# BitFury.net
KiCad netlist of a schematic drawn in Altium Designer
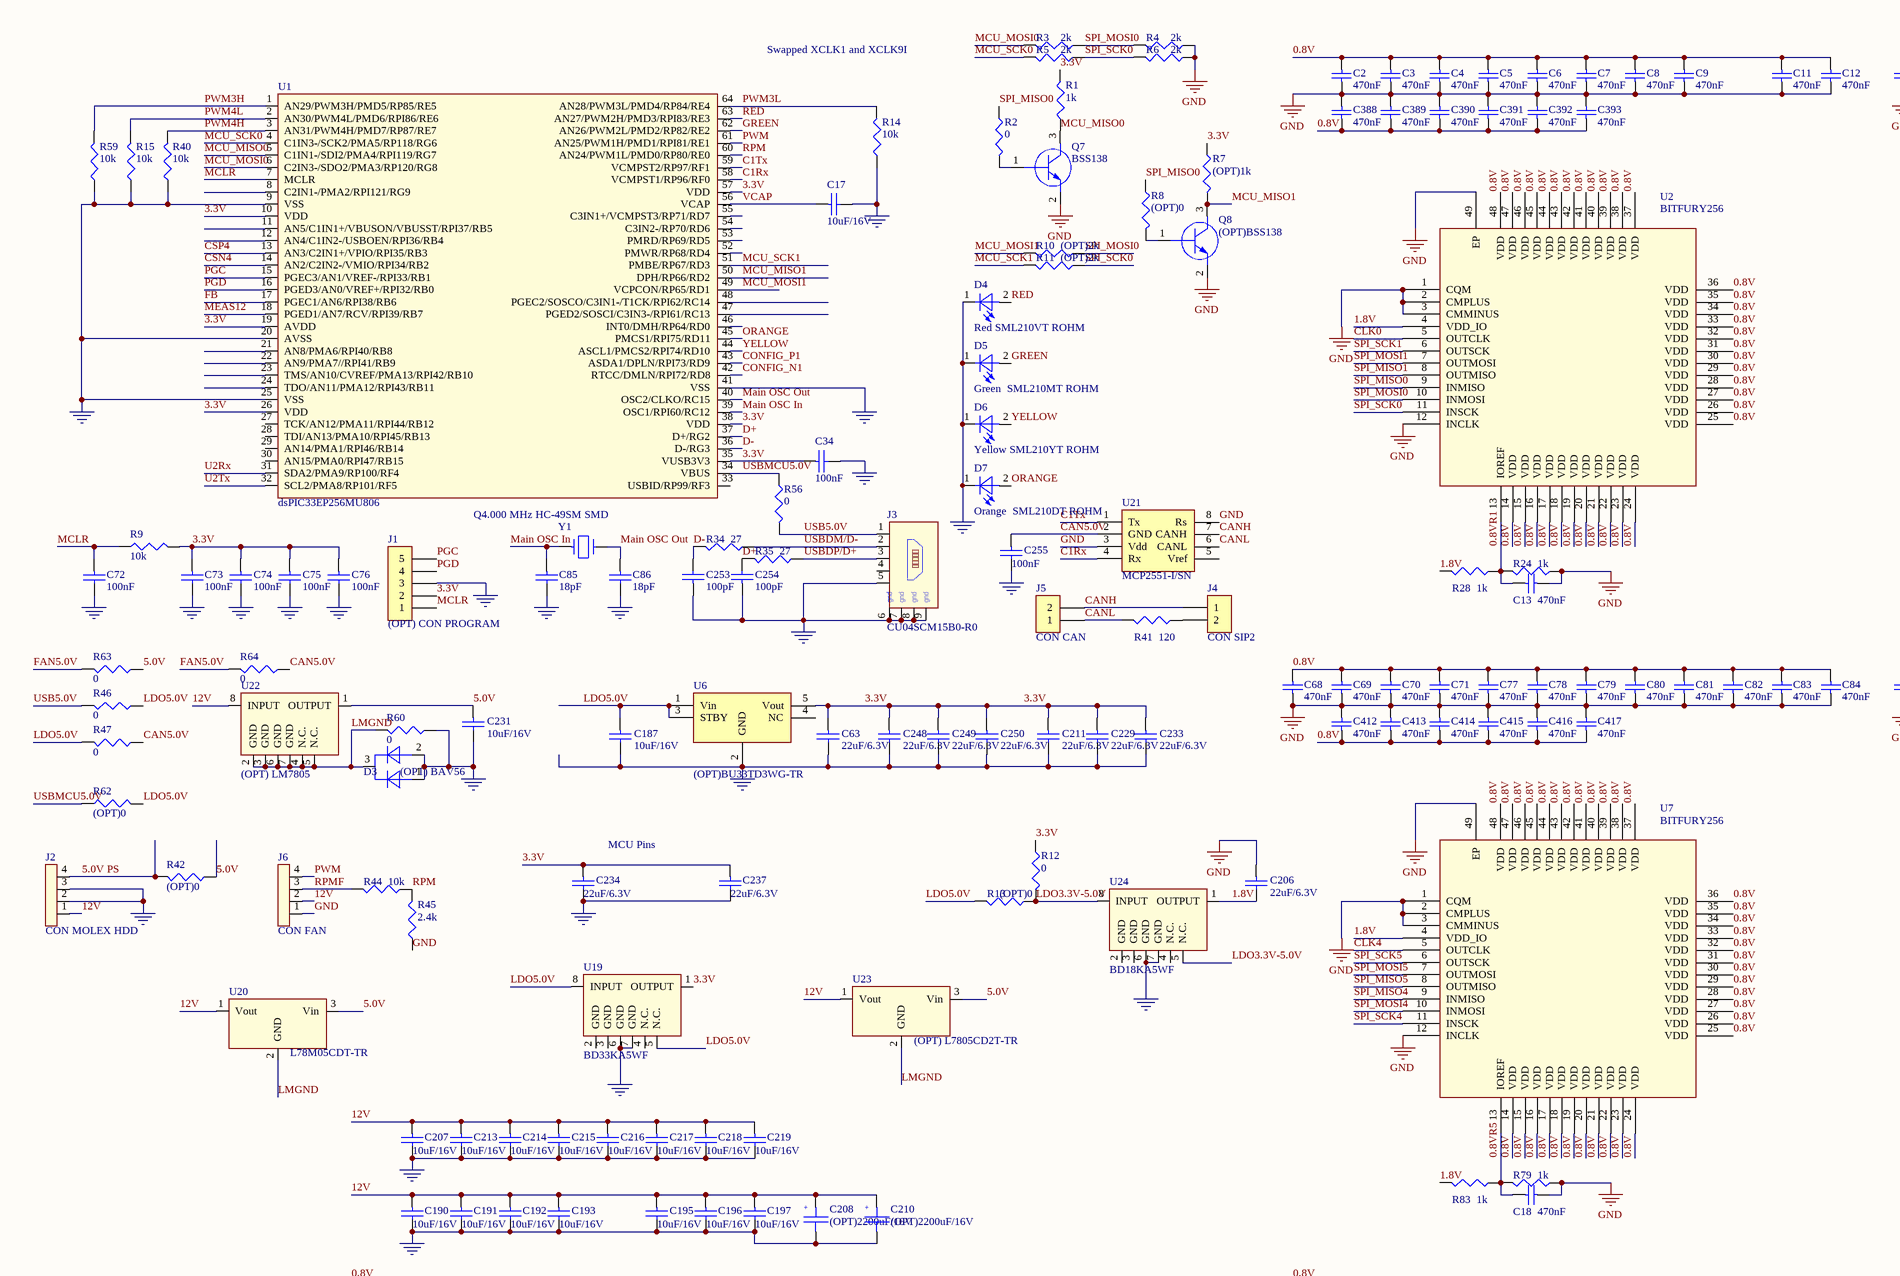
[diagram p0: BitFury.SchDoc, top left]
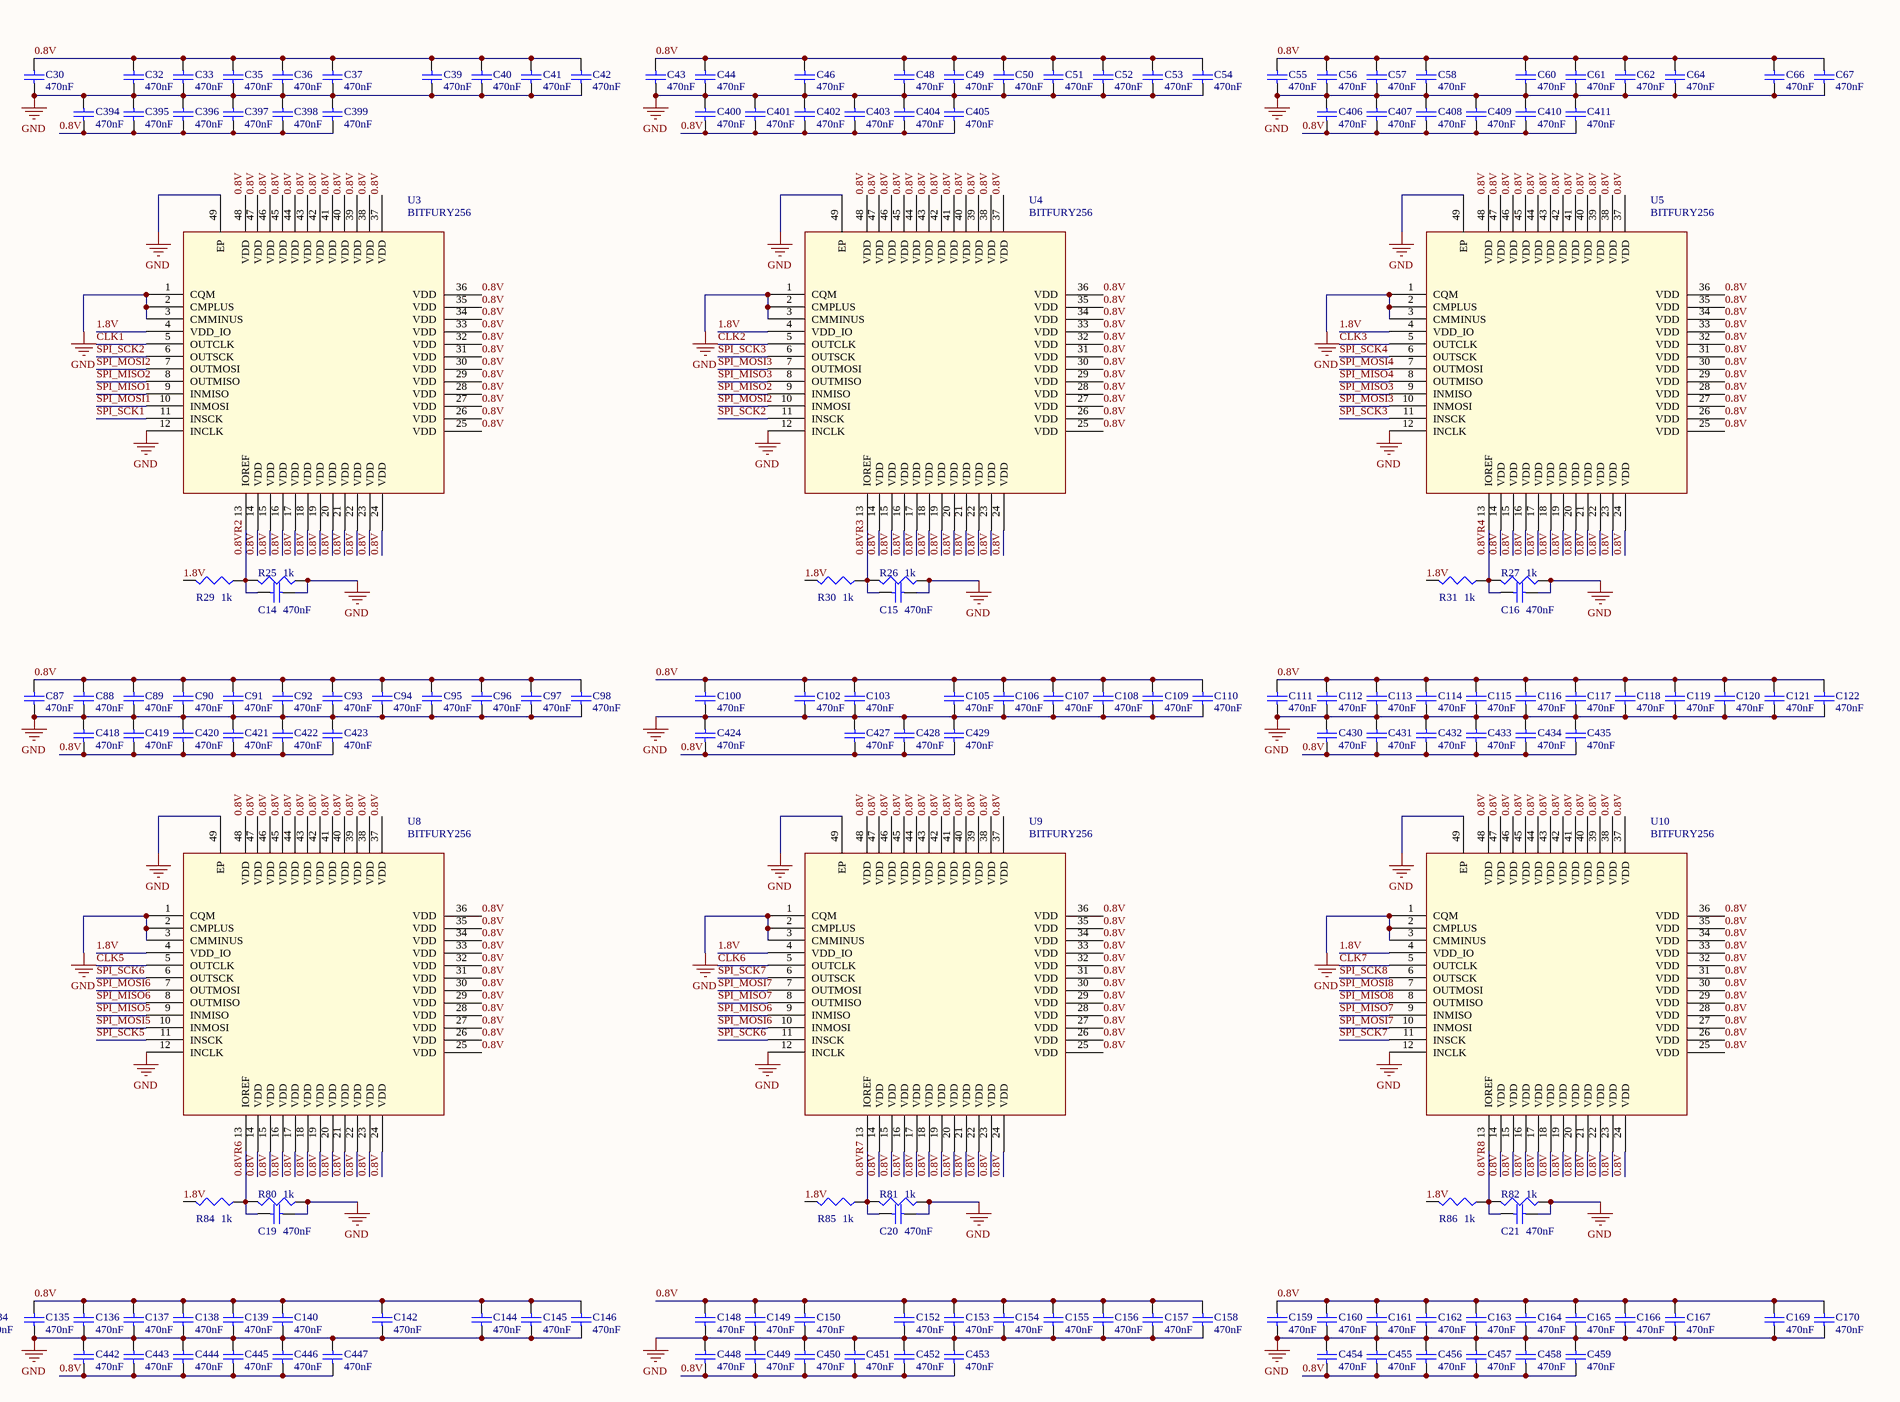
[diagram p1: BitFury.SchDoc, top right]
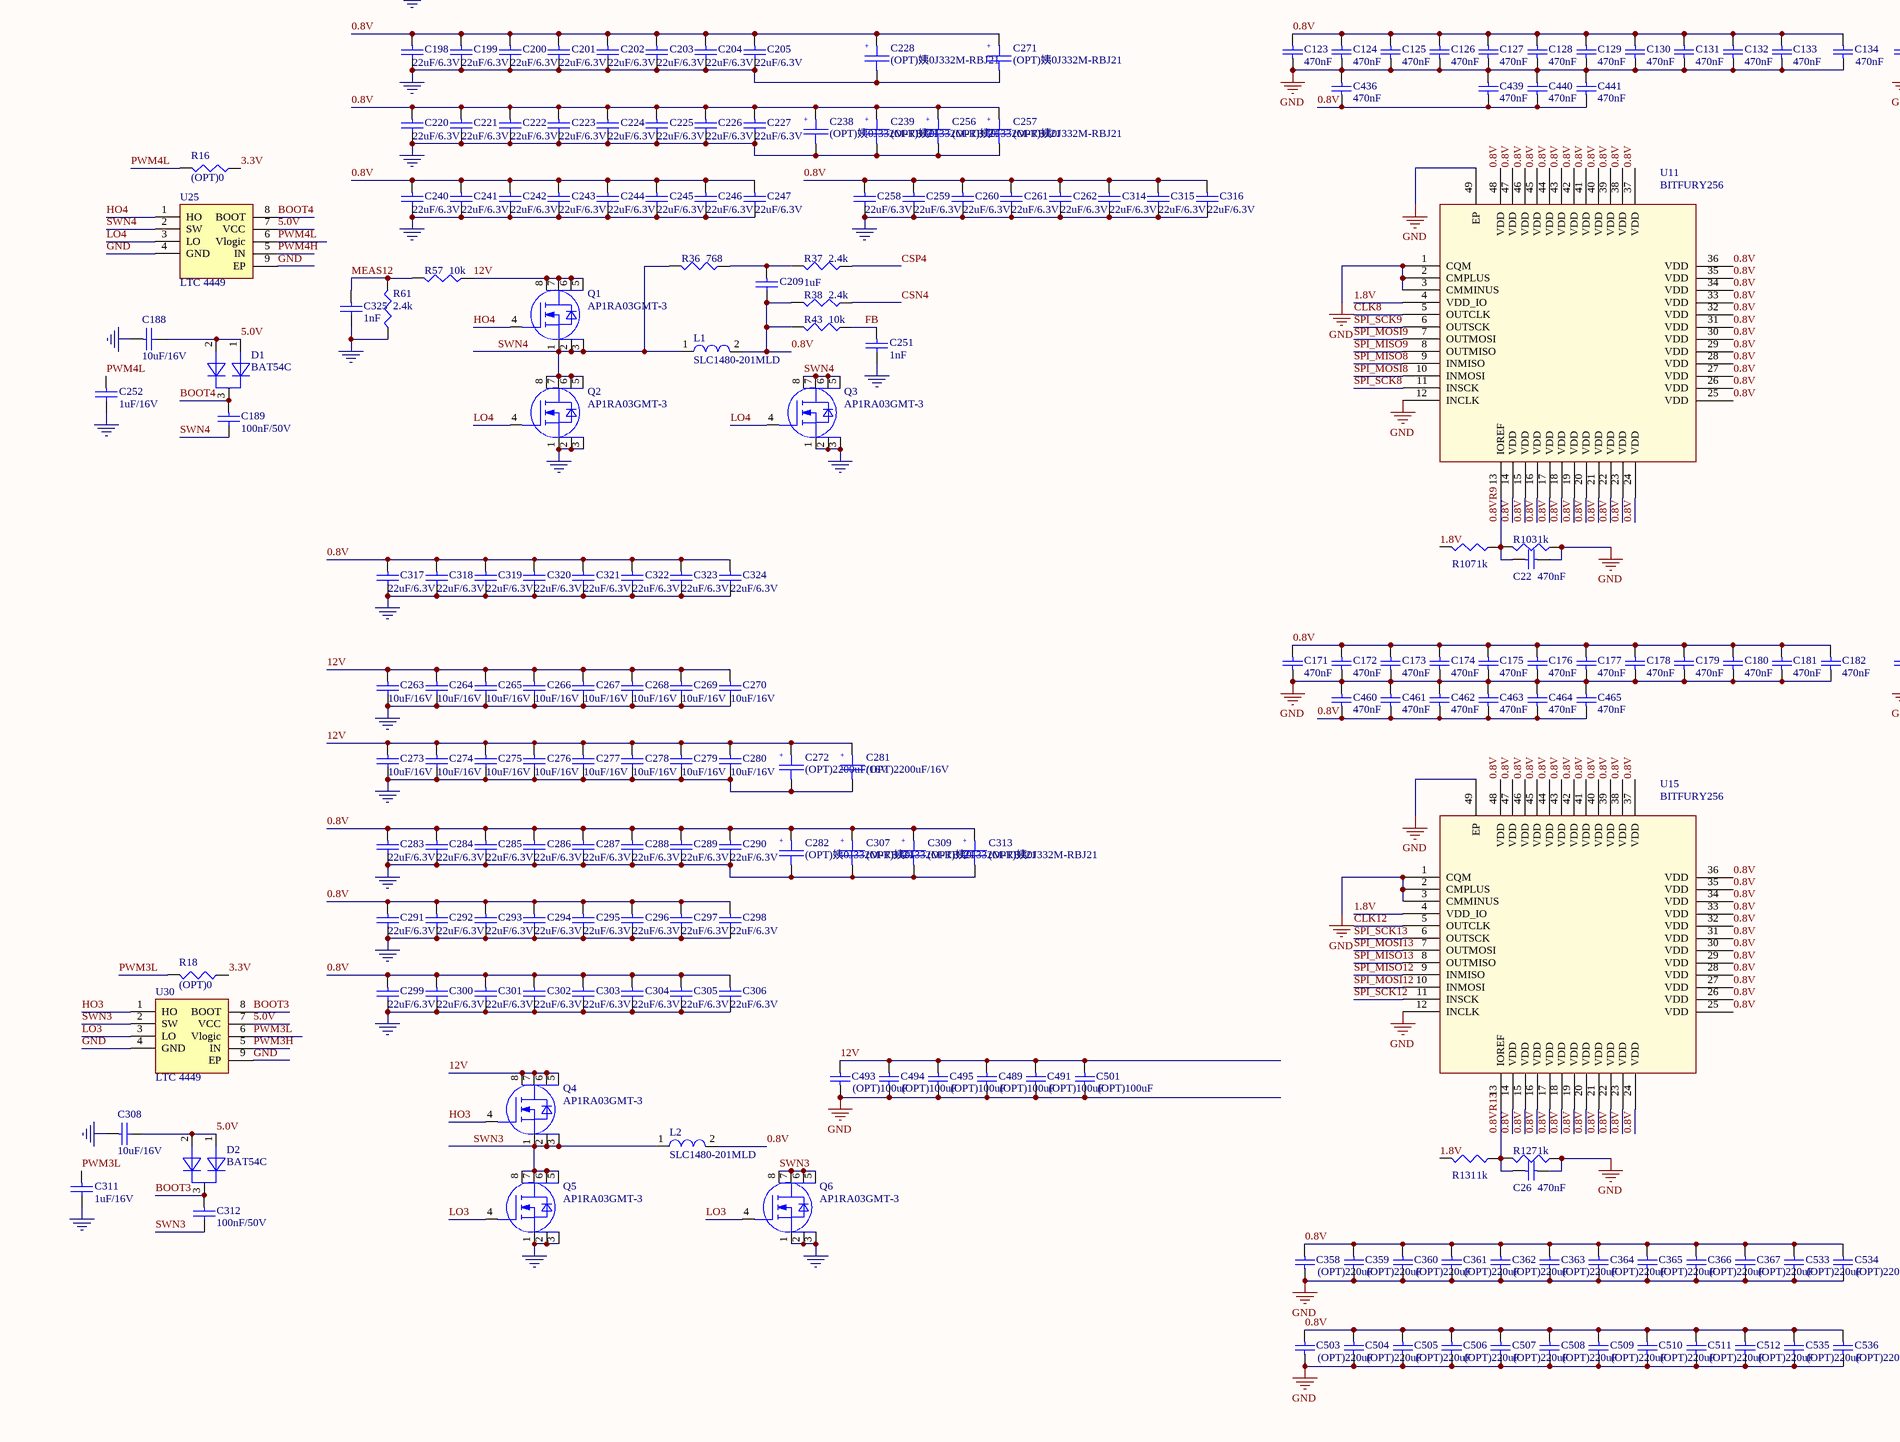
[diagram p2: BitFury.SchDoc, bottom left]
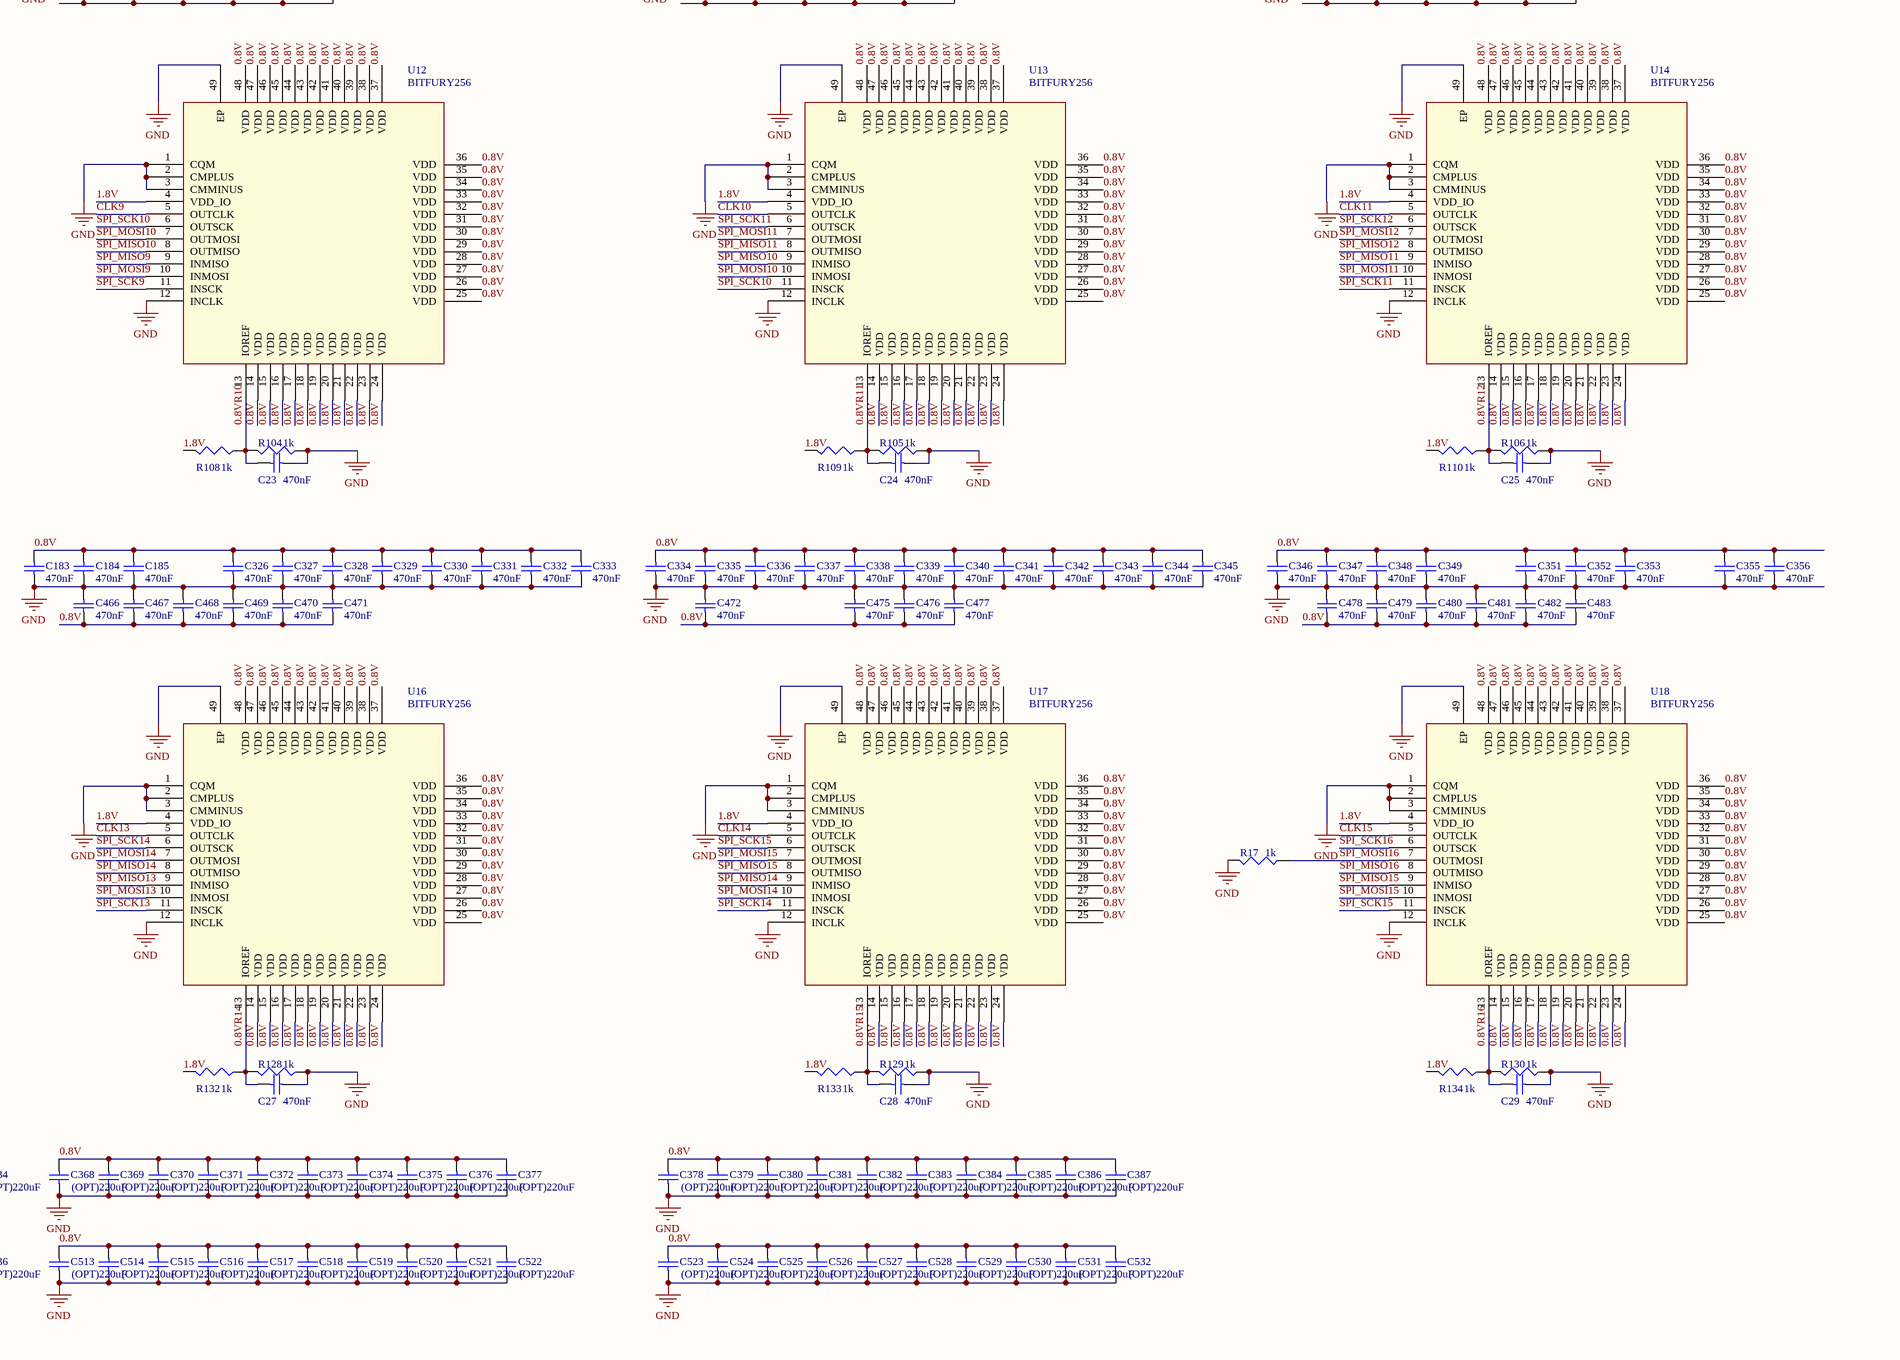
[diagram p3: BitFury.SchDoc, bottom right]

(export (version "E")
  (design (tool "Eeschema 10.0.6"))
  (components
    (comp (ref "C2")
      (value "470nF")
      (footprint "SMD_0603_CAPC1608X80N")
      (description "Capacitor (Semiconductor SIM Model)")
      (fields (field (name "PUBLISHER") "Altium Limited"))
      (libsource (lib "Miscellaneous Devices") (part "Cap Semi"))
    )
    (comp (ref "C3")
      (value "470nF")
      (footprint "SMD_0603_CAPC1608X80N")
      (description "Capacitor (Semiconductor SIM Model)")
      (fields (field (name "PUBLISHER") "Altium Limited"))
      (libsource (lib "Miscellaneous Devices") (part "Cap Semi"))
    )
    (comp (ref "C4")
      (value "470nF")
      (footprint "SMD_0603_CAPC1608X80N")
      (description "Capacitor (Semiconductor SIM Model)")
      (fields (field (name "PUBLISHER") "Altium Limited"))
      (libsource (lib "Miscellaneous Devices") (part "Cap Semi"))
    )
    (comp (ref "C5")
      (value "470nF")
      (footprint "SMD_0603_CAPC1608X80N")
      (description "Capacitor (Semiconductor SIM Model)")
      (fields (field (name "PUBLISHER") "Altium Limited"))
      (libsource (lib "Miscellaneous Devices") (part "Cap Semi"))
    )
    (comp (ref "C6")
      (value "470nF")
      (footprint "SMD_0603_CAPC1608X80N")
      (description "Capacitor (Semiconductor SIM Model)")
      (fields (field (name "PUBLISHER") "Altium Limited"))
      (libsource (lib "Miscellaneous Devices") (part "Cap Semi"))
    )
    (comp (ref "C7")
      (value "470nF")
      (footprint "SMD_0603_CAPC1608X80N")
      (description "Capacitor (Semiconductor SIM Model)")
      (fields (field (name "PUBLISHER") "Altium Limited"))
      (libsource (lib "Miscellaneous Devices") (part "Cap Semi"))
    )
    (comp (ref "C8")
      (value "470nF")
      (footprint "SMD_0603_CAPC1608X80N")
      (description "Capacitor (Semiconductor SIM Model)")
      (fields (field (name "PUBLISHER") "Altium Limited"))
      (libsource (lib "Miscellaneous Devices") (part "Cap Semi"))
    )
    (comp (ref "C9")
      (value "470nF")
      (footprint "SMD_0603_CAPC1608X80N")
      (description "Capacitor (Semiconductor SIM Model)")
      (fields (field (name "PUBLISHER") "Altium Limited"))
      (libsource (lib "Miscellaneous Devices") (part "Cap Semi"))
    )
    (comp (ref "C11")
      (value "470nF")
      (footprint "SMD_0603_CAPC1608X80N")
      (description "Capacitor (Semiconductor SIM Model)")
      (fields (field (name "PUBLISHER") "Altium Limited"))
      (libsource (lib "Miscellaneous Devices") (part "Cap Semi"))
    )
    (comp (ref "C12")
      (value "470nF")
      (footprint "SMD_0603_CAPC1608X80N")
      (description "Capacitor (Semiconductor SIM Model)")
      (fields (field (name "PUBLISHER") "Altium Limited"))
      (libsource (lib "Miscellaneous Devices") (part "Cap Semi"))
    )
    (comp (ref "C13")
      (value "470nF")
      (footprint "SMD_0603_CAPC1608X80N")
      (description "Capacitor (Semiconductor SIM Model)")
      (fields (field (name "PUBLISHER") "Altium Limited"))
      (libsource (lib "Miscellaneous Devices") (part "Cap Semi"))
    )
    (comp (ref "C14")
      (value "470nF")
      (footprint "SMD_0603_CAPC1608X80N")
      (description "Capacitor (Semiconductor SIM Model)")
      (fields (field (name "PUBLISHER") "Altium Limited"))
      (libsource (lib "Miscellaneous Devices") (part "Cap Semi"))
    )
    (comp (ref "C15")
      (value "470nF")
      (footprint "SMD_0603_CAPC1608X80N")
      (description "Capacitor (Semiconductor SIM Model)")
      (fields (field (name "PUBLISHER") "Altium Limited"))
      (libsource (lib "Miscellaneous Devices") (part "Cap Semi"))
    )
    (comp (ref "C16")
      (value "470nF")
      (footprint "SMD_0603_CAPC1608X80N")
      (description "Capacitor (Semiconductor SIM Model)")
      (fields (field (name "PUBLISHER") "Altium Limited"))
      (libsource (lib "Miscellaneous Devices") (part "Cap Semi"))
    )
    (comp (ref "C17")
      (value "10uF/16V")
      (footprint "SMD_0805_CAPC2012X145N")
      (description "Capacitor")
      (libsource (lib "*") (part "CAP"))
    )
    (comp (ref "C18")
      (value "470nF")
      (footprint "SMD_0603_CAPC1608X80N")
      (description "Capacitor (Semiconductor SIM Model)")
      (fields (field (name "PUBLISHER") "Altium Limited"))
      (libsource (lib "Miscellaneous Devices") (part "Cap Semi"))
    )
    (comp (ref "C19")
      (value "470nF")
      (footprint "SMD_0603_CAPC1608X80N")
      (description "Capacitor (Semiconductor SIM Model)")
      (fields (field (name "PUBLISHER") "Altium Limited"))
      (libsource (lib "Miscellaneous Devices") (part "Cap Semi"))
    )
    (comp (ref "C20")
      (value "470nF")
      (footprint "SMD_0603_CAPC1608X80N")
      (description "Capacitor (Semiconductor SIM Model)")
      (fields (field (name "PUBLISHER") "Altium Limited"))
      (libsource (lib "Miscellaneous Devices") (part "Cap Semi"))
    )
    (comp (ref "C21")
      (value "470nF")
      (footprint "SMD_0603_CAPC1608X80N")
      (description "Capacitor (Semiconductor SIM Model)")
      (fields (field (name "PUBLISHER") "Altium Limited"))
      (libsource (lib "Miscellaneous Devices") (part "Cap Semi"))
    )
    (comp (ref "C22")
      (value "470nF")
      (footprint "SMD_0603_CAPC1608X80N")
      (description "Capacitor (Semiconductor SIM Model)")
      (fields (field (name "PUBLISHER") "Altium Limited"))
      (libsource (lib "Miscellaneous Devices") (part "Cap Semi"))
    )
    (comp (ref "C23")
      (value "470nF")
      (footprint "SMD_0603_CAPC1608X80N")
      (description "Capacitor (Semiconductor SIM Model)")
      (fields (field (name "PUBLISHER") "Altium Limited"))
      (libsource (lib "Miscellaneous Devices") (part "Cap Semi"))
    )
    (comp (ref "C24")
      (value "470nF")
      (footprint "SMD_0603_CAPC1608X80N")
      (description "Capacitor (Semiconductor SIM Model)")
      (fields (field (name "PUBLISHER") "Altium Limited"))
      (libsource (lib "Miscellaneous Devices") (part "Cap Semi"))
    )
    (comp (ref "C25")
      (value "470nF")
      (footprint "SMD_0603_CAPC1608X80N")
      (description "Capacitor (Semiconductor SIM Model)")
      (fields (field (name "PUBLISHER") "Altium Limited"))
      (libsource (lib "Miscellaneous Devices") (part "Cap Semi"))
    )
    (comp (ref "C26")
      (value "470nF")
      (footprint "SMD_0603_CAPC1608X80N")
      (description "Capacitor (Semiconductor SIM Model)")
      (fields (field (name "PUBLISHER") "Altium Limited"))
      (libsource (lib "Miscellaneous Devices") (part "Cap Semi"))
    )
    (comp (ref "C27")
      (value "470nF")
      (footprint "SMD_0603_CAPC1608X80N")
      (description "Capacitor (Semiconductor SIM Model)")
      (fields (field (name "PUBLISHER") "Altium Limited"))
      (libsource (lib "Miscellaneous Devices") (part "Cap Semi"))
    )
    (comp (ref "C28")
      (value "470nF")
      (footprint "SMD_0603_CAPC1608X80N")
      (description "Capacitor (Semiconductor SIM Model)")
      (fields (field (name "PUBLISHER") "Altium Limited"))
      (libsource (lib "Miscellaneous Devices") (part "Cap Semi"))
    )
    (comp (ref "C29")
      (value "470nF")
      (footprint "SMD_0603_CAPC1608X80N")
      (description "Capacitor (Semiconductor SIM Model)")
      (fields (field (name "PUBLISHER") "Altium Limited"))
      (libsource (lib "Miscellaneous Devices") (part "Cap Semi"))
    )
    (comp (ref "C30")
      (value "470nF")
      (footprint "SMD_0603_CAPC1608X80N")
      (description "Capacitor (Semiconductor SIM Model)")
      (fields (field (name "PUBLISHER") "Altium Limited"))
      (libsource (lib "Miscellaneous Devices") (part "Cap Semi"))
    )
    (comp (ref "C32")
      (value "470nF")
      (footprint "SMD_0603_CAPC1608X80N")
      (description "Capacitor (Semiconductor SIM Model)")
      (fields (field (name "PUBLISHER") "Altium Limited"))
      (libsource (lib "Miscellaneous Devices") (part "Cap Semi"))
    )
    (comp (ref "C33")
      (value "470nF")
      (footprint "SMD_0603_CAPC1608X80N")
      (description "Capacitor (Semiconductor SIM Model)")
      (fields (field (name "PUBLISHER") "Altium Limited"))
      (libsource (lib "Miscellaneous Devices") (part "Cap Semi"))
    )
    (comp (ref "C34")
      (value "100nF")
      (footprint "SMD_0603_CAPC1608X80N")
      (description "Capacitor")
      (libsource (lib "*") (part "CAP"))
    )
    (comp (ref "C35")
      (value "470nF")
      (footprint "SMD_0603_CAPC1608X80N")
      (description "Capacitor (Semiconductor SIM Model)")
      (fields (field (name "PUBLISHER") "Altium Limited"))
      (libsource (lib "Miscellaneous Devices") (part "Cap Semi"))
    )
    (comp (ref "C36")
      (value "470nF")
      (footprint "SMD_0603_CAPC1608X80N")
      (description "Capacitor (Semiconductor SIM Model)")
      (fields (field (name "PUBLISHER") "Altium Limited"))
      (libsource (lib "Miscellaneous Devices") (part "Cap Semi"))
    )
    (comp (ref "C37")
      (value "470nF")
      (footprint "SMD_0603_CAPC1608X80N")
      (description "Capacitor (Semiconductor SIM Model)")
      (fields (field (name "PUBLISHER") "Altium Limited"))
      (libsource (lib "Miscellaneous Devices") (part "Cap Semi"))
    )
    (comp (ref "C39")
      (value "470nF")
      (footprint "SMD_0603_CAPC1608X80N")
      (description "Capacitor (Semiconductor SIM Model)")
      (fields (field (name "PUBLISHER") "Altium Limited"))
      (libsource (lib "Miscellaneous Devices") (part "Cap Semi"))
    )
    (comp (ref "C40")
      (value "470nF")
      (footprint "SMD_0603_CAPC1608X80N")
      (description "Capacitor (Semiconductor SIM Model)")
      (fields (field (name "PUBLISHER") "Altium Limited"))
      (libsource (lib "Miscellaneous Devices") (part "Cap Semi"))
    )
    (comp (ref "C41")
      (value "470nF")
      (footprint "SMD_0603_CAPC1608X80N")
      (description "Capacitor (Semiconductor SIM Model)")
      (fields (field (name "PUBLISHER") "Altium Limited"))
      (libsource (lib "Miscellaneous Devices") (part "Cap Semi"))
    )
    (comp (ref "C42")
      (value "470nF")
      (footprint "SMD_0603_CAPC1608X80N")
      (description "Capacitor (Semiconductor SIM Model)")
      (fields (field (name "PUBLISHER") "Altium Limited"))
      (libsource (lib "Miscellaneous Devices") (part "Cap Semi"))
    )
    (comp (ref "C43")
      (value "470nF")
      (footprint "SMD_0603_CAPC1608X80N")
      (description "Capacitor (Semiconductor SIM Model)")
      (fields (field (name "PUBLISHER") "Altium Limited"))
      (libsource (lib "Miscellaneous Devices") (part "Cap Semi"))
    )
    (comp (ref "C44")
      (value "470nF")
      (footprint "SMD_0603_CAPC1608X80N")
      (description "Capacitor (Semiconductor SIM Model)")
      (fields (field (name "PUBLISHER") "Altium Limited"))
      (libsource (lib "Miscellaneous Devices") (part "Cap Semi"))
    )
    (comp (ref "C46")
      (value "470nF")
      (footprint "SMD_0603_CAPC1608X80N")
      (description "Capacitor (Semiconductor SIM Model)")
      (fields (field (name "PUBLISHER") "Altium Limited"))
      (libsource (lib "Miscellaneous Devices") (part "Cap Semi"))
    )
    (comp (ref "C48")
      (value "470nF")
      (footprint "SMD_0603_CAPC1608X80N")
      (description "Capacitor (Semiconductor SIM Model)")
      (fields (field (name "PUBLISHER") "Altium Limited"))
      (libsource (lib "Miscellaneous Devices") (part "Cap Semi"))
    )
    (comp (ref "C49")
      (value "470nF")
      (footprint "SMD_0603_CAPC1608X80N")
      (description "Capacitor (Semiconductor SIM Model)")
      (fields (field (name "PUBLISHER") "Altium Limited"))
      (libsource (lib "Miscellaneous Devices") (part "Cap Semi"))
    )
    (comp (ref "C50")
      (value "470nF")
      (footprint "SMD_0603_CAPC1608X80N")
      (description "Capacitor (Semiconductor SIM Model)")
      (fields (field (name "PUBLISHER") "Altium Limited"))
      (libsource (lib "Miscellaneous Devices") (part "Cap Semi"))
    )
    (comp (ref "C51")
      (value "470nF")
      (footprint "SMD_0603_CAPC1608X80N")
      (description "Capacitor (Semiconductor SIM Model)")
      (fields (field (name "PUBLISHER") "Altium Limited"))
      (libsource (lib "Miscellaneous Devices") (part "Cap Semi"))
    )
    (comp (ref "C52")
      (value "470nF")
      (footprint "SMD_0603_CAPC1608X80N")
      (description "Capacitor (Semiconductor SIM Model)")
      (fields (field (name "PUBLISHER") "Altium Limited"))
      (libsource (lib "Miscellaneous Devices") (part "Cap Semi"))
    )
    (comp (ref "C53")
      (value "470nF")
      (footprint "SMD_0603_CAPC1608X80N")
      (description "Capacitor (Semiconductor SIM Model)")
      (fields (field (name "PUBLISHER") "Altium Limited"))
      (libsource (lib "Miscellaneous Devices") (part "Cap Semi"))
    )
    (comp (ref "C54")
      (value "470nF")
      (footprint "SMD_0603_CAPC1608X80N")
      (description "Capacitor (Semiconductor SIM Model)")
      (fields (field (name "PUBLISHER") "Altium Limited"))
      (libsource (lib "Miscellaneous Devices") (part "Cap Semi"))
    )
    (comp (ref "C55")
      (value "470nF")
      (footprint "SMD_0603_CAPC1608X80N")
      (description "Capacitor (Semiconductor SIM Model)")
      (fields (field (name "PUBLISHER") "Altium Limited"))
      (libsource (lib "Miscellaneous Devices") (part "Cap Semi"))
    )
    (comp (ref "C56")
      (value "470nF")
      (footprint "SMD_0603_CAPC1608X80N")
      (description "Capacitor (Semiconductor SIM Model)")
      (fields (field (name "PUBLISHER") "Altium Limited"))
      (libsource (lib "Miscellaneous Devices") (part "Cap Semi"))
    )
    (comp (ref "C57")
      (value "470nF")
      (footprint "SMD_0603_CAPC1608X80N")
      (description "Capacitor (Semiconductor SIM Model)")
      (fields (field (name "PUBLISHER") "Altium Limited"))
      (libsource (lib "Miscellaneous Devices") (part "Cap Semi"))
    )
    (comp (ref "C58")
      (value "470nF")
      (footprint "SMD_0603_CAPC1608X80N")
      (description "Capacitor (Semiconductor SIM Model)")
      (fields (field (name "PUBLISHER") "Altium Limited"))
      (libsource (lib "Miscellaneous Devices") (part "Cap Semi"))
    )
    (comp (ref "C60")
      (value "470nF")
      (footprint "SMD_0603_CAPC1608X80N")
      (description "Capacitor (Semiconductor SIM Model)")
      (fields (field (name "PUBLISHER") "Altium Limited"))
      (libsource (lib "Miscellaneous Devices") (part "Cap Semi"))
    )
    (comp (ref "C61")
      (value "470nF")
      (footprint "SMD_0603_CAPC1608X80N")
      (description "Capacitor (Semiconductor SIM Model)")
      (fields (field (name "PUBLISHER") "Altium Limited"))
      (libsource (lib "Miscellaneous Devices") (part "Cap Semi"))
    )
    (comp (ref "C62")
      (value "470nF")
      (footprint "SMD_0603_CAPC1608X80N")
      (description "Capacitor (Semiconductor SIM Model)")
      (fields (field (name "PUBLISHER") "Altium Limited"))
      (libsource (lib "Miscellaneous Devices") (part "Cap Semi"))
    )
    (comp (ref "C63")
      (value "22uF/6.3V")
      (footprint "SMD_0805_CAPC2012X145N")
      (description "Capacitor")
      (libsource (lib "*") (part "CAP"))
    )
    (comp (ref "C64")
      (value "470nF")
      (footprint "SMD_0603_CAPC1608X80N")
      (description "Capacitor (Semiconductor SIM Model)")
      (fields (field (name "PUBLISHER") "Altium Limited"))
      (libsource (lib "Miscellaneous Devices") (part "Cap Semi"))
    )
    (comp (ref "C66")
      (value "470nF")
      (footprint "SMD_0603_CAPC1608X80N")
      (description "Capacitor (Semiconductor SIM Model)")
      (fields (field (name "PUBLISHER") "Altium Limited"))
      (libsource (lib "Miscellaneous Devices") (part "Cap Semi"))
    )
    (comp (ref "C67")
      (value "470nF")
      (footprint "SMD_0603_CAPC1608X80N")
      (description "Capacitor (Semiconductor SIM Model)")
      (fields (field (name "PUBLISHER") "Altium Limited"))
      (libsource (lib "Miscellaneous Devices") (part "Cap Semi"))
    )
    (comp (ref "C68")
      (value "470nF")
      (footprint "SMD_0603_CAPC1608X80N")
      (description "Capacitor (Semiconductor SIM Model)")
      (fields (field (name "PUBLISHER") "Altium Limited"))
      (libsource (lib "Miscellaneous Devices") (part "Cap Semi"))
    )
    (comp (ref "C69")
      (value "470nF")
      (footprint "SMD_0603_CAPC1608X80N")
      (description "Capacitor (Semiconductor SIM Model)")
      (fields (field (name "PUBLISHER") "Altium Limited"))
      (libsource (lib "Miscellaneous Devices") (part "Cap Semi"))
    )
    (comp (ref "C70")
      (value "470nF")
      (footprint "SMD_0603_CAPC1608X80N")
      (description "Capacitor (Semiconductor SIM Model)")
      (fields (field (name "PUBLISHER") "Altium Limited"))
      (libsource (lib "Miscellaneous Devices") (part "Cap Semi"))
    )
    (comp (ref "C71")
      (value "470nF")
      (footprint "SMD_0603_CAPC1608X80N")
      (description "Capacitor (Semiconductor SIM Model)")
      (fields (field (name "PUBLISHER") "Altium Limited"))
      (libsource (lib "Miscellaneous Devices") (part "Cap Semi"))
    )
    (comp (ref "C72")
      (value "100nF")
      (footprint "SMD_0603_CAPC1608X80N")
      (description "Capacitor")
      (libsource (lib "*") (part "CAP"))
    )
    (comp (ref "C73")
      (value "100nF")
      (footprint "SMD_0603_CAPC1608X80N")
      (description "Capacitor")
      (libsource (lib "*") (part "CAP"))
    )
    (comp (ref "C74")
      (value "100nF")
      (footprint "SMD_0603_CAPC1608X80N")
      (description "Capacitor")
      (libsource (lib "*") (part "CAP"))
    )
    (comp (ref "C75")
      (value "100nF")
      (footprint "SMD_0603_CAPC1608X80N")
      (description "Capacitor")
      (libsource (lib "*") (part "CAP"))
    )
    (comp (ref "C76")
      (value "100nF")
      (footprint "SMD_0603_CAPC1608X80N")
      (description "Capacitor")
      (libsource (lib "*") (part "CAP"))
    )
    (comp (ref "C77")
      (value "470nF")
      (footprint "SMD_0603_CAPC1608X80N")
      (description "Capacitor (Semiconductor SIM Model)")
      (fields (field (name "PUBLISHER") "Altium Limited"))
      (libsource (lib "Miscellaneous Devices") (part "Cap Semi"))
    )
    (comp (ref "C78")
      (value "470nF")
      (footprint "SMD_0603_CAPC1608X80N")
      (description "Capacitor (Semiconductor SIM Model)")
      (fields (field (name "PUBLISHER") "Altium Limited"))
      (libsource (lib "Miscellaneous Devices") (part "Cap Semi"))
    )
    (comp (ref "C79")
      (value "470nF")
      (footprint "SMD_0603_CAPC1608X80N")
      (description "Capacitor (Semiconductor SIM Model)")
      (fields (field (name "PUBLISHER") "Altium Limited"))
      (libsource (lib "Miscellaneous Devices") (part "Cap Semi"))
    )
    (comp (ref "C80")
      (value "470nF")
      (footprint "SMD_0603_CAPC1608X80N")
      (description "Capacitor (Semiconductor SIM Model)")
      (fields (field (name "PUBLISHER") "Altium Limited"))
      (libsource (lib "Miscellaneous Devices") (part "Cap Semi"))
    )
    (comp (ref "C81")
      (value "470nF")
      (footprint "SMD_0603_CAPC1608X80N")
      (description "Capacitor (Semiconductor SIM Model)")
      (fields (field (name "PUBLISHER") "Altium Limited"))
      (libsource (lib "Miscellaneous Devices") (part "Cap Semi"))
    )
    (comp (ref "C82")
      (value "470nF")
      (footprint "SMD_0603_CAPC1608X80N")
      (description "Capacitor (Semiconductor SIM Model)")
      (fields (field (name "PUBLISHER") "Altium Limited"))
      (libsource (lib "Miscellaneous Devices") (part "Cap Semi"))
    )
    (comp (ref "C83")
      (value "470nF")
      (footprint "SMD_0603_CAPC1608X80N")
      (description "Capacitor (Semiconductor SIM Model)")
      (fields (field (name "PUBLISHER") "Altium Limited"))
      (libsource (lib "Miscellaneous Devices") (part "Cap Semi"))
    )
    (comp (ref "C84")
      (value "470nF")
      (footprint "SMD_0603_CAPC1608X80N")
      (description "Capacitor (Semiconductor SIM Model)")
      (fields (field (name "PUBLISHER") "Altium Limited"))
      (libsource (lib "Miscellaneous Devices") (part "Cap Semi"))
    )
    (comp (ref "C85")
      (value "18pF")
      (footprint "SMD_0603_CAPC1608X80N")
      (description "Capacitor")
      (libsource (lib "*") (part "CAP"))
    )
    (comp (ref "C86")
      (value "18pF")
      (footprint "SMD_0603_CAPC1608X80N")
      (description "Capacitor")
      (libsource (lib "*") (part "CAP"))
    )
    (comp (ref "C87")
      (value "470nF")
      (footprint "SMD_0603_CAPC1608X80N")
      (description "Capacitor (Semiconductor SIM Model)")
      (fields (field (name "PUBLISHER") "Altium Limited"))
      (libsource (lib "Miscellaneous Devices") (part "Cap Semi"))
    )
    (comp (ref "C88")
      (value "470nF")
      (footprint "SMD_0603_CAPC1608X80N")
      (description "Capacitor (Semiconductor SIM Model)")
      (fields (field (name "PUBLISHER") "Altium Limited"))
      (libsource (lib "Miscellaneous Devices") (part "Cap Semi"))
    )
    (comp (ref "C89")
      (value "470nF")
      (footprint "SMD_0603_CAPC1608X80N")
      (description "Capacitor (Semiconductor SIM Model)")
      (fields (field (name "PUBLISHER") "Altium Limited"))
      (libsource (lib "Miscellaneous Devices") (part "Cap Semi"))
    )
    (comp (ref "C90")
      (value "470nF")
      (footprint "SMD_0603_CAPC1608X80N")
      (description "Capacitor (Semiconductor SIM Model)")
      (fields (field (name "PUBLISHER") "Altium Limited"))
      (libsource (lib "Miscellaneous Devices") (part "Cap Semi"))
    )
    (comp (ref "C91")
      (value "470nF")
      (footprint "SMD_0603_CAPC1608X80N")
      (description "Capacitor (Semiconductor SIM Model)")
      (fields (field (name "PUBLISHER") "Altium Limited"))
      (libsource (lib "Miscellaneous Devices") (part "Cap Semi"))
    )
    (comp (ref "C92")
      (value "470nF")
      (footprint "SMD_0603_CAPC1608X80N")
      (description "Capacitor (Semiconductor SIM Model)")
      (fields (field (name "PUBLISHER") "Altium Limited"))
      (libsource (lib "Miscellaneous Devices") (part "Cap Semi"))
    )
    (comp (ref "C93")
      (value "470nF")
      (footprint "SMD_0603_CAPC1608X80N")
      (description "Capacitor (Semiconductor SIM Model)")
      (fields (field (name "PUBLISHER") "Altium Limited"))
      (libsource (lib "Miscellaneous Devices") (part "Cap Semi"))
    )
    (comp (ref "C94")
      (value "470nF")
      (footprint "SMD_0603_CAPC1608X80N")
      (description "Capacitor (Semiconductor SIM Model)")
      (fields (field (name "PUBLISHER") "Altium Limited"))
      (libsource (lib "Miscellaneous Devices") (part "Cap Semi"))
    )
    (comp (ref "C95")
      (value "470nF")
      (footprint "SMD_0603_CAPC1608X80N")
      (description "Capacitor (Semiconductor SIM Model)")
      (fields (field (name "PUBLISHER") "Altium Limited"))
      (libsource (lib "Miscellaneous Devices") (part "Cap Semi"))
    )
    (comp (ref "C96")
      (value "470nF")
      (footprint "SMD_0603_CAPC1608X80N")
      (description "Capacitor (Semiconductor SIM Model)")
      (fields (field (name "PUBLISHER") "Altium Limited"))
      (libsource (lib "Miscellaneous Devices") (part "Cap Semi"))
    )
    (comp (ref "C97")
      (value "470nF")
      (footprint "SMD_0603_CAPC1608X80N")
      (description "Capacitor (Semiconductor SIM Model)")
      (fields (field (name "PUBLISHER") "Altium Limited"))
      (libsource (lib "Miscellaneous Devices") (part "Cap Semi"))
    )
    (comp (ref "C98")
      (value "470nF")
      (footprint "SMD_0603_CAPC1608X80N")
      (description "Capacitor (Semiconductor SIM Model)")
      (fields (field (name "PUBLISHER") "Altium Limited"))
      (libsource (lib "Miscellaneous Devices") (part "Cap Semi"))
    )
    (comp (ref "C100")
      (value "470nF")
      (footprint "SMD_0603_CAPC1608X80N")
      (description "Capacitor (Semiconductor SIM Model)")
      (fields (field (name "PUBLISHER") "Altium Limited"))
      (libsource (lib "Miscellaneous Devices") (part "Cap Semi"))
    )
    (comp (ref "C102")
      (value "470nF")
      (footprint "SMD_0603_CAPC1608X80N")
      (description "Capacitor (Semiconductor SIM Model)")
      (fields (field (name "PUBLISHER") "Altium Limited"))
      (libsource (lib "Miscellaneous Devices") (part "Cap Semi"))
    )
    (comp (ref "C103")
      (value "470nF")
      (footprint "SMD_0603_CAPC1608X80N")
      (description "Capacitor (Semiconductor SIM Model)")
      (fields (field (name "PUBLISHER") "Altium Limited"))
      (libsource (lib "Miscellaneous Devices") (part "Cap Semi"))
    )
    (comp (ref "C105")
      (value "470nF")
      (footprint "SMD_0603_CAPC1608X80N")
      (description "Capacitor (Semiconductor SIM Model)")
      (fields (field (name "PUBLISHER") "Altium Limited"))
      (libsource (lib "Miscellaneous Devices") (part "Cap Semi"))
    )
    (comp (ref "C106")
      (value "470nF")
      (footprint "SMD_0603_CAPC1608X80N")
      (description "Capacitor (Semiconductor SIM Model)")
      (fields (field (name "PUBLISHER") "Altium Limited"))
      (libsource (lib "Miscellaneous Devices") (part "Cap Semi"))
    )
    (comp (ref "C107")
      (value "470nF")
      (footprint "SMD_0603_CAPC1608X80N")
      (description "Capacitor (Semiconductor SIM Model)")
      (fields (field (name "PUBLISHER") "Altium Limited"))
      (libsource (lib "Miscellaneous Devices") (part "Cap Semi"))
    )
    (comp (ref "C108")
      (value "470nF")
      (footprint "SMD_0603_CAPC1608X80N")
      (description "Capacitor (Semiconductor SIM Model)")
      (fields (field (name "PUBLISHER") "Altium Limited"))
      (libsource (lib "Miscellaneous Devices") (part "Cap Semi"))
    )
    (comp (ref "C109")
      (value "470nF")
      (footprint "SMD_0603_CAPC1608X80N")
      (description "Capacitor (Semiconductor SIM Model)")
      (fields (field (name "PUBLISHER") "Altium Limited"))
      (libsource (lib "Miscellaneous Devices") (part "Cap Semi"))
    )
    (comp (ref "C110")
      (value "470nF")
      (footprint "SMD_0603_CAPC1608X80N")
      (description "Capacitor (Semiconductor SIM Model)")
      (fields (field (name "PUBLISHER") "Altium Limited"))
      (libsource (lib "Miscellaneous Devices") (part "Cap Semi"))
    )
    (comp (ref "C111")
      (value "470nF")
      (footprint "SMD_0603_CAPC1608X80N")
      (description "Capacitor (Semiconductor SIM Model)")
      (fields (field (name "PUBLISHER") "Altium Limited"))
      (libsource (lib "Miscellaneous Devices") (part "Cap Semi"))
    )
    (comp (ref "C112")
      (value "470nF")
      (footprint "SMD_0603_CAPC1608X80N")
      (description "Capacitor (Semiconductor SIM Model)")
      (fields (field (name "PUBLISHER") "Altium Limited"))
      (libsource (lib "Miscellaneous Devices") (part "Cap Semi"))
    )
    (comp (ref "C113")
      (value "470nF")
      (footprint "SMD_0603_CAPC1608X80N")
      (description "Capacitor (Semiconductor SIM Model)")
      (fields (field (name "PUBLISHER") "Altium Limited"))
      (libsource (lib "Miscellaneous Devices") (part "Cap Semi"))
    )
    (comp (ref "C114")
      (value "470nF")
      (footprint "SMD_0603_CAPC1608X80N")
      (description "Capacitor (Semiconductor SIM Model)")
      (fields (field (name "PUBLISHER") "Altium Limited"))
      (libsource (lib "Miscellaneous Devices") (part "Cap Semi"))
    )
    (comp (ref "C115")
      (value "470nF")
      (footprint "SMD_0603_CAPC1608X80N")
      (description "Capacitor (Semiconductor SIM Model)")
      (fields (field (name "PUBLISHER") "Altium Limited"))
      (libsource (lib "Miscellaneous Devices") (part "Cap Semi"))
    )
    (comp (ref "C116")
      (value "470nF")
      (footprint "SMD_0603_CAPC1608X80N")
      (description "Capacitor (Semiconductor SIM Model)")
      (fields (field (name "PUBLISHER") "Altium Limited"))
      (libsource (lib "Miscellaneous Devices") (part "Cap Semi"))
    )
    (comp (ref "C117")
      (value "470nF")
      (footprint "SMD_0603_CAPC1608X80N")
      (description "Capacitor (Semiconductor SIM Model)")
      (fields (field (name "PUBLISHER") "Altium Limited"))
      (libsource (lib "Miscellaneous Devices") (part "Cap Semi"))
    )
    (comp (ref "C118")
      (value "470nF")
      (footprint "SMD_0603_CAPC1608X80N")
      (description "Capacitor (Semiconductor SIM Model)")
      (fields (field (name "PUBLISHER") "Altium Limited"))
      (libsource (lib "Miscellaneous Devices") (part "Cap Semi"))
    )
    (comp (ref "C119")
      (value "470nF")
      (footprint "SMD_0603_CAPC1608X80N")
      (description "Capacitor (Semiconductor SIM Model)")
      (fields (field (name "PUBLISHER") "Altium Limited"))
      (libsource (lib "Miscellaneous Devices") (part "Cap Semi"))
    )
    (comp (ref "C120")
      (value "470nF")
      (footprint "SMD_0603_CAPC1608X80N")
      (description "Capacitor (Semiconductor SIM Model)")
      (fields (field (name "PUBLISHER") "Altium Limited"))
      (libsource (lib "Miscellaneous Devices") (part "Cap Semi"))
    )
    (comp (ref "C121")
      (value "470nF")
      (footprint "SMD_0603_CAPC1608X80N")
      (description "Capacitor (Semiconductor SIM Model)")
      (fields (field (name "PUBLISHER") "Altium Limited"))
      (libsource (lib "Miscellaneous Devices") (part "Cap Semi"))
    )
    (comp (ref "C122")
      (value "470nF")
      (footprint "SMD_0603_CAPC1608X80N")
      (description "Capacitor (Semiconductor SIM Model)")
      (fields (field (name "PUBLISHER") "Altium Limited"))
      (libsource (lib "Miscellaneous Devices") (part "Cap Semi"))
    )
    (comp (ref "C123")
      (value "470nF")
      (footprint "SMD_0603_CAPC1608X80N")
      (description "Capacitor (Semiconductor SIM Model)")
      (fields (field (name "PUBLISHER") "Altium Limited"))
      (libsource (lib "Miscellaneous Devices") (part "Cap Semi"))
    )
    (comp (ref "C124")
      (value "470nF")
      (footprint "SMD_0603_CAPC1608X80N")
      (description "Capacitor (Semiconductor SIM Model)")
      (fields (field (name "PUBLISHER") "Altium Limited"))
      (libsource (lib "Miscellaneous Devices") (part "Cap Semi"))
    )
    (comp (ref "C125")
      (value "470nF")
      (footprint "SMD_0603_CAPC1608X80N")
      (description "Capacitor (Semiconductor SIM Model)")
      (fields (field (name "PUBLISHER") "Altium Limited"))
      (libsource (lib "Miscellaneous Devices") (part "Cap Semi"))
    )
    (comp (ref "C126")
      (value "470nF")
      (footprint "SMD_0603_CAPC1608X80N")
      (description "Capacitor (Semiconductor SIM Model)")
      (fields (field (name "PUBLISHER") "Altium Limited"))
      (libsource (lib "Miscellaneous Devices") (part "Cap Semi"))
    )
    (comp (ref "C127")
      (value "470nF")
      (footprint "SMD_0603_CAPC1608X80N")
      (description "Capacitor (Semiconductor SIM Model)")
      (fields (field (name "PUBLISHER") "Altium Limited"))
      (libsource (lib "Miscellaneous Devices") (part "Cap Semi"))
    )
    (comp (ref "C128")
      (value "470nF")
      (footprint "SMD_0603_CAPC1608X80N")
      (description "Capacitor (Semiconductor SIM Model)")
      (fields (field (name "PUBLISHER") "Altium Limited"))
      (libsource (lib "Miscellaneous Devices") (part "Cap Semi"))
    )
    (comp (ref "C129")
      (value "470nF")
      (footprint "SMD_0603_CAPC1608X80N")
      (description "Capacitor (Semiconductor SIM Model)")
      (fields (field (name "PUBLISHER") "Altium Limited"))
      (libsource (lib "Miscellaneous Devices") (part "Cap Semi"))
    )
    (comp (ref "C130")
      (value "470nF")
      (footprint "SMD_0603_CAPC1608X80N")
      (description "Capacitor (Semiconductor SIM Model)")
      (fields (field (name "PUBLISHER") "Altium Limited"))
      (libsource (lib "Miscellaneous Devices") (part "Cap Semi"))
    )
    (comp (ref "C131")
      (value "470nF")
      (footprint "SMD_0603_CAPC1608X80N")
      (description "Capacitor (Semiconductor SIM Model)")
      (fields (field (name "PUBLISHER") "Altium Limited"))
      (libsource (lib "Miscellaneous Devices") (part "Cap Semi"))
    )
    (comp (ref "C132")
      (value "470nF")
      (footprint "SMD_0603_CAPC1608X80N")
      (description "Capacitor (Semiconductor SIM Model)")
      (fields (field (name "PUBLISHER") "Altium Limited"))
      (libsource (lib "Miscellaneous Devices") (part "Cap Semi"))
    )
    (comp (ref "C133")
      (value "470nF")
      (footprint "SMD_0603_CAPC1608X80N")
      (description "Capacitor (Semiconductor SIM Model)")
      (fields (field (name "PUBLISHER") "Altium Limited"))
      (libsource (lib "Miscellaneous Devices") (part "Cap Semi"))
    )
    (comp (ref "C134")
      (value "470nF")
      (footprint "SMD_0603_CAPC1608X80N")
      (description "Capacitor (Semiconductor SIM Model)")
      (fields (field (name "PUBLISHER") "Altium Limited"))
      (libsource (lib "Miscellaneous Devices") (part "Cap Semi"))
    )
    (comp (ref "C135")
      (value "470nF")
      (footprint "SMD_0603_CAPC1608X80N")
      (description "Capacitor (Semiconductor SIM Model)")
      (fields (field (name "PUBLISHER") "Altium Limited"))
      (libsource (lib "Miscellaneous Devices") (part "Cap Semi"))
    )
    (comp (ref "C136")
      (value "470nF")
      (footprint "SMD_0603_CAPC1608X80N")
      (description "Capacitor (Semiconductor SIM Model)")
      (fields (field (name "PUBLISHER") "Altium Limited"))
      (libsource (lib "Miscellaneous Devices") (part "Cap Semi"))
    )
    (comp (ref "C137")
      (value "470nF")
      (footprint "SMD_0603_CAPC1608X80N")
      (description "Capacitor (Semiconductor SIM Model)")
      (fields (field (name "PUBLISHER") "Altium Limited"))
      (libsource (lib "Miscellaneous Devices") (part "Cap Semi"))
    )
    (comp (ref "C138")
      (value "470nF")
      (footprint "SMD_0603_CAPC1608X80N")
      (description "Capacitor (Semiconductor SIM Model)")
      (fields (field (name "PUBLISHER") "Altium Limited"))
      (libsource (lib "Miscellaneous Devices") (part "Cap Semi"))
    )
    (comp (ref "C139")
      (value "470nF")
      (footprint "SMD_0603_CAPC1608X80N")
      (description "Capacitor (Semiconductor SIM Model)")
      (fields (field (name "PUBLISHER") "Altium Limited"))
      (libsource (lib "Miscellaneous Devices") (part "Cap Semi"))
    )
    (comp (ref "C140")
      (value "470nF")
      (footprint "SMD_0603_CAPC1608X80N")
      (description "Capacitor (Semiconductor SIM Model)")
      (fields (field (name "PUBLISHER") "Altium Limited"))
      (libsource (lib "Miscellaneous Devices") (part "Cap Semi"))
    )
    (comp (ref "C142")
      (value "470nF")
      (footprint "SMD_0603_CAPC1608X80N")
      (description "Capacitor (Semiconductor SIM Model)")
      (fields (field (name "PUBLISHER") "Altium Limited"))
      (libsource (lib "Miscellaneous Devices") (part "Cap Semi"))
    )
    (comp (ref "C144")
      (value "470nF")
      (footprint "SMD_0603_CAPC1608X80N")
      (description "Capacitor (Semiconductor SIM Model)")
      (fields (field (name "PUBLISHER") "Altium Limited"))
      (libsource (lib "Miscellaneous Devices") (part "Cap Semi"))
    )
    (comp (ref "C145")
      (value "470nF")
      (footprint "SMD_0603_CAPC1608X80N")
      (description "Capacitor (Semiconductor SIM Model)")
      (fields (field (name "PUBLISHER") "Altium Limited"))
      (libsource (lib "Miscellaneous Devices") (part "Cap Semi"))
    )
    (comp (ref "C146")
      (value "470nF")
      (footprint "SMD_0603_CAPC1608X80N")
      (description "Capacitor (Semiconductor SIM Model)")
      (fields (field (name "PUBLISHER") "Altium Limited"))
      (libsource (lib "Miscellaneous Devices") (part "Cap Semi"))
    )
    (comp (ref "C148")
      (value "470nF")
      (footprint "SMD_0603_CAPC1608X80N")
      (description "Capacitor (Semiconductor SIM Model)")
      (fields (field (name "PUBLISHER") "Altium Limited"))
      (libsource (lib "Miscellaneous Devices") (part "Cap Semi"))
    )
    (comp (ref "C149")
      (value "470nF")
      (footprint "SMD_0603_CAPC1608X80N")
      (description "Capacitor (Semiconductor SIM Model)")
      (fields (field (name "PUBLISHER") "Altium Limited"))
      (libsource (lib "Miscellaneous Devices") (part "Cap Semi"))
    )
    (comp (ref "C150")
      (value "470nF")
      (footprint "SMD_0603_CAPC1608X80N")
      (description "Capacitor (Semiconductor SIM Model)")
      (fields (field (name "PUBLISHER") "Altium Limited"))
      (libsource (lib "Miscellaneous Devices") (part "Cap Semi"))
    )
    (comp (ref "C152")
      (value "470nF")
      (footprint "SMD_0603_CAPC1608X80N")
      (description "Capacitor (Semiconductor SIM Model)")
      (fields (field (name "PUBLISHER") "Altium Limited"))
      (libsource (lib "Miscellaneous Devices") (part "Cap Semi"))
    )
    (comp (ref "C153")
      (value "470nF")
      (footprint "SMD_0603_CAPC1608X80N")
      (description "Capacitor (Semiconductor SIM Model)")
      (fields (field (name "PUBLISHER") "Altium Limited"))
      (libsource (lib "Miscellaneous Devices") (part "Cap Semi"))
    )
    (comp (ref "C154")
      (value "470nF")
      (footprint "SMD_0603_CAPC1608X80N")
      (description "Capacitor (Semiconductor SIM Model)")
      (fields (field (name "PUBLISHER") "Altium Limited"))
      (libsource (lib "Miscellaneous Devices") (part "Cap Semi"))
    )
    (comp (ref "C155")
      (value "470nF")
      (footprint "SMD_0603_CAPC1608X80N")
      (description "Capacitor (Semiconductor SIM Model)")
      (fields (field (name "PUBLISHER") "Altium Limited"))
      (libsource (lib "Miscellaneous Devices") (part "Cap Semi"))
    )
    (comp (ref "C156")
      (value "470nF")
      (footprint "SMD_0603_CAPC1608X80N")
      (description "Capacitor (Semiconductor SIM Model)")
      (fields (field (name "PUBLISHER") "Altium Limited"))
      (libsource (lib "Miscellaneous Devices") (part "Cap Semi"))
    )
    (comp (ref "C157")
      (value "470nF")
      (footprint "SMD_0603_CAPC1608X80N")
      (description "Capacitor (Semiconductor SIM Model)")
      (fields (field (name "PUBLISHER") "Altium Limited"))
      (libsource (lib "Miscellaneous Devices") (part "Cap Semi"))
    )
    (comp (ref "C158")
      (value "470nF")
      (footprint "SMD_0603_CAPC1608X80N")
      (description "Capacitor (Semiconductor SIM Model)")
      (fields (field (name "PUBLISHER") "Altium Limited"))
      (libsource (lib "Miscellaneous Devices") (part "Cap Semi"))
    )
    (comp (ref "C159")
      (value "470nF")
      (footprint "SMD_0603_CAPC1608X80N")
      (description "Capacitor (Semiconductor SIM Model)")
      (fields (field (name "PUBLISHER") "Altium Limited"))
      (libsource (lib "Miscellaneous Devices") (part "Cap Semi"))
    )
    (comp (ref "C160")
      (value "470nF")
      (footprint "SMD_0603_CAPC1608X80N")
      (description "Capacitor (Semiconductor SIM Model)")
      (fields (field (name "PUBLISHER") "Altium Limited"))
      (libsource (lib "Miscellaneous Devices") (part "Cap Semi"))
    )
    (comp (ref "C161")
      (value "470nF")
      (footprint "SMD_0603_CAPC1608X80N")
      (description "Capacitor (Semiconductor SIM Model)")
      (fields (field (name "PUBLISHER") "Altium Limited"))
      (libsource (lib "Miscellaneous Devices") (part "Cap Semi"))
    )
    (comp (ref "C162")
      (value "470nF")
      (footprint "SMD_0603_CAPC1608X80N")
      (description "Capacitor (Semiconductor SIM Model)")
      (fields (field (name "PUBLISHER") "Altium Limited"))
      (libsource (lib "Miscellaneous Devices") (part "Cap Semi"))
    )
    (comp (ref "C163")
      (value "470nF")
      (footprint "SMD_0603_CAPC1608X80N")
      (description "Capacitor (Semiconductor SIM Model)")
      (fields (field (name "PUBLISHER") "Altium Limited"))
      (libsource (lib "Miscellaneous Devices") (part "Cap Semi"))
    )
    (comp (ref "C164")
      (value "470nF")
      (footprint "SMD_0603_CAPC1608X80N")
      (description "Capacitor (Semiconductor SIM Model)")
      (fields (field (name "PUBLISHER") "Altium Limited"))
      (libsource (lib "Miscellaneous Devices") (part "Cap Semi"))
    )
    (comp (ref "C165")
      (value "470nF")
      (footprint "SMD_0603_CAPC1608X80N")
      (description "Capacitor (Semiconductor SIM Model)")
      (fields (field (name "PUBLISHER") "Altium Limited"))
      (libsource (lib "Miscellaneous Devices") (part "Cap Semi"))
    )
    (comp (ref "C166")
      (value "470nF")
      (footprint "SMD_0603_CAPC1608X80N")
      (description "Capacitor (Semiconductor SIM Model)")
      (fields (field (name "PUBLISHER") "Altium Limited"))
      (libsource (lib "Miscellaneous Devices") (part "Cap Semi"))
    )
    (comp (ref "C167")
      (value "470nF")
      (footprint "SMD_0603_CAPC1608X80N")
      (description "Capacitor (Semiconductor SIM Model)")
      (fields (field (name "PUBLISHER") "Altium Limited"))
      (libsource (lib "Miscellaneous Devices") (part "Cap Semi"))
    )
    (comp (ref "C169")
      (value "470nF")
      (footprint "SMD_0603_CAPC1608X80N")
      (description "Capacitor (Semiconductor SIM Model)")
      (fields (field (name "PUBLISHER") "Altium Limited"))
      (libsource (lib "Miscellaneous Devices") (part "Cap Semi"))
    )
    (comp (ref "C170")
      (value "470nF")
      (footprint "SMD_0603_CAPC1608X80N")
      (description "Capacitor (Semiconductor SIM Model)")
      (fields (field (name "PUBLISHER") "Altium Limited"))
      (libsource (lib "Miscellaneous Devices") (part "Cap Semi"))
    )
    (comp (ref "C171")
      (value "470nF")
      (footprint "SMD_0603_CAPC1608X80N")
      (description "Capacitor (Semiconductor SIM Model)")
      (fields (field (name "PUBLISHER") "Altium Limited"))
      (libsource (lib "Miscellaneous Devices") (part "Cap Semi"))
    )
    (comp (ref "C172")
      (value "470nF")
      (footprint "SMD_0603_CAPC1608X80N")
      (description "Capacitor (Semiconductor SIM Model)")
      (fields (field (name "PUBLISHER") "Altium Limited"))
      (libsource (lib "Miscellaneous Devices") (part "Cap Semi"))
    )
    (comp (ref "C173")
      (value "470nF")
      (footprint "SMD_0603_CAPC1608X80N")
      (description "Capacitor (Semiconductor SIM Model)")
      (fields (field (name "PUBLISHER") "Altium Limited"))
      (libsource (lib "Miscellaneous Devices") (part "Cap Semi"))
    )
    (comp (ref "C174")
      (value "470nF")
      (footprint "SMD_0603_CAPC1608X80N")
      (description "Capacitor (Semiconductor SIM Model)")
      (fields (field (name "PUBLISHER") "Altium Limited"))
      (libsource (lib "Miscellaneous Devices") (part "Cap Semi"))
    )
    (comp (ref "C175")
      (value "470nF")
      (footprint "SMD_0603_CAPC1608X80N")
      (description "Capacitor (Semiconductor SIM Model)")
      (fields (field (name "PUBLISHER") "Altium Limited"))
      (libsource (lib "Miscellaneous Devices") (part "Cap Semi"))
    )
    (comp (ref "C176")
      (value "470nF")
      (footprint "SMD_0603_CAPC1608X80N")
      (description "Capacitor (Semiconductor SIM Model)")
      (fields (field (name "PUBLISHER") "Altium Limited"))
      (libsource (lib "Miscellaneous Devices") (part "Cap Semi"))
    )
    (comp (ref "C177")
      (value "470nF")
      (footprint "SMD_0603_CAPC1608X80N")
      (description "Capacitor (Semiconductor SIM Model)")
      (fields (field (name "PUBLISHER") "Altium Limited"))
      (libsource (lib "Miscellaneous Devices") (part "Cap Semi"))
    )
    (comp (ref "C178")
      (value "470nF")
      (footprint "SMD_0603_CAPC1608X80N")
      (description "Capacitor (Semiconductor SIM Model)")
      (fields (field (name "PUBLISHER") "Altium Limited"))
      (libsource (lib "Miscellaneous Devices") (part "Cap Semi"))
    )
    (comp (ref "C179")
      (value "470nF")
      (footprint "SMD_0603_CAPC1608X80N")
      (description "Capacitor (Semiconductor SIM Model)")
      (fields (field (name "PUBLISHER") "Altium Limited"))
      (libsource (lib "Miscellaneous Devices") (part "Cap Semi"))
    )
    (comp (ref "C180")
      (value "470nF")
      (footprint "SMD_0603_CAPC1608X80N")
      (description "Capacitor (Semiconductor SIM Model)")
      (fields (field (name "PUBLISHER") "Altium Limited"))
      (libsource (lib "Miscellaneous Devices") (part "Cap Semi"))
    )
    (comp (ref "C181")
      (value "470nF")
      (footprint "SMD_0603_CAPC1608X80N")
      (description "Capacitor (Semiconductor SIM Model)")
      (fields (field (name "PUBLISHER") "Altium Limited"))
      (libsource (lib "Miscellaneous Devices") (part "Cap Semi"))
    )
    (comp (ref "C182")
      (value "470nF")
      (footprint "SMD_0603_CAPC1608X80N")
      (description "Capacitor (Semiconductor SIM Model)")
      (fields (field (name "PUBLISHER") "Altium Limited"))
      (libsource (lib "Miscellaneous Devices") (part "Cap Semi"))
    )
    (comp (ref "C183")
      (value "470nF")
      (footprint "SMD_0603_CAPC1608X80N")
      (description "Capacitor (Semiconductor SIM Model)")
      (fields (field (name "PUBLISHER") "Altium Limited"))
      (libsource (lib "Miscellaneous Devices") (part "Cap Semi"))
    )
    (comp (ref "C184")
      (value "470nF")
      (footprint "SMD_0603_CAPC1608X80N")
      (description "Capacitor (Semiconductor SIM Model)")
      (fields (field (name "PUBLISHER") "Altium Limited"))
      (libsource (lib "Miscellaneous Devices") (part "Cap Semi"))
    )
    (comp (ref "C185")
      (value "470nF")
      (footprint "SMD_0603_CAPC1608X80N")
      (description "Capacitor (Semiconductor SIM Model)")
      (fields (field (name "PUBLISHER") "Altium Limited"))
      (libsource (lib "Miscellaneous Devices") (part "Cap Semi"))
    )
    (comp (ref "C187")
      (value "10uF/16V")
      (footprint "SMD_0805_CAPC2012X145N")
      (description "Capacitor")
      (libsource (lib "*") (part "CAP"))
    )
    (comp (ref "C188")
      (value "10uF/16V")
      (footprint "SMD_0805_CAPC2012X145N")
      (description "Capacitor")
      (libsource (lib "*") (part "CAP"))
    )
    (comp (ref "C189")
      (value "100nF/50V")
      (footprint "SMD_0805_CAPC2012X145N")
      (description "Capacitor")
      (libsource (lib "*") (part "CAP"))
    )
    (comp (ref "C190")
      (value "10uF/16V")
      (footprint "SMD_0805_CAPC2012X145N")
      (description "Capacitor")
      (libsource (lib "*") (part "CAP"))
    )
    (comp (ref "C191")
      (value "10uF/16V")
      (footprint "SMD_0805_CAPC2012X145N")
      (description "Capacitor")
      (libsource (lib "*") (part "CAP"))
    )
    (comp (ref "C192")
      (value "10uF/16V")
      (footprint "SMD_0805_CAPC2012X145N")
      (description "Capacitor")
      (libsource (lib "*") (part "CAP"))
    )
    (comp (ref "C193")
      (value "10uF/16V")
      (footprint "SMD_0805_CAPC2012X145N")
      (description "Capacitor")
      (libsource (lib "*") (part "CAP"))
    )
    (comp (ref "C195")
      (value "10uF/16V")
      (footprint "SMD_0805_CAPC2012X145N")
      (description "Capacitor")
      (libsource (lib "*") (part "CAP"))
    )
    (comp (ref "C196")
      (value "10uF/16V")
      (footprint "SMD_0805_CAPC2012X145N")
      (description "Capacitor")
      (libsource (lib "*") (part "CAP"))
    )
    (comp (ref "C197")
      (value "10uF/16V")
      (footprint "SMD_0805_CAPC2012X145N")
      (description "Capacitor")
      (libsource (lib "*") (part "CAP"))
    )
    (comp (ref "C198")
      (value "22uF/6.3V")
      (footprint "SMD_0805_CAPC2012X145N")
      (description "Capacitor")
      (libsource (lib "*") (part "CAP"))
    )
    (comp (ref "C199")
      (value "22uF/6.3V")
      (footprint "SMD_0805_CAPC2012X145N")
      (description "Capacitor")
      (libsource (lib "*") (part "CAP"))
    )
    (comp (ref "C200")
      (value "22uF/6.3V")
      (footprint "SMD_0805_CAPC2012X145N")
      (description "Capacitor")
      (libsource (lib "*") (part "CAP"))
    )
    (comp (ref "C201")
      (value "22uF/6.3V")
      (footprint "SMD_0805_CAPC2012X145N")
      (description "Capacitor")
      (libsource (lib "*") (part "CAP"))
    )
    (comp (ref "C202")
      (value "22uF/6.3V")
      (footprint "SMD_0805_CAPC2012X145N")
      (description "Capacitor")
      (libsource (lib "*") (part "CAP"))
    )
    (comp (ref "C203")
      (value "22uF/6.3V")
      (footprint "SMD_0805_CAPC2012X145N")
      (description "Capacitor")
      (libsource (lib "*") (part "CAP"))
    )
    (comp (ref "C204")
      (value "22uF/6.3V")
      (footprint "SMD_0805_CAPC2012X145N")
      (description "Capacitor")
      (libsource (lib "*") (part "CAP"))
    )
    (comp (ref "C205")
      (value "22uF/6.3V")
      (footprint "SMD_0805_CAPC2012X145N")
      (description "Capacitor")
      (libsource (lib "*") (part "CAP"))
    )
    (comp (ref "C206")
      (value "22uF/6.3V")
      (footprint "SMD_0805_CAPC2012X145N")
      (description "Capacitor")
      (libsource (lib "*") (part "CAP"))
    )
    (comp (ref "C207")
      (value "10uF/16V")
      (footprint "SMD_0805_CAPC2012X145N")
      (description "Capacitor")
      (libsource (lib "*") (part "CAP"))
    )
    (comp (ref "C208")
      (value "(OPT)2200uF/16V")
      (footprint "PTH_CAPPR500-1300X2250")
      (libsource (lib "EPIQ_DND_CIS_Library") (part "C_POL"))
    )
    (comp (ref "C209")
      (value "1uF")
      (footprint "SMD_0805_CAPC2012X145N")
      (description "Capacitor")
      (libsource (lib "*") (part "CAP"))
    )
    (comp (ref "C210")
      (value "(OPT)2200uF/16V")
      (footprint "PTH_CAPPR500-1300X2250")
      (libsource (lib "EPIQ_DND_CIS_Library") (part "C_POL"))
    )
    (comp (ref "C211")
      (value "22uF/6.3V")
      (footprint "SMD_0805_CAPC2012X145N")
      (description "Capacitor")
      (libsource (lib "*") (part "CAP"))
    )
    (comp (ref "C213")
      (value "10uF/16V")
      (footprint "SMD_0805_CAPC2012X145N")
      (description "Capacitor")
      (libsource (lib "*") (part "CAP"))
    )
    (comp (ref "C214")
      (value "10uF/16V")
      (footprint "SMD_0805_CAPC2012X145N")
      (description "Capacitor")
      (libsource (lib "*") (part "CAP"))
    )
    (comp (ref "C215")
      (value "10uF/16V")
      (footprint "SMD_0805_CAPC2012X145N")
      (description "Capacitor")
      (libsource (lib "*") (part "CAP"))
    )
    (comp (ref "C216")
      (value "10uF/16V")
      (footprint "SMD_0805_CAPC2012X145N")
      (description "Capacitor")
      (libsource (lib "*") (part "CAP"))
    )
    (comp (ref "C217")
      (value "10uF/16V")
      (footprint "SMD_0805_CAPC2012X145N")
      (description "Capacitor")
      (libsource (lib "*") (part "CAP"))
    )
    (comp (ref "C218")
      (value "10uF/16V")
      (footprint "SMD_0805_CAPC2012X145N")
      (description "Capacitor")
      (libsource (lib "*") (part "CAP"))
    )
    (comp (ref "C219")
      (value "10uF/16V")
      (footprint "SMD_0805_CAPC2012X145N")
      (description "Capacitor")
      (libsource (lib "*") (part "CAP"))
    )
    (comp (ref "C220")
      (value "22uF/6.3V")
      (footprint "SMD_0805_CAPC2012X145N")
      (description "Capacitor")
      (libsource (lib "*") (part "CAP"))
    )
    (comp (ref "C221")
      (value "22uF/6.3V")
      (footprint "SMD_0805_CAPC2012X145N")
      (description "Capacitor")
      (libsource (lib "*") (part "CAP"))
    )
    (comp (ref "C222")
      (value "22uF/6.3V")
      (footprint "SMD_0805_CAPC2012X145N")
      (description "Capacitor")
      (libsource (lib "*") (part "CAP"))
    )
    (comp (ref "C223")
      (value "22uF/6.3V")
      (footprint "SMD_0805_CAPC2012X145N")
      (description "Capacitor")
      (libsource (lib "*") (part "CAP"))
    )
    (comp (ref "C224")
      (value "22uF/6.3V")
      (footprint "SMD_0805_CAPC2012X145N")
      (description "Capacitor")
      (libsource (lib "*") (part "CAP"))
    )
    (comp (ref "C225")
      (value "22uF/6.3V")
      (footprint "SMD_0805_CAPC2012X145N")
      (description "Capacitor")
      (libsource (lib "*") (part "CAP"))
    )
    (comp (ref "C226")
      (value "22uF/6.3V")
      (footprint "SMD_0805_CAPC2012X145N")
      (description "Capacitor")
      (libsource (lib "*") (part "CAP"))
    )
    (comp (ref "C227")
      (value "22uF/6.3V")
      (footprint "SMD_0805_CAPC2012X145N")
      (description "Capacitor")
      (libsource (lib "*") (part "CAP"))
    )
    (comp (ref "C228")
      (value "(OPT)姨0J332M-RBJ21")
      (footprint "PTH_CAPPR500-1300X2250")
      (description "姨0J332M-RBJ21")
      (libsource (lib "EPIQ_DND_CIS_Library") (part "C_POL"))
    )
    (comp (ref "C229")
      (value "22uF/6.3V")
      (footprint "SMD_0805_CAPC2012X145N")
      (description "Capacitor")
      (libsource (lib "*") (part "CAP"))
    )
    (comp (ref "C231")
      (value "10uF/16V")
      (footprint "SMD_0805_CAPC2012X145N")
      (description "Capacitor")
      (libsource (lib "*") (part "CAP"))
    )
    (comp (ref "C233")
      (value "22uF/6.3V")
      (footprint "SMD_0805_CAPC2012X145N")
      (description "Capacitor")
      (libsource (lib "*") (part "CAP"))
    )
    (comp (ref "C234")
      (value "22uF/6.3V")
      (footprint "SMD_0805_CAPC2012X145N")
      (description "Capacitor")
      (libsource (lib "*") (part "CAP"))
    )
    (comp (ref "C237")
      (value "22uF/6.3V")
      (footprint "SMD_0805_CAPC2012X145N")
      (description "Capacitor")
      (libsource (lib "*") (part "CAP"))
    )
    (comp (ref "C238")
      (value "(OPT)姨0J332M-RBJ21")
      (footprint "PTH_CAPPR500-1300X2250")
      (description "姨0J332M-RBJ21")
      (libsource (lib "EPIQ_DND_CIS_Library") (part "C_POL"))
    )
    (comp (ref "C239")
      (value "(OPT)姨0J332M-RBJ21")
      (footprint "PTH_CAPPR500-1300X2250")
      (description "姨0J332M-RBJ21")
      (libsource (lib "EPIQ_DND_CIS_Library") (part "C_POL"))
    )
    (comp (ref "C240")
      (value "22uF/6.3V")
      (footprint "SMD_0805_CAPC2012X145N")
      (description "Capacitor")
      (libsource (lib "*") (part "CAP"))
    )
    (comp (ref "C241")
      (value "22uF/6.3V")
      (footprint "SMD_0805_CAPC2012X145N")
      (description "Capacitor")
      (libsource (lib "*") (part "CAP"))
    )
    (comp (ref "C242")
      (value "22uF/6.3V")
      (footprint "SMD_0805_CAPC2012X145N")
      (description "Capacitor")
      (libsource (lib "*") (part "CAP"))
    )
    (comp (ref "C243")
      (value "22uF/6.3V")
      (footprint "SMD_0805_CAPC2012X145N")
      (description "Capacitor")
      (libsource (lib "*") (part "CAP"))
    )
    (comp (ref "C244")
      (value "22uF/6.3V")
      (footprint "SMD_0805_CAPC2012X145N")
      (description "Capacitor")
      (libsource (lib "*") (part "CAP"))
    )
    (comp (ref "C245")
      (value "22uF/6.3V")
      (footprint "SMD_0805_CAPC2012X145N")
      (description "Capacitor")
      (libsource (lib "*") (part "CAP"))
    )
    (comp (ref "C246")
      (value "22uF/6.3V")
      (footprint "SMD_0805_CAPC2012X145N")
      (description "Capacitor")
      (libsource (lib "*") (part "CAP"))
    )
    (comp (ref "C247")
      (value "22uF/6.3V")
      (footprint "SMD_0805_CAPC2012X145N")
      (description "Capacitor")
      (libsource (lib "*") (part "CAP"))
    )
    (comp (ref "C248")
      (value "22uF/6.3V")
      (footprint "SMD_0805_CAPC2012X145N")
      (description "Capacitor")
      (libsource (lib "*") (part "CAP"))
    )
    (comp (ref "C249")
      (value "22uF/6.3V")
      (footprint "SMD_0805_CAPC2012X145N")
      (description "Capacitor")
      (libsource (lib "*") (part "CAP"))
    )
    (comp (ref "C250")
      (value "22uF/6.3V")
      (footprint "SMD_0805_CAPC2012X145N")
      (description "Capacitor")
      (libsource (lib "*") (part "CAP"))
    )
    (comp (ref "C251")
      (value "1nF")
      (footprint "SMD_0603_CAPC1608X80N")
      (description "Capacitor")
      (libsource (lib "*") (part "CAP"))
    )
    (comp (ref "C252")
      (value "1uF/16V")
      (footprint "SMD_0805_CAPC2012X145N")
      (description "Capacitor")
      (libsource (lib "*") (part "CAP"))
    )
    (comp (ref "C253")
      (value "100pF")
      (footprint "SMD_0603_CAPC1608X80N")
      (description "Capacitor")
      (libsource (lib "*") (part "CAP"))
    )
    (comp (ref "C254")
      (value "100pF")
      (footprint "SMD_0603_CAPC1608X80N")
      (description "Capacitor")
      (libsource (lib "*") (part "CAP"))
    )
    (comp (ref "C255")
      (value "100nF")
      (footprint "SMD_0603_CAPC1608X80N")
      (description "Capacitor")
      (libsource (lib "*") (part "CAP"))
    )
    (comp (ref "C256")
      (value "(OPT)姨0J332M-RBJ21")
      (footprint "PTH_CAPPR500-1300X2250")
      (description "姨0J332M-RBJ21")
      (libsource (lib "EPIQ_DND_CIS_Library") (part "C_POL"))
    )
    (comp (ref "C257")
      (value "(OPT)姨0J332M-RBJ21")
      (footprint "PTH_CAPPR500-1300X2250")
      (description "姨0J332M-RBJ21")
      (libsource (lib "EPIQ_DND_CIS_Library") (part "C_POL"))
    )
    (comp (ref "C258")
      (value "22uF/6.3V")
      (footprint "SMD_0805_CAPC2012X145N")
      (description "Capacitor")
      (libsource (lib "*") (part "CAP"))
    )
    (comp (ref "C259")
      (value "22uF/6.3V")
      (footprint "SMD_0805_CAPC2012X145N")
      (description "Capacitor")
      (libsource (lib "*") (part "CAP"))
    )
    (comp (ref "C260")
      (value "22uF/6.3V")
      (footprint "SMD_0805_CAPC2012X145N")
      (description "Capacitor")
      (libsource (lib "*") (part "CAP"))
    )
    (comp (ref "C261")
      (value "22uF/6.3V")
      (footprint "SMD_0805_CAPC2012X145N")
      (description "Capacitor")
      (libsource (lib "*") (part "CAP"))
    )
    (comp (ref "C262")
      (value "22uF/6.3V")
      (footprint "SMD_0805_CAPC2012X145N")
      (description "Capacitor")
      (libsource (lib "*") (part "CAP"))
    )
    (comp (ref "C263")
      (value "10uF/16V")
      (footprint "SMD_0805_CAPC2012X145N")
      (description "Capacitor")
      (libsource (lib "*") (part "CAP"))
    )
    (comp (ref "C264")
      (value "10uF/16V")
      (footprint "SMD_0805_CAPC2012X145N")
      (description "Capacitor")
      (libsource (lib "*") (part "CAP"))
    )
    (comp (ref "C265")
      (value "10uF/16V")
      (footprint "SMD_0805_CAPC2012X145N")
      (description "Capacitor")
      (libsource (lib "*") (part "CAP"))
    )
    (comp (ref "C266")
      (value "10uF/16V")
      (footprint "SMD_0805_CAPC2012X145N")
      (description "Capacitor")
      (libsource (lib "*") (part "CAP"))
    )
    (comp (ref "C267")
      (value "10uF/16V")
      (footprint "SMD_0805_CAPC2012X145N")
      (description "Capacitor")
      (libsource (lib "*") (part "CAP"))
    )
    (comp (ref "C268")
      (value "10uF/16V")
      (footprint "SMD_0805_CAPC2012X145N")
      (description "Capacitor")
      (libsource (lib "*") (part "CAP"))
    )
    (comp (ref "C269")
      (value "10uF/16V")
      (footprint "SMD_0805_CAPC2012X145N")
      (description "Capacitor")
      (libsource (lib "*") (part "CAP"))
    )
    (comp (ref "C270")
      (value "10uF/16V")
      (footprint "SMD_0805_CAPC2012X145N")
      (description "Capacitor")
      (libsource (lib "*") (part "CAP"))
    )
    (comp (ref "C271")
      (value "(OPT)姨0J332M-RBJ21")
      (footprint "PTH_CAPPR500-1300X2250")
      (description "姨0J332M-RBJ21")
      (libsource (lib "EPIQ_DND_CIS_Library") (part "C_POL"))
    )
    (comp (ref "C272")
      (value "(OPT)2200uF/16V")
      (footprint "PTH_CAPPR500-1300X2250")
      (libsource (lib "EPIQ_DND_CIS_Library") (part "C_POL"))
    )
    (comp (ref "C273")
      (value "10uF/16V")
      (footprint "SMD_0805_CAPC2012X145N")
      (description "Capacitor")
      (libsource (lib "*") (part "CAP"))
    )
    (comp (ref "C274")
      (value "10uF/16V")
      (footprint "SMD_0805_CAPC2012X145N")
      (description "Capacitor")
      (libsource (lib "*") (part "CAP"))
    )
    (comp (ref "C275")
      (value "10uF/16V")
      (footprint "SMD_0805_CAPC2012X145N")
      (description "Capacitor")
      (libsource (lib "*") (part "CAP"))
    )
    (comp (ref "C276")
      (value "10uF/16V")
      (footprint "SMD_0805_CAPC2012X145N")
      (description "Capacitor")
      (libsource (lib "*") (part "CAP"))
    )
    (comp (ref "C277")
      (value "10uF/16V")
      (footprint "SMD_0805_CAPC2012X145N")
      (description "Capacitor")
      (libsource (lib "*") (part "CAP"))
    )
    (comp (ref "C278")
      (value "10uF/16V")
      (footprint "SMD_0805_CAPC2012X145N")
      (description "Capacitor")
      (libsource (lib "*") (part "CAP"))
    )
    (comp (ref "C279")
      (value "10uF/16V")
      (footprint "SMD_0805_CAPC2012X145N")
      (description "Capacitor")
      (libsource (lib "*") (part "CAP"))
    )
    (comp (ref "C280")
      (value "10uF/16V")
      (footprint "SMD_0805_CAPC2012X145N")
      (description "Capacitor")
      (libsource (lib "*") (part "CAP"))
    )
    (comp (ref "C281")
      (value "(OPT)2200uF/16V")
      (footprint "PTH_CAPPR500-1300X2250")
      (libsource (lib "EPIQ_DND_CIS_Library") (part "C_POL"))
    )
    (comp (ref "C282")
      (value "(OPT)姨0J332M-RBJ21")
      (footprint "PTH_CAPPR500-1300X2250")
      (description "姨0J332M-RBJ21")
      (libsource (lib "EPIQ_DND_CIS_Library") (part "C_POL"))
    )
    (comp (ref "C283")
      (value "22uF/6.3V")
      (footprint "SMD_0805_CAPC2012X145N")
      (description "Capacitor")
      (libsource (lib "*") (part "CAP"))
    )
    (comp (ref "C284")
      (value "22uF/6.3V")
      (footprint "SMD_0805_CAPC2012X145N")
      (description "Capacitor")
      (libsource (lib "*") (part "CAP"))
    )
    (comp (ref "C285")
      (value "22uF/6.3V")
      (footprint "SMD_0805_CAPC2012X145N")
      (description "Capacitor")
      (libsource (lib "*") (part "CAP"))
    )
    (comp (ref "C286")
      (value "22uF/6.3V")
      (footprint "SMD_0805_CAPC2012X145N")
      (description "Capacitor")
      (libsource (lib "*") (part "CAP"))
    )
    (comp (ref "C287")
      (value "22uF/6.3V")
      (footprint "SMD_0805_CAPC2012X145N")
      (description "Capacitor")
      (libsource (lib "*") (part "CAP"))
    )
    (comp (ref "C288")
      (value "22uF/6.3V")
      (footprint "SMD_0805_CAPC2012X145N")
      (description "Capacitor")
      (libsource (lib "*") (part "CAP"))
    )
    (comp (ref "C289")
      (value "22uF/6.3V")
      (footprint "SMD_0805_CAPC2012X145N")
      (description "Capacitor")
      (libsource (lib "*") (part "CAP"))
    )
    (comp (ref "C290")
      (value "22uF/6.3V")
      (footprint "SMD_0805_CAPC2012X145N")
      (description "Capacitor")
      (libsource (lib "*") (part "CAP"))
    )
    (comp (ref "C291")
      (value "22uF/6.3V")
      (footprint "SMD_0805_CAPC2012X145N")
      (description "Capacitor")
      (libsource (lib "*") (part "CAP"))
    )
    (comp (ref "C292")
      (value "22uF/6.3V")
      (footprint "SMD_0805_CAPC2012X145N")
      (description "Capacitor")
      (libsource (lib "*") (part "CAP"))
    )
    (comp (ref "C293")
      (value "22uF/6.3V")
      (footprint "SMD_0805_CAPC2012X145N")
      (description "Capacitor")
      (libsource (lib "*") (part "CAP"))
    )
    (comp (ref "C294")
      (value "22uF/6.3V")
      (footprint "SMD_0805_CAPC2012X145N")
      (description "Capacitor")
      (libsource (lib "*") (part "CAP"))
    )
    (comp (ref "C295")
      (value "22uF/6.3V")
      (footprint "SMD_0805_CAPC2012X145N")
      (description "Capacitor")
      (libsource (lib "*") (part "CAP"))
    )
    (comp (ref "C296")
      (value "22uF/6.3V")
      (footprint "SMD_0805_CAPC2012X145N")
      (description "Capacitor")
      (libsource (lib "*") (part "CAP"))
    )
    (comp (ref "C297")
      (value "22uF/6.3V")
      (footprint "SMD_0805_CAPC2012X145N")
      (description "Capacitor")
      (libsource (lib "*") (part "CAP"))
    )
    (comp (ref "C298")
      (value "22uF/6.3V")
      (footprint "SMD_0805_CAPC2012X145N")
      (description "Capacitor")
      (libsource (lib "*") (part "CAP"))
    )
    (comp (ref "C299")
      (value "22uF/6.3V")
      (footprint "SMD_0805_CAPC2012X145N")
      (description "Capacitor")
      (libsource (lib "*") (part "CAP"))
    )
    (comp (ref "C300")
      (value "22uF/6.3V")
      (footprint "SMD_0805_CAPC2012X145N")
      (description "Capacitor")
      (libsource (lib "*") (part "CAP"))
    )
    (comp (ref "C301")
      (value "22uF/6.3V")
      (footprint "SMD_0805_CAPC2012X145N")
      (description "Capacitor")
      (libsource (lib "*") (part "CAP"))
    )
    (comp (ref "C302")
      (value "22uF/6.3V")
      (footprint "SMD_0805_CAPC2012X145N")
      (description "Capacitor")
      (libsource (lib "*") (part "CAP"))
    )
    (comp (ref "C303")
      (value "22uF/6.3V")
      (footprint "SMD_0805_CAPC2012X145N")
      (description "Capacitor")
      (libsource (lib "*") (part "CAP"))
    )
    (comp (ref "C304")
      (value "22uF/6.3V")
      (footprint "SMD_0805_CAPC2012X145N")
      (description "Capacitor")
      (libsource (lib "*") (part "CAP"))
    )
    (comp (ref "C305")
      (value "22uF/6.3V")
      (footprint "SMD_0805_CAPC2012X145N")
      (description "Capacitor")
      (libsource (lib "*") (part "CAP"))
    )
    (comp (ref "C306")
      (value "22uF/6.3V")
      (footprint "SMD_0805_CAPC2012X145N")
      (description "Capacitor")
      (libsource (lib "*") (part "CAP"))
    )
    (comp (ref "C307")
      (value "(OPT)姨0J332M-RBJ21")
      (footprint "PTH_CAPPR500-1300X2250")
      (description "姨0J332M-RBJ21")
      (libsource (lib "EPIQ_DND_CIS_Library") (part "C_POL"))
    )
    (comp (ref "C308")
      (value "10uF/16V")
      (footprint "SMD_0805_CAPC2012X145N")
      (description "Capacitor")
      (libsource (lib "*") (part "CAP"))
    )
    (comp (ref "C309")
      (value "(OPT)姨0J332M-RBJ21")
      (footprint "PTH_CAPPR500-1300X2250")
      (description "姨0J332M-RBJ21")
      (libsource (lib "EPIQ_DND_CIS_Library") (part "C_POL"))
    )
    (comp (ref "C311")
      (value "1uF/16V")
      (footprint "SMD_0805_CAPC2012X145N")
      (description "Capacitor")
      (libsource (lib "*") (part "CAP"))
    )
    (comp (ref "C312")
      (value "100nF/50V")
      (footprint "SMD_0805_CAPC2012X145N")
      (description "Capacitor")
      (libsource (lib "*") (part "CAP"))
    )
    (comp (ref "C313")
      (value "(OPT)姨0J332M-RBJ21")
      (footprint "PTH_CAPPR500-1300X2250")
      (description "姨0J332M-RBJ21")
      (libsource (lib "EPIQ_DND_CIS_Library") (part "C_POL"))
    )
    (comp (ref "C314")
      (value "22uF/6.3V")
      (footprint "SMD_0805_CAPC2012X145N")
      (description "Capacitor")
      (libsource (lib "*") (part "CAP"))
    )
    (comp (ref "C315")
      (value "22uF/6.3V")
      (footprint "SMD_0805_CAPC2012X145N")
      (description "Capacitor")
      (libsource (lib "*") (part "CAP"))
    )
    (comp (ref "C316")
      (value "22uF/6.3V")
      (footprint "SMD_0805_CAPC2012X145N")
      (description "Capacitor")
      (libsource (lib "*") (part "CAP"))
    )
    (comp (ref "C317")
      (value "22uF/6.3V")
      (footprint "SMD_0805_CAPC2012X145N")
      (description "Capacitor")
      (libsource (lib "*") (part "CAP"))
    )
    (comp (ref "C318")
      (value "22uF/6.3V")
      (footprint "SMD_0805_CAPC2012X145N")
      (description "Capacitor")
      (libsource (lib "*") (part "CAP"))
    )
    (comp (ref "C319")
      (value "22uF/6.3V")
      (footprint "SMD_0805_CAPC2012X145N")
      (description "Capacitor")
      (libsource (lib "*") (part "CAP"))
    )
    (comp (ref "C320")
      (value "22uF/6.3V")
      (footprint "SMD_0805_CAPC2012X145N")
      (description "Capacitor")
      (libsource (lib "*") (part "CAP"))
    )
    (comp (ref "C321")
      (value "22uF/6.3V")
      (footprint "SMD_0805_CAPC2012X145N")
      (description "Capacitor")
      (libsource (lib "*") (part "CAP"))
    )
    (comp (ref "C322")
      (value "22uF/6.3V")
      (footprint "SMD_0805_CAPC2012X145N")
      (description "Capacitor")
      (libsource (lib "*") (part "CAP"))
    )
    (comp (ref "C323")
      (value "22uF/6.3V")
      (footprint "SMD_0805_CAPC2012X145N")
      (description "Capacitor")
      (libsource (lib "*") (part "CAP"))
    )
    (comp (ref "C324")
      (value "22uF/6.3V")
      (footprint "SMD_0805_CAPC2012X145N")
      (description "Capacitor")
      (libsource (lib "*") (part "CAP"))
    )
    (comp (ref "C325")
      (value "1nF")
      (footprint "SMD_0603_CAPC1608X80N")
      (description "Capacitor")
      (libsource (lib "*") (part "CAP"))
    )
    (comp (ref "C326")
      (value "470nF")
      (footprint "SMD_0603_CAPC1608X80N")
      (description "Capacitor (Semiconductor SIM Model)")
      (fields (field (name "PUBLISHER") "Altium Limited"))
      (libsource (lib "Miscellaneous Devices") (part "Cap Semi"))
    )
    (comp (ref "C327")
      (value "470nF")
      (footprint "SMD_0603_CAPC1608X80N")
      (description "Capacitor (Semiconductor SIM Model)")
      (fields (field (name "PUBLISHER") "Altium Limited"))
      (libsource (lib "Miscellaneous Devices") (part "Cap Semi"))
    )
    (comp (ref "C328")
      (value "470nF")
      (footprint "SMD_0603_CAPC1608X80N")
      (description "Capacitor (Semiconductor SIM Model)")
      (fields (field (name "PUBLISHER") "Altium Limited"))
      (libsource (lib "Miscellaneous Devices") (part "Cap Semi"))
    )
    (comp (ref "C329")
      (value "470nF")
      (footprint "SMD_0603_CAPC1608X80N")
      (description "Capacitor (Semiconductor SIM Model)")
      (fields (field (name "PUBLISHER") "Altium Limited"))
      (libsource (lib "Miscellaneous Devices") (part "Cap Semi"))
    )
    (comp (ref "C330")
      (value "470nF")
      (footprint "SMD_0603_CAPC1608X80N")
      (description "Capacitor (Semiconductor SIM Model)")
      (fields (field (name "PUBLISHER") "Altium Limited"))
      (libsource (lib "Miscellaneous Devices") (part "Cap Semi"))
    )
    (comp (ref "C331")
      (value "470nF")
      (footprint "SMD_0603_CAPC1608X80N")
      (description "Capacitor (Semiconductor SIM Model)")
      (fields (field (name "PUBLISHER") "Altium Limited"))
      (libsource (lib "Miscellaneous Devices") (part "Cap Semi"))
    )
    (comp (ref "C332")
      (value "470nF")
      (footprint "SMD_0603_CAPC1608X80N")
      (description "Capacitor (Semiconductor SIM Model)")
      (fields (field (name "PUBLISHER") "Altium Limited"))
      (libsource (lib "Miscellaneous Devices") (part "Cap Semi"))
    )
    (comp (ref "C333")
      (value "470nF")
      (footprint "SMD_0603_CAPC1608X80N")
      (description "Capacitor (Semiconductor SIM Model)")
      (fields (field (name "PUBLISHER") "Altium Limited"))
      (libsource (lib "Miscellaneous Devices") (part "Cap Semi"))
    )
    (comp (ref "C334")
      (value "470nF")
      (footprint "SMD_0603_CAPC1608X80N")
      (description "Capacitor (Semiconductor SIM Model)")
      (fields (field (name "PUBLISHER") "Altium Limited"))
      (libsource (lib "Miscellaneous Devices") (part "Cap Semi"))
    )
    (comp (ref "C335")
      (value "470nF")
      (footprint "SMD_0603_CAPC1608X80N")
      (description "Capacitor (Semiconductor SIM Model)")
      (fields (field (name "PUBLISHER") "Altium Limited"))
      (libsource (lib "Miscellaneous Devices") (part "Cap Semi"))
    )
    (comp (ref "C336")
      (value "470nF")
      (footprint "SMD_0603_CAPC1608X80N")
      (description "Capacitor (Semiconductor SIM Model)")
      (fields (field (name "PUBLISHER") "Altium Limited"))
      (libsource (lib "Miscellaneous Devices") (part "Cap Semi"))
    )
    (comp (ref "C337")
      (value "470nF")
      (footprint "SMD_0603_CAPC1608X80N")
      (description "Capacitor (Semiconductor SIM Model)")
      (fields (field (name "PUBLISHER") "Altium Limited"))
      (libsource (lib "Miscellaneous Devices") (part "Cap Semi"))
    )
    (comp (ref "C338")
      (value "470nF")
      (footprint "SMD_0603_CAPC1608X80N")
      (description "Capacitor (Semiconductor SIM Model)")
      (fields (field (name "PUBLISHER") "Altium Limited"))
      (libsource (lib "Miscellaneous Devices") (part "Cap Semi"))
    )
    (comp (ref "C339")
      (value "470nF")
      (footprint "SMD_0603_CAPC1608X80N")
      (description "Capacitor (Semiconductor SIM Model)")
      (fields (field (name "PUBLISHER") "Altium Limited"))
      (libsource (lib "Miscellaneous Devices") (part "Cap Semi"))
    )
    (comp (ref "C340")
      (value "470nF")
      (footprint "SMD_0603_CAPC1608X80N")
      (description "Capacitor (Semiconductor SIM Model)")
      (fields (field (name "PUBLISHER") "Altium Limited"))
      (libsource (lib "Miscellaneous Devices") (part "Cap Semi"))
    )
    (comp (ref "C341")
      (value "470nF")
      (footprint "SMD_0603_CAPC1608X80N")
      (description "Capacitor (Semiconductor SIM Model)")
      (fields (field (name "PUBLISHER") "Altium Limited"))
      (libsource (lib "Miscellaneous Devices") (part "Cap Semi"))
    )
    (comp (ref "C342")
      (value "470nF")
      (footprint "SMD_0603_CAPC1608X80N")
      (description "Capacitor (Semiconductor SIM Model)")
      (fields (field (name "PUBLISHER") "Altium Limited"))
      (libsource (lib "Miscellaneous Devices") (part "Cap Semi"))
    )
    (comp (ref "C343")
      (value "470nF")
      (footprint "SMD_0603_CAPC1608X80N")
      (description "Capacitor (Semiconductor SIM Model)")
      (fields (field (name "PUBLISHER") "Altium Limited"))
      (libsource (lib "Miscellaneous Devices") (part "Cap Semi"))
    )
    (comp (ref "C344")
      (value "470nF")
      (footprint "SMD_0603_CAPC1608X80N")
      (description "Capacitor (Semiconductor SIM Model)")
      (fields (field (name "PUBLISHER") "Altium Limited"))
      (libsource (lib "Miscellaneous Devices") (part "Cap Semi"))
    )
    (comp (ref "C345")
      (value "470nF")
      (footprint "SMD_0603_CAPC1608X80N")
      (description "Capacitor (Semiconductor SIM Model)")
      (fields (field (name "PUBLISHER") "Altium Limited"))
      (libsource (lib "Miscellaneous Devices") (part "Cap Semi"))
    )
    (comp (ref "C346")
      (value "470nF")
      (footprint "SMD_0603_CAPC1608X80N")
      (description "Capacitor (Semiconductor SIM Model)")
      (fields (field (name "PUBLISHER") "Altium Limited"))
      (libsource (lib "Miscellaneous Devices") (part "Cap Semi"))
    )
    (comp (ref "C347")
      (value "470nF")
      (footprint "SMD_0603_CAPC1608X80N")
      (description "Capacitor (Semiconductor SIM Model)")
      (fields (field (name "PUBLISHER") "Altium Limited"))
      (libsource (lib "Miscellaneous Devices") (part "Cap Semi"))
    )
    (comp (ref "C348")
      (value "470nF")
      (footprint "SMD_0603_CAPC1608X80N")
      (description "Capacitor (Semiconductor SIM Model)")
      (fields (field (name "PUBLISHER") "Altium Limited"))
      (libsource (lib "Miscellaneous Devices") (part "Cap Semi"))
    )
    (comp (ref "C349")
      (value "470nF")
      (footprint "SMD_0603_CAPC1608X80N")
      (description "Capacitor (Semiconductor SIM Model)")
      (fields (field (name "PUBLISHER") "Altium Limited"))
      (libsource (lib "Miscellaneous Devices") (part "Cap Semi"))
    )
    (comp (ref "C351")
      (value "470nF")
      (footprint "SMD_0603_CAPC1608X80N")
      (description "Capacitor (Semiconductor SIM Model)")
      (fields (field (name "PUBLISHER") "Altium Limited"))
      (libsource (lib "Miscellaneous Devices") (part "Cap Semi"))
    )
    (comp (ref "C352")
      (value "470nF")
      (footprint "SMD_0603_CAPC1608X80N")
      (description "Capacitor (Semiconductor SIM Model)")
      (fields (field (name "PUBLISHER") "Altium Limited"))
      (libsource (lib "Miscellaneous Devices") (part "Cap Semi"))
    )
    (comp (ref "C353")
      (value "470nF")
      (footprint "SMD_0603_CAPC1608X80N")
      (description "Capacitor (Semiconductor SIM Model)")
      (fields (field (name "PUBLISHER") "Altium Limited"))
      (libsource (lib "Miscellaneous Devices") (part "Cap Semi"))
    )
    (comp (ref "C355")
      (value "470nF")
      (footprint "SMD_0603_CAPC1608X80N")
      (description "Capacitor (Semiconductor SIM Model)")
      (fields (field (name "PUBLISHER") "Altium Limited"))
      (libsource (lib "Miscellaneous Devices") (part "Cap Semi"))
    )
    (comp (ref "C356")
      (value "470nF")
      (footprint "SMD_0603_CAPC1608X80N")
      (description "Capacitor (Semiconductor SIM Model)")
      (fields (field (name "PUBLISHER") "Altium Limited"))
      (libsource (lib "Miscellaneous Devices") (part "Cap Semi"))
    )
    (comp (ref "C358")
      (value "(OPT)220uF")
      (footprint "SMD_1210_CAPC3225X279N")
      (description "CL32A227MQVNNNE 220UF 6.3V 20% X5R 1210")
      (fields (field (name "PUBLISHER") "Altium Limited"))
      (libsource (lib "Miscellaneous Devices") (part "Cap Semi"))
    )
    (comp (ref "C359")
      (value "(OPT)220uF")
      (footprint "SMD_1210_CAPC3225X279N")
      (description "CL32A227MQVNNNE 220UF 6.3V 20% X5R 1210")
      (fields (field (name "PUBLISHER") "Altium Limited"))
      (libsource (lib "Miscellaneous Devices") (part "Cap Semi"))
    )
    (comp (ref "C360")
      (value "(OPT)220uF")
      (footprint "SMD_1210_CAPC3225X279N")
      (description "CL32A227MQVNNNE 220UF 6.3V 20% X5R 1210")
      (fields (field (name "PUBLISHER") "Altium Limited"))
      (libsource (lib "Miscellaneous Devices") (part "Cap Semi"))
    )
    (comp (ref "C361")
      (value "(OPT)220uF")
      (footprint "SMD_1210_CAPC3225X279N")
      (description "CL32A227MQVNNNE 220UF 6.3V 20% X5R 1210")
      (fields (field (name "PUBLISHER") "Altium Limited"))
      (libsource (lib "Miscellaneous Devices") (part "Cap Semi"))
    )
    (comp (ref "C362")
      (value "(OPT)220uF")
      (footprint "SMD_1210_CAPC3225X279N")
      (description "CL32A227MQVNNNE 220UF 6.3V 20% X5R 1210")
      (fields (field (name "PUBLISHER") "Altium Limited"))
      (libsource (lib "Miscellaneous Devices") (part "Cap Semi"))
    )
    (comp (ref "C363")
      (value "(OPT)220uF")
      (footprint "SMD_1210_CAPC3225X279N")
      (description "CL32A227MQVNNNE 220UF 6.3V 20% X5R 1210")
      (fields (field (name "PUBLISHER") "Altium Limited"))
      (libsource (lib "Miscellaneous Devices") (part "Cap Semi"))
    )
    (comp (ref "C364")
      (value "(OPT)220uF")
      (footprint "SMD_1210_CAPC3225X279N")
      (description "CL32A227MQVNNNE 220UF 6.3V 20% X5R 1210")
      (fields (field (name "PUBLISHER") "Altium Limited"))
      (libsource (lib "Miscellaneous Devices") (part "Cap Semi"))
    )
    (comp (ref "C365")
      (value "(OPT)220uF")
      (footprint "SMD_1210_CAPC3225X279N")
      (description "CL32A227MQVNNNE 220UF 6.3V 20% X5R 1210")
      (fields (field (name "PUBLISHER") "Altium Limited"))
      (libsource (lib "Miscellaneous Devices") (part "Cap Semi"))
    )
    (comp (ref "C366")
      (value "(OPT)220uF")
      (footprint "SMD_1210_CAPC3225X279N")
      (description "CL32A227MQVNNNE 220UF 6.3V 20% X5R 1210")
      (fields (field (name "PUBLISHER") "Altium Limited"))
      (libsource (lib "Miscellaneous Devices") (part "Cap Semi"))
    )
    (comp (ref "C367")
      (value "(OPT)220uF")
      (footprint "SMD_1210_CAPC3225X279N")
      (description "CL32A227MQVNNNE 220UF 6.3V 20% X5R 1210")
      (fields (field (name "PUBLISHER") "Altium Limited"))
      (libsource (lib "Miscellaneous Devices") (part "Cap Semi"))
    )
    (comp (ref "C368")
      (value "(OPT)220uF")
      (footprint "SMD_1210_CAPC3225X279N")
      (description "CL32A227MQVNNNE 220UF 6.3V 20% X5R 1210")
      (fields (field (name "PUBLISHER") "Altium Limited"))
      (libsource (lib "Miscellaneous Devices") (part "Cap Semi"))
    )
    (comp (ref "C369")
      (value "(OPT)220uF")
      (footprint "SMD_1210_CAPC3225X279N")
      (description "CL32A227MQVNNNE 220UF 6.3V 20% X5R 1210")
      (fields (field (name "PUBLISHER") "Altium Limited"))
      (libsource (lib "Miscellaneous Devices") (part "Cap Semi"))
    )
    (comp (ref "C370")
      (value "(OPT)220uF")
      (footprint "SMD_1210_CAPC3225X279N")
      (description "CL32A227MQVNNNE 220UF 6.3V 20% X5R 1210")
      (fields (field (name "PUBLISHER") "Altium Limited"))
      (libsource (lib "Miscellaneous Devices") (part "Cap Semi"))
    )
    (comp (ref "C371")
      (value "(OPT)220uF")
      (footprint "SMD_1210_CAPC3225X279N")
      (description "CL32A227MQVNNNE 220UF 6.3V 20% X5R 1210")
      (fields (field (name "PUBLISHER") "Altium Limited"))
      (libsource (lib "Miscellaneous Devices") (part "Cap Semi"))
    )
    (comp (ref "C372")
      (value "(OPT)220uF")
      (footprint "SMD_1210_CAPC3225X279N")
      (description "CL32A227MQVNNNE 220UF 6.3V 20% X5R 1210")
      (fields (field (name "PUBLISHER") "Altium Limited"))
      (libsource (lib "Miscellaneous Devices") (part "Cap Semi"))
    )
    (comp (ref "C373")
      (value "(OPT)220uF")
      (footprint "SMD_1210_CAPC3225X279N")
      (description "CL32A227MQVNNNE 220UF 6.3V 20% X5R 1210")
      (fields (field (name "PUBLISHER") "Altium Limited"))
      (libsource (lib "Miscellaneous Devices") (part "Cap Semi"))
    )
    (comp (ref "C374")
      (value "(OPT)220uF")
      (footprint "SMD_1210_CAPC3225X279N")
      (description "CL32A227MQVNNNE 220UF 6.3V 20% X5R 1210")
      (fields (field (name "PUBLISHER") "Altium Limited"))
      (libsource (lib "Miscellaneous Devices") (part "Cap Semi"))
    )
    (comp (ref "C375")
      (value "(OPT)220uF")
      (footprint "SMD_1210_CAPC3225X279N")
      (description "CL32A227MQVNNNE 220UF 6.3V 20% X5R 1210")
      (fields (field (name "PUBLISHER") "Altium Limited"))
      (libsource (lib "Miscellaneous Devices") (part "Cap Semi"))
    )
    (comp (ref "C376")
      (value "(OPT)220uF")
      (footprint "SMD_1210_CAPC3225X279N")
      (description "CL32A227MQVNNNE 220UF 6.3V 20% X5R 1210")
      (fields (field (name "PUBLISHER") "Altium Limited"))
      (libsource (lib "Miscellaneous Devices") (part "Cap Semi"))
    )
    (comp (ref "C377")
      (value "(OPT)220uF")
      (footprint "SMD_1210_CAPC3225X279N")
      (description "CL32A227MQVNNNE 220UF 6.3V 20% X5R 1210")
      (fields (field (name "PUBLISHER") "Altium Limited"))
      (libsource (lib "Miscellaneous Devices") (part "Cap Semi"))
    )
    (comp (ref "C378")
      (value "(OPT)220uF")
      (footprint "SMD_1210_CAPC3225X279N")
      (description "CL32A227MQVNNNE 220UF 6.3V 20% X5R 1210")
      (fields (field (name "PUBLISHER") "Altium Limited"))
      (libsource (lib "Miscellaneous Devices") (part "Cap Semi"))
    )
    (comp (ref "C379")
      (value "(OPT)220uF")
      (footprint "SMD_1210_CAPC3225X279N")
      (description "CL32A227MQVNNNE 220UF 6.3V 20% X5R 1210")
      (fields (field (name "PUBLISHER") "Altium Limited"))
      (libsource (lib "Miscellaneous Devices") (part "Cap Semi"))
    )
    (comp (ref "C380")
      (value "(OPT)220uF")
      (footprint "SMD_1210_CAPC3225X279N")
      (description "CL32A227MQVNNNE 220UF 6.3V 20% X5R 1210")
      (fields (field (name "PUBLISHER") "Altium Limited"))
      (libsource (lib "Miscellaneous Devices") (part "Cap Semi"))
    )
    (comp (ref "C381")
      (value "(OPT)220uF")
      (footprint "SMD_1210_CAPC3225X279N")
      (description "CL32A227MQVNNNE 220UF 6.3V 20% X5R 1210")
      (fields (field (name "PUBLISHER") "Altium Limited"))
      (libsource (lib "Miscellaneous Devices") (part "Cap Semi"))
    )
    (comp (ref "C382")
      (value "(OPT)220uF")
      (footprint "SMD_1210_CAPC3225X279N")
      (description "CL32A227MQVNNNE 220UF 6.3V 20% X5R 1210")
      (fields (field (name "PUBLISHER") "Altium Limited"))
      (libsource (lib "Miscellaneous Devices") (part "Cap Semi"))
    )
    (comp (ref "C383")
      (value "(OPT)220uF")
      (footprint "SMD_1210_CAPC3225X279N")
      (description "CL32A227MQVNNNE 220UF 6.3V 20% X5R 1210")
      (fields (field (name "PUBLISHER") "Altium Limited"))
      (libsource (lib "Miscellaneous Devices") (part "Cap Semi"))
    )
    (comp (ref "C384")
      (value "(OPT)220uF")
      (footprint "SMD_1210_CAPC3225X279N")
      (description "CL32A227MQVNNNE 220UF 6.3V 20% X5R 1210")
      (fields (field (name "PUBLISHER") "Altium Limited"))
      (libsource (lib "Miscellaneous Devices") (part "Cap Semi"))
    )
    (comp (ref "C385")
      (value "(OPT)220uF")
      (footprint "SMD_1210_CAPC3225X279N")
      (description "CL32A227MQVNNNE 220UF 6.3V 20% X5R 1210")
      (fields (field (name "PUBLISHER") "Altium Limited"))
      (libsource (lib "Miscellaneous Devices") (part "Cap Semi"))
    )
    (comp (ref "C386")
      (value "(OPT)220uF")
      (footprint "SMD_1210_CAPC3225X279N")
      (description "CL32A227MQVNNNE 220UF 6.3V 20% X5R 1210")
      (fields (field (name "PUBLISHER") "Altium Limited"))
      (libsource (lib "Miscellaneous Devices") (part "Cap Semi"))
    )
    (comp (ref "C387")
      (value "(OPT)220uF")
      (footprint "SMD_1210_CAPC3225X279N")
      (description "CL32A227MQVNNNE 220UF 6.3V 20% X5R 1210")
      (fields (field (name "PUBLISHER") "Altium Limited"))
      (libsource (lib "Miscellaneous Devices") (part "Cap Semi"))
    )
    (comp (ref "C388")
      (value "470nF")
      (footprint "SMD_0603_CAPC1608X80N")
      (description "Capacitor (Semiconductor SIM Model)")
      (fields (field (name "PUBLISHER") "Altium Limited"))
      (libsource (lib "Miscellaneous Devices") (part "Cap Semi"))
    )
    (comp (ref "C389")
      (value "470nF")
      (footprint "SMD_0603_CAPC1608X80N")
      (description "Capacitor (Semiconductor SIM Model)")
      (fields (field (name "PUBLISHER") "Altium Limited"))
      (libsource (lib "Miscellaneous Devices") (part "Cap Semi"))
    )
    (comp (ref "C390")
      (value "470nF")
      (footprint "SMD_0603_CAPC1608X80N")
      (description "Capacitor (Semiconductor SIM Model)")
      (fields (field (name "PUBLISHER") "Altium Limited"))
      (libsource (lib "Miscellaneous Devices") (part "Cap Semi"))
    )
    (comp (ref "C391")
      (value "470nF")
      (footprint "SMD_0603_CAPC1608X80N")
      (description "Capacitor (Semiconductor SIM Model)")
      (fields (field (name "PUBLISHER") "Altium Limited"))
      (libsource (lib "Miscellaneous Devices") (part "Cap Semi"))
    )
    (comp (ref "C392")
      (value "470nF")
      (footprint "SMD_0603_CAPC1608X80N")
      (description "Capacitor (Semiconductor SIM Model)")
      (fields (field (name "PUBLISHER") "Altium Limited"))
      (libsource (lib "Miscellaneous Devices") (part "Cap Semi"))
    )
    (comp (ref "C393")
      (value "470nF")
      (footprint "SMD_0603_CAPC1608X80N")
      (description "Capacitor (Semiconductor SIM Model)")
      (fields (field (name "PUBLISHER") "Altium Limited"))
      (libsource (lib "Miscellaneous Devices") (part "Cap Semi"))
    )
    (comp (ref "C394")
      (value "470nF")
      (footprint "SMD_0603_CAPC1608X80N")
      (description "Capacitor (Semiconductor SIM Model)")
      (fields (field (name "PUBLISHER") "Altium Limited"))
      (libsource (lib "Miscellaneous Devices") (part "Cap Semi"))
    )
    (comp (ref "C395")
      (value "470nF")
      (footprint "SMD_0603_CAPC1608X80N")
      (description "Capacitor (Semiconductor SIM Model)")
      (fields (field (name "PUBLISHER") "Altium Limited"))
      (libsource (lib "Miscellaneous Devices") (part "Cap Semi"))
    )
    (comp (ref "C396")
      (value "470nF")
      (footprint "SMD_0603_CAPC1608X80N")
      (description "Capacitor (Semiconductor SIM Model)")
      (fields (field (name "PUBLISHER") "Altium Limited"))
      (libsource (lib "Miscellaneous Devices") (part "Cap Semi"))
    )
    (comp (ref "C397")
      (value "470nF")
      (footprint "SMD_0603_CAPC1608X80N")
      (description "Capacitor (Semiconductor SIM Model)")
      (fields (field (name "PUBLISHER") "Altium Limited"))
      (libsource (lib "Miscellaneous Devices") (part "Cap Semi"))
    )
    (comp (ref "C398")
      (value "470nF")
      (footprint "SMD_0603_CAPC1608X80N")
      (description "Capacitor (Semiconductor SIM Model)")
      (fields (field (name "PUBLISHER") "Altium Limited"))
      (libsource (lib "Miscellaneous Devices") (part "Cap Semi"))
    )
    (comp (ref "C399")
      (value "470nF")
      (footprint "SMD_0603_CAPC1608X80N")
      (description "Capacitor (Semiconductor SIM Model)")
      (fields (field (name "PUBLISHER") "Altium Limited"))
      (libsource (lib "Miscellaneous Devices") (part "Cap Semi"))
    )
    (comp (ref "C400")
      (value "470nF")
      (footprint "SMD_0603_CAPC1608X80N")
      (description "Capacitor (Semiconductor SIM Model)")
      (fields (field (name "PUBLISHER") "Altium Limited"))
      (libsource (lib "Miscellaneous Devices") (part "Cap Semi"))
    )
    (comp (ref "C401")
      (value "470nF")
      (footprint "SMD_0603_CAPC1608X80N")
      (description "Capacitor (Semiconductor SIM Model)")
      (fields (field (name "PUBLISHER") "Altium Limited"))
      (libsource (lib "Miscellaneous Devices") (part "Cap Semi"))
    )
    (comp (ref "C402")
      (value "470nF")
      (footprint "SMD_0603_CAPC1608X80N")
      (description "Capacitor (Semiconductor SIM Model)")
      (fields (field (name "PUBLISHER") "Altium Limited"))
      (libsource (lib "Miscellaneous Devices") (part "Cap Semi"))
    )
    (comp (ref "C403")
      (value "470nF")
      (footprint "SMD_0603_CAPC1608X80N")
      (description "Capacitor (Semiconductor SIM Model)")
      (fields (field (name "PUBLISHER") "Altium Limited"))
      (libsource (lib "Miscellaneous Devices") (part "Cap Semi"))
    )
    (comp (ref "C404")
      (value "470nF")
      (footprint "SMD_0603_CAPC1608X80N")
      (description "Capacitor (Semiconductor SIM Model)")
      (fields (field (name "PUBLISHER") "Altium Limited"))
      (libsource (lib "Miscellaneous Devices") (part "Cap Semi"))
    )
    (comp (ref "C405")
      (value "470nF")
      (footprint "SMD_0603_CAPC1608X80N")
      (description "Capacitor (Semiconductor SIM Model)")
      (fields (field (name "PUBLISHER") "Altium Limited"))
      (libsource (lib "Miscellaneous Devices") (part "Cap Semi"))
    )
    (comp (ref "C406")
      (value "470nF")
      (footprint "SMD_0603_CAPC1608X80N")
      (description "Capacitor (Semiconductor SIM Model)")
      (fields (field (name "PUBLISHER") "Altium Limited"))
      (libsource (lib "Miscellaneous Devices") (part "Cap Semi"))
    )
    (comp (ref "C407")
      (value "470nF")
      (footprint "SMD_0603_CAPC1608X80N")
      (description "Capacitor (Semiconductor SIM Model)")
      (fields (field (name "PUBLISHER") "Altium Limited"))
      (libsource (lib "Miscellaneous Devices") (part "Cap Semi"))
    )
    (comp (ref "C408")
      (value "470nF")
      (footprint "SMD_0603_CAPC1608X80N")
      (description "Capacitor (Semiconductor SIM Model)")
      (fields (field (name "PUBLISHER") "Altium Limited"))
      (libsource (lib "Miscellaneous Devices") (part "Cap Semi"))
    )
    (comp (ref "C409")
      (value "470nF")
      (footprint "SMD_0603_CAPC1608X80N")
      (description "Capacitor (Semiconductor SIM Model)")
      (fields (field (name "PUBLISHER") "Altium Limited"))
      (libsource (lib "Miscellaneous Devices") (part "Cap Semi"))
    )
    (comp (ref "C410")
      (value "470nF")
      (footprint "SMD_0603_CAPC1608X80N")
      (description "Capacitor (Semiconductor SIM Model)")
      (fields (field (name "PUBLISHER") "Altium Limited"))
      (libsource (lib "Miscellaneous Devices") (part "Cap Semi"))
    )
    (comp (ref "C411")
      (value "470nF")
      (footprint "SMD_0603_CAPC1608X80N")
      (description "Capacitor (Semiconductor SIM Model)")
      (fields (field (name "PUBLISHER") "Altium Limited"))
      (libsource (lib "Miscellaneous Devices") (part "Cap Semi"))
    )
    (comp (ref "C412")
      (value "470nF")
      (footprint "SMD_0603_CAPC1608X80N")
      (description "Capacitor (Semiconductor SIM Model)")
      (fields (field (name "PUBLISHER") "Altium Limited"))
      (libsource (lib "Miscellaneous Devices") (part "Cap Semi"))
    )
    (comp (ref "C413")
      (value "470nF")
      (footprint "SMD_0603_CAPC1608X80N")
      (description "Capacitor (Semiconductor SIM Model)")
      (fields (field (name "PUBLISHER") "Altium Limited"))
      (libsource (lib "Miscellaneous Devices") (part "Cap Semi"))
    )
    (comp (ref "C414")
      (value "470nF")
      (footprint "SMD_0603_CAPC1608X80N")
      (description "Capacitor (Semiconductor SIM Model)")
      (fields (field (name "PUBLISHER") "Altium Limited"))
      (libsource (lib "Miscellaneous Devices") (part "Cap Semi"))
    )
    (comp (ref "C415")
      (value "470nF")
      (footprint "SMD_0603_CAPC1608X80N")
      (description "Capacitor (Semiconductor SIM Model)")
      (fields (field (name "PUBLISHER") "Altium Limited"))
      (libsource (lib "Miscellaneous Devices") (part "Cap Semi"))
    )
    (comp (ref "C416")
      (value "470nF")
      (footprint "SMD_0603_CAPC1608X80N")
      (description "Capacitor (Semiconductor SIM Model)")
      (fields (field (name "PUBLISHER") "Altium Limited"))
      (libsource (lib "Miscellaneous Devices") (part "Cap Semi"))
    )
    (comp (ref "C417")
      (value "470nF")
      (footprint "SMD_0603_CAPC1608X80N")
      (description "Capacitor (Semiconductor SIM Model)")
      (fields (field (name "PUBLISHER") "Altium Limited"))
      (libsource (lib "Miscellaneous Devices") (part "Cap Semi"))
    )
    (comp (ref "C418")
      (value "470nF")
      (footprint "SMD_0603_CAPC1608X80N")
      (description "Capacitor (Semiconductor SIM Model)")
      (fields (field (name "PUBLISHER") "Altium Limited"))
      (libsource (lib "Miscellaneous Devices") (part "Cap Semi"))
    )
    (comp (ref "C419")
      (value "470nF")
      (footprint "SMD_0603_CAPC1608X80N")
      (description "Capacitor (Semiconductor SIM Model)")
      (fields (field (name "PUBLISHER") "Altium Limited"))
      (libsource (lib "Miscellaneous Devices") (part "Cap Semi"))
    )
    (comp (ref "C420")
      (value "470nF")
      (footprint "SMD_0603_CAPC1608X80N")
      (description "Capacitor (Semiconductor SIM Model)")
      (fields (field (name "PUBLISHER") "Altium Limited"))
      (libsource (lib "Miscellaneous Devices") (part "Cap Semi"))
    )
    (comp (ref "C421")
      (value "470nF")
      (footprint "SMD_0603_CAPC1608X80N")
      (description "Capacitor (Semiconductor SIM Model)")
      (fields (field (name "PUBLISHER") "Altium Limited"))
      (libsource (lib "Miscellaneous Devices") (part "Cap Semi"))
    )
    (comp (ref "C422")
      (value "470nF")
      (footprint "SMD_0603_CAPC1608X80N")
      (description "Capacitor (Semiconductor SIM Model)")
      (fields (field (name "PUBLISHER") "Altium Limited"))
      (libsource (lib "Miscellaneous Devices") (part "Cap Semi"))
    )
    (comp (ref "C423")
      (value "470nF")
      (footprint "SMD_0603_CAPC1608X80N")
      (description "Capacitor (Semiconductor SIM Model)")
      (fields (field (name "PUBLISHER") "Altium Limited"))
      (libsource (lib "Miscellaneous Devices") (part "Cap Semi"))
    )
    (comp (ref "C424")
      (value "470nF")
      (footprint "SMD_0603_CAPC1608X80N")
      (description "Capacitor (Semiconductor SIM Model)")
      (fields (field (name "PUBLISHER") "Altium Limited"))
      (libsource (lib "Miscellaneous Devices") (part "Cap Semi"))
    )
    (comp (ref "C427")
      (value "470nF")
      (footprint "SMD_0603_CAPC1608X80N")
      (description "Capacitor (Semiconductor SIM Model)")
      (fields (field (name "PUBLISHER") "Altium Limited"))
      (libsource (lib "Miscellaneous Devices") (part "Cap Semi"))
    )
    (comp (ref "C428")
      (value "470nF")
      (footprint "SMD_0603_CAPC1608X80N")
      (description "Capacitor (Semiconductor SIM Model)")
      (fields (field (name "PUBLISHER") "Altium Limited"))
      (libsource (lib "Miscellaneous Devices") (part "Cap Semi"))
    )
    (comp (ref "C429")
      (value "470nF")
      (footprint "SMD_0603_CAPC1608X80N")
      (description "Capacitor (Semiconductor SIM Model)")
      (fields (field (name "PUBLISHER") "Altium Limited"))
      (libsource (lib "Miscellaneous Devices") (part "Cap Semi"))
    )
    (comp (ref "C430")
      (value "470nF")
      (footprint "SMD_0603_CAPC1608X80N")
      (description "Capacitor (Semiconductor SIM Model)")
      (fields (field (name "PUBLISHER") "Altium Limited"))
      (libsource (lib "Miscellaneous Devices") (part "Cap Semi"))
    )
    (comp (ref "C431")
      (value "470nF")
      (footprint "SMD_0603_CAPC1608X80N")
      (description "Capacitor (Semiconductor SIM Model)")
      (fields (field (name "PUBLISHER") "Altium Limited"))
      (libsource (lib "Miscellaneous Devices") (part "Cap Semi"))
    )
    (comp (ref "C432")
      (value "470nF")
      (footprint "SMD_0603_CAPC1608X80N")
      (description "Capacitor (Semiconductor SIM Model)")
      (fields (field (name "PUBLISHER") "Altium Limited"))
      (libsource (lib "Miscellaneous Devices") (part "Cap Semi"))
    )
    (comp (ref "C433")
      (value "470nF")
      (footprint "SMD_0603_CAPC1608X80N")
      (description "Capacitor (Semiconductor SIM Model)")
      (fields (field (name "PUBLISHER") "Altium Limited"))
      (libsource (lib "Miscellaneous Devices") (part "Cap Semi"))
    )
    (comp (ref "C434")
      (value "470nF")
      (footprint "SMD_0603_CAPC1608X80N")
      (description "Capacitor (Semiconductor SIM Model)")
      (fields (field (name "PUBLISHER") "Altium Limited"))
      (libsource (lib "Miscellaneous Devices") (part "Cap Semi"))
    )
    (comp (ref "C435")
      (value "470nF")
      (footprint "SMD_0603_CAPC1608X80N")
      (description "Capacitor (Semiconductor SIM Model)")
      (fields (field (name "PUBLISHER") "Altium Limited"))
      (libsource (lib "Miscellaneous Devices") (part "Cap Semi"))
    )
    (comp (ref "C436")
      (value "470nF")
      (footprint "SMD_0603_CAPC1608X80N")
      (description "Capacitor (Semiconductor SIM Model)")
      (fields (field (name "PUBLISHER") "Altium Limited"))
      (libsource (lib "Miscellaneous Devices") (part "Cap Semi"))
    )
    (comp (ref "C439")
      (value "470nF")
      (footprint "SMD_0603_CAPC1608X80N")
      (description "Capacitor (Semiconductor SIM Model)")
      (fields (field (name "PUBLISHER") "Altium Limited"))
      (libsource (lib "Miscellaneous Devices") (part "Cap Semi"))
    )
    (comp (ref "C440")
      (value "470nF")
      (footprint "SMD_0603_CAPC1608X80N")
      (description "Capacitor (Semiconductor SIM Model)")
      (fields (field (name "PUBLISHER") "Altium Limited"))
      (libsource (lib "Miscellaneous Devices") (part "Cap Semi"))
    )
    (comp (ref "C441")
      (value "470nF")
      (footprint "SMD_0603_CAPC1608X80N")
      (description "Capacitor (Semiconductor SIM Model)")
      (fields (field (name "PUBLISHER") "Altium Limited"))
      (libsource (lib "Miscellaneous Devices") (part "Cap Semi"))
    )
    (comp (ref "C442")
      (value "470nF")
      (footprint "SMD_0603_CAPC1608X80N")
      (description "Capacitor (Semiconductor SIM Model)")
      (fields (field (name "PUBLISHER") "Altium Limited"))
      (libsource (lib "Miscellaneous Devices") (part "Cap Semi"))
    )
    (comp (ref "C443")
      (value "470nF")
      (footprint "SMD_0603_CAPC1608X80N")
      (description "Capacitor (Semiconductor SIM Model)")
      (fields (field (name "PUBLISHER") "Altium Limited"))
      (libsource (lib "Miscellaneous Devices") (part "Cap Semi"))
    )
    (comp (ref "C444")
      (value "470nF")
      (footprint "SMD_0603_CAPC1608X80N")
      (description "Capacitor (Semiconductor SIM Model)")
      (fields (field (name "PUBLISHER") "Altium Limited"))
      (libsource (lib "Miscellaneous Devices") (part "Cap Semi"))
    )
    (comp (ref "C445")
      (value "470nF")
      (footprint "SMD_0603_CAPC1608X80N")
      (description "Capacitor (Semiconductor SIM Model)")
      (fields (field (name "PUBLISHER") "Altium Limited"))
      (libsource (lib "Miscellaneous Devices") (part "Cap Semi"))
    )
    (comp (ref "C446")
      (value "470nF")
      (footprint "SMD_0603_CAPC1608X80N")
      (description "Capacitor (Semiconductor SIM Model)")
      (fields (field (name "PUBLISHER") "Altium Limited"))
      (libsource (lib "Miscellaneous Devices") (part "Cap Semi"))
    )
    (comp (ref "C447")
      (value "470nF")
      (footprint "SMD_0603_CAPC1608X80N")
      (description "Capacitor (Semiconductor SIM Model)")
      (fields (field (name "PUBLISHER") "Altium Limited"))
      (libsource (lib "Miscellaneous Devices") (part "Cap Semi"))
    )
    (comp (ref "C448")
      (value "470nF")
      (footprint "SMD_0603_CAPC1608X80N")
      (description "Capacitor (Semiconductor SIM Model)")
      (fields (field (name "PUBLISHER") "Altium Limited"))
      (libsource (lib "Miscellaneous Devices") (part "Cap Semi"))
    )
    (comp (ref "C449")
      (value "470nF")
      (footprint "SMD_0603_CAPC1608X80N")
      (description "Capacitor (Semiconductor SIM Model)")
      (fields (field (name "PUBLISHER") "Altium Limited"))
      (libsource (lib "Miscellaneous Devices") (part "Cap Semi"))
    )
    (comp (ref "C450")
      (value "470nF")
      (footprint "SMD_0603_CAPC1608X80N")
      (description "Capacitor (Semiconductor SIM Model)")
      (fields (field (name "PUBLISHER") "Altium Limited"))
      (libsource (lib "Miscellaneous Devices") (part "Cap Semi"))
    )
    (comp (ref "C451")
      (value "470nF")
      (footprint "SMD_0603_CAPC1608X80N")
      (description "Capacitor (Semiconductor SIM Model)")
      (fields (field (name "PUBLISHER") "Altium Limited"))
      (libsource (lib "Miscellaneous Devices") (part "Cap Semi"))
    )
    (comp (ref "C452")
      (value "470nF")
      (footprint "SMD_0603_CAPC1608X80N")
      (description "Capacitor (Semiconductor SIM Model)")
      (fields (field (name "PUBLISHER") "Altium Limited"))
      (libsource (lib "Miscellaneous Devices") (part "Cap Semi"))
    )
    (comp (ref "C453")
      (value "470nF")
      (footprint "SMD_0603_CAPC1608X80N")
      (description "Capacitor (Semiconductor SIM Model)")
      (fields (field (name "PUBLISHER") "Altium Limited"))
      (libsource (lib "Miscellaneous Devices") (part "Cap Semi"))
    )
    (comp (ref "C454")
      (value "470nF")
      (footprint "SMD_0603_CAPC1608X80N")
      (description "Capacitor (Semiconductor SIM Model)")
      (fields (field (name "PUBLISHER") "Altium Limited"))
      (libsource (lib "Miscellaneous Devices") (part "Cap Semi"))
    )
    (comp (ref "C455")
      (value "470nF")
      (footprint "SMD_0603_CAPC1608X80N")
      (description "Capacitor (Semiconductor SIM Model)")
      (fields (field (name "PUBLISHER") "Altium Limited"))
      (libsource (lib "Miscellaneous Devices") (part "Cap Semi"))
    )
    (comp (ref "C456")
      (value "470nF")
      (footprint "SMD_0603_CAPC1608X80N")
      (description "Capacitor (Semiconductor SIM Model)")
      (fields (field (name "PUBLISHER") "Altium Limited"))
      (libsource (lib "Miscellaneous Devices") (part "Cap Semi"))
    )
    (comp (ref "C457")
      (value "470nF")
      (footprint "SMD_0603_CAPC1608X80N")
      (description "Capacitor (Semiconductor SIM Model)")
      (fields (field (name "PUBLISHER") "Altium Limited"))
      (libsource (lib "Miscellaneous Devices") (part "Cap Semi"))
    )
    (comp (ref "C458")
      (value "470nF")
      (footprint "SMD_0603_CAPC1608X80N")
      (description "Capacitor (Semiconductor SIM Model)")
      (fields (field (name "PUBLISHER") "Altium Limited"))
      (libsource (lib "Miscellaneous Devices") (part "Cap Semi"))
    )
    (comp (ref "C459")
      (value "470nF")
      (footprint "SMD_0603_CAPC1608X80N")
      (description "Capacitor (Semiconductor SIM Model)")
      (fields (field (name "PUBLISHER") "Altium Limited"))
      (libsource (lib "Miscellaneous Devices") (part "Cap Semi"))
    )
    (comp (ref "C460")
      (value "470nF")
      (footprint "SMD_0603_CAPC1608X80N")
      (description "Capacitor (Semiconductor SIM Model)")
      (fields (field (name "PUBLISHER") "Altium Limited"))
      (libsource (lib "Miscellaneous Devices") (part "Cap Semi"))
    )
    (comp (ref "C461")
      (value "470nF")
      (footprint "SMD_0603_CAPC1608X80N")
      (description "Capacitor (Semiconductor SIM Model)")
      (fields (field (name "PUBLISHER") "Altium Limited"))
      (libsource (lib "Miscellaneous Devices") (part "Cap Semi"))
    )
    (comp (ref "C462")
      (value "470nF")
      (footprint "SMD_0603_CAPC1608X80N")
      (description "Capacitor (Semiconductor SIM Model)")
      (fields (field (name "PUBLISHER") "Altium Limited"))
      (libsource (lib "Miscellaneous Devices") (part "Cap Semi"))
    )
    (comp (ref "C463")
      (value "470nF")
      (footprint "SMD_0603_CAPC1608X80N")
      (description "Capacitor (Semiconductor SIM Model)")
      (fields (field (name "PUBLISHER") "Altium Limited"))
      (libsource (lib "Miscellaneous Devices") (part "Cap Semi"))
    )
    (comp (ref "C464")
      (value "470nF")
      (footprint "SMD_0603_CAPC1608X80N")
      (description "Capacitor (Semiconductor SIM Model)")
      (fields (field (name "PUBLISHER") "Altium Limited"))
      (libsource (lib "Miscellaneous Devices") (part "Cap Semi"))
    )
    (comp (ref "C465")
      (value "470nF")
      (footprint "SMD_0603_CAPC1608X80N")
      (description "Capacitor (Semiconductor SIM Model)")
      (fields (field (name "PUBLISHER") "Altium Limited"))
      (libsource (lib "Miscellaneous Devices") (part "Cap Semi"))
    )
    (comp (ref "C466")
      (value "470nF")
      (footprint "SMD_0603_CAPC1608X80N")
      (description "Capacitor (Semiconductor SIM Model)")
      (fields (field (name "PUBLISHER") "Altium Limited"))
      (libsource (lib "Miscellaneous Devices") (part "Cap Semi"))
    )
    (comp (ref "C467")
      (value "470nF")
      (footprint "SMD_0603_CAPC1608X80N")
      (description "Capacitor (Semiconductor SIM Model)")
      (fields (field (name "PUBLISHER") "Altium Limited"))
      (libsource (lib "Miscellaneous Devices") (part "Cap Semi"))
    )
    (comp (ref "C468")
      (value "470nF")
      (footprint "SMD_0603_CAPC1608X80N")
      (description "Capacitor (Semiconductor SIM Model)")
      (fields (field (name "PUBLISHER") "Altium Limited"))
      (libsource (lib "Miscellaneous Devices") (part "Cap Semi"))
    )
    (comp (ref "C469")
      (value "470nF")
      (footprint "SMD_0603_CAPC1608X80N")
      (description "Capacitor (Semiconductor SIM Model)")
      (fields (field (name "PUBLISHER") "Altium Limited"))
      (libsource (lib "Miscellaneous Devices") (part "Cap Semi"))
    )
    (comp (ref "C470")
      (value "470nF")
      (footprint "SMD_0603_CAPC1608X80N")
      (description "Capacitor (Semiconductor SIM Model)")
      (fields (field (name "PUBLISHER") "Altium Limited"))
      (libsource (lib "Miscellaneous Devices") (part "Cap Semi"))
    )
    (comp (ref "C471")
      (value "470nF")
      (footprint "SMD_0603_CAPC1608X80N")
      (description "Capacitor (Semiconductor SIM Model)")
      (fields (field (name "PUBLISHER") "Altium Limited"))
      (libsource (lib "Miscellaneous Devices") (part "Cap Semi"))
    )
    (comp (ref "C472")
      (value "470nF")
      (footprint "SMD_0603_CAPC1608X80N")
      (description "Capacitor (Semiconductor SIM Model)")
      (fields (field (name "PUBLISHER") "Altium Limited"))
      (libsource (lib "Miscellaneous Devices") (part "Cap Semi"))
    )
    (comp (ref "C475")
      (value "470nF")
      (footprint "SMD_0603_CAPC1608X80N")
      (description "Capacitor (Semiconductor SIM Model)")
      (fields (field (name "PUBLISHER") "Altium Limited"))
      (libsource (lib "Miscellaneous Devices") (part "Cap Semi"))
    )
    (comp (ref "C476")
      (value "470nF")
      (footprint "SMD_0603_CAPC1608X80N")
      (description "Capacitor (Semiconductor SIM Model)")
      (fields (field (name "PUBLISHER") "Altium Limited"))
      (libsource (lib "Miscellaneous Devices") (part "Cap Semi"))
    )
    (comp (ref "C477")
      (value "470nF")
      (footprint "SMD_0603_CAPC1608X80N")
      (description "Capacitor (Semiconductor SIM Model)")
      (fields (field (name "PUBLISHER") "Altium Limited"))
      (libsource (lib "Miscellaneous Devices") (part "Cap Semi"))
    )
    (comp (ref "C478")
      (value "470nF")
      (footprint "SMD_0603_CAPC1608X80N")
      (description "Capacitor (Semiconductor SIM Model)")
      (fields (field (name "PUBLISHER") "Altium Limited"))
      (libsource (lib "Miscellaneous Devices") (part "Cap Semi"))
    )
    (comp (ref "C479")
      (value "470nF")
      (footprint "SMD_0603_CAPC1608X80N")
      (description "Capacitor (Semiconductor SIM Model)")
      (fields (field (name "PUBLISHER") "Altium Limited"))
      (libsource (lib "Miscellaneous Devices") (part "Cap Semi"))
    )
    (comp (ref "C480")
      (value "470nF")
      (footprint "SMD_0603_CAPC1608X80N")
      (description "Capacitor (Semiconductor SIM Model)")
      (fields (field (name "PUBLISHER") "Altium Limited"))
      (libsource (lib "Miscellaneous Devices") (part "Cap Semi"))
    )
    (comp (ref "C481")
      (value "470nF")
      (footprint "SMD_0603_CAPC1608X80N")
      (description "Capacitor (Semiconductor SIM Model)")
      (fields (field (name "PUBLISHER") "Altium Limited"))
      (libsource (lib "Miscellaneous Devices") (part "Cap Semi"))
    )
    (comp (ref "C482")
      (value "470nF")
      (footprint "SMD_0603_CAPC1608X80N")
      (description "Capacitor (Semiconductor SIM Model)")
      (fields (field (name "PUBLISHER") "Altium Limited"))
      (libsource (lib "Miscellaneous Devices") (part "Cap Semi"))
    )
    (comp (ref "C483")
      (value "470nF")
      (footprint "SMD_0603_CAPC1608X80N")
      (description "Capacitor (Semiconductor SIM Model)")
      (fields (field (name "PUBLISHER") "Altium Limited"))
      (libsource (lib "Miscellaneous Devices") (part "Cap Semi"))
    )
    (comp (ref "C489")
      (value "(OPT)100uF")
      (footprint "SMD_1210_CAPC3225X279N")
      (description "CL32A227MQVNNNE 220UF 6.3V 20% X5R 1210")
      (fields (field (name "PUBLISHER") "Altium Limited"))
      (libsource (lib "Miscellaneous Devices") (part "Cap Semi"))
    )
    (comp (ref "C491")
      (value "(OPT)100uF")
      (footprint "SMD_1210_CAPC3225X279N")
      (description "CL32A227MQVNNNE 220UF 6.3V 20% X5R 1210")
      (fields (field (name "PUBLISHER") "Altium Limited"))
      (libsource (lib "Miscellaneous Devices") (part "Cap Semi"))
    )
    (comp (ref "C493")
      (value "(OPT)100uF")
      (footprint "SMD_1210_CAPC3225X279N")
      (description "CL32A227MQVNNNE 220UF 6.3V 20% X5R 1210")
      (fields (field (name "PUBLISHER") "Altium Limited"))
      (libsource (lib "Miscellaneous Devices") (part "Cap Semi"))
    )
    (comp (ref "C494")
      (value "(OPT)100uF")
      (footprint "SMD_1210_CAPC3225X279N")
      (description "CL32A227MQVNNNE 220UF 6.3V 20% X5R 1210")
      (fields (field (name "PUBLISHER") "Altium Limited"))
      (libsource (lib "Miscellaneous Devices") (part "Cap Semi"))
    )
    (comp (ref "C495")
      (value "(OPT)100uF")
      (footprint "SMD_1210_CAPC3225X279N")
      (description "CL32A227MQVNNNE 220UF 6.3V 20% X5R 1210")
      (fields (field (name "PUBLISHER") "Altium Limited"))
      (libsource (lib "Miscellaneous Devices") (part "Cap Semi"))
    )
    (comp (ref "C501")
      (value "(OPT)100uF")
      (footprint "SMD_1210_CAPC3225X279N")
      (description "CL32A227MQVNNNE 220UF 6.3V 20% X5R 1210")
      (fields (field (name "PUBLISHER") "Altium Limited"))
      (libsource (lib "Miscellaneous Devices") (part "Cap Semi"))
    )
    (comp (ref "C503")
      (value "(OPT)220uF")
      (footprint "SMD_1210_CAPC3225X279N")
      (description "CL32A227MQVNNNE 220UF 6.3V 20% X5R 1210")
      (fields (field (name "PUBLISHER") "Altium Limited"))
      (libsource (lib "Miscellaneous Devices") (part "Cap Semi"))
    )
    (comp (ref "C504")
      (value "(OPT)220uF")
      (footprint "SMD_1210_CAPC3225X279N")
      (description "CL32A227MQVNNNE 220UF 6.3V 20% X5R 1210")
      (fields (field (name "PUBLISHER") "Altium Limited"))
      (libsource (lib "Miscellaneous Devices") (part "Cap Semi"))
    )
    (comp (ref "C505")
      (value "(OPT)220uF")
      (footprint "SMD_1210_CAPC3225X279N")
      (description "CL32A227MQVNNNE 220UF 6.3V 20% X5R 1210")
      (fields (field (name "PUBLISHER") "Altium Limited"))
      (libsource (lib "Miscellaneous Devices") (part "Cap Semi"))
    )
    (comp (ref "C506")
      (value "(OPT)220uF")
      (footprint "SMD_1210_CAPC3225X279N")
      (description "CL32A227MQVNNNE 220UF 6.3V 20% X5R 1210")
      (fields (field (name "PUBLISHER") "Altium Limited"))
      (libsource (lib "Miscellaneous Devices") (part "Cap Semi"))
    )
    (comp (ref "C507")
      (value "(OPT)220uF")
      (footprint "SMD_1210_CAPC3225X279N")
      (description "CL32A227MQVNNNE 220UF 6.3V 20% X5R 1210")
      (fields (field (name "PUBLISHER") "Altium Limited"))
      (libsource (lib "Miscellaneous Devices") (part "Cap Semi"))
    )
    (comp (ref "C508")
      (value "(OPT)220uF")
      (footprint "SMD_1210_CAPC3225X279N")
      (description "CL32A227MQVNNNE 220UF 6.3V 20% X5R 1210")
      (fields (field (name "PUBLISHER") "Altium Limited"))
      (libsource (lib "Miscellaneous Devices") (part "Cap Semi"))
    )
    (comp (ref "C509")
      (value "(OPT)220uF")
      (footprint "SMD_1210_CAPC3225X279N")
      (description "CL32A227MQVNNNE 220UF 6.3V 20% X5R 1210")
      (fields (field (name "PUBLISHER") "Altium Limited"))
      (libsource (lib "Miscellaneous Devices") (part "Cap Semi"))
    )
    (comp (ref "C510")
      (value "(OPT)220uF")
      (footprint "SMD_1210_CAPC3225X279N")
      (description "CL32A227MQVNNNE 220UF 6.3V 20% X5R 1210")
      (fields (field (name "PUBLISHER") "Altium Limited"))
      (libsource (lib "Miscellaneous Devices") (part "Cap Semi"))
    )
    (comp (ref "C511")
      (value "(OPT)220uF")
      (footprint "SMD_1210_CAPC3225X279N")
      (description "CL32A227MQVNNNE 220UF 6.3V 20% X5R 1210")
      (fields (field (name "PUBLISHER") "Altium Limited"))
      (libsource (lib "Miscellaneous Devices") (part "Cap Semi"))
    )
    (comp (ref "C512")
      (value "(OPT)220uF")
      (footprint "SMD_1210_CAPC3225X279N")
      (description "CL32A227MQVNNNE 220UF 6.3V 20% X5R 1210")
      (fields (field (name "PUBLISHER") "Altium Limited"))
      (libsource (lib "Miscellaneous Devices") (part "Cap Semi"))
    )
    (comp (ref "C513")
      (value "(OPT)220uF")
      (footprint "SMD_1210_CAPC3225X279N")
      (description "CL32A227MQVNNNE 220UF 6.3V 20% X5R 1210")
      (fields (field (name "PUBLISHER") "Altium Limited"))
      (libsource (lib "Miscellaneous Devices") (part "Cap Semi"))
    )
    (comp (ref "C514")
      (value "(OPT)220uF")
      (footprint "SMD_1210_CAPC3225X279N")
      (description "CL32A227MQVNNNE 220UF 6.3V 20% X5R 1210")
      (fields (field (name "PUBLISHER") "Altium Limited"))
      (libsource (lib "Miscellaneous Devices") (part "Cap Semi"))
    )
    (comp (ref "C515")
      (value "(OPT)220uF")
      (footprint "SMD_1210_CAPC3225X279N")
      (description "CL32A227MQVNNNE 220UF 6.3V 20% X5R 1210")
      (fields (field (name "PUBLISHER") "Altium Limited"))
      (libsource (lib "Miscellaneous Devices") (part "Cap Semi"))
    )
    (comp (ref "C516")
      (value "(OPT)220uF")
      (footprint "SMD_1210_CAPC3225X279N")
      (description "CL32A227MQVNNNE 220UF 6.3V 20% X5R 1210")
      (fields (field (name "PUBLISHER") "Altium Limited"))
      (libsource (lib "Miscellaneous Devices") (part "Cap Semi"))
    )
    (comp (ref "C517")
      (value "(OPT)220uF")
      (footprint "SMD_1210_CAPC3225X279N")
      (description "CL32A227MQVNNNE 220UF 6.3V 20% X5R 1210")
      (fields (field (name "PUBLISHER") "Altium Limited"))
      (libsource (lib "Miscellaneous Devices") (part "Cap Semi"))
    )
    (comp (ref "C518")
      (value "(OPT)220uF")
      (footprint "SMD_1210_CAPC3225X279N")
      (description "CL32A227MQVNNNE 220UF 6.3V 20% X5R 1210")
      (fields (field (name "PUBLISHER") "Altium Limited"))
      (libsource (lib "Miscellaneous Devices") (part "Cap Semi"))
    )
    (comp (ref "C519")
      (value "(OPT)220uF")
      (footprint "SMD_1210_CAPC3225X279N")
      (description "CL32A227MQVNNNE 220UF 6.3V 20% X5R 1210")
      (fields (field (name "PUBLISHER") "Altium Limited"))
      (libsource (lib "Miscellaneous Devices") (part "Cap Semi"))
    )
    (comp (ref "C520")
      (value "(OPT)220uF")
      (footprint "SMD_1210_CAPC3225X279N")
      (description "CL32A227MQVNNNE 220UF 6.3V 20% X5R 1210")
      (fields (field (name "PUBLISHER") "Altium Limited"))
      (libsource (lib "Miscellaneous Devices") (part "Cap Semi"))
    )
    (comp (ref "C521")
      (value "(OPT)220uF")
      (footprint "SMD_1210_CAPC3225X279N")
      (description "CL32A227MQVNNNE 220UF 6.3V 20% X5R 1210")
      (fields (field (name "PUBLISHER") "Altium Limited"))
      (libsource (lib "Miscellaneous Devices") (part "Cap Semi"))
    )
    (comp (ref "C522")
      (value "(OPT)220uF")
      (footprint "SMD_1210_CAPC3225X279N")
      (description "CL32A227MQVNNNE 220UF 6.3V 20% X5R 1210")
      (fields (field (name "PUBLISHER") "Altium Limited"))
      (libsource (lib "Miscellaneous Devices") (part "Cap Semi"))
    )
    (comp (ref "C523")
      (value "(OPT)220uF")
      (footprint "SMD_1210_CAPC3225X279N")
      (description "CL32A227MQVNNNE 220UF 6.3V 20% X5R 1210")
      (fields (field (name "PUBLISHER") "Altium Limited"))
      (libsource (lib "Miscellaneous Devices") (part "Cap Semi"))
    )
    (comp (ref "C524")
      (value "(OPT)220uF")
      (footprint "SMD_1210_CAPC3225X279N")
      (description "CL32A227MQVNNNE 220UF 6.3V 20% X5R 1210")
      (fields (field (name "PUBLISHER") "Altium Limited"))
      (libsource (lib "Miscellaneous Devices") (part "Cap Semi"))
    )
    (comp (ref "C525")
      (value "(OPT)220uF")
      (footprint "SMD_1210_CAPC3225X279N")
      (description "CL32A227MQVNNNE 220UF 6.3V 20% X5R 1210")
      (fields (field (name "PUBLISHER") "Altium Limited"))
      (libsource (lib "Miscellaneous Devices") (part "Cap Semi"))
    )
    (comp (ref "C526")
      (value "(OPT)220uF")
      (footprint "SMD_1210_CAPC3225X279N")
      (description "CL32A227MQVNNNE 220UF 6.3V 20% X5R 1210")
      (fields (field (name "PUBLISHER") "Altium Limited"))
      (libsource (lib "Miscellaneous Devices") (part "Cap Semi"))
    )
    (comp (ref "C527")
      (value "(OPT)220uF")
      (footprint "SMD_1210_CAPC3225X279N")
      (description "CL32A227MQVNNNE 220UF 6.3V 20% X5R 1210")
      (fields (field (name "PUBLISHER") "Altium Limited"))
      (libsource (lib "Miscellaneous Devices") (part "Cap Semi"))
    )
    (comp (ref "C528")
      (value "(OPT)220uF")
      (footprint "SMD_1210_CAPC3225X279N")
      (description "CL32A227MQVNNNE 220UF 6.3V 20% X5R 1210")
      (fields (field (name "PUBLISHER") "Altium Limited"))
      (libsource (lib "Miscellaneous Devices") (part "Cap Semi"))
    )
    (comp (ref "C529")
      (value "(OPT)220uF")
      (footprint "SMD_1210_CAPC3225X279N")
      (description "CL32A227MQVNNNE 220UF 6.3V 20% X5R 1210")
      (fields (field (name "PUBLISHER") "Altium Limited"))
      (libsource (lib "Miscellaneous Devices") (part "Cap Semi"))
    )
    (comp (ref "C530")
      (value "(OPT)220uF")
      (footprint "SMD_1210_CAPC3225X279N")
      (description "CL32A227MQVNNNE 220UF 6.3V 20% X5R 1210")
      (fields (field (name "PUBLISHER") "Altium Limited"))
      (libsource (lib "Miscellaneous Devices") (part "Cap Semi"))
    )
    (comp (ref "C531")
      (value "(OPT)220uF")
      (footprint "SMD_1210_CAPC3225X279N")
      (description "CL32A227MQVNNNE 220UF 6.3V 20% X5R 1210")
      (fields (field (name "PUBLISHER") "Altium Limited"))
      (libsource (lib "Miscellaneous Devices") (part "Cap Semi"))
    )
    (comp (ref "C532")
      (value "(OPT)220uF")
      (footprint "SMD_1210_CAPC3225X279N")
      (description "CL32A227MQVNNNE 220UF 6.3V 20% X5R 1210")
      (fields (field (name "PUBLISHER") "Altium Limited"))
      (libsource (lib "Miscellaneous Devices") (part "Cap Semi"))
    )
    (comp (ref "C533")
      (value "(OPT)220uF")
      (footprint "SMD_1210_CAPC3225X279N")
      (description "CL32A227MQVNNNE 220UF 6.3V 20% X5R 1210")
      (fields (field (name "PUBLISHER") "Altium Limited"))
      (libsource (lib "Miscellaneous Devices") (part "Cap Semi"))
    )
    (comp (ref "C534")
      (value "(OPT)220uF")
      (footprint "SMD_1210_CAPC3225X279N")
      (description "CL32A227MQVNNNE 220UF 6.3V 20% X5R 1210")
      (fields (field (name "PUBLISHER") "Altium Limited"))
      (libsource (lib "Miscellaneous Devices") (part "Cap Semi"))
    )
    (comp (ref "C535")
      (value "(OPT)220uF")
      (footprint "SMD_1210_CAPC3225X279N")
      (description "CL32A227MQVNNNE 220UF 6.3V 20% X5R 1210")
      (fields (field (name "PUBLISHER") "Altium Limited"))
      (libsource (lib "Miscellaneous Devices") (part "Cap Semi"))
    )
    (comp (ref "C536")
      (value "(OPT)220uF")
      (footprint "SMD_1210_CAPC3225X279N")
      (description "CL32A227MQVNNNE 220UF 6.3V 20% X5R 1210")
      (fields (field (name "PUBLISHER") "Altium Limited"))
      (libsource (lib "Miscellaneous Devices") (part "Cap Semi"))
    )
    (comp (ref "D1")
      (value "BAT54C")
      (footprint "SMD_SOT23_SOT95P240X120-3N")
      (libsource (lib "EPIQ_DND_CIS_Library") (part "D_DUAL_A1A2CC3"))
    )
    (comp (ref "D2")
      (value "BAT54C")
      (footprint "SMD_SOT23_SOT95P240X120-3N")
      (libsource (lib "EPIQ_DND_CIS_Library") (part "D_DUAL_A1A2CC3"))
    )
    (comp (ref "D3")
      (value "(OPT) BAV56")
      (footprint "SMD_SOT23_SOT95P240X120-3N")
      (libsource (lib "EPIQ_DND_CIS_Library") (part "D_DUAL_A1A2CC3"))
    )
    (comp (ref "D4")
      (value "Red SML210VT ROHM")
      (footprint "SMD_0805_LED2012X100N")
      (libsource (lib "EPIQ_DND_CIS_Library") (part "LED_2"))
    )
    (comp (ref "D5")
      (value "Green 	SML210MT ROHM")
      (footprint "SMD_0805_LED2012X100N")
      (libsource (lib "EPIQ_DND_CIS_Library") (part "LED_2"))
    )
    (comp (ref "D6")
      (value "Yellow SML210YT ROHM")
      (footprint "SMD_0805_LED2012X100N")
      (libsource (lib "EPIQ_DND_CIS_Library") (part "LED_2"))
    )
    (comp (ref "D7")
      (value "Orange 	SML210DT ROHM")
      (footprint "SMD_0805_LED2012X100N")
      (libsource (lib "EPIQ_DND_CIS_Library") (part "LED_2"))
    )
    (comp (ref "J1")
      (value "(OPT) CON PROGRAM")
      (footprint "SIP5 PGM TOP")
      (description "Connector")
      (libsource (lib "Miscellaneous Devices") (part "CON5"))
    )
    (comp (ref "J2")
      (value "CON MOLEX HDD")
      (footprint "MOLEX_PWR_4P - AVALON")
      (libsource (lib "EPIQ_DND_CIS_Library") (part "CON_4PINS"))
    )
    (comp (ref "J3")
      (value "CU04SCM15B0-R0")
      (footprint "SMD_CON-CVILUX-CU04-SCM15B0")
      (libsource (lib "EPIQ_DND_CIS_Library") (part "CON_USB_MINI_1"))
    )
    (comp (ref "J4")
      (value "CON SIP2")
      (footprint "PTH_HDRV02W64P254_1X02")
      (description "Connector")
      (libsource (lib "Miscellaneous Devices") (part "CON2"))
    )
    (comp (ref "J5")
      (value "CON CAN")
      (footprint "PTH_CON_JST-B2PS-VH")
      (description "Connector")
      (libsource (lib "*") (part "CON2"))
    )
    (comp (ref "J6")
      (value "CON FAN")
      (footprint "PTH_CON_PANCON-MPSS100-04D")
      (libsource (lib "EPIQ_DND_CIS_Library") (part "CON_4PINS"))
    )
    (comp (ref "L1")
      (value "SLC1480-201MLD")
      (footprint "SMD_INDM12501250X800A - Coilcraft SLC1480")
      (libsource (lib "EPIQ_DND_CIS_Library") (part "L"))
    )
    (comp (ref "L2")
      (value "SLC1480-201MLD")
      (footprint "SMD_INDM12501250X800A - Coilcraft SLC1480")
      (libsource (lib "EPIQ_DND_CIS_Library") (part "L"))
    )
    (comp (ref "Q1")
      (value "AP1RA03GMT-3")
      (footprint "SMD_SON127P615X520X100-8N")
      (libsource (lib "EPIQ_DND_CIS_Library") (part "MOS_N_D1_S1S2S3G4D5D6D7D8"))
    )
    (comp (ref "Q2")
      (value "AP1RA03GMT-3")
      (footprint "SMD_SON127P615X520X100-8N")
      (libsource (lib "EPIQ_DND_CIS_Library") (part "MOS_N_D1_S1S2S3G4D5D6D7D8"))
    )
    (comp (ref "Q3")
      (value "AP1RA03GMT-3")
      (footprint "SMD_SON127P615X520X100-8N")
      (libsource (lib "EPIQ_DND_CIS_Library") (part "MOS_N_D1_S1S2S3G4D5D6D7D8"))
    )
    (comp (ref "Q4")
      (value "AP1RA03GMT-3")
      (footprint "SMD_SON127P615X520X100-8N")
      (libsource (lib "EPIQ_DND_CIS_Library") (part "MOS_N_D1_S1S2S3G4D5D6D7D8"))
    )
    (comp (ref "Q5")
      (value "AP1RA03GMT-3")
      (footprint "SMD_SON127P615X520X100-8N")
      (libsource (lib "EPIQ_DND_CIS_Library") (part "MOS_N_D1_S1S2S3G4D5D6D7D8"))
    )
    (comp (ref "Q6")
      (value "AP1RA03GMT-3")
      (footprint "SMD_SON127P615X520X100-8N")
      (libsource (lib "EPIQ_DND_CIS_Library") (part "MOS_N_D1_S1S2S3G4D5D6D7D8"))
    )
    (comp (ref "Q7")
      (value "BSS138")
      (footprint "SMD_SOT23_SOT95P240X120-3N")
      (libsource (lib "EPIQ_DND_CIS_Library") (part "BJT_NPN_B1E2C3"))
    )
    (comp (ref "Q8")
      (value "(OPT)BSS138")
      (footprint "SMD_SOT23_SOT95P240X120-3N")
      (libsource (lib "EPIQ_DND_CIS_Library") (part "BJT_NPN_B1E2C3"))
    )
    (comp (ref "R1")
      (value "1k")
      (footprint "SMD_0603_RESC1608X55N")
      (description "Resistor")
      (fields (field (name "PUBLISHER") "Altium Limited"))
      (libsource (lib "Miscellaneous Devices") (part "Res3"))
    )
    (comp (ref "R2")
      (value "0")
      (footprint "SMD_0603_RESC1608X55N")
      (description "Resistor")
      (fields (field (name "PUBLISHER") "Altium Limited"))
      (libsource (lib "Miscellaneous Devices") (part "Res3"))
    )
    (comp (ref "R3")
      (value "2k")
      (footprint "SMD_0603_RESC1608X55N")
      (description "Resistor")
      (fields (field (name "PUBLISHER") "Altium Limited"))
      (libsource (lib "Miscellaneous Devices") (part "Res3"))
    )
    (comp (ref "R4")
      (value "2k")
      (footprint "SMD_0603_RESC1608X55N")
      (description "Resistor")
      (fields (field (name "PUBLISHER") "Altium Limited"))
      (libsource (lib "Miscellaneous Devices") (part "Res3"))
    )
    (comp (ref "R5")
      (value "2k")
      (footprint "SMD_0603_RESC1608X55N")
      (description "Resistor")
      (fields (field (name "PUBLISHER") "Altium Limited"))
      (libsource (lib "Miscellaneous Devices") (part "Res3"))
    )
    (comp (ref "R6")
      (value "2k")
      (footprint "SMD_0603_RESC1608X55N")
      (description "Resistor")
      (fields (field (name "PUBLISHER") "Altium Limited"))
      (libsource (lib "Miscellaneous Devices") (part "Res3"))
    )
    (comp (ref "R7")
      (value "(OPT)1k")
      (footprint "SMD_0603_RESC1608X55N")
      (description "Resistor")
      (fields (field (name "PUBLISHER") "Altium Limited"))
      (libsource (lib "Miscellaneous Devices") (part "Res3"))
    )
    (comp (ref "R8")
      (value "(OPT)0")
      (footprint "SMD_0603_RESC1608X55N")
      (description "Resistor")
      (fields (field (name "PUBLISHER") "Altium Limited"))
      (libsource (lib "Miscellaneous Devices") (part "Res3"))
    )
    (comp (ref "R9")
      (value "10k")
      (footprint "SMD_0603_RESC1608X55N")
      (description "Resistor")
      (fields (field (name "PUBLISHER") "Altium Limited"))
      (libsource (lib "Miscellaneous Devices") (part "Res3"))
    )
    (comp (ref "R10")
      (value "(OPT)2k")
      (footprint "SMD_0603_RESC1608X55N")
      (description "Resistor")
      (fields (field (name "PUBLISHER") "Altium Limited"))
      (libsource (lib "Miscellaneous Devices") (part "Res3"))
    )
    (comp (ref "R11")
      (value "(OPT)2k")
      (footprint "SMD_0603_RESC1608X55N")
      (description "Resistor")
      (fields (field (name "PUBLISHER") "Altium Limited"))
      (libsource (lib "Miscellaneous Devices") (part "Res3"))
    )
    (comp (ref "R12")
      (value "0")
      (footprint "SMD_0603_RESC1608X55N")
      (description "Resistor")
      (fields (field (name "PUBLISHER") "Altium Limited"))
      (libsource (lib "Miscellaneous Devices") (part "Res3"))
    )
    (comp (ref "R13")
      (value "(OPT)0")
      (footprint "SMD_0603_RESC1608X55N")
      (description "Resistor")
      (fields (field (name "PUBLISHER") "Altium Limited"))
      (libsource (lib "Miscellaneous Devices") (part "Res3"))
    )
    (comp (ref "R14")
      (value "10k")
      (footprint "SMD_0603_RESC1608X55N")
      (description "Resistor")
      (fields (field (name "PUBLISHER") "Altium Limited"))
      (libsource (lib "Miscellaneous Devices") (part "Res3"))
    )
    (comp (ref "R15")
      (value "10k")
      (footprint "SMD_0603_RESC1608X55N")
      (description "Resistor")
      (fields (field (name "PUBLISHER") "Altium Limited"))
      (libsource (lib "Miscellaneous Devices") (part "Res3"))
    )
    (comp (ref "R16")
      (value "(OPT)0")
      (footprint "SMD_0603_RESC1608X55N")
      (description "Resistor")
      (fields (field (name "PUBLISHER") "Altium Limited"))
      (libsource (lib "Miscellaneous Devices") (part "Res3"))
    )
    (comp (ref "R17")
      (value "1k")
      (footprint "SMD_0603_RESC1608X55N")
      (description "Resistor")
      (fields (field (name "PUBLISHER") "Altium Limited"))
      (libsource (lib "Miscellaneous Devices") (part "Res3"))
    )
    (comp (ref "R18")
      (value "(OPT)0")
      (footprint "SMD_0603_RESC1608X55N")
      (description "Resistor")
      (fields (field (name "PUBLISHER") "Altium Limited"))
      (libsource (lib "Miscellaneous Devices") (part "Res3"))
    )
    (comp (ref "R24")
      (value "1k")
      (footprint "SMD_0603_RESC1608X55N")
      (description "Resistor")
      (fields (field (name "PUBLISHER") "Altium Limited"))
      (libsource (lib "Miscellaneous Devices") (part "Res3"))
    )
    (comp (ref "R25")
      (value "1k")
      (footprint "SMD_0603_RESC1608X55N")
      (description "Resistor")
      (fields (field (name "PUBLISHER") "Altium Limited"))
      (libsource (lib "Miscellaneous Devices") (part "Res3"))
    )
    (comp (ref "R26")
      (value "1k")
      (footprint "SMD_0603_RESC1608X55N")
      (description "Resistor")
      (fields (field (name "PUBLISHER") "Altium Limited"))
      (libsource (lib "Miscellaneous Devices") (part "Res3"))
    )
    (comp (ref "R27")
      (value "1k")
      (footprint "SMD_0603_RESC1608X55N")
      (description "Resistor")
      (fields (field (name "PUBLISHER") "Altium Limited"))
      (libsource (lib "Miscellaneous Devices") (part "Res3"))
    )
    (comp (ref "R28")
      (value "1k")
      (footprint "SMD_0603_RESC1608X55N")
      (description "Resistor")
      (fields (field (name "PUBLISHER") "Altium Limited"))
      (libsource (lib "Miscellaneous Devices") (part "Res3"))
    )
    (comp (ref "R29")
      (value "1k")
      (footprint "SMD_0603_RESC1608X55N")
      (description "Resistor")
      (fields (field (name "PUBLISHER") "Altium Limited"))
      (libsource (lib "Miscellaneous Devices") (part "Res3"))
    )
    (comp (ref "R30")
      (value "1k")
      (footprint "SMD_0603_RESC1608X55N")
      (description "Resistor")
      (fields (field (name "PUBLISHER") "Altium Limited"))
      (libsource (lib "Miscellaneous Devices") (part "Res3"))
    )
    (comp (ref "R31")
      (value "1k")
      (footprint "SMD_0603_RESC1608X55N")
      (description "Resistor")
      (fields (field (name "PUBLISHER") "Altium Limited"))
      (libsource (lib "Miscellaneous Devices") (part "Res3"))
    )
    (comp (ref "R34")
      (value "27")
      (footprint "SMD_0603_RESC1608X55N")
      (description "Resistor")
      (fields (field (name "PUBLISHER") "Altium Limited"))
      (libsource (lib "Miscellaneous Devices") (part "Res3"))
    )
    (comp (ref "R35")
      (value "27")
      (footprint "SMD_0603_RESC1608X55N")
      (description "Resistor")
      (fields (field (name "PUBLISHER") "Altium Limited"))
      (libsource (lib "Miscellaneous Devices") (part "Res3"))
    )
    (comp (ref "R36")
      (value "768")
      (footprint "SMD_0603_RESC1608X55N")
      (description "Resistor")
      (fields (field (name "PUBLISHER") "Altium Limited"))
      (libsource (lib "Miscellaneous Devices") (part "Res3"))
    )
    (comp (ref "R37")
      (value "2.4k")
      (footprint "SMD_0603_RESC1608X55N")
      (description "Resistor")
      (fields (field (name "PUBLISHER") "Altium Limited"))
      (libsource (lib "Miscellaneous Devices") (part "Res3"))
    )
    (comp (ref "R38")
      (value "2.4k")
      (footprint "SMD_0603_RESC1608X55N")
      (description "Resistor")
      (fields (field (name "PUBLISHER") "Altium Limited"))
      (libsource (lib "Miscellaneous Devices") (part "Res3"))
    )
    (comp (ref "R40")
      (value "10k")
      (footprint "SMD_0603_RESC1608X55N")
      (description "Resistor")
      (fields (field (name "PUBLISHER") "Altium Limited"))
      (libsource (lib "Miscellaneous Devices") (part "Res3"))
    )
    (comp (ref "R41")
      (value "120")
      (footprint "SMD_0603_RESC1608X55N")
      (description "Resistor")
      (fields (field (name "PUBLISHER") "Altium Limited"))
      (libsource (lib "Miscellaneous Devices") (part "Res3"))
    )
    (comp (ref "R42")
      (value "(OPT)0")
      (footprint "SMD_0603_RESC1608X55N")
      (description "Resistor")
      (fields (field (name "PUBLISHER") "Altium Limited"))
      (libsource (lib "Miscellaneous Devices") (part "Res3"))
    )
    (comp (ref "R43")
      (value "10k")
      (footprint "SMD_0603_RESC1608X55N")
      (description "Resistor")
      (fields (field (name "PUBLISHER") "Altium Limited"))
      (libsource (lib "Miscellaneous Devices") (part "Res3"))
    )
    (comp (ref "R44")
      (value "10k")
      (footprint "SMD_0603_RESC1608X55N")
      (description "Resistor")
      (fields (field (name "PUBLISHER") "Altium Limited"))
      (libsource (lib "Miscellaneous Devices") (part "Res3"))
    )
    (comp (ref "R45")
      (value "2.4k")
      (footprint "SMD_0603_RESC1608X55N")
      (description "Resistor")
      (fields (field (name "PUBLISHER") "Altium Limited"))
      (libsource (lib "Miscellaneous Devices") (part "Res3"))
    )
    (comp (ref "R46")
      (value "0")
      (footprint "SMD_1206_RESC3216X180N")
      (description "Resistor")
      (fields (field (name "PUBLISHER") "Altium Limited"))
      (libsource (lib "Miscellaneous Devices") (part "Res3"))
    )
    (comp (ref "R47")
      (value "0")
      (footprint "SMD_1206_RESC3216X180N")
      (description "Resistor")
      (fields (field (name "PUBLISHER") "Altium Limited"))
      (libsource (lib "Miscellaneous Devices") (part "Res3"))
    )
    (comp (ref "R56")
      (value "0")
      (footprint "SMD_0603_RESC1608X55N")
      (description "Resistor")
      (fields (field (name "PUBLISHER") "Altium Limited"))
      (libsource (lib "Miscellaneous Devices") (part "Res3"))
    )
    (comp (ref "R57")
      (value "10k")
      (footprint "SMD_0603_RESC1608X55N")
      (description "Resistor")
      (fields (field (name "PUBLISHER") "Altium Limited"))
      (libsource (lib "Miscellaneous Devices") (part "Res3"))
    )
    (comp (ref "R59")
      (value "10k")
      (footprint "SMD_0603_RESC1608X55N")
      (description "Resistor")
      (fields (field (name "PUBLISHER") "Altium Limited"))
      (libsource (lib "Miscellaneous Devices") (part "Res3"))
    )
    (comp (ref "R60")
      (value "0")
      (footprint "SMD_1206_RESC3216X180N")
      (description "Resistor")
      (fields (field (name "PUBLISHER") "Altium Limited"))
      (libsource (lib "Miscellaneous Devices") (part "Res3"))
    )
    (comp (ref "R61")
      (value "2.4k")
      (footprint "SMD_0603_RESC1608X55N")
      (description "Resistor")
      (fields (field (name "PUBLISHER") "Altium Limited"))
      (libsource (lib "Miscellaneous Devices") (part "Res3"))
    )
    (comp (ref "R62")
      (value "(OPT)0")
      (footprint "SMD_0603_RESC1608X55N")
      (description "Resistor")
      (fields (field (name "PUBLISHER") "Altium Limited"))
      (libsource (lib "Miscellaneous Devices") (part "Res3"))
    )
    (comp (ref "R63")
      (value "0")
      (footprint "SMD_0603_RESC1608X55N")
      (description "Resistor")
      (fields (field (name "PUBLISHER") "Altium Limited"))
      (libsource (lib "Miscellaneous Devices") (part "Res3"))
    )
    (comp (ref "R64")
      (value "0")
      (footprint "SMD_0603_RESC1608X55N")
      (description "Resistor")
      (fields (field (name "PUBLISHER") "Altium Limited"))
      (libsource (lib "Miscellaneous Devices") (part "Res3"))
    )
    (comp (ref "R79")
      (value "1k")
      (footprint "SMD_0603_RESC1608X55N")
      (description "Resistor")
      (fields (field (name "PUBLISHER") "Altium Limited"))
      (libsource (lib "Miscellaneous Devices") (part "Res3"))
    )
    (comp (ref "R80")
      (value "1k")
      (footprint "SMD_0603_RESC1608X55N")
      (description "Resistor")
      (fields (field (name "PUBLISHER") "Altium Limited"))
      (libsource (lib "Miscellaneous Devices") (part "Res3"))
    )
    (comp (ref "R81")
      (value "1k")
      (footprint "SMD_0603_RESC1608X55N")
      (description "Resistor")
      (fields (field (name "PUBLISHER") "Altium Limited"))
      (libsource (lib "Miscellaneous Devices") (part "Res3"))
    )
    (comp (ref "R82")
      (value "1k")
      (footprint "SMD_0603_RESC1608X55N")
      (description "Resistor")
      (fields (field (name "PUBLISHER") "Altium Limited"))
      (libsource (lib "Miscellaneous Devices") (part "Res3"))
    )
    (comp (ref "R83")
      (value "1k")
      (footprint "SMD_0603_RESC1608X55N")
      (description "Resistor")
      (fields (field (name "PUBLISHER") "Altium Limited"))
      (libsource (lib "Miscellaneous Devices") (part "Res3"))
    )
    (comp (ref "R84")
      (value "1k")
      (footprint "SMD_0603_RESC1608X55N")
      (description "Resistor")
      (fields (field (name "PUBLISHER") "Altium Limited"))
      (libsource (lib "Miscellaneous Devices") (part "Res3"))
    )
    (comp (ref "R85")
      (value "1k")
      (footprint "SMD_0603_RESC1608X55N")
      (description "Resistor")
      (fields (field (name "PUBLISHER") "Altium Limited"))
      (libsource (lib "Miscellaneous Devices") (part "Res3"))
    )
    (comp (ref "R86")
      (value "1k")
      (footprint "SMD_0603_RESC1608X55N")
      (description "Resistor")
      (fields (field (name "PUBLISHER") "Altium Limited"))
      (libsource (lib "Miscellaneous Devices") (part "Res3"))
    )
    (comp (ref "R103")
      (value "1k")
      (footprint "SMD_0603_RESC1608X55N")
      (description "Resistor")
      (fields (field (name "PUBLISHER") "Altium Limited"))
      (libsource (lib "Miscellaneous Devices") (part "Res3"))
    )
    (comp (ref "R104")
      (value "1k")
      (footprint "SMD_0603_RESC1608X55N")
      (description "Resistor")
      (fields (field (name "PUBLISHER") "Altium Limited"))
      (libsource (lib "Miscellaneous Devices") (part "Res3"))
    )
    (comp (ref "R105")
      (value "1k")
      (footprint "SMD_0603_RESC1608X55N")
      (description "Resistor")
      (fields (field (name "PUBLISHER") "Altium Limited"))
      (libsource (lib "Miscellaneous Devices") (part "Res3"))
    )
    (comp (ref "R106")
      (value "1k")
      (footprint "SMD_0603_RESC1608X55N")
      (description "Resistor")
      (fields (field (name "PUBLISHER") "Altium Limited"))
      (libsource (lib "Miscellaneous Devices") (part "Res3"))
    )
    (comp (ref "R107")
      (value "1k")
      (footprint "SMD_0603_RESC1608X55N")
      (description "Resistor")
      (fields (field (name "PUBLISHER") "Altium Limited"))
      (libsource (lib "Miscellaneous Devices") (part "Res3"))
    )
    (comp (ref "R108")
      (value "1k")
      (footprint "SMD_0603_RESC1608X55N")
      (description "Resistor")
      (fields (field (name "PUBLISHER") "Altium Limited"))
      (libsource (lib "Miscellaneous Devices") (part "Res3"))
    )
    (comp (ref "R109")
      (value "1k")
      (footprint "SMD_0603_RESC1608X55N")
      (description "Resistor")
      (fields (field (name "PUBLISHER") "Altium Limited"))
      (libsource (lib "Miscellaneous Devices") (part "Res3"))
    )
    (comp (ref "R110")
      (value "1k")
      (footprint "SMD_0603_RESC1608X55N")
      (description "Resistor")
      (fields (field (name "PUBLISHER") "Altium Limited"))
      (libsource (lib "Miscellaneous Devices") (part "Res3"))
    )
    (comp (ref "R127")
      (value "1k")
      (footprint "SMD_0603_RESC1608X55N")
      (description "Resistor")
      (fields (field (name "PUBLISHER") "Altium Limited"))
      (libsource (lib "Miscellaneous Devices") (part "Res3"))
    )
    (comp (ref "R128")
      (value "1k")
      (footprint "SMD_0603_RESC1608X55N")
      (description "Resistor")
      (fields (field (name "PUBLISHER") "Altium Limited"))
      (libsource (lib "Miscellaneous Devices") (part "Res3"))
    )
    (comp (ref "R129")
      (value "1k")
      (footprint "SMD_0603_RESC1608X55N")
      (description "Resistor")
      (fields (field (name "PUBLISHER") "Altium Limited"))
      (libsource (lib "Miscellaneous Devices") (part "Res3"))
    )
    (comp (ref "R130")
      (value "1k")
      (footprint "SMD_0603_RESC1608X55N")
      (description "Resistor")
      (fields (field (name "PUBLISHER") "Altium Limited"))
      (libsource (lib "Miscellaneous Devices") (part "Res3"))
    )
    (comp (ref "R131")
      (value "1k")
      (footprint "SMD_0603_RESC1608X55N")
      (description "Resistor")
      (fields (field (name "PUBLISHER") "Altium Limited"))
      (libsource (lib "Miscellaneous Devices") (part "Res3"))
    )
    (comp (ref "R132")
      (value "1k")
      (footprint "SMD_0603_RESC1608X55N")
      (description "Resistor")
      (fields (field (name "PUBLISHER") "Altium Limited"))
      (libsource (lib "Miscellaneous Devices") (part "Res3"))
    )
    (comp (ref "R133")
      (value "1k")
      (footprint "SMD_0603_RESC1608X55N")
      (description "Resistor")
      (fields (field (name "PUBLISHER") "Altium Limited"))
      (libsource (lib "Miscellaneous Devices") (part "Res3"))
    )
    (comp (ref "R134")
      (value "1k")
      (footprint "SMD_0603_RESC1608X55N")
      (description "Resistor")
      (fields (field (name "PUBLISHER") "Altium Limited"))
      (libsource (lib "Miscellaneous Devices") (part "Res3"))
    )
    (comp (ref "U1")
      (value "dsPIC33EP256MU806")
      (footprint "SMD_QFP50P1200X1200X120-64N")
      (libsource (lib "MCU") (part "dsPIC33EP256MU806"))
    )
    (comp (ref "U2")
      (value "BITFURY256")
      (footprint "SMD_QFN50P700X700X90-49N")
      (description "BitFury SHA256")
      (libsource (lib "DevicesA10") (part "BITFURY256"))
    )
    (comp (ref "U3")
      (value "BITFURY256")
      (footprint "SMD_QFN50P700X700X90-49N")
      (description "BitFury SHA256")
      (libsource (lib "DevicesA10") (part "BITFURY256"))
    )
    (comp (ref "U4")
      (value "BITFURY256")
      (footprint "SMD_QFN50P700X700X90-49N")
      (description "BitFury SHA256")
      (libsource (lib "DevicesA10") (part "BITFURY256"))
    )
    (comp (ref "U5")
      (value "BITFURY256")
      (footprint "SMD_QFN50P700X700X90-49N")
      (description "BitFury SHA256")
      (libsource (lib "DevicesA10") (part "BITFURY256"))
    )
    (comp (ref "U6")
      (value "(OPT)BU33TD3WG-TR")
      (footprint "SMD_SOT26_SOT95P285X140-5N - DLV")
      (libsource (lib "Miscellaneous Devices") (part "VOLTREG LDO"))
    )
    (comp (ref "U7")
      (value "BITFURY256")
      (footprint "SMD_QFN50P700X700X90-49N")
      (description "BitFury SHA256")
      (libsource (lib "DevicesA10") (part "BITFURY256"))
    )
    (comp (ref "U8")
      (value "BITFURY256")
      (footprint "SMD_QFN50P700X700X90-49N")
      (description "BitFury SHA256")
      (libsource (lib "DevicesA10") (part "BITFURY256"))
    )
    (comp (ref "U9")
      (value "BITFURY256")
      (footprint "SMD_QFN50P700X700X90-49N")
      (description "BitFury SHA256")
      (libsource (lib "DevicesA10") (part "BITFURY256"))
    )
    (comp (ref "U10")
      (value "BITFURY256")
      (footprint "SMD_QFN50P700X700X90-49N")
      (description "BitFury SHA256")
      (libsource (lib "DevicesA10") (part "BITFURY256"))
    )
    (comp (ref "U11")
      (value "BITFURY256")
      (footprint "SMD_QFN50P700X700X90-49N")
      (description "BitFury SHA256")
      (libsource (lib "DevicesA10") (part "BITFURY256"))
    )
    (comp (ref "U12")
      (value "BITFURY256")
      (footprint "SMD_QFN50P700X700X90-49N")
      (description "BitFury SHA256")
      (libsource (lib "DevicesA10") (part "BITFURY256"))
    )
    (comp (ref "U13")
      (value "BITFURY256")
      (footprint "SMD_QFN50P700X700X90-49N")
      (description "BitFury SHA256")
      (libsource (lib "DevicesA10") (part "BITFURY256"))
    )
    (comp (ref "U14")
      (value "BITFURY256")
      (footprint "SMD_QFN50P700X700X90-49N")
      (description "BitFury SHA256")
      (libsource (lib "DevicesA10") (part "BITFURY256"))
    )
    (comp (ref "U15")
      (value "BITFURY256")
      (footprint "SMD_QFN50P700X700X90-49N")
      (description "BitFury SHA256")
      (libsource (lib "DevicesA10") (part "BITFURY256"))
    )
    (comp (ref "U16")
      (value "BITFURY256")
      (footprint "SMD_QFN50P700X700X90-49N")
      (description "BitFury SHA256")
      (libsource (lib "DevicesA10") (part "BITFURY256"))
    )
    (comp (ref "U17")
      (value "BITFURY256")
      (footprint "SMD_QFN50P700X700X90-49N")
      (description "BitFury SHA256")
      (libsource (lib "DevicesA10") (part "BITFURY256"))
    )
    (comp (ref "U18")
      (value "BITFURY256")
      (footprint "SMD_QFN50P700X700X90-49N")
      (description "BitFury SHA256")
      (libsource (lib "DevicesA10") (part "BITFURY256"))
    )
    (comp (ref "U19")
      (value "BD33KA5WF")
      (footprint "SMD_SOIC127P602X173-8N")
      (libsource (lib "EPIQ_DND_CIS_Library") (part "IC_LM2931AD-5.0R2G_SO-8"))
    )
    (comp (ref "U20")
      (value "L78M05CDT-TR")
      (footprint "SMD_TO229P991X239-4AN_DPAK")
      (libsource (lib "EPIQ_DND_CIS_Library") (part "IC_Vout1GND2Vin3"))
    )
    (comp (ref "U21")
      (value "MCP2551-I/SN")
      (footprint "SMD_SOIC127P602X173-8N")
      (description "CAN Driver")
      (libsource (lib "Devices") (part "MCP2551"))
    )
    (comp (ref "U22")
      (value "(OPT) LM7805")
      (footprint "SMD_SOIC127P602X173-8N")
      (libsource (lib "EPIQ_DND_CIS_Library") (part "IC_LM2931AD-5.0R2G_SO-8"))
    )
    (comp (ref "U23")
      (value "(OPT) L7805CD2T-TR")
      (footprint "SMD_TO254P1524X483-3_4N_D2PAK + DPAK")
      (libsource (lib "EPIQ_DND_CIS_Library") (part "IC_Vout1GND2Vin3"))
    )
    (comp (ref "U24")
      (value "BD18KA5WF")
      (footprint "SMD_SOIC127P602X173-8N")
      (libsource (lib "EPIQ_DND_CIS_Library") (part "IC_LM2931AD-5.0R2G_SO-8"))
    )
    (comp (ref "U25")
      (value "LTC 4449")
      (footprint "SMD_SOP65P490X110-9N - DUAL")
      (description "Mosfet 12V Dual Bootstrapped PWM Sync Buck Optimised")
      (libsource (lib "Devices") (part "DRVFET_LTC4442"))
    )
    (comp (ref "U30")
      (value "LTC 4449")
      (footprint "SMD_SOP65P490X110-9N - DUAL")
      (description "Mosfet 12V Dual Bootstrapped PWM Sync Buck Optimised")
      (libsource (lib "Devices") (part "DRVFET_LTC4442"))
    )
    (comp (ref "Y1")
      (value "Q4.000 MHz HC-49SM SMD")
      (footprint "SMD_HC49_XTAL1140X480X420N")
      (description "Crystal")
      (libsource (lib "*") (part "CRYSTAL"))
    )
  )
  (nets
    (net (code "1") (name "/0.8V") (class "Default")
      (node (ref "C100") (pin "1") (pinfunction "1_1") (pintype "passive"))
      (node (ref "C102") (pin "1") (pinfunction "1_1") (pintype "passive"))
      (node (ref "C103") (pin "1") (pinfunction "1_1") (pintype "passive"))
      (node (ref "C105") (pin "1") (pinfunction "1_1") (pintype "passive"))
      (node (ref "C106") (pin "1") (pinfunction "1_1") (pintype "passive"))
      (node (ref "C107") (pin "1") (pinfunction "1_1") (pintype "passive"))
      (node (ref "C108") (pin "1") (pinfunction "1_1") (pintype "passive"))
      (node (ref "C109") (pin "1") (pinfunction "1_1") (pintype "passive"))
      (node (ref "C11") (pin "1") (pinfunction "1_1") (pintype "passive"))
      (node (ref "C110") (pin "1") (pinfunction "1_1") (pintype "passive"))
      (node (ref "C111") (pin "1") (pinfunction "1_1") (pintype "passive"))
      (node (ref "C112") (pin "1") (pinfunction "1_1") (pintype "passive"))
      (node (ref "C113") (pin "1") (pinfunction "1_1") (pintype "passive"))
      (node (ref "C114") (pin "1") (pinfunction "1_1") (pintype "passive"))
      (node (ref "C115") (pin "1") (pinfunction "1_1") (pintype "passive"))
      (node (ref "C116") (pin "1") (pinfunction "1_1") (pintype "passive"))
      (node (ref "C117") (pin "1") (pinfunction "1_1") (pintype "passive"))
      (node (ref "C118") (pin "1") (pinfunction "1_1") (pintype "passive"))
      (node (ref "C119") (pin "1") (pinfunction "1_1") (pintype "passive"))
      (node (ref "C12") (pin "1") (pinfunction "1_1") (pintype "passive"))
      (node (ref "C120") (pin "1") (pinfunction "1_1") (pintype "passive"))
      (node (ref "C121") (pin "1") (pinfunction "1_1") (pintype "passive"))
      (node (ref "C122") (pin "1") (pinfunction "1_1") (pintype "passive"))
      (node (ref "C123") (pin "1") (pinfunction "1_1") (pintype "passive"))
      (node (ref "C124") (pin "1") (pinfunction "1_1") (pintype "passive"))
      (node (ref "C125") (pin "1") (pinfunction "1_1") (pintype "passive"))
      (node (ref "C126") (pin "1") (pinfunction "1_1") (pintype "passive"))
      (node (ref "C127") (pin "1") (pinfunction "1_1") (pintype "passive"))
      (node (ref "C128") (pin "1") (pinfunction "1_1") (pintype "passive"))
      (node (ref "C129") (pin "1") (pinfunction "1_1") (pintype "passive"))
      (node (ref "C130") (pin "1") (pinfunction "1_1") (pintype "passive"))
      (node (ref "C131") (pin "1") (pinfunction "1_1") (pintype "passive"))
      (node (ref "C132") (pin "1") (pinfunction "1_1") (pintype "passive"))
      (node (ref "C133") (pin "1") (pinfunction "1_1") (pintype "passive"))
      (node (ref "C134") (pin "1") (pinfunction "1_1") (pintype "passive"))
      (node (ref "C135") (pin "1") (pinfunction "1_1") (pintype "passive"))
      (node (ref "C136") (pin "1") (pinfunction "1_1") (pintype "passive"))
      (node (ref "C137") (pin "1") (pinfunction "1_1") (pintype "passive"))
      (node (ref "C138") (pin "1") (pinfunction "1_1") (pintype "passive"))
      (node (ref "C139") (pin "1") (pinfunction "1_1") (pintype "passive"))
      (node (ref "C140") (pin "1") (pinfunction "1_1") (pintype "passive"))
      (node (ref "C142") (pin "1") (pinfunction "1_1") (pintype "passive"))
      (node (ref "C144") (pin "1") (pinfunction "1_1") (pintype "passive"))
      (node (ref "C145") (pin "1") (pinfunction "1_1") (pintype "passive"))
      (node (ref "C146") (pin "1") (pinfunction "1_1") (pintype "passive"))
      (node (ref "C148") (pin "1") (pinfunction "1_1") (pintype "passive"))
      (node (ref "C149") (pin "1") (pinfunction "1_1") (pintype "passive"))
      (node (ref "C150") (pin "1") (pinfunction "1_1") (pintype "passive"))
      (node (ref "C152") (pin "1") (pinfunction "1_1") (pintype "passive"))
      (node (ref "C153") (pin "1") (pinfunction "1_1") (pintype "passive"))
      (node (ref "C154") (pin "1") (pinfunction "1_1") (pintype "passive"))
      (node (ref "C155") (pin "1") (pinfunction "1_1") (pintype "passive"))
      (node (ref "C156") (pin "1") (pinfunction "1_1") (pintype "passive"))
      (node (ref "C157") (pin "1") (pinfunction "1_1") (pintype "passive"))
      (node (ref "C158") (pin "1") (pinfunction "1_1") (pintype "passive"))
      (node (ref "C159") (pin "1") (pinfunction "1_1") (pintype "passive"))
      (node (ref "C160") (pin "1") (pinfunction "1_1") (pintype "passive"))
      (node (ref "C161") (pin "1") (pinfunction "1_1") (pintype "passive"))
      (node (ref "C162") (pin "1") (pinfunction "1_1") (pintype "passive"))
      (node (ref "C163") (pin "1") (pinfunction "1_1") (pintype "passive"))
      (node (ref "C164") (pin "1") (pinfunction "1_1") (pintype "passive"))
      (node (ref "C165") (pin "1") (pinfunction "1_1") (pintype "passive"))
      (node (ref "C166") (pin "1") (pinfunction "1_1") (pintype "passive"))
      (node (ref "C167") (pin "1") (pinfunction "1_1") (pintype "passive"))
      (node (ref "C169") (pin "1") (pinfunction "1_1") (pintype "passive"))
      (node (ref "C170") (pin "1") (pinfunction "1_1") (pintype "passive"))
      (node (ref "C171") (pin "1") (pinfunction "1_1") (pintype "passive"))
      (node (ref "C172") (pin "1") (pinfunction "1_1") (pintype "passive"))
      (node (ref "C173") (pin "1") (pinfunction "1_1") (pintype "passive"))
      (node (ref "C174") (pin "1") (pinfunction "1_1") (pintype "passive"))
      (node (ref "C175") (pin "1") (pinfunction "1_1") (pintype "passive"))
      (node (ref "C176") (pin "1") (pinfunction "1_1") (pintype "passive"))
      (node (ref "C177") (pin "1") (pinfunction "1_1") (pintype "passive"))
      (node (ref "C178") (pin "1") (pinfunction "1_1") (pintype "passive"))
      (node (ref "C179") (pin "1") (pinfunction "1_1") (pintype "passive"))
      (node (ref "C180") (pin "1") (pinfunction "1_1") (pintype "passive"))
      (node (ref "C181") (pin "1") (pinfunction "1_1") (pintype "passive"))
      (node (ref "C182") (pin "1") (pinfunction "1_1") (pintype "passive"))
      (node (ref "C183") (pin "1") (pinfunction "1_1") (pintype "passive"))
      (node (ref "C184") (pin "1") (pinfunction "1_1") (pintype "passive"))
      (node (ref "C185") (pin "1") (pinfunction "1_1") (pintype "passive"))
      (node (ref "C198") (pin "1") (pinfunction "1_1") (pintype "passive"))
      (node (ref "C199") (pin "1") (pinfunction "1_1") (pintype "passive"))
      (node (ref "C2") (pin "1") (pinfunction "1_1") (pintype "passive"))
      (node (ref "C200") (pin "1") (pinfunction "1_1") (pintype "passive"))
      (node (ref "C201") (pin "1") (pinfunction "1_1") (pintype "passive"))
      (node (ref "C202") (pin "1") (pinfunction "1_1") (pintype "passive"))
      (node (ref "C203") (pin "1") (pinfunction "1_1") (pintype "passive"))
      (node (ref "C204") (pin "1") (pinfunction "1_1") (pintype "passive"))
      (node (ref "C205") (pin "1") (pinfunction "1_1") (pintype "passive"))
      (node (ref "C209") (pin "2") (pinfunction "2_2") (pintype "passive"))
      (node (ref "C220") (pin "1") (pinfunction "1_1") (pintype "passive"))
      (node (ref "C221") (pin "1") (pinfunction "1_1") (pintype "passive"))
      (node (ref "C222") (pin "1") (pinfunction "1_1") (pintype "passive"))
      (node (ref "C223") (pin "1") (pinfunction "1_1") (pintype "passive"))
      (node (ref "C224") (pin "1") (pinfunction "1_1") (pintype "passive"))
      (node (ref "C225") (pin "1") (pinfunction "1_1") (pintype "passive"))
      (node (ref "C226") (pin "1") (pinfunction "1_1") (pintype "passive"))
      (node (ref "C227") (pin "1") (pinfunction "1_1") (pintype "passive"))
      (node (ref "C228") (pin "1") (pinfunction "1_1") (pintype "passive"))
      (node (ref "C238") (pin "1") (pinfunction "1_1") (pintype "passive"))
      (node (ref "C239") (pin "1") (pinfunction "1_1") (pintype "passive"))
      (node (ref "C240") (pin "1") (pinfunction "1_1") (pintype "passive"))
      (node (ref "C241") (pin "1") (pinfunction "1_1") (pintype "passive"))
      (node (ref "C242") (pin "1") (pinfunction "1_1") (pintype "passive"))
      (node (ref "C243") (pin "1") (pinfunction "1_1") (pintype "passive"))
      (node (ref "C244") (pin "1") (pinfunction "1_1") (pintype "passive"))
      (node (ref "C245") (pin "1") (pinfunction "1_1") (pintype "passive"))
      (node (ref "C246") (pin "1") (pinfunction "1_1") (pintype "passive"))
      (node (ref "C247") (pin "1") (pinfunction "1_1") (pintype "passive"))
      (node (ref "C256") (pin "1") (pinfunction "1_1") (pintype "passive"))
      (node (ref "C257") (pin "1") (pinfunction "1_1") (pintype "passive"))
      (node (ref "C258") (pin "1") (pinfunction "1_1") (pintype "passive"))
      (node (ref "C259") (pin "1") (pinfunction "1_1") (pintype "passive"))
      (node (ref "C260") (pin "1") (pinfunction "1_1") (pintype "passive"))
      (node (ref "C261") (pin "1") (pinfunction "1_1") (pintype "passive"))
      (node (ref "C262") (pin "1") (pinfunction "1_1") (pintype "passive"))
      (node (ref "C271") (pin "1") (pinfunction "1_1") (pintype "passive"))
      (node (ref "C282") (pin "1") (pinfunction "1_1") (pintype "passive"))
      (node (ref "C283") (pin "1") (pinfunction "1_1") (pintype "passive"))
      (node (ref "C284") (pin "1") (pinfunction "1_1") (pintype "passive"))
      (node (ref "C285") (pin "1") (pinfunction "1_1") (pintype "passive"))
      (node (ref "C286") (pin "1") (pinfunction "1_1") (pintype "passive"))
      (node (ref "C287") (pin "1") (pinfunction "1_1") (pintype "passive"))
      (node (ref "C288") (pin "1") (pinfunction "1_1") (pintype "passive"))
      (node (ref "C289") (pin "1") (pinfunction "1_1") (pintype "passive"))
      (node (ref "C290") (pin "1") (pinfunction "1_1") (pintype "passive"))
      (node (ref "C291") (pin "1") (pinfunction "1_1") (pintype "passive"))
      (node (ref "C292") (pin "1") (pinfunction "1_1") (pintype "passive"))
      (node (ref "C293") (pin "1") (pinfunction "1_1") (pintype "passive"))
      (node (ref "C294") (pin "1") (pinfunction "1_1") (pintype "passive"))
      (node (ref "C295") (pin "1") (pinfunction "1_1") (pintype "passive"))
      (node (ref "C296") (pin "1") (pinfunction "1_1") (pintype "passive"))
      (node (ref "C297") (pin "1") (pinfunction "1_1") (pintype "passive"))
      (node (ref "C298") (pin "1") (pinfunction "1_1") (pintype "passive"))
      (node (ref "C299") (pin "1") (pinfunction "1_1") (pintype "passive"))
      (node (ref "C3") (pin "1") (pinfunction "1_1") (pintype "passive"))
      (node (ref "C30") (pin "1") (pinfunction "1_1") (pintype "passive"))
      (node (ref "C300") (pin "1") (pinfunction "1_1") (pintype "passive"))
      (node (ref "C301") (pin "1") (pinfunction "1_1") (pintype "passive"))
      (node (ref "C302") (pin "1") (pinfunction "1_1") (pintype "passive"))
      (node (ref "C303") (pin "1") (pinfunction "1_1") (pintype "passive"))
      (node (ref "C304") (pin "1") (pinfunction "1_1") (pintype "passive"))
      (node (ref "C305") (pin "1") (pinfunction "1_1") (pintype "passive"))
      (node (ref "C306") (pin "1") (pinfunction "1_1") (pintype "passive"))
      (node (ref "C307") (pin "1") (pinfunction "1_1") (pintype "passive"))
      (node (ref "C309") (pin "1") (pinfunction "1_1") (pintype "passive"))
      (node (ref "C313") (pin "1") (pinfunction "1_1") (pintype "passive"))
      (node (ref "C314") (pin "1") (pinfunction "1_1") (pintype "passive"))
      (node (ref "C315") (pin "1") (pinfunction "1_1") (pintype "passive"))
      (node (ref "C316") (pin "1") (pinfunction "1_1") (pintype "passive"))
      (node (ref "C317") (pin "1") (pinfunction "1_1") (pintype "passive"))
      (node (ref "C318") (pin "1") (pinfunction "1_1") (pintype "passive"))
      (node (ref "C319") (pin "1") (pinfunction "1_1") (pintype "passive"))
      (node (ref "C32") (pin "1") (pinfunction "1_1") (pintype "passive"))
      (node (ref "C320") (pin "1") (pinfunction "1_1") (pintype "passive"))
      (node (ref "C321") (pin "1") (pinfunction "1_1") (pintype "passive"))
      (node (ref "C322") (pin "1") (pinfunction "1_1") (pintype "passive"))
      (node (ref "C323") (pin "1") (pinfunction "1_1") (pintype "passive"))
      (node (ref "C324") (pin "1") (pinfunction "1_1") (pintype "passive"))
      (node (ref "C326") (pin "1") (pinfunction "1_1") (pintype "passive"))
      (node (ref "C327") (pin "1") (pinfunction "1_1") (pintype "passive"))
      (node (ref "C328") (pin "1") (pinfunction "1_1") (pintype "passive"))
      (node (ref "C329") (pin "1") (pinfunction "1_1") (pintype "passive"))
      (node (ref "C33") (pin "1") (pinfunction "1_1") (pintype "passive"))
      (node (ref "C330") (pin "1") (pinfunction "1_1") (pintype "passive"))
      (node (ref "C331") (pin "1") (pinfunction "1_1") (pintype "passive"))
      (node (ref "C332") (pin "1") (pinfunction "1_1") (pintype "passive"))
      (node (ref "C333") (pin "1") (pinfunction "1_1") (pintype "passive"))
      (node (ref "C334") (pin "1") (pinfunction "1_1") (pintype "passive"))
      (node (ref "C335") (pin "1") (pinfunction "1_1") (pintype "passive"))
      (node (ref "C336") (pin "1") (pinfunction "1_1") (pintype "passive"))
      (node (ref "C337") (pin "1") (pinfunction "1_1") (pintype "passive"))
      (node (ref "C338") (pin "1") (pinfunction "1_1") (pintype "passive"))
      (node (ref "C339") (pin "1") (pinfunction "1_1") (pintype "passive"))
      (node (ref "C340") (pin "1") (pinfunction "1_1") (pintype "passive"))
      (node (ref "C341") (pin "1") (pinfunction "1_1") (pintype "passive"))
      (node (ref "C342") (pin "1") (pinfunction "1_1") (pintype "passive"))
      (node (ref "C343") (pin "1") (pinfunction "1_1") (pintype "passive"))
      (node (ref "C344") (pin "1") (pinfunction "1_1") (pintype "passive"))
      (node (ref "C345") (pin "1") (pinfunction "1_1") (pintype "passive"))
      (node (ref "C346") (pin "1") (pinfunction "1_1") (pintype "passive"))
      (node (ref "C347") (pin "1") (pinfunction "1_1") (pintype "passive"))
      (node (ref "C348") (pin "1") (pinfunction "1_1") (pintype "passive"))
      (node (ref "C349") (pin "1") (pinfunction "1_1") (pintype "passive"))
      (node (ref "C35") (pin "1") (pinfunction "1_1") (pintype "passive"))
      (node (ref "C351") (pin "1") (pinfunction "1_1") (pintype "passive"))
      (node (ref "C352") (pin "1") (pinfunction "1_1") (pintype "passive"))
      (node (ref "C353") (pin "1") (pinfunction "1_1") (pintype "passive"))
      (node (ref "C355") (pin "1") (pinfunction "1_1") (pintype "passive"))
      (node (ref "C356") (pin "1") (pinfunction "1_1") (pintype "passive"))
      (node (ref "C358") (pin "1") (pinfunction "1_1") (pintype "passive"))
      (node (ref "C359") (pin "1") (pinfunction "1_1") (pintype "passive"))
      (node (ref "C36") (pin "1") (pinfunction "1_1") (pintype "passive"))
      (node (ref "C360") (pin "1") (pinfunction "1_1") (pintype "passive"))
      (node (ref "C361") (pin "1") (pinfunction "1_1") (pintype "passive"))
      (node (ref "C362") (pin "1") (pinfunction "1_1") (pintype "passive"))
      (node (ref "C363") (pin "1") (pinfunction "1_1") (pintype "passive"))
      (node (ref "C364") (pin "1") (pinfunction "1_1") (pintype "passive"))
      (node (ref "C365") (pin "1") (pinfunction "1_1") (pintype "passive"))
      (node (ref "C366") (pin "1") (pinfunction "1_1") (pintype "passive"))
      (node (ref "C367") (pin "1") (pinfunction "1_1") (pintype "passive"))
      (node (ref "C368") (pin "1") (pinfunction "1_1") (pintype "passive"))
      (node (ref "C369") (pin "1") (pinfunction "1_1") (pintype "passive"))
      (node (ref "C37") (pin "1") (pinfunction "1_1") (pintype "passive"))
      (node (ref "C370") (pin "1") (pinfunction "1_1") (pintype "passive"))
      (node (ref "C371") (pin "1") (pinfunction "1_1") (pintype "passive"))
      (node (ref "C372") (pin "1") (pinfunction "1_1") (pintype "passive"))
      (node (ref "C373") (pin "1") (pinfunction "1_1") (pintype "passive"))
      (node (ref "C374") (pin "1") (pinfunction "1_1") (pintype "passive"))
      (node (ref "C375") (pin "1") (pinfunction "1_1") (pintype "passive"))
      (node (ref "C376") (pin "1") (pinfunction "1_1") (pintype "passive"))
      (node (ref "C377") (pin "1") (pinfunction "1_1") (pintype "passive"))
      (node (ref "C378") (pin "1") (pinfunction "1_1") (pintype "passive"))
      (node (ref "C379") (pin "1") (pinfunction "1_1") (pintype "passive"))
      (node (ref "C380") (pin "1") (pinfunction "1_1") (pintype "passive"))
      (node (ref "C381") (pin "1") (pinfunction "1_1") (pintype "passive"))
      (node (ref "C382") (pin "1") (pinfunction "1_1") (pintype "passive"))
      (node (ref "C383") (pin "1") (pinfunction "1_1") (pintype "passive"))
      (node (ref "C384") (pin "1") (pinfunction "1_1") (pintype "passive"))
      (node (ref "C385") (pin "1") (pinfunction "1_1") (pintype "passive"))
      (node (ref "C386") (pin "1") (pinfunction "1_1") (pintype "passive"))
      (node (ref "C387") (pin "1") (pinfunction "1_1") (pintype "passive"))
      (node (ref "C388") (pin "2") (pinfunction "2_2") (pintype "passive"))
      (node (ref "C389") (pin "2") (pinfunction "2_2") (pintype "passive"))
      (node (ref "C39") (pin "1") (pinfunction "1_1") (pintype "passive"))
      (node (ref "C390") (pin "2") (pinfunction "2_2") (pintype "passive"))
      (node (ref "C391") (pin "2") (pinfunction "2_2") (pintype "passive"))
      (node (ref "C392") (pin "2") (pinfunction "2_2") (pintype "passive"))
      (node (ref "C393") (pin "2") (pinfunction "2_2") (pintype "passive"))
      (node (ref "C394") (pin "2") (pinfunction "2_2") (pintype "passive"))
      (node (ref "C395") (pin "2") (pinfunction "2_2") (pintype "passive"))
      (node (ref "C396") (pin "2") (pinfunction "2_2") (pintype "passive"))
      (node (ref "C397") (pin "2") (pinfunction "2_2") (pintype "passive"))
      (node (ref "C398") (pin "2") (pinfunction "2_2") (pintype "passive"))
      (node (ref "C399") (pin "2") (pinfunction "2_2") (pintype "passive"))
      (node (ref "C4") (pin "1") (pinfunction "1_1") (pintype "passive"))
      (node (ref "C40") (pin "1") (pinfunction "1_1") (pintype "passive"))
      (node (ref "C400") (pin "2") (pinfunction "2_2") (pintype "passive"))
      (node (ref "C401") (pin "2") (pinfunction "2_2") (pintype "passive"))
      (node (ref "C402") (pin "2") (pinfunction "2_2") (pintype "passive"))
      (node (ref "C403") (pin "2") (pinfunction "2_2") (pintype "passive"))
      (node (ref "C404") (pin "2") (pinfunction "2_2") (pintype "passive"))
      (node (ref "C405") (pin "2") (pinfunction "2_2") (pintype "passive"))
      (node (ref "C406") (pin "2") (pinfunction "2_2") (pintype "passive"))
      (node (ref "C407") (pin "2") (pinfunction "2_2") (pintype "passive"))
      (node (ref "C408") (pin "2") (pinfunction "2_2") (pintype "passive"))
      (node (ref "C409") (pin "2") (pinfunction "2_2") (pintype "passive"))
      (node (ref "C41") (pin "1") (pinfunction "1_1") (pintype "passive"))
      (node (ref "C410") (pin "2") (pinfunction "2_2") (pintype "passive"))
      (node (ref "C411") (pin "2") (pinfunction "2_2") (pintype "passive"))
      (node (ref "C412") (pin "2") (pinfunction "2_2") (pintype "passive"))
      (node (ref "C413") (pin "2") (pinfunction "2_2") (pintype "passive"))
      (node (ref "C414") (pin "2") (pinfunction "2_2") (pintype "passive"))
      (node (ref "C415") (pin "2") (pinfunction "2_2") (pintype "passive"))
      (node (ref "C416") (pin "2") (pinfunction "2_2") (pintype "passive"))
      (node (ref "C417") (pin "2") (pinfunction "2_2") (pintype "passive"))
      (node (ref "C418") (pin "2") (pinfunction "2_2") (pintype "passive"))
      (node (ref "C419") (pin "2") (pinfunction "2_2") (pintype "passive"))
      (node (ref "C42") (pin "1") (pinfunction "1_1") (pintype "passive"))
      (node (ref "C420") (pin "2") (pinfunction "2_2") (pintype "passive"))
      (node (ref "C421") (pin "2") (pinfunction "2_2") (pintype "passive"))
      (node (ref "C422") (pin "2") (pinfunction "2_2") (pintype "passive"))
      (node (ref "C423") (pin "2") (pinfunction "2_2") (pintype "passive"))
      (node (ref "C424") (pin "2") (pinfunction "2_2") (pintype "passive"))
      (node (ref "C427") (pin "2") (pinfunction "2_2") (pintype "passive"))
      (node (ref "C428") (pin "2") (pinfunction "2_2") (pintype "passive"))
      (node (ref "C429") (pin "2") (pinfunction "2_2") (pintype "passive"))
      (node (ref "C43") (pin "1") (pinfunction "1_1") (pintype "passive"))
      (node (ref "C430") (pin "2") (pinfunction "2_2") (pintype "passive"))
      (node (ref "C431") (pin "2") (pinfunction "2_2") (pintype "passive"))
      (node (ref "C432") (pin "2") (pinfunction "2_2") (pintype "passive"))
      (node (ref "C433") (pin "2") (pinfunction "2_2") (pintype "passive"))
      (node (ref "C434") (pin "2") (pinfunction "2_2") (pintype "passive"))
      (node (ref "C435") (pin "2") (pinfunction "2_2") (pintype "passive"))
      (node (ref "C436") (pin "2") (pinfunction "2_2") (pintype "passive"))
      (node (ref "C439") (pin "2") (pinfunction "2_2") (pintype "passive"))
      (node (ref "C44") (pin "1") (pinfunction "1_1") (pintype "passive"))
      (node (ref "C440") (pin "2") (pinfunction "2_2") (pintype "passive"))
      (node (ref "C441") (pin "2") (pinfunction "2_2") (pintype "passive"))
      (node (ref "C442") (pin "2") (pinfunction "2_2") (pintype "passive"))
      (node (ref "C443") (pin "2") (pinfunction "2_2") (pintype "passive"))
      (node (ref "C444") (pin "2") (pinfunction "2_2") (pintype "passive"))
      (node (ref "C445") (pin "2") (pinfunction "2_2") (pintype "passive"))
      (node (ref "C446") (pin "2") (pinfunction "2_2") (pintype "passive"))
      (node (ref "C447") (pin "2") (pinfunction "2_2") (pintype "passive"))
      (node (ref "C448") (pin "2") (pinfunction "2_2") (pintype "passive"))
      (node (ref "C449") (pin "2") (pinfunction "2_2") (pintype "passive"))
      (node (ref "C450") (pin "2") (pinfunction "2_2") (pintype "passive"))
      (node (ref "C451") (pin "2") (pinfunction "2_2") (pintype "passive"))
      (node (ref "C452") (pin "2") (pinfunction "2_2") (pintype "passive"))
      (node (ref "C453") (pin "2") (pinfunction "2_2") (pintype "passive"))
      (node (ref "C454") (pin "2") (pinfunction "2_2") (pintype "passive"))
      (node (ref "C455") (pin "2") (pinfunction "2_2") (pintype "passive"))
      (node (ref "C456") (pin "2") (pinfunction "2_2") (pintype "passive"))
      (node (ref "C457") (pin "2") (pinfunction "2_2") (pintype "passive"))
      (node (ref "C458") (pin "2") (pinfunction "2_2") (pintype "passive"))
      (node (ref "C459") (pin "2") (pinfunction "2_2") (pintype "passive"))
      (node (ref "C46") (pin "1") (pinfunction "1_1") (pintype "passive"))
      (node (ref "C460") (pin "2") (pinfunction "2_2") (pintype "passive"))
      (node (ref "C461") (pin "2") (pinfunction "2_2") (pintype "passive"))
      (node (ref "C462") (pin "2") (pinfunction "2_2") (pintype "passive"))
      (node (ref "C463") (pin "2") (pinfunction "2_2") (pintype "passive"))
      (node (ref "C464") (pin "2") (pinfunction "2_2") (pintype "passive"))
      (node (ref "C465") (pin "2") (pinfunction "2_2") (pintype "passive"))
      (node (ref "C466") (pin "2") (pinfunction "2_2") (pintype "passive"))
      (node (ref "C467") (pin "2") (pinfunction "2_2") (pintype "passive"))
      (node (ref "C468") (pin "2") (pinfunction "2_2") (pintype "passive"))
      (node (ref "C469") (pin "2") (pinfunction "2_2") (pintype "passive"))
      (node (ref "C470") (pin "2") (pinfunction "2_2") (pintype "passive"))
      (node (ref "C471") (pin "2") (pinfunction "2_2") (pintype "passive"))
      (node (ref "C472") (pin "2") (pinfunction "2_2") (pintype "passive"))
      (node (ref "C475") (pin "2") (pinfunction "2_2") (pintype "passive"))
      (node (ref "C476") (pin "2") (pinfunction "2_2") (pintype "passive"))
      (node (ref "C477") (pin "2") (pinfunction "2_2") (pintype "passive"))
      (node (ref "C478") (pin "2") (pinfunction "2_2") (pintype "passive"))
      (node (ref "C479") (pin "2") (pinfunction "2_2") (pintype "passive"))
      (node (ref "C48") (pin "1") (pinfunction "1_1") (pintype "passive"))
      (node (ref "C480") (pin "2") (pinfunction "2_2") (pintype "passive"))
      (node (ref "C481") (pin "2") (pinfunction "2_2") (pintype "passive"))
      (node (ref "C482") (pin "2") (pinfunction "2_2") (pintype "passive"))
      (node (ref "C483") (pin "2") (pinfunction "2_2") (pintype "passive"))
      (node (ref "C49") (pin "1") (pinfunction "1_1") (pintype "passive"))
      (node (ref "C5") (pin "1") (pinfunction "1_1") (pintype "passive"))
      (node (ref "C50") (pin "1") (pinfunction "1_1") (pintype "passive"))
      (node (ref "C503") (pin "1") (pinfunction "1_1") (pintype "passive"))
      (node (ref "C504") (pin "1") (pinfunction "1_1") (pintype "passive"))
      (node (ref "C505") (pin "1") (pinfunction "1_1") (pintype "passive"))
      (node (ref "C506") (pin "1") (pinfunction "1_1") (pintype "passive"))
      (node (ref "C507") (pin "1") (pinfunction "1_1") (pintype "passive"))
      (node (ref "C508") (pin "1") (pinfunction "1_1") (pintype "passive"))
      (node (ref "C509") (pin "1") (pinfunction "1_1") (pintype "passive"))
      (node (ref "C51") (pin "1") (pinfunction "1_1") (pintype "passive"))
      (node (ref "C510") (pin "1") (pinfunction "1_1") (pintype "passive"))
      (node (ref "C511") (pin "1") (pinfunction "1_1") (pintype "passive"))
      (node (ref "C512") (pin "1") (pinfunction "1_1") (pintype "passive"))
      (node (ref "C513") (pin "1") (pinfunction "1_1") (pintype "passive"))
      (node (ref "C514") (pin "1") (pinfunction "1_1") (pintype "passive"))
      (node (ref "C515") (pin "1") (pinfunction "1_1") (pintype "passive"))
      (node (ref "C516") (pin "1") (pinfunction "1_1") (pintype "passive"))
      (node (ref "C517") (pin "1") (pinfunction "1_1") (pintype "passive"))
      (node (ref "C518") (pin "1") (pinfunction "1_1") (pintype "passive"))
      (node (ref "C519") (pin "1") (pinfunction "1_1") (pintype "passive"))
      (node (ref "C52") (pin "1") (pinfunction "1_1") (pintype "passive"))
      (node (ref "C520") (pin "1") (pinfunction "1_1") (pintype "passive"))
      (node (ref "C521") (pin "1") (pinfunction "1_1") (pintype "passive"))
      (node (ref "C522") (pin "1") (pinfunction "1_1") (pintype "passive"))
      (node (ref "C523") (pin "1") (pinfunction "1_1") (pintype "passive"))
      (node (ref "C524") (pin "1") (pinfunction "1_1") (pintype "passive"))
      (node (ref "C525") (pin "1") (pinfunction "1_1") (pintype "passive"))
      (node (ref "C526") (pin "1") (pinfunction "1_1") (pintype "passive"))
      (node (ref "C527") (pin "1") (pinfunction "1_1") (pintype "passive"))
      (node (ref "C528") (pin "1") (pinfunction "1_1") (pintype "passive"))
      (node (ref "C529") (pin "1") (pinfunction "1_1") (pintype "passive"))
      (node (ref "C53") (pin "1") (pinfunction "1_1") (pintype "passive"))
      (node (ref "C530") (pin "1") (pinfunction "1_1") (pintype "passive"))
      (node (ref "C531") (pin "1") (pinfunction "1_1") (pintype "passive"))
      (node (ref "C532") (pin "1") (pinfunction "1_1") (pintype "passive"))
      (node (ref "C533") (pin "1") (pinfunction "1_1") (pintype "passive"))
      (node (ref "C534") (pin "1") (pinfunction "1_1") (pintype "passive"))
      (node (ref "C535") (pin "1") (pinfunction "1_1") (pintype "passive"))
      (node (ref "C536") (pin "1") (pinfunction "1_1") (pintype "passive"))
      (node (ref "C54") (pin "1") (pinfunction "1_1") (pintype "passive"))
      (node (ref "C55") (pin "1") (pinfunction "1_1") (pintype "passive"))
      (node (ref "C56") (pin "1") (pinfunction "1_1") (pintype "passive"))
      (node (ref "C57") (pin "1") (pinfunction "1_1") (pintype "passive"))
      (node (ref "C58") (pin "1") (pinfunction "1_1") (pintype "passive"))
      (node (ref "C6") (pin "1") (pinfunction "1_1") (pintype "passive"))
      (node (ref "C60") (pin "1") (pinfunction "1_1") (pintype "passive"))
      (node (ref "C61") (pin "1") (pinfunction "1_1") (pintype "passive"))
      (node (ref "C62") (pin "1") (pinfunction "1_1") (pintype "passive"))
      (node (ref "C64") (pin "1") (pinfunction "1_1") (pintype "passive"))
      (node (ref "C66") (pin "1") (pinfunction "1_1") (pintype "passive"))
      (node (ref "C67") (pin "1") (pinfunction "1_1") (pintype "passive"))
      (node (ref "C68") (pin "1") (pinfunction "1_1") (pintype "passive"))
      (node (ref "C69") (pin "1") (pinfunction "1_1") (pintype "passive"))
      (node (ref "C7") (pin "1") (pinfunction "1_1") (pintype "passive"))
      (node (ref "C70") (pin "1") (pinfunction "1_1") (pintype "passive"))
      (node (ref "C71") (pin "1") (pinfunction "1_1") (pintype "passive"))
      (node (ref "C77") (pin "1") (pinfunction "1_1") (pintype "passive"))
      (node (ref "C78") (pin "1") (pinfunction "1_1") (pintype "passive"))
      (node (ref "C79") (pin "1") (pinfunction "1_1") (pintype "passive"))
      (node (ref "C8") (pin "1") (pinfunction "1_1") (pintype "passive"))
      (node (ref "C80") (pin "1") (pinfunction "1_1") (pintype "passive"))
      (node (ref "C81") (pin "1") (pinfunction "1_1") (pintype "passive"))
      (node (ref "C82") (pin "1") (pinfunction "1_1") (pintype "passive"))
      (node (ref "C83") (pin "1") (pinfunction "1_1") (pintype "passive"))
      (node (ref "C84") (pin "1") (pinfunction "1_1") (pintype "passive"))
      (node (ref "C87") (pin "1") (pinfunction "1_1") (pintype "passive"))
      (node (ref "C88") (pin "1") (pinfunction "1_1") (pintype "passive"))
      (node (ref "C89") (pin "1") (pinfunction "1_1") (pintype "passive"))
      (node (ref "C9") (pin "1") (pinfunction "1_1") (pintype "passive"))
      (node (ref "C90") (pin "1") (pinfunction "1_1") (pintype "passive"))
      (node (ref "C91") (pin "1") (pinfunction "1_1") (pintype "passive"))
      (node (ref "C92") (pin "1") (pinfunction "1_1") (pintype "passive"))
      (node (ref "C93") (pin "1") (pinfunction "1_1") (pintype "passive"))
      (node (ref "C94") (pin "1") (pinfunction "1_1") (pintype "passive"))
      (node (ref "C95") (pin "1") (pinfunction "1_1") (pintype "passive"))
      (node (ref "C96") (pin "1") (pinfunction "1_1") (pintype "passive"))
      (node (ref "C97") (pin "1") (pinfunction "1_1") (pintype "passive"))
      (node (ref "C98") (pin "1") (pinfunction "1_1") (pintype "passive"))
      (node (ref "L1") (pin "2") (pinfunction "2_2") (pintype "passive"))
      (node (ref "L2") (pin "2") (pinfunction "2_2") (pintype "passive"))
      (node (ref "R38") (pin "2") (pinfunction "2_2") (pintype "passive"))
      (node (ref "R43") (pin "2") (pinfunction "2_2") (pintype "passive"))
      (node (ref "U10") (pin "14") (pinfunction "VDD_14") (pintype "passive"))
      (node (ref "U10") (pin "15") (pinfunction "VDD_15") (pintype "passive"))
      (node (ref "U10") (pin "16") (pinfunction "VDD_16") (pintype "passive"))
      (node (ref "U10") (pin "17") (pinfunction "VDD_17") (pintype "passive"))
      (node (ref "U10") (pin "18") (pinfunction "VDD_18") (pintype "passive"))
      (node (ref "U10") (pin "19") (pinfunction "VDD_19") (pintype "passive"))
      (node (ref "U10") (pin "20") (pinfunction "VDD_20") (pintype "passive"))
      (node (ref "U10") (pin "21") (pinfunction "VDD_21") (pintype "passive"))
      (node (ref "U10") (pin "22") (pinfunction "VDD_22") (pintype "passive"))
      (node (ref "U10") (pin "23") (pinfunction "VDD_23") (pintype "passive"))
      (node (ref "U10") (pin "24") (pinfunction "VDD_24") (pintype "passive"))
      (node (ref "U10") (pin "25") (pinfunction "VDD_25") (pintype "passive"))
      (node (ref "U10") (pin "26") (pinfunction "VDD_26") (pintype "passive"))
      (node (ref "U10") (pin "27") (pinfunction "VDD_27") (pintype "passive"))
      (node (ref "U10") (pin "28") (pinfunction "VDD_28") (pintype "passive"))
      (node (ref "U10") (pin "29") (pinfunction "VDD_29") (pintype "passive"))
      (node (ref "U10") (pin "30") (pinfunction "VDD_30") (pintype "passive"))
      (node (ref "U10") (pin "31") (pinfunction "VDD_31") (pintype "passive"))
      (node (ref "U10") (pin "32") (pinfunction "VDD_32") (pintype "passive"))
      (node (ref "U10") (pin "33") (pinfunction "VDD_33") (pintype "passive"))
      (node (ref "U10") (pin "34") (pinfunction "VDD_34") (pintype "passive"))
      (node (ref "U10") (pin "35") (pinfunction "VDD_35") (pintype "passive"))
      (node (ref "U10") (pin "36") (pinfunction "VDD_36") (pintype "passive"))
      (node (ref "U10") (pin "37") (pinfunction "VDD_37") (pintype "passive"))
      (node (ref "U10") (pin "38") (pinfunction "VDD_38") (pintype "passive"))
      (node (ref "U10") (pin "39") (pinfunction "VDD_39") (pintype "passive"))
      (node (ref "U10") (pin "40") (pinfunction "VDD_40") (pintype "passive"))
      (node (ref "U10") (pin "41") (pinfunction "VDD_41") (pintype "passive"))
      (node (ref "U10") (pin "42") (pinfunction "VDD_42") (pintype "passive"))
      (node (ref "U10") (pin "43") (pinfunction "VDD_43") (pintype "passive"))
      (node (ref "U10") (pin "44") (pinfunction "VDD_44") (pintype "passive"))
      (node (ref "U10") (pin "45") (pinfunction "VDD_45") (pintype "passive"))
      (node (ref "U10") (pin "46") (pinfunction "VDD_46") (pintype "passive"))
      (node (ref "U10") (pin "47") (pinfunction "VDD_47") (pintype "passive"))
      (node (ref "U10") (pin "48") (pinfunction "VDD_48") (pintype "passive"))
      (node (ref "U11") (pin "14") (pinfunction "VDD_14") (pintype "passive"))
      (node (ref "U11") (pin "15") (pinfunction "VDD_15") (pintype "passive"))
      (node (ref "U11") (pin "16") (pinfunction "VDD_16") (pintype "passive"))
      (node (ref "U11") (pin "17") (pinfunction "VDD_17") (pintype "passive"))
      (node (ref "U11") (pin "18") (pinfunction "VDD_18") (pintype "passive"))
      (node (ref "U11") (pin "19") (pinfunction "VDD_19") (pintype "passive"))
      (node (ref "U11") (pin "20") (pinfunction "VDD_20") (pintype "passive"))
      (node (ref "U11") (pin "21") (pinfunction "VDD_21") (pintype "passive"))
      (node (ref "U11") (pin "22") (pinfunction "VDD_22") (pintype "passive"))
      (node (ref "U11") (pin "23") (pinfunction "VDD_23") (pintype "passive"))
      (node (ref "U11") (pin "24") (pinfunction "VDD_24") (pintype "passive"))
      (node (ref "U11") (pin "25") (pinfunction "VDD_25") (pintype "passive"))
      (node (ref "U11") (pin "26") (pinfunction "VDD_26") (pintype "passive"))
      (node (ref "U11") (pin "27") (pinfunction "VDD_27") (pintype "passive"))
      (node (ref "U11") (pin "28") (pinfunction "VDD_28") (pintype "passive"))
      (node (ref "U11") (pin "29") (pinfunction "VDD_29") (pintype "passive"))
      (node (ref "U11") (pin "30") (pinfunction "VDD_30") (pintype "passive"))
      (node (ref "U11") (pin "31") (pinfunction "VDD_31") (pintype "passive"))
      (node (ref "U11") (pin "32") (pinfunction "VDD_32") (pintype "passive"))
      (node (ref "U11") (pin "33") (pinfunction "VDD_33") (pintype "passive"))
      (node (ref "U11") (pin "34") (pinfunction "VDD_34") (pintype "passive"))
      (node (ref "U11") (pin "35") (pinfunction "VDD_35") (pintype "passive"))
      (node (ref "U11") (pin "36") (pinfunction "VDD_36") (pintype "passive"))
      (node (ref "U11") (pin "37") (pinfunction "VDD_37") (pintype "passive"))
      (node (ref "U11") (pin "38") (pinfunction "VDD_38") (pintype "passive"))
      (node (ref "U11") (pin "39") (pinfunction "VDD_39") (pintype "passive"))
      (node (ref "U11") (pin "40") (pinfunction "VDD_40") (pintype "passive"))
      (node (ref "U11") (pin "41") (pinfunction "VDD_41") (pintype "passive"))
      (node (ref "U11") (pin "42") (pinfunction "VDD_42") (pintype "passive"))
      (node (ref "U11") (pin "43") (pinfunction "VDD_43") (pintype "passive"))
      (node (ref "U11") (pin "44") (pinfunction "VDD_44") (pintype "passive"))
      (node (ref "U11") (pin "45") (pinfunction "VDD_45") (pintype "passive"))
      (node (ref "U11") (pin "46") (pinfunction "VDD_46") (pintype "passive"))
      (node (ref "U11") (pin "47") (pinfunction "VDD_47") (pintype "passive"))
      (node (ref "U11") (pin "48") (pinfunction "VDD_48") (pintype "passive"))
      (node (ref "U12") (pin "14") (pinfunction "VDD_14") (pintype "passive"))
      (node (ref "U12") (pin "15") (pinfunction "VDD_15") (pintype "passive"))
      (node (ref "U12") (pin "16") (pinfunction "VDD_16") (pintype "passive"))
      (node (ref "U12") (pin "17") (pinfunction "VDD_17") (pintype "passive"))
      (node (ref "U12") (pin "18") (pinfunction "VDD_18") (pintype "passive"))
      (node (ref "U12") (pin "19") (pinfunction "VDD_19") (pintype "passive"))
      (node (ref "U12") (pin "20") (pinfunction "VDD_20") (pintype "passive"))
      (node (ref "U12") (pin "21") (pinfunction "VDD_21") (pintype "passive"))
      (node (ref "U12") (pin "22") (pinfunction "VDD_22") (pintype "passive"))
      (node (ref "U12") (pin "23") (pinfunction "VDD_23") (pintype "passive"))
      (node (ref "U12") (pin "24") (pinfunction "VDD_24") (pintype "passive"))
      (node (ref "U12") (pin "25") (pinfunction "VDD_25") (pintype "passive"))
      (node (ref "U12") (pin "26") (pinfunction "VDD_26") (pintype "passive"))
      (node (ref "U12") (pin "27") (pinfunction "VDD_27") (pintype "passive"))
      (node (ref "U12") (pin "28") (pinfunction "VDD_28") (pintype "passive"))
      (node (ref "U12") (pin "29") (pinfunction "VDD_29") (pintype "passive"))
      (node (ref "U12") (pin "30") (pinfunction "VDD_30") (pintype "passive"))
      (node (ref "U12") (pin "31") (pinfunction "VDD_31") (pintype "passive"))
      (node (ref "U12") (pin "32") (pinfunction "VDD_32") (pintype "passive"))
      (node (ref "U12") (pin "33") (pinfunction "VDD_33") (pintype "passive"))
      (node (ref "U12") (pin "34") (pinfunction "VDD_34") (pintype "passive"))
      (node (ref "U12") (pin "35") (pinfunction "VDD_35") (pintype "passive"))
      (node (ref "U12") (pin "36") (pinfunction "VDD_36") (pintype "passive"))
      (node (ref "U12") (pin "37") (pinfunction "VDD_37") (pintype "passive"))
      (node (ref "U12") (pin "38") (pinfunction "VDD_38") (pintype "passive"))
      (node (ref "U12") (pin "39") (pinfunction "VDD_39") (pintype "passive"))
      (node (ref "U12") (pin "40") (pinfunction "VDD_40") (pintype "passive"))
      (node (ref "U12") (pin "41") (pinfunction "VDD_41") (pintype "passive"))
      (node (ref "U12") (pin "42") (pinfunction "VDD_42") (pintype "passive"))
      (node (ref "U12") (pin "43") (pinfunction "VDD_43") (pintype "passive"))
      (node (ref "U12") (pin "44") (pinfunction "VDD_44") (pintype "passive"))
      (node (ref "U12") (pin "45") (pinfunction "VDD_45") (pintype "passive"))
      (node (ref "U12") (pin "46") (pinfunction "VDD_46") (pintype "passive"))
      (node (ref "U12") (pin "47") (pinfunction "VDD_47") (pintype "passive"))
      (node (ref "U12") (pin "48") (pinfunction "VDD_48") (pintype "passive"))
      (node (ref "U13") (pin "14") (pinfunction "VDD_14") (pintype "passive"))
      (node (ref "U13") (pin "15") (pinfunction "VDD_15") (pintype "passive"))
      (node (ref "U13") (pin "16") (pinfunction "VDD_16") (pintype "passive"))
      (node (ref "U13") (pin "17") (pinfunction "VDD_17") (pintype "passive"))
      (node (ref "U13") (pin "18") (pinfunction "VDD_18") (pintype "passive"))
      (node (ref "U13") (pin "19") (pinfunction "VDD_19") (pintype "passive"))
      (node (ref "U13") (pin "20") (pinfunction "VDD_20") (pintype "passive"))
      (node (ref "U13") (pin "21") (pinfunction "VDD_21") (pintype "passive"))
      (node (ref "U13") (pin "22") (pinfunction "VDD_22") (pintype "passive"))
      (node (ref "U13") (pin "23") (pinfunction "VDD_23") (pintype "passive"))
      (node (ref "U13") (pin "24") (pinfunction "VDD_24") (pintype "passive"))
      (node (ref "U13") (pin "25") (pinfunction "VDD_25") (pintype "passive"))
      (node (ref "U13") (pin "26") (pinfunction "VDD_26") (pintype "passive"))
      (node (ref "U13") (pin "27") (pinfunction "VDD_27") (pintype "passive"))
      (node (ref "U13") (pin "28") (pinfunction "VDD_28") (pintype "passive"))
      (node (ref "U13") (pin "29") (pinfunction "VDD_29") (pintype "passive"))
      (node (ref "U13") (pin "30") (pinfunction "VDD_30") (pintype "passive"))
      (node (ref "U13") (pin "31") (pinfunction "VDD_31") (pintype "passive"))
      (node (ref "U13") (pin "32") (pinfunction "VDD_32") (pintype "passive"))
      (node (ref "U13") (pin "33") (pinfunction "VDD_33") (pintype "passive"))
      (node (ref "U13") (pin "34") (pinfunction "VDD_34") (pintype "passive"))
      (node (ref "U13") (pin "35") (pinfunction "VDD_35") (pintype "passive"))
      (node (ref "U13") (pin "36") (pinfunction "VDD_36") (pintype "passive"))
      (node (ref "U13") (pin "37") (pinfunction "VDD_37") (pintype "passive"))
      (node (ref "U13") (pin "38") (pinfunction "VDD_38") (pintype "passive"))
      (node (ref "U13") (pin "39") (pinfunction "VDD_39") (pintype "passive"))
      (node (ref "U13") (pin "40") (pinfunction "VDD_40") (pintype "passive"))
      (node (ref "U13") (pin "41") (pinfunction "VDD_41") (pintype "passive"))
      (node (ref "U13") (pin "42") (pinfunction "VDD_42") (pintype "passive"))
      (node (ref "U13") (pin "43") (pinfunction "VDD_43") (pintype "passive"))
      (node (ref "U13") (pin "44") (pinfunction "VDD_44") (pintype "passive"))
      (node (ref "U13") (pin "45") (pinfunction "VDD_45") (pintype "passive"))
      (node (ref "U13") (pin "46") (pinfunction "VDD_46") (pintype "passive"))
      (node (ref "U13") (pin "47") (pinfunction "VDD_47") (pintype "passive"))
      (node (ref "U13") (pin "48") (pinfunction "VDD_48") (pintype "passive"))
      (node (ref "U14") (pin "14") (pinfunction "VDD_14") (pintype "passive"))
      (node (ref "U14") (pin "15") (pinfunction "VDD_15") (pintype "passive"))
      (node (ref "U14") (pin "16") (pinfunction "VDD_16") (pintype "passive"))
      (node (ref "U14") (pin "17") (pinfunction "VDD_17") (pintype "passive"))
      (node (ref "U14") (pin "18") (pinfunction "VDD_18") (pintype "passive"))
      (node (ref "U14") (pin "19") (pinfunction "VDD_19") (pintype "passive"))
      (node (ref "U14") (pin "20") (pinfunction "VDD_20") (pintype "passive"))
      (node (ref "U14") (pin "21") (pinfunction "VDD_21") (pintype "passive"))
      (node (ref "U14") (pin "22") (pinfunction "VDD_22") (pintype "passive"))
      (node (ref "U14") (pin "23") (pinfunction "VDD_23") (pintype "passive"))
      (node (ref "U14") (pin "24") (pinfunction "VDD_24") (pintype "passive"))
      (node (ref "U14") (pin "25") (pinfunction "VDD_25") (pintype "passive"))
      (node (ref "U14") (pin "26") (pinfunction "VDD_26") (pintype "passive"))
      (node (ref "U14") (pin "27") (pinfunction "VDD_27") (pintype "passive"))
      (node (ref "U14") (pin "28") (pinfunction "VDD_28") (pintype "passive"))
      (node (ref "U14") (pin "29") (pinfunction "VDD_29") (pintype "passive"))
      (node (ref "U14") (pin "30") (pinfunction "VDD_30") (pintype "passive"))
      (node (ref "U14") (pin "31") (pinfunction "VDD_31") (pintype "passive"))
      (node (ref "U14") (pin "32") (pinfunction "VDD_32") (pintype "passive"))
      (node (ref "U14") (pin "33") (pinfunction "VDD_33") (pintype "passive"))
      (node (ref "U14") (pin "34") (pinfunction "VDD_34") (pintype "passive"))
      (node (ref "U14") (pin "35") (pinfunction "VDD_35") (pintype "passive"))
      (node (ref "U14") (pin "36") (pinfunction "VDD_36") (pintype "passive"))
      (node (ref "U14") (pin "37") (pinfunction "VDD_37") (pintype "passive"))
      (node (ref "U14") (pin "38") (pinfunction "VDD_38") (pintype "passive"))
      (node (ref "U14") (pin "39") (pinfunction "VDD_39") (pintype "passive"))
      (node (ref "U14") (pin "40") (pinfunction "VDD_40") (pintype "passive"))
      (node (ref "U14") (pin "41") (pinfunction "VDD_41") (pintype "passive"))
      (node (ref "U14") (pin "42") (pinfunction "VDD_42") (pintype "passive"))
      (node (ref "U14") (pin "43") (pinfunction "VDD_43") (pintype "passive"))
      (node (ref "U14") (pin "44") (pinfunction "VDD_44") (pintype "passive"))
      (node (ref "U14") (pin "45") (pinfunction "VDD_45") (pintype "passive"))
      (node (ref "U14") (pin "46") (pinfunction "VDD_46") (pintype "passive"))
      (node (ref "U14") (pin "47") (pinfunction "VDD_47") (pintype "passive"))
      (node (ref "U14") (pin "48") (pinfunction "VDD_48") (pintype "passive"))
      (node (ref "U15") (pin "14") (pinfunction "VDD_14") (pintype "passive"))
      (node (ref "U15") (pin "15") (pinfunction "VDD_15") (pintype "passive"))
      (node (ref "U15") (pin "16") (pinfunction "VDD_16") (pintype "passive"))
      (node (ref "U15") (pin "17") (pinfunction "VDD_17") (pintype "passive"))
      (node (ref "U15") (pin "18") (pinfunction "VDD_18") (pintype "passive"))
      (node (ref "U15") (pin "19") (pinfunction "VDD_19") (pintype "passive"))
      (node (ref "U15") (pin "20") (pinfunction "VDD_20") (pintype "passive"))
      (node (ref "U15") (pin "21") (pinfunction "VDD_21") (pintype "passive"))
      (node (ref "U15") (pin "22") (pinfunction "VDD_22") (pintype "passive"))
      (node (ref "U15") (pin "23") (pinfunction "VDD_23") (pintype "passive"))
      (node (ref "U15") (pin "24") (pinfunction "VDD_24") (pintype "passive"))
      (node (ref "U15") (pin "25") (pinfunction "VDD_25") (pintype "passive"))
      (node (ref "U15") (pin "26") (pinfunction "VDD_26") (pintype "passive"))
      (node (ref "U15") (pin "27") (pinfunction "VDD_27") (pintype "passive"))
      (node (ref "U15") (pin "28") (pinfunction "VDD_28") (pintype "passive"))
      (node (ref "U15") (pin "29") (pinfunction "VDD_29") (pintype "passive"))
      (node (ref "U15") (pin "30") (pinfunction "VDD_30") (pintype "passive"))
      (node (ref "U15") (pin "31") (pinfunction "VDD_31") (pintype "passive"))
      (node (ref "U15") (pin "32") (pinfunction "VDD_32") (pintype "passive"))
      (node (ref "U15") (pin "33") (pinfunction "VDD_33") (pintype "passive"))
      (node (ref "U15") (pin "34") (pinfunction "VDD_34") (pintype "passive"))
      (node (ref "U15") (pin "35") (pinfunction "VDD_35") (pintype "passive"))
      (node (ref "U15") (pin "36") (pinfunction "VDD_36") (pintype "passive"))
      (node (ref "U15") (pin "37") (pinfunction "VDD_37") (pintype "passive"))
      (node (ref "U15") (pin "38") (pinfunction "VDD_38") (pintype "passive"))
      (node (ref "U15") (pin "39") (pinfunction "VDD_39") (pintype "passive"))
      (node (ref "U15") (pin "40") (pinfunction "VDD_40") (pintype "passive"))
      (node (ref "U15") (pin "41") (pinfunction "VDD_41") (pintype "passive"))
      (node (ref "U15") (pin "42") (pinfunction "VDD_42") (pintype "passive"))
      (node (ref "U15") (pin "43") (pinfunction "VDD_43") (pintype "passive"))
      (node (ref "U15") (pin "44") (pinfunction "VDD_44") (pintype "passive"))
      (node (ref "U15") (pin "45") (pinfunction "VDD_45") (pintype "passive"))
      (node (ref "U15") (pin "46") (pinfunction "VDD_46") (pintype "passive"))
      (node (ref "U15") (pin "47") (pinfunction "VDD_47") (pintype "passive"))
      (node (ref "U15") (pin "48") (pinfunction "VDD_48") (pintype "passive"))
      (node (ref "U16") (pin "14") (pinfunction "VDD_14") (pintype "passive"))
      (node (ref "U16") (pin "15") (pinfunction "VDD_15") (pintype "passive"))
      (node (ref "U16") (pin "16") (pinfunction "VDD_16") (pintype "passive"))
      (node (ref "U16") (pin "17") (pinfunction "VDD_17") (pintype "passive"))
      (node (ref "U16") (pin "18") (pinfunction "VDD_18") (pintype "passive"))
      (node (ref "U16") (pin "19") (pinfunction "VDD_19") (pintype "passive"))
      (node (ref "U16") (pin "20") (pinfunction "VDD_20") (pintype "passive"))
      (node (ref "U16") (pin "21") (pinfunction "VDD_21") (pintype "passive"))
      (node (ref "U16") (pin "22") (pinfunction "VDD_22") (pintype "passive"))
      (node (ref "U16") (pin "23") (pinfunction "VDD_23") (pintype "passive"))
      (node (ref "U16") (pin "24") (pinfunction "VDD_24") (pintype "passive"))
      (node (ref "U16") (pin "25") (pinfunction "VDD_25") (pintype "passive"))
      (node (ref "U16") (pin "26") (pinfunction "VDD_26") (pintype "passive"))
      (node (ref "U16") (pin "27") (pinfunction "VDD_27") (pintype "passive"))
      (node (ref "U16") (pin "28") (pinfunction "VDD_28") (pintype "passive"))
      (node (ref "U16") (pin "29") (pinfunction "VDD_29") (pintype "passive"))
      (node (ref "U16") (pin "30") (pinfunction "VDD_30") (pintype "passive"))
      (node (ref "U16") (pin "31") (pinfunction "VDD_31") (pintype "passive"))
      (node (ref "U16") (pin "32") (pinfunction "VDD_32") (pintype "passive"))
      (node (ref "U16") (pin "33") (pinfunction "VDD_33") (pintype "passive"))
      (node (ref "U16") (pin "34") (pinfunction "VDD_34") (pintype "passive"))
      (node (ref "U16") (pin "35") (pinfunction "VDD_35") (pintype "passive"))
      (node (ref "U16") (pin "36") (pinfunction "VDD_36") (pintype "passive"))
      (node (ref "U16") (pin "37") (pinfunction "VDD_37") (pintype "passive"))
      (node (ref "U16") (pin "38") (pinfunction "VDD_38") (pintype "passive"))
      (node (ref "U16") (pin "39") (pinfunction "VDD_39") (pintype "passive"))
      (node (ref "U16") (pin "40") (pinfunction "VDD_40") (pintype "passive"))
      (node (ref "U16") (pin "41") (pinfunction "VDD_41") (pintype "passive"))
      (node (ref "U16") (pin "42") (pinfunction "VDD_42") (pintype "passive"))
      (node (ref "U16") (pin "43") (pinfunction "VDD_43") (pintype "passive"))
      (node (ref "U16") (pin "44") (pinfunction "VDD_44") (pintype "passive"))
      (node (ref "U16") (pin "45") (pinfunction "VDD_45") (pintype "passive"))
      (node (ref "U16") (pin "46") (pinfunction "VDD_46") (pintype "passive"))
      (node (ref "U16") (pin "47") (pinfunction "VDD_47") (pintype "passive"))
      (node (ref "U16") (pin "48") (pinfunction "VDD_48") (pintype "passive"))
      (node (ref "U17") (pin "14") (pinfunction "VDD_14") (pintype "passive"))
      (node (ref "U17") (pin "15") (pinfunction "VDD_15") (pintype "passive"))
      (node (ref "U17") (pin "16") (pinfunction "VDD_16") (pintype "passive"))
      (node (ref "U17") (pin "17") (pinfunction "VDD_17") (pintype "passive"))
      (node (ref "U17") (pin "18") (pinfunction "VDD_18") (pintype "passive"))
      (node (ref "U17") (pin "19") (pinfunction "VDD_19") (pintype "passive"))
      (node (ref "U17") (pin "20") (pinfunction "VDD_20") (pintype "passive"))
      (node (ref "U17") (pin "21") (pinfunction "VDD_21") (pintype "passive"))
      (node (ref "U17") (pin "22") (pinfunction "VDD_22") (pintype "passive"))
      (node (ref "U17") (pin "23") (pinfunction "VDD_23") (pintype "passive"))
      (node (ref "U17") (pin "24") (pinfunction "VDD_24") (pintype "passive"))
      (node (ref "U17") (pin "25") (pinfunction "VDD_25") (pintype "passive"))
      (node (ref "U17") (pin "26") (pinfunction "VDD_26") (pintype "passive"))
      (node (ref "U17") (pin "27") (pinfunction "VDD_27") (pintype "passive"))
      (node (ref "U17") (pin "28") (pinfunction "VDD_28") (pintype "passive"))
      (node (ref "U17") (pin "29") (pinfunction "VDD_29") (pintype "passive"))
      (node (ref "U17") (pin "30") (pinfunction "VDD_30") (pintype "passive"))
      (node (ref "U17") (pin "31") (pinfunction "VDD_31") (pintype "passive"))
      (node (ref "U17") (pin "32") (pinfunction "VDD_32") (pintype "passive"))
      (node (ref "U17") (pin "33") (pinfunction "VDD_33") (pintype "passive"))
      (node (ref "U17") (pin "34") (pinfunction "VDD_34") (pintype "passive"))
      (node (ref "U17") (pin "35") (pinfunction "VDD_35") (pintype "passive"))
      (node (ref "U17") (pin "36") (pinfunction "VDD_36") (pintype "passive"))
      (node (ref "U17") (pin "37") (pinfunction "VDD_37") (pintype "passive"))
      (node (ref "U17") (pin "38") (pinfunction "VDD_38") (pintype "passive"))
      (node (ref "U17") (pin "39") (pinfunction "VDD_39") (pintype "passive"))
      (node (ref "U17") (pin "40") (pinfunction "VDD_40") (pintype "passive"))
      (node (ref "U17") (pin "41") (pinfunction "VDD_41") (pintype "passive"))
      (node (ref "U17") (pin "42") (pinfunction "VDD_42") (pintype "passive"))
      (node (ref "U17") (pin "43") (pinfunction "VDD_43") (pintype "passive"))
      (node (ref "U17") (pin "44") (pinfunction "VDD_44") (pintype "passive"))
      (node (ref "U17") (pin "45") (pinfunction "VDD_45") (pintype "passive"))
      (node (ref "U17") (pin "46") (pinfunction "VDD_46") (pintype "passive"))
      (node (ref "U17") (pin "47") (pinfunction "VDD_47") (pintype "passive"))
      (node (ref "U17") (pin "48") (pinfunction "VDD_48") (pintype "passive"))
      (node (ref "U18") (pin "14") (pinfunction "VDD_14") (pintype "passive"))
      (node (ref "U18") (pin "15") (pinfunction "VDD_15") (pintype "passive"))
      (node (ref "U18") (pin "16") (pinfunction "VDD_16") (pintype "passive"))
      (node (ref "U18") (pin "17") (pinfunction "VDD_17") (pintype "passive"))
      (node (ref "U18") (pin "18") (pinfunction "VDD_18") (pintype "passive"))
      (node (ref "U18") (pin "19") (pinfunction "VDD_19") (pintype "passive"))
      (node (ref "U18") (pin "20") (pinfunction "VDD_20") (pintype "passive"))
      (node (ref "U18") (pin "21") (pinfunction "VDD_21") (pintype "passive"))
      (node (ref "U18") (pin "22") (pinfunction "VDD_22") (pintype "passive"))
      (node (ref "U18") (pin "23") (pinfunction "VDD_23") (pintype "passive"))
      (node (ref "U18") (pin "24") (pinfunction "VDD_24") (pintype "passive"))
      (node (ref "U18") (pin "25") (pinfunction "VDD_25") (pintype "passive"))
      (node (ref "U18") (pin "26") (pinfunction "VDD_26") (pintype "passive"))
      (node (ref "U18") (pin "27") (pinfunction "VDD_27") (pintype "passive"))
      (node (ref "U18") (pin "28") (pinfunction "VDD_28") (pintype "passive"))
      (node (ref "U18") (pin "29") (pinfunction "VDD_29") (pintype "passive"))
      (node (ref "U18") (pin "30") (pinfunction "VDD_30") (pintype "passive"))
      (node (ref "U18") (pin "31") (pinfunction "VDD_31") (pintype "passive"))
      (node (ref "U18") (pin "32") (pinfunction "VDD_32") (pintype "passive"))
      (node (ref "U18") (pin "33") (pinfunction "VDD_33") (pintype "passive"))
      (node (ref "U18") (pin "34") (pinfunction "VDD_34") (pintype "passive"))
      (node (ref "U18") (pin "35") (pinfunction "VDD_35") (pintype "passive"))
      (node (ref "U18") (pin "36") (pinfunction "VDD_36") (pintype "passive"))
      (node (ref "U18") (pin "37") (pinfunction "VDD_37") (pintype "passive"))
      (node (ref "U18") (pin "38") (pinfunction "VDD_38") (pintype "passive"))
      (node (ref "U18") (pin "39") (pinfunction "VDD_39") (pintype "passive"))
      (node (ref "U18") (pin "40") (pinfunction "VDD_40") (pintype "passive"))
      (node (ref "U18") (pin "41") (pinfunction "VDD_41") (pintype "passive"))
      (node (ref "U18") (pin "42") (pinfunction "VDD_42") (pintype "passive"))
      (node (ref "U18") (pin "43") (pinfunction "VDD_43") (pintype "passive"))
      (node (ref "U18") (pin "44") (pinfunction "VDD_44") (pintype "passive"))
      (node (ref "U18") (pin "45") (pinfunction "VDD_45") (pintype "passive"))
      (node (ref "U18") (pin "46") (pinfunction "VDD_46") (pintype "passive"))
      (node (ref "U18") (pin "47") (pinfunction "VDD_47") (pintype "passive"))
      (node (ref "U18") (pin "48") (pinfunction "VDD_48") (pintype "passive"))
      (node (ref "U2") (pin "14") (pinfunction "VDD_14") (pintype "passive"))
      (node (ref "U2") (pin "15") (pinfunction "VDD_15") (pintype "passive"))
      (node (ref "U2") (pin "16") (pinfunction "VDD_16") (pintype "passive"))
      (node (ref "U2") (pin "17") (pinfunction "VDD_17") (pintype "passive"))
      (node (ref "U2") (pin "18") (pinfunction "VDD_18") (pintype "passive"))
      (node (ref "U2") (pin "19") (pinfunction "VDD_19") (pintype "passive"))
      (node (ref "U2") (pin "20") (pinfunction "VDD_20") (pintype "passive"))
      (node (ref "U2") (pin "21") (pinfunction "VDD_21") (pintype "passive"))
      (node (ref "U2") (pin "22") (pinfunction "VDD_22") (pintype "passive"))
      (node (ref "U2") (pin "23") (pinfunction "VDD_23") (pintype "passive"))
      (node (ref "U2") (pin "24") (pinfunction "VDD_24") (pintype "passive"))
      (node (ref "U2") (pin "25") (pinfunction "VDD_25") (pintype "passive"))
      (node (ref "U2") (pin "26") (pinfunction "VDD_26") (pintype "passive"))
      (node (ref "U2") (pin "27") (pinfunction "VDD_27") (pintype "passive"))
      (node (ref "U2") (pin "28") (pinfunction "VDD_28") (pintype "passive"))
      (node (ref "U2") (pin "29") (pinfunction "VDD_29") (pintype "passive"))
      (node (ref "U2") (pin "30") (pinfunction "VDD_30") (pintype "passive"))
      (node (ref "U2") (pin "31") (pinfunction "VDD_31") (pintype "passive"))
      (node (ref "U2") (pin "32") (pinfunction "VDD_32") (pintype "passive"))
      (node (ref "U2") (pin "33") (pinfunction "VDD_33") (pintype "passive"))
      (node (ref "U2") (pin "34") (pinfunction "VDD_34") (pintype "passive"))
      (node (ref "U2") (pin "35") (pinfunction "VDD_35") (pintype "passive"))
      (node (ref "U2") (pin "36") (pinfunction "VDD_36") (pintype "passive"))
      (node (ref "U2") (pin "37") (pinfunction "VDD_37") (pintype "passive"))
      (node (ref "U2") (pin "38") (pinfunction "VDD_38") (pintype "passive"))
      (node (ref "U2") (pin "39") (pinfunction "VDD_39") (pintype "passive"))
      (node (ref "U2") (pin "40") (pinfunction "VDD_40") (pintype "passive"))
      (node (ref "U2") (pin "41") (pinfunction "VDD_41") (pintype "passive"))
      (node (ref "U2") (pin "42") (pinfunction "VDD_42") (pintype "passive"))
      (node (ref "U2") (pin "43") (pinfunction "VDD_43") (pintype "passive"))
      (node (ref "U2") (pin "44") (pinfunction "VDD_44") (pintype "passive"))
      (node (ref "U2") (pin "45") (pinfunction "VDD_45") (pintype "passive"))
      (node (ref "U2") (pin "46") (pinfunction "VDD_46") (pintype "passive"))
      (node (ref "U2") (pin "47") (pinfunction "VDD_47") (pintype "passive"))
      (node (ref "U2") (pin "48") (pinfunction "VDD_48") (pintype "passive"))
      (node (ref "U3") (pin "14") (pinfunction "VDD_14") (pintype "passive"))
      (node (ref "U3") (pin "15") (pinfunction "VDD_15") (pintype "passive"))
      (node (ref "U3") (pin "16") (pinfunction "VDD_16") (pintype "passive"))
      (node (ref "U3") (pin "17") (pinfunction "VDD_17") (pintype "passive"))
      (node (ref "U3") (pin "18") (pinfunction "VDD_18") (pintype "passive"))
      (node (ref "U3") (pin "19") (pinfunction "VDD_19") (pintype "passive"))
      (node (ref "U3") (pin "20") (pinfunction "VDD_20") (pintype "passive"))
      (node (ref "U3") (pin "21") (pinfunction "VDD_21") (pintype "passive"))
      (node (ref "U3") (pin "22") (pinfunction "VDD_22") (pintype "passive"))
      (node (ref "U3") (pin "23") (pinfunction "VDD_23") (pintype "passive"))
      (node (ref "U3") (pin "24") (pinfunction "VDD_24") (pintype "passive"))
      (node (ref "U3") (pin "25") (pinfunction "VDD_25") (pintype "passive"))
      (node (ref "U3") (pin "26") (pinfunction "VDD_26") (pintype "passive"))
      (node (ref "U3") (pin "27") (pinfunction "VDD_27") (pintype "passive"))
      (node (ref "U3") (pin "28") (pinfunction "VDD_28") (pintype "passive"))
      (node (ref "U3") (pin "29") (pinfunction "VDD_29") (pintype "passive"))
      (node (ref "U3") (pin "30") (pinfunction "VDD_30") (pintype "passive"))
      (node (ref "U3") (pin "31") (pinfunction "VDD_31") (pintype "passive"))
      (node (ref "U3") (pin "32") (pinfunction "VDD_32") (pintype "passive"))
      (node (ref "U3") (pin "33") (pinfunction "VDD_33") (pintype "passive"))
      (node (ref "U3") (pin "34") (pinfunction "VDD_34") (pintype "passive"))
      (node (ref "U3") (pin "35") (pinfunction "VDD_35") (pintype "passive"))
      (node (ref "U3") (pin "36") (pinfunction "VDD_36") (pintype "passive"))
      (node (ref "U3") (pin "37") (pinfunction "VDD_37") (pintype "passive"))
      (node (ref "U3") (pin "38") (pinfunction "VDD_38") (pintype "passive"))
      (node (ref "U3") (pin "39") (pinfunction "VDD_39") (pintype "passive"))
      (node (ref "U3") (pin "40") (pinfunction "VDD_40") (pintype "passive"))
      (node (ref "U3") (pin "41") (pinfunction "VDD_41") (pintype "passive"))
      (node (ref "U3") (pin "42") (pinfunction "VDD_42") (pintype "passive"))
      (node (ref "U3") (pin "43") (pinfunction "VDD_43") (pintype "passive"))
      (node (ref "U3") (pin "44") (pinfunction "VDD_44") (pintype "passive"))
      (node (ref "U3") (pin "45") (pinfunction "VDD_45") (pintype "passive"))
      (node (ref "U3") (pin "46") (pinfunction "VDD_46") (pintype "passive"))
      (node (ref "U3") (pin "47") (pinfunction "VDD_47") (pintype "passive"))
      (node (ref "U3") (pin "48") (pinfunction "VDD_48") (pintype "passive"))
      (node (ref "U4") (pin "14") (pinfunction "VDD_14") (pintype "passive"))
      (node (ref "U4") (pin "15") (pinfunction "VDD_15") (pintype "passive"))
      (node (ref "U4") (pin "16") (pinfunction "VDD_16") (pintype "passive"))
      (node (ref "U4") (pin "17") (pinfunction "VDD_17") (pintype "passive"))
      (node (ref "U4") (pin "18") (pinfunction "VDD_18") (pintype "passive"))
      (node (ref "U4") (pin "19") (pinfunction "VDD_19") (pintype "passive"))
      (node (ref "U4") (pin "20") (pinfunction "VDD_20") (pintype "passive"))
      (node (ref "U4") (pin "21") (pinfunction "VDD_21") (pintype "passive"))
      (node (ref "U4") (pin "22") (pinfunction "VDD_22") (pintype "passive"))
      (node (ref "U4") (pin "23") (pinfunction "VDD_23") (pintype "passive"))
      (node (ref "U4") (pin "24") (pinfunction "VDD_24") (pintype "passive"))
      (node (ref "U4") (pin "25") (pinfunction "VDD_25") (pintype "passive"))
      (node (ref "U4") (pin "26") (pinfunction "VDD_26") (pintype "passive"))
      (node (ref "U4") (pin "27") (pinfunction "VDD_27") (pintype "passive"))
      (node (ref "U4") (pin "28") (pinfunction "VDD_28") (pintype "passive"))
      (node (ref "U4") (pin "29") (pinfunction "VDD_29") (pintype "passive"))
      (node (ref "U4") (pin "30") (pinfunction "VDD_30") (pintype "passive"))
      (node (ref "U4") (pin "31") (pinfunction "VDD_31") (pintype "passive"))
      (node (ref "U4") (pin "32") (pinfunction "VDD_32") (pintype "passive"))
      (node (ref "U4") (pin "33") (pinfunction "VDD_33") (pintype "passive"))
      (node (ref "U4") (pin "34") (pinfunction "VDD_34") (pintype "passive"))
      (node (ref "U4") (pin "35") (pinfunction "VDD_35") (pintype "passive"))
      (node (ref "U4") (pin "36") (pinfunction "VDD_36") (pintype "passive"))
      (node (ref "U4") (pin "37") (pinfunction "VDD_37") (pintype "passive"))
      (node (ref "U4") (pin "38") (pinfunction "VDD_38") (pintype "passive"))
      (node (ref "U4") (pin "39") (pinfunction "VDD_39") (pintype "passive"))
      (node (ref "U4") (pin "40") (pinfunction "VDD_40") (pintype "passive"))
      (node (ref "U4") (pin "41") (pinfunction "VDD_41") (pintype "passive"))
      (node (ref "U4") (pin "42") (pinfunction "VDD_42") (pintype "passive"))
      (node (ref "U4") (pin "43") (pinfunction "VDD_43") (pintype "passive"))
      (node (ref "U4") (pin "44") (pinfunction "VDD_44") (pintype "passive"))
      (node (ref "U4") (pin "45") (pinfunction "VDD_45") (pintype "passive"))
      (node (ref "U4") (pin "46") (pinfunction "VDD_46") (pintype "passive"))
      (node (ref "U4") (pin "47") (pinfunction "VDD_47") (pintype "passive"))
      (node (ref "U4") (pin "48") (pinfunction "VDD_48") (pintype "passive"))
      (node (ref "U5") (pin "14") (pinfunction "VDD_14") (pintype "passive"))
      (node (ref "U5") (pin "15") (pinfunction "VDD_15") (pintype "passive"))
      (node (ref "U5") (pin "16") (pinfunction "VDD_16") (pintype "passive"))
      (node (ref "U5") (pin "17") (pinfunction "VDD_17") (pintype "passive"))
      (node (ref "U5") (pin "18") (pinfunction "VDD_18") (pintype "passive"))
      (node (ref "U5") (pin "19") (pinfunction "VDD_19") (pintype "passive"))
      (node (ref "U5") (pin "20") (pinfunction "VDD_20") (pintype "passive"))
      (node (ref "U5") (pin "21") (pinfunction "VDD_21") (pintype "passive"))
      (node (ref "U5") (pin "22") (pinfunction "VDD_22") (pintype "passive"))
      (node (ref "U5") (pin "23") (pinfunction "VDD_23") (pintype "passive"))
      (node (ref "U5") (pin "24") (pinfunction "VDD_24") (pintype "passive"))
      (node (ref "U5") (pin "25") (pinfunction "VDD_25") (pintype "passive"))
      (node (ref "U5") (pin "26") (pinfunction "VDD_26") (pintype "passive"))
      (node (ref "U5") (pin "27") (pinfunction "VDD_27") (pintype "passive"))
      (node (ref "U5") (pin "28") (pinfunction "VDD_28") (pintype "passive"))
      (node (ref "U5") (pin "29") (pinfunction "VDD_29") (pintype "passive"))
      (node (ref "U5") (pin "30") (pinfunction "VDD_30") (pintype "passive"))
      (node (ref "U5") (pin "31") (pinfunction "VDD_31") (pintype "passive"))
      (node (ref "U5") (pin "32") (pinfunction "VDD_32") (pintype "passive"))
      (node (ref "U5") (pin "33") (pinfunction "VDD_33") (pintype "passive"))
      (node (ref "U5") (pin "34") (pinfunction "VDD_34") (pintype "passive"))
      (node (ref "U5") (pin "35") (pinfunction "VDD_35") (pintype "passive"))
      (node (ref "U5") (pin "36") (pinfunction "VDD_36") (pintype "passive"))
      (node (ref "U5") (pin "37") (pinfunction "VDD_37") (pintype "passive"))
      (node (ref "U5") (pin "38") (pinfunction "VDD_38") (pintype "passive"))
      (node (ref "U5") (pin "39") (pinfunction "VDD_39") (pintype "passive"))
      (node (ref "U5") (pin "40") (pinfunction "VDD_40") (pintype "passive"))
      (node (ref "U5") (pin "41") (pinfunction "VDD_41") (pintype "passive"))
      (node (ref "U5") (pin "42") (pinfunction "VDD_42") (pintype "passive"))
      (node (ref "U5") (pin "43") (pinfunction "VDD_43") (pintype "passive"))
      (node (ref "U5") (pin "44") (pinfunction "VDD_44") (pintype "passive"))
      (node (ref "U5") (pin "45") (pinfunction "VDD_45") (pintype "passive"))
      (node (ref "U5") (pin "46") (pinfunction "VDD_46") (pintype "passive"))
      (node (ref "U5") (pin "47") (pinfunction "VDD_47") (pintype "passive"))
      (node (ref "U5") (pin "48") (pinfunction "VDD_48") (pintype "passive"))
      (node (ref "U7") (pin "14") (pinfunction "VDD_14") (pintype "passive"))
      (node (ref "U7") (pin "15") (pinfunction "VDD_15") (pintype "passive"))
      (node (ref "U7") (pin "16") (pinfunction "VDD_16") (pintype "passive"))
      (node (ref "U7") (pin "17") (pinfunction "VDD_17") (pintype "passive"))
      (node (ref "U7") (pin "18") (pinfunction "VDD_18") (pintype "passive"))
      (node (ref "U7") (pin "19") (pinfunction "VDD_19") (pintype "passive"))
      (node (ref "U7") (pin "20") (pinfunction "VDD_20") (pintype "passive"))
      (node (ref "U7") (pin "21") (pinfunction "VDD_21") (pintype "passive"))
      (node (ref "U7") (pin "22") (pinfunction "VDD_22") (pintype "passive"))
      (node (ref "U7") (pin "23") (pinfunction "VDD_23") (pintype "passive"))
      (node (ref "U7") (pin "24") (pinfunction "VDD_24") (pintype "passive"))
      (node (ref "U7") (pin "25") (pinfunction "VDD_25") (pintype "passive"))
      (node (ref "U7") (pin "26") (pinfunction "VDD_26") (pintype "passive"))
      (node (ref "U7") (pin "27") (pinfunction "VDD_27") (pintype "passive"))
      (node (ref "U7") (pin "28") (pinfunction "VDD_28") (pintype "passive"))
      (node (ref "U7") (pin "29") (pinfunction "VDD_29") (pintype "passive"))
      (node (ref "U7") (pin "30") (pinfunction "VDD_30") (pintype "passive"))
      (node (ref "U7") (pin "31") (pinfunction "VDD_31") (pintype "passive"))
      (node (ref "U7") (pin "32") (pinfunction "VDD_32") (pintype "passive"))
      (node (ref "U7") (pin "33") (pinfunction "VDD_33") (pintype "passive"))
      (node (ref "U7") (pin "34") (pinfunction "VDD_34") (pintype "passive"))
      (node (ref "U7") (pin "35") (pinfunction "VDD_35") (pintype "passive"))
      (node (ref "U7") (pin "36") (pinfunction "VDD_36") (pintype "passive"))
      (node (ref "U7") (pin "37") (pinfunction "VDD_37") (pintype "passive"))
      (node (ref "U7") (pin "38") (pinfunction "VDD_38") (pintype "passive"))
      (node (ref "U7") (pin "39") (pinfunction "VDD_39") (pintype "passive"))
      (node (ref "U7") (pin "40") (pinfunction "VDD_40") (pintype "passive"))
      (node (ref "U7") (pin "41") (pinfunction "VDD_41") (pintype "passive"))
      (node (ref "U7") (pin "42") (pinfunction "VDD_42") (pintype "passive"))
      (node (ref "U7") (pin "43") (pinfunction "VDD_43") (pintype "passive"))
      (node (ref "U7") (pin "44") (pinfunction "VDD_44") (pintype "passive"))
      (node (ref "U7") (pin "45") (pinfunction "VDD_45") (pintype "passive"))
      (node (ref "U7") (pin "46") (pinfunction "VDD_46") (pintype "passive"))
      (node (ref "U7") (pin "47") (pinfunction "VDD_47") (pintype "passive"))
      (node (ref "U7") (pin "48") (pinfunction "VDD_48") (pintype "passive"))
      (node (ref "U8") (pin "14") (pinfunction "VDD_14") (pintype "passive"))
      (node (ref "U8") (pin "15") (pinfunction "VDD_15") (pintype "passive"))
      (node (ref "U8") (pin "16") (pinfunction "VDD_16") (pintype "passive"))
      (node (ref "U8") (pin "17") (pinfunction "VDD_17") (pintype "passive"))
      (node (ref "U8") (pin "18") (pinfunction "VDD_18") (pintype "passive"))
      (node (ref "U8") (pin "19") (pinfunction "VDD_19") (pintype "passive"))
      (node (ref "U8") (pin "20") (pinfunction "VDD_20") (pintype "passive"))
      (node (ref "U8") (pin "21") (pinfunction "VDD_21") (pintype "passive"))
      (node (ref "U8") (pin "22") (pinfunction "VDD_22") (pintype "passive"))
      (node (ref "U8") (pin "23") (pinfunction "VDD_23") (pintype "passive"))
      (node (ref "U8") (pin "24") (pinfunction "VDD_24") (pintype "passive"))
      (node (ref "U8") (pin "25") (pinfunction "VDD_25") (pintype "passive"))
      (node (ref "U8") (pin "26") (pinfunction "VDD_26") (pintype "passive"))
      (node (ref "U8") (pin "27") (pinfunction "VDD_27") (pintype "passive"))
      (node (ref "U8") (pin "28") (pinfunction "VDD_28") (pintype "passive"))
      (node (ref "U8") (pin "29") (pinfunction "VDD_29") (pintype "passive"))
      (node (ref "U8") (pin "30") (pinfunction "VDD_30") (pintype "passive"))
      (node (ref "U8") (pin "31") (pinfunction "VDD_31") (pintype "passive"))
      (node (ref "U8") (pin "32") (pinfunction "VDD_32") (pintype "passive"))
      (node (ref "U8") (pin "33") (pinfunction "VDD_33") (pintype "passive"))
      (node (ref "U8") (pin "34") (pinfunction "VDD_34") (pintype "passive"))
      (node (ref "U8") (pin "35") (pinfunction "VDD_35") (pintype "passive"))
      (node (ref "U8") (pin "36") (pinfunction "VDD_36") (pintype "passive"))
      (node (ref "U8") (pin "37") (pinfunction "VDD_37") (pintype "passive"))
      (node (ref "U8") (pin "38") (pinfunction "VDD_38") (pintype "passive"))
      (node (ref "U8") (pin "39") (pinfunction "VDD_39") (pintype "passive"))
      (node (ref "U8") (pin "40") (pinfunction "VDD_40") (pintype "passive"))
      (node (ref "U8") (pin "41") (pinfunction "VDD_41") (pintype "passive"))
      (node (ref "U8") (pin "42") (pinfunction "VDD_42") (pintype "passive"))
      (node (ref "U8") (pin "43") (pinfunction "VDD_43") (pintype "passive"))
      (node (ref "U8") (pin "44") (pinfunction "VDD_44") (pintype "passive"))
      (node (ref "U8") (pin "45") (pinfunction "VDD_45") (pintype "passive"))
      (node (ref "U8") (pin "46") (pinfunction "VDD_46") (pintype "passive"))
      (node (ref "U8") (pin "47") (pinfunction "VDD_47") (pintype "passive"))
      (node (ref "U8") (pin "48") (pinfunction "VDD_48") (pintype "passive"))
      (node (ref "U9") (pin "14") (pinfunction "VDD_14") (pintype "passive"))
      (node (ref "U9") (pin "15") (pinfunction "VDD_15") (pintype "passive"))
      (node (ref "U9") (pin "16") (pinfunction "VDD_16") (pintype "passive"))
      (node (ref "U9") (pin "17") (pinfunction "VDD_17") (pintype "passive"))
      (node (ref "U9") (pin "18") (pinfunction "VDD_18") (pintype "passive"))
      (node (ref "U9") (pin "19") (pinfunction "VDD_19") (pintype "passive"))
      (node (ref "U9") (pin "20") (pinfunction "VDD_20") (pintype "passive"))
      (node (ref "U9") (pin "21") (pinfunction "VDD_21") (pintype "passive"))
      (node (ref "U9") (pin "22") (pinfunction "VDD_22") (pintype "passive"))
      (node (ref "U9") (pin "23") (pinfunction "VDD_23") (pintype "passive"))
      (node (ref "U9") (pin "24") (pinfunction "VDD_24") (pintype "passive"))
      (node (ref "U9") (pin "25") (pinfunction "VDD_25") (pintype "passive"))
      (node (ref "U9") (pin "26") (pinfunction "VDD_26") (pintype "passive"))
      (node (ref "U9") (pin "27") (pinfunction "VDD_27") (pintype "passive"))
      (node (ref "U9") (pin "28") (pinfunction "VDD_28") (pintype "passive"))
      (node (ref "U9") (pin "29") (pinfunction "VDD_29") (pintype "passive"))
      (node (ref "U9") (pin "30") (pinfunction "VDD_30") (pintype "passive"))
      (node (ref "U9") (pin "31") (pinfunction "VDD_31") (pintype "passive"))
      (node (ref "U9") (pin "32") (pinfunction "VDD_32") (pintype "passive"))
      (node (ref "U9") (pin "33") (pinfunction "VDD_33") (pintype "passive"))
      (node (ref "U9") (pin "34") (pinfunction "VDD_34") (pintype "passive"))
      (node (ref "U9") (pin "35") (pinfunction "VDD_35") (pintype "passive"))
      (node (ref "U9") (pin "36") (pinfunction "VDD_36") (pintype "passive"))
      (node (ref "U9") (pin "37") (pinfunction "VDD_37") (pintype "passive"))
      (node (ref "U9") (pin "38") (pinfunction "VDD_38") (pintype "passive"))
      (node (ref "U9") (pin "39") (pinfunction "VDD_39") (pintype "passive"))
      (node (ref "U9") (pin "40") (pinfunction "VDD_40") (pintype "passive"))
      (node (ref "U9") (pin "41") (pinfunction "VDD_41") (pintype "passive"))
      (node (ref "U9") (pin "42") (pinfunction "VDD_42") (pintype "passive"))
      (node (ref "U9") (pin "43") (pinfunction "VDD_43") (pintype "passive"))
      (node (ref "U9") (pin "44") (pinfunction "VDD_44") (pintype "passive"))
      (node (ref "U9") (pin "45") (pinfunction "VDD_45") (pintype "passive"))
      (node (ref "U9") (pin "46") (pinfunction "VDD_46") (pintype "passive"))
      (node (ref "U9") (pin "47") (pinfunction "VDD_47") (pintype "passive"))
      (node (ref "U9") (pin "48") (pinfunction "VDD_48") (pintype "passive"))
    )
    (net (code "2") (name "/0.8VR1") (class "Default")
      (node (ref "C13") (pin "2") (pinfunction "2_2") (pintype "passive"))
      (node (ref "R24") (pin "2") (pinfunction "2_2") (pintype "passive"))
      (node (ref "R28") (pin "1") (pinfunction "1_1") (pintype "passive"))
      (node (ref "U2") (pin "13") (pinfunction "IOREF_13") (pintype "passive"))
    )
    (net (code "3") (name "/0.8VR2") (class "Default")
      (node (ref "C14") (pin "2") (pinfunction "2_2") (pintype "passive"))
      (node (ref "R25") (pin "2") (pinfunction "2_2") (pintype "passive"))
      (node (ref "R29") (pin "1") (pinfunction "1_1") (pintype "passive"))
      (node (ref "U3") (pin "13") (pinfunction "IOREF_13") (pintype "passive"))
    )
    (net (code "4") (name "/0.8VR3") (class "Default")
      (node (ref "C15") (pin "2") (pinfunction "2_2") (pintype "passive"))
      (node (ref "R26") (pin "2") (pinfunction "2_2") (pintype "passive"))
      (node (ref "R30") (pin "1") (pinfunction "1_1") (pintype "passive"))
      (node (ref "U4") (pin "13") (pinfunction "IOREF_13") (pintype "passive"))
    )
    (net (code "5") (name "/0.8VR4") (class "Default")
      (node (ref "C16") (pin "2") (pinfunction "2_2") (pintype "passive"))
      (node (ref "R27") (pin "2") (pinfunction "2_2") (pintype "passive"))
      (node (ref "R31") (pin "1") (pinfunction "1_1") (pintype "passive"))
      (node (ref "U5") (pin "13") (pinfunction "IOREF_13") (pintype "passive"))
    )
    (net (code "6") (name "/0.8VR5") (class "Default")
      (node (ref "C18") (pin "2") (pinfunction "2_2") (pintype "passive"))
      (node (ref "R79") (pin "2") (pinfunction "2_2") (pintype "passive"))
      (node (ref "R83") (pin "1") (pinfunction "1_1") (pintype "passive"))
      (node (ref "U7") (pin "13") (pinfunction "IOREF_13") (pintype "passive"))
    )
    (net (code "7") (name "/0.8VR6") (class "Default")
      (node (ref "C19") (pin "2") (pinfunction "2_2") (pintype "passive"))
      (node (ref "R80") (pin "2") (pinfunction "2_2") (pintype "passive"))
      (node (ref "R84") (pin "1") (pinfunction "1_1") (pintype "passive"))
      (node (ref "U8") (pin "13") (pinfunction "IOREF_13") (pintype "passive"))
    )
    (net (code "8") (name "/0.8VR7") (class "Default")
      (node (ref "C20") (pin "2") (pinfunction "2_2") (pintype "passive"))
      (node (ref "R81") (pin "2") (pinfunction "2_2") (pintype "passive"))
      (node (ref "R85") (pin "1") (pinfunction "1_1") (pintype "passive"))
      (node (ref "U9") (pin "13") (pinfunction "IOREF_13") (pintype "passive"))
    )
    (net (code "9") (name "/0.8VR8") (class "Default")
      (node (ref "C21") (pin "2") (pinfunction "2_2") (pintype "passive"))
      (node (ref "R82") (pin "2") (pinfunction "2_2") (pintype "passive"))
      (node (ref "R86") (pin "1") (pinfunction "1_1") (pintype "passive"))
      (node (ref "U10") (pin "13") (pinfunction "IOREF_13") (pintype "passive"))
    )
    (net (code "10") (name "/0.8VR9") (class "Default")
      (node (ref "C22") (pin "2") (pinfunction "2_2") (pintype "passive"))
      (node (ref "R103") (pin "2") (pinfunction "2_2") (pintype "passive"))
      (node (ref "R107") (pin "1") (pinfunction "1_1") (pintype "passive"))
      (node (ref "U11") (pin "13") (pinfunction "IOREF_13") (pintype "passive"))
    )
    (net (code "11") (name "/0.8VR10") (class "Default")
      (node (ref "C23") (pin "2") (pinfunction "2_2") (pintype "passive"))
      (node (ref "R104") (pin "2") (pinfunction "2_2") (pintype "passive"))
      (node (ref "R108") (pin "1") (pinfunction "1_1") (pintype "passive"))
      (node (ref "U12") (pin "13") (pinfunction "IOREF_13") (pintype "passive"))
    )
    (net (code "12") (name "/0.8VR11") (class "Default")
      (node (ref "C24") (pin "2") (pinfunction "2_2") (pintype "passive"))
      (node (ref "R105") (pin "2") (pinfunction "2_2") (pintype "passive"))
      (node (ref "R109") (pin "1") (pinfunction "1_1") (pintype "passive"))
      (node (ref "U13") (pin "13") (pinfunction "IOREF_13") (pintype "passive"))
    )
    (net (code "13") (name "/0.8VR12") (class "Default")
      (node (ref "C25") (pin "2") (pinfunction "2_2") (pintype "passive"))
      (node (ref "R106") (pin "2") (pinfunction "2_2") (pintype "passive"))
      (node (ref "R110") (pin "1") (pinfunction "1_1") (pintype "passive"))
      (node (ref "U14") (pin "13") (pinfunction "IOREF_13") (pintype "passive"))
    )
    (net (code "14") (name "/0.8VR13") (class "Default")
      (node (ref "C26") (pin "2") (pinfunction "2_2") (pintype "passive"))
      (node (ref "R127") (pin "2") (pinfunction "2_2") (pintype "passive"))
      (node (ref "R131") (pin "1") (pinfunction "1_1") (pintype "passive"))
      (node (ref "U15") (pin "13") (pinfunction "IOREF_13") (pintype "passive"))
    )
    (net (code "15") (name "/0.8VR14") (class "Default")
      (node (ref "C27") (pin "2") (pinfunction "2_2") (pintype "passive"))
      (node (ref "R128") (pin "2") (pinfunction "2_2") (pintype "passive"))
      (node (ref "R132") (pin "1") (pinfunction "1_1") (pintype "passive"))
      (node (ref "U16") (pin "13") (pinfunction "IOREF_13") (pintype "passive"))
    )
    (net (code "16") (name "/0.8VR15") (class "Default")
      (node (ref "C28") (pin "2") (pinfunction "2_2") (pintype "passive"))
      (node (ref "R129") (pin "2") (pinfunction "2_2") (pintype "passive"))
      (node (ref "R133") (pin "1") (pinfunction "1_1") (pintype "passive"))
      (node (ref "U17") (pin "13") (pinfunction "IOREF_13") (pintype "passive"))
    )
    (net (code "17") (name "/0.8VR16") (class "Default")
      (node (ref "C29") (pin "2") (pinfunction "2_2") (pintype "passive"))
      (node (ref "R130") (pin "2") (pinfunction "2_2") (pintype "passive"))
      (node (ref "R134") (pin "1") (pinfunction "1_1") (pintype "passive"))
      (node (ref "U18") (pin "13") (pinfunction "IOREF_13") (pintype "passive"))
    )
    (net (code "18") (name "/1.8V") (class "Default")
      (node (ref "C206") (pin "2") (pinfunction "2_2") (pintype "passive"))
      (node (ref "R107") (pin "2") (pinfunction "2_2") (pintype "passive"))
      (node (ref "R108") (pin "2") (pinfunction "2_2") (pintype "passive"))
      (node (ref "R109") (pin "2") (pinfunction "2_2") (pintype "passive"))
      (node (ref "R110") (pin "2") (pinfunction "2_2") (pintype "passive"))
      (node (ref "R131") (pin "2") (pinfunction "2_2") (pintype "passive"))
      (node (ref "R132") (pin "2") (pinfunction "2_2") (pintype "passive"))
      (node (ref "R133") (pin "2") (pinfunction "2_2") (pintype "passive"))
      (node (ref "R134") (pin "2") (pinfunction "2_2") (pintype "passive"))
      (node (ref "R28") (pin "2") (pinfunction "2_2") (pintype "passive"))
      (node (ref "R29") (pin "2") (pinfunction "2_2") (pintype "passive"))
      (node (ref "R30") (pin "2") (pinfunction "2_2") (pintype "passive"))
      (node (ref "R31") (pin "2") (pinfunction "2_2") (pintype "passive"))
      (node (ref "R83") (pin "2") (pinfunction "2_2") (pintype "passive"))
      (node (ref "R84") (pin "2") (pinfunction "2_2") (pintype "passive"))
      (node (ref "R85") (pin "2") (pinfunction "2_2") (pintype "passive"))
      (node (ref "R86") (pin "2") (pinfunction "2_2") (pintype "passive"))
      (node (ref "U10") (pin "4") (pinfunction "VDD_IO_4") (pintype "passive"))
      (node (ref "U11") (pin "4") (pinfunction "VDD_IO_4") (pintype "passive"))
      (node (ref "U12") (pin "4") (pinfunction "VDD_IO_4") (pintype "passive"))
      (node (ref "U13") (pin "4") (pinfunction "VDD_IO_4") (pintype "passive"))
      (node (ref "U14") (pin "4") (pinfunction "VDD_IO_4") (pintype "passive"))
      (node (ref "U15") (pin "4") (pinfunction "VDD_IO_4") (pintype "passive"))
      (node (ref "U16") (pin "4") (pinfunction "VDD_IO_4") (pintype "passive"))
      (node (ref "U17") (pin "4") (pinfunction "VDD_IO_4") (pintype "passive"))
      (node (ref "U18") (pin "4") (pinfunction "VDD_IO_4") (pintype "passive"))
      (node (ref "U2") (pin "4") (pinfunction "VDD_IO_4") (pintype "passive"))
      (node (ref "U24") (pin "1") (pinfunction "OUTPUT_1") (pintype "passive"))
      (node (ref "U3") (pin "4") (pinfunction "VDD_IO_4") (pintype "passive"))
      (node (ref "U4") (pin "4") (pinfunction "VDD_IO_4") (pintype "passive"))
      (node (ref "U5") (pin "4") (pinfunction "VDD_IO_4") (pintype "passive"))
      (node (ref "U7") (pin "4") (pinfunction "VDD_IO_4") (pintype "passive"))
      (node (ref "U8") (pin "4") (pinfunction "VDD_IO_4") (pintype "passive"))
      (node (ref "U9") (pin "4") (pinfunction "VDD_IO_4") (pintype "passive"))
    )
    (net (code "19") (name "/3.3V") (class "Default")
      (node (ref "C211") (pin "1") (pinfunction "1_1") (pintype "passive"))
      (node (ref "C229") (pin "1") (pinfunction "1_1") (pintype "passive"))
      (node (ref "C233") (pin "1") (pinfunction "1_1") (pintype "passive"))
      (node (ref "C234") (pin "1") (pinfunction "1_1") (pintype "passive"))
      (node (ref "C237") (pin "1") (pinfunction "1_1") (pintype "passive"))
      (node (ref "C248") (pin "1") (pinfunction "1_1") (pintype "passive"))
      (node (ref "C249") (pin "1") (pinfunction "1_1") (pintype "passive"))
      (node (ref "C250") (pin "1") (pinfunction "1_1") (pintype "passive"))
      (node (ref "C34") (pin "1") (pinfunction "1_1") (pintype "passive"))
      (node (ref "C63") (pin "1") (pinfunction "1_1") (pintype "passive"))
      (node (ref "C73") (pin "1") (pinfunction "1_1") (pintype "passive"))
      (node (ref "C74") (pin "1") (pinfunction "1_1") (pintype "passive"))
      (node (ref "C75") (pin "1") (pinfunction "1_1") (pintype "passive"))
      (node (ref "C76") (pin "1") (pinfunction "1_1") (pintype "passive"))
      (node (ref "J1") (pin "2") (pinfunction "2_2") (pintype "passive"))
      (node (ref "R1") (pin "2") (pinfunction "2_2") (pintype "passive"))
      (node (ref "R12") (pin "1") (pinfunction "1_1") (pintype "passive"))
      (node (ref "R16") (pin "1") (pinfunction "1_1") (pintype "passive"))
      (node (ref "R18") (pin "1") (pinfunction "1_1") (pintype "passive"))
      (node (ref "R7") (pin "1") (pinfunction "1_1") (pintype "passive"))
      (node (ref "R9") (pin "2") (pinfunction "2_2") (pintype "passive"))
      (node (ref "U1") (pin "10") (pinfunction "VDD_10") (pintype "passive"))
      (node (ref "U1") (pin "19") (pinfunction "AVDD_19") (pintype "passive"))
      (node (ref "U1") (pin "26") (pinfunction "VDD_26") (pintype "passive"))
      (node (ref "U1") (pin "35") (pinfunction "VUSB3V3_35") (pintype "passive"))
      (node (ref "U1") (pin "38") (pinfunction "VDD_38") (pintype "passive"))
      (node (ref "U1") (pin "57") (pinfunction "VDD_57") (pintype "passive"))
      (node (ref "U19") (pin "1") (pinfunction "OUTPUT_1") (pintype "passive"))
      (node (ref "U6") (pin "5") (pinfunction "Vout_5") (pintype "passive"))
    )
    (net (code "20") (name "/5.0V") (class "Default")
      (node (ref "C188") (pin "2") (pinfunction "2_2") (pintype "passive"))
      (node (ref "C231") (pin "1") (pinfunction "1_1") (pintype "passive"))
      (node (ref "C308") (pin "2") (pinfunction "2_2") (pintype "passive"))
      (node (ref "D1") (pin "1") (pinfunction "A1_1") (pintype "passive"))
      (node (ref "D1") (pin "2") (pinfunction "A2_2") (pintype "passive"))
      (node (ref "D2") (pin "1") (pinfunction "A1_1") (pintype "passive"))
      (node (ref "D2") (pin "2") (pinfunction "A2_2") (pintype "passive"))
      (node (ref "R42") (pin "1") (pinfunction "1_1") (pintype "passive"))
      (node (ref "R63") (pin "1") (pinfunction "1_1") (pintype "passive"))
      (node (ref "U20") (pin "3") (pinfunction "Vin_3") (pintype "passive"))
      (node (ref "U22") (pin "1") (pinfunction "OUTPUT_1") (pintype "passive"))
      (node (ref "U23") (pin "3") (pinfunction "Vin_3") (pintype "passive"))
      (node (ref "U25") (pin "7") (pinfunction "VCC_7") (pintype "passive"))
      (node (ref "U30") (pin "7") (pinfunction "VCC_7") (pintype "passive"))
    )
    (net (code "21") (name "/5.0V PS") (class "Default")
      (node (ref "J2") (pin "4") (pinfunction "4_4") (pintype "passive"))
      (node (ref "R42") (pin "2") (pinfunction "2_2") (pintype "passive"))
    )
    (net (code "22") (name "/12V") (class "Default")
      (node (ref "C190") (pin "1") (pinfunction "1_1") (pintype "passive"))
      (node (ref "C191") (pin "1") (pinfunction "1_1") (pintype "passive"))
      (node (ref "C192") (pin "1") (pinfunction "1_1") (pintype "passive"))
      (node (ref "C193") (pin "1") (pinfunction "1_1") (pintype "passive"))
      (node (ref "C195") (pin "1") (pinfunction "1_1") (pintype "passive"))
      (node (ref "C196") (pin "1") (pinfunction "1_1") (pintype "passive"))
      (node (ref "C197") (pin "1") (pinfunction "1_1") (pintype "passive"))
      (node (ref "C207") (pin "1") (pinfunction "1_1") (pintype "passive"))
      (node (ref "C208") (pin "1") (pinfunction "1_1") (pintype "passive"))
      (node (ref "C210") (pin "1") (pinfunction "1_1") (pintype "passive"))
      (node (ref "C213") (pin "1") (pinfunction "1_1") (pintype "passive"))
      (node (ref "C214") (pin "1") (pinfunction "1_1") (pintype "passive"))
      (node (ref "C215") (pin "1") (pinfunction "1_1") (pintype "passive"))
      (node (ref "C216") (pin "1") (pinfunction "1_1") (pintype "passive"))
      (node (ref "C217") (pin "1") (pinfunction "1_1") (pintype "passive"))
      (node (ref "C218") (pin "1") (pinfunction "1_1") (pintype "passive"))
      (node (ref "C219") (pin "1") (pinfunction "1_1") (pintype "passive"))
      (node (ref "C263") (pin "1") (pinfunction "1_1") (pintype "passive"))
      (node (ref "C264") (pin "1") (pinfunction "1_1") (pintype "passive"))
      (node (ref "C265") (pin "1") (pinfunction "1_1") (pintype "passive"))
      (node (ref "C266") (pin "1") (pinfunction "1_1") (pintype "passive"))
      (node (ref "C267") (pin "1") (pinfunction "1_1") (pintype "passive"))
      (node (ref "C268") (pin "1") (pinfunction "1_1") (pintype "passive"))
      (node (ref "C269") (pin "1") (pinfunction "1_1") (pintype "passive"))
      (node (ref "C270") (pin "1") (pinfunction "1_1") (pintype "passive"))
      (node (ref "C272") (pin "1") (pinfunction "1_1") (pintype "passive"))
      (node (ref "C273") (pin "1") (pinfunction "1_1") (pintype "passive"))
      (node (ref "C274") (pin "1") (pinfunction "1_1") (pintype "passive"))
      (node (ref "C275") (pin "1") (pinfunction "1_1") (pintype "passive"))
      (node (ref "C276") (pin "1") (pinfunction "1_1") (pintype "passive"))
      (node (ref "C277") (pin "1") (pinfunction "1_1") (pintype "passive"))
      (node (ref "C278") (pin "1") (pinfunction "1_1") (pintype "passive"))
      (node (ref "C279") (pin "1") (pinfunction "1_1") (pintype "passive"))
      (node (ref "C280") (pin "1") (pinfunction "1_1") (pintype "passive"))
      (node (ref "C281") (pin "1") (pinfunction "1_1") (pintype "passive"))
      (node (ref "C489") (pin "1") (pinfunction "1_1") (pintype "passive"))
      (node (ref "C491") (pin "1") (pinfunction "1_1") (pintype "passive"))
      (node (ref "C493") (pin "1") (pinfunction "1_1") (pintype "passive"))
      (node (ref "C494") (pin "1") (pinfunction "1_1") (pintype "passive"))
      (node (ref "C495") (pin "1") (pinfunction "1_1") (pintype "passive"))
      (node (ref "C501") (pin "1") (pinfunction "1_1") (pintype "passive"))
      (node (ref "J2") (pin "1") (pinfunction "1_1") (pintype "passive"))
      (node (ref "J6") (pin "2") (pinfunction "2_2") (pintype "passive"))
      (node (ref "Q1") (pin "5") (pinfunction "D_5") (pintype "passive"))
      (node (ref "Q1") (pin "6") (pinfunction "D_6") (pintype "passive"))
      (node (ref "Q1") (pin "7") (pinfunction "D_7") (pintype "passive"))
      (node (ref "Q1") (pin "8") (pinfunction "D_8") (pintype "passive"))
      (node (ref "Q4") (pin "5") (pinfunction "D_5") (pintype "passive"))
      (node (ref "Q4") (pin "6") (pinfunction "D_6") (pintype "passive"))
      (node (ref "Q4") (pin "7") (pinfunction "D_7") (pintype "passive"))
      (node (ref "Q4") (pin "8") (pinfunction "D_8") (pintype "passive"))
      (node (ref "R57") (pin "1") (pinfunction "1_1") (pintype "passive"))
      (node (ref "U20") (pin "1") (pinfunction "Vout_1") (pintype "passive"))
      (node (ref "U22") (pin "8") (pinfunction "INPUT_8") (pintype "passive"))
      (node (ref "U23") (pin "1") (pinfunction "Vout_1") (pintype "passive"))
    )
    (net (code "23") (name "/BOOT3") (class "Default")
      (node (ref "C312") (pin "1") (pinfunction "1_1") (pintype "passive"))
      (node (ref "D2") (pin "3") (pinfunction "CC_3") (pintype "passive"))
      (node (ref "U30") (pin "8") (pinfunction "BOOT_8") (pintype "passive"))
    )
    (net (code "24") (name "/BOOT4") (class "Default")
      (node (ref "C189") (pin "1") (pinfunction "1_1") (pintype "passive"))
      (node (ref "D1") (pin "3") (pinfunction "CC_3") (pintype "passive"))
      (node (ref "U25") (pin "8") (pinfunction "BOOT_8") (pintype "passive"))
    )
    (net (code "25") (name "/C1Rx") (class "Default")
      (node (ref "U1") (pin "58") (pinfunction "VCMPST1/RP96/RF0_58") (pintype "passive"))
      (node (ref "U21") (pin "4") (pinfunction "Rx_4") (pintype "passive"))
    )
    (net (code "26") (name "/C1Tx") (class "Default")
      (node (ref "U1") (pin "59") (pinfunction "VCMPST2/RP97/RF1_59") (pintype "passive"))
      (node (ref "U21") (pin "1") (pinfunction "Tx_1") (pintype "passive"))
    )
    (net (code "27") (name "/CAN5.0V") (class "Default")
      (node (ref "C255") (pin "1") (pinfunction "1_1") (pintype "passive"))
      (node (ref "R47") (pin "1") (pinfunction "1_1") (pintype "passive"))
      (node (ref "R64") (pin "1") (pinfunction "1_1") (pintype "passive"))
      (node (ref "U21") (pin "2") (pinfunction "GND_2") (pintype "passive"))
    )
    (net (code "28") (name "/CANH") (class "Default")
      (node (ref "J4") (pin "1") (pinfunction "1_1") (pintype "passive"))
      (node (ref "J5") (pin "2") (pinfunction "2_2") (pintype "passive"))
      (node (ref "U21") (pin "7") (pinfunction "CANH_7") (pintype "passive"))
    )
    (net (code "29") (name "/CANL") (class "Default")
      (node (ref "J5") (pin "1") (pinfunction "1_1") (pintype "passive"))
      (node (ref "R41") (pin "2") (pinfunction "2_2") (pintype "passive"))
      (node (ref "U21") (pin "6") (pinfunction "CANL_6") (pintype "passive"))
    )
    (net (code "30") (name "/CLK0") (class "Default")
      (node (ref "U2") (pin "5") (pinfunction "OUTCLK_5") (pintype "passive"))
    )
    (net (code "31") (name "/CLK1") (class "Default")
      (node (ref "U3") (pin "5") (pinfunction "OUTCLK_5") (pintype "passive"))
    )
    (net (code "32") (name "/CLK2") (class "Default")
      (node (ref "U4") (pin "5") (pinfunction "OUTCLK_5") (pintype "passive"))
    )
    (net (code "33") (name "/CLK3") (class "Default")
      (node (ref "U5") (pin "5") (pinfunction "OUTCLK_5") (pintype "passive"))
    )
    (net (code "34") (name "/CLK4") (class "Default")
      (node (ref "U7") (pin "5") (pinfunction "OUTCLK_5") (pintype "passive"))
    )
    (net (code "35") (name "/CLK5") (class "Default")
      (node (ref "U8") (pin "5") (pinfunction "OUTCLK_5") (pintype "passive"))
    )
    (net (code "36") (name "/CLK6") (class "Default")
      (node (ref "U9") (pin "5") (pinfunction "OUTCLK_5") (pintype "passive"))
    )
    (net (code "37") (name "/CLK7") (class "Default")
      (node (ref "U10") (pin "5") (pinfunction "OUTCLK_5") (pintype "passive"))
    )
    (net (code "38") (name "/CLK8") (class "Default")
      (node (ref "U11") (pin "5") (pinfunction "OUTCLK_5") (pintype "passive"))
    )
    (net (code "39") (name "/CLK9") (class "Default")
      (node (ref "U12") (pin "5") (pinfunction "OUTCLK_5") (pintype "passive"))
    )
    (net (code "40") (name "/CLK10") (class "Default")
      (node (ref "U13") (pin "5") (pinfunction "OUTCLK_5") (pintype "passive"))
    )
    (net (code "41") (name "/CLK11") (class "Default")
      (node (ref "U14") (pin "5") (pinfunction "OUTCLK_5") (pintype "passive"))
    )
    (net (code "42") (name "/CLK12") (class "Default")
      (node (ref "U15") (pin "5") (pinfunction "OUTCLK_5") (pintype "passive"))
    )
    (net (code "43") (name "/CLK13") (class "Default")
      (node (ref "U16") (pin "5") (pinfunction "OUTCLK_5") (pintype "passive"))
    )
    (net (code "44") (name "/CLK14") (class "Default")
      (node (ref "U17") (pin "5") (pinfunction "OUTCLK_5") (pintype "passive"))
    )
    (net (code "45") (name "/CLK15") (class "Default")
      (node (ref "U18") (pin "5") (pinfunction "OUTCLK_5") (pintype "passive"))
    )
    (net (code "46") (name "/CONFIG_N1") (class "Default")
      (node (ref "U1") (pin "42") (pinfunction "RTCC/DMLN/RPI72/RD8_42") (pintype "passive"))
    )
    (net (code "47") (name "/CONFIG_P1") (class "Default")
      (node (ref "U1") (pin "43") (pinfunction "ASDA1/DPLN/RPI73/RD9_43") (pintype "passive"))
    )
    (net (code "48") (name "/CSN4") (class "Default")
      (node (ref "R38") (pin "1") (pinfunction "1_1") (pintype "passive"))
      (node (ref "U1") (pin "14") (pinfunction "AN2/C2IN2-/VMIO/RPI34/RB2_14") (pintype "passive"))
    )
    (net (code "49") (name "/CSP4") (class "Default")
      (node (ref "R37") (pin "1") (pinfunction "1_1") (pintype "passive"))
      (node (ref "U1") (pin "13") (pinfunction "AN3/C2IN1+/VPIO/RPI35/RB3_13") (pintype "passive"))
    )
    (net (code "50") (name "/D+") (class "Default")
      (node (ref "C254") (pin "2") (pinfunction "2_2") (pintype "passive"))
      (node (ref "R35") (pin "2") (pinfunction "2_2") (pintype "passive"))
      (node (ref "U1") (pin "37") (pinfunction "D+/RG2_37") (pintype "passive"))
    )
    (net (code "51") (name "/D-") (class "Default")
      (node (ref "C253") (pin "2") (pinfunction "2_2") (pintype "passive"))
      (node (ref "R34") (pin "2") (pinfunction "2_2") (pintype "passive"))
      (node (ref "U1") (pin "36") (pinfunction "D-/RG3_36") (pintype "passive"))
    )
    (net (code "52") (name "/FAN5.0V") (class "Default")
      (node (ref "R63") (pin "2") (pinfunction "2_2") (pintype "passive"))
      (node (ref "R64") (pin "2") (pinfunction "2_2") (pintype "passive"))
    )
    (net (code "53") (name "/FB") (class "Default")
      (node (ref "C251") (pin "1") (pinfunction "1_1") (pintype "passive"))
      (node (ref "R43") (pin "1") (pinfunction "1_1") (pintype "passive"))
      (node (ref "U1") (pin "17") (pinfunction "PGEC1/AN6/RPI38/RB6_17") (pintype "passive"))
    )
    (net (code "54") (name "/GREEN") (class "Default")
      (node (ref "D5") (pin "2") (pinfunction "A_2") (pintype "passive"))
      (node (ref "U1") (pin "62") (pinfunction "AN26/PWM2L/PMD2/RP82/RE2_62") (pintype "passive"))
    )
    (net (code "55") (name "/HO3") (class "Default")
      (node (ref "Q4") (pin "4") (pinfunction "G_4") (pintype "passive"))
      (node (ref "U30") (pin "1") (pinfunction "HO_1") (pintype "passive"))
    )
    (net (code "56") (name "/HO4") (class "Default")
      (node (ref "Q1") (pin "4") (pinfunction "G_4") (pintype "passive"))
      (node (ref "U25") (pin "1") (pinfunction "HO_1") (pintype "passive"))
    )
    (net (code "57") (name "/LDO3.3V-5.0V") (class "Default")
      (node (ref "R12") (pin "2") (pinfunction "2_2") (pintype "passive"))
      (node (ref "R13") (pin "1") (pinfunction "1_1") (pintype "passive"))
      (node (ref "U24") (pin "5") (pinfunction "N.C._5") (pintype "passive"))
      (node (ref "U24") (pin "8") (pinfunction "INPUT_8") (pintype "passive"))
    )
    (net (code "58") (name "/LDO5.0V") (class "Default")
      (node (ref "C187") (pin "1") (pinfunction "1_1") (pintype "passive"))
      (node (ref "R13") (pin "2") (pinfunction "2_2") (pintype "passive"))
      (node (ref "R46") (pin "1") (pinfunction "1_1") (pintype "passive"))
      (node (ref "R47") (pin "2") (pinfunction "2_2") (pintype "passive"))
      (node (ref "R62") (pin "2") (pinfunction "2_2") (pintype "passive"))
      (node (ref "U19") (pin "5") (pinfunction "N.C._5") (pintype "passive"))
      (node (ref "U19") (pin "8") (pinfunction "INPUT_8") (pintype "passive"))
      (node (ref "U6") (pin "1") (pinfunction "Vin_1") (pintype "passive"))
      (node (ref "U6") (pin "3") (pinfunction "STBY_3") (pintype "passive"))
    )
    (net (code "59") (name "/LMGND") (class "Default")
      (node (ref "D3") (pin "3") (pinfunction "CC_3") (pintype "passive"))
      (node (ref "R60") (pin "2") (pinfunction "2_2") (pintype "passive"))
      (node (ref "U20") (pin "2") (pinfunction "GND_2") (pintype "passive"))
      (node (ref "U22") (pin "2") (pinfunction "GND_2") (pintype "passive"))
      (node (ref "U22") (pin "3") (pinfunction "GND_3") (pintype "passive"))
      (node (ref "U22") (pin "4") (pinfunction "N.C._4") (pintype "passive"))
      (node (ref "U22") (pin "5") (pinfunction "N.C._5") (pintype "passive"))
      (node (ref "U22") (pin "6") (pinfunction "GND_6") (pintype "passive"))
      (node (ref "U22") (pin "7") (pinfunction "GND_7") (pintype "passive"))
      (node (ref "U23") (pin "2") (pinfunction "GND_2") (pintype "passive"))
    )
    (net (code "60") (name "/LO3") (class "Default")
      (node (ref "Q5") (pin "4") (pinfunction "G_4") (pintype "passive"))
      (node (ref "Q6") (pin "4") (pinfunction "G_4") (pintype "passive"))
      (node (ref "U30") (pin "3") (pinfunction "LO_3") (pintype "passive"))
    )
    (net (code "61") (name "/LO4") (class "Default")
      (node (ref "Q2") (pin "4") (pinfunction "G_4") (pintype "passive"))
      (node (ref "Q3") (pin "4") (pinfunction "G_4") (pintype "passive"))
      (node (ref "U25") (pin "3") (pinfunction "LO_3") (pintype "passive"))
    )
    (net (code "62") (name "/MCLR") (class "Default")
      (node (ref "C72") (pin "1") (pinfunction "1_1") (pintype "passive"))
      (node (ref "J1") (pin "1") (pinfunction "1_1") (pintype "passive"))
      (node (ref "R9") (pin "1") (pinfunction "1_1") (pintype "passive"))
      (node (ref "U1") (pin "7") (pinfunction "MCLR_7") (pintype "passive"))
    )
    (net (code "63") (name "/MCU_MISO0") (class "Default")
      (node (ref "Q7") (pin "3") (pinfunction "C_3") (pintype "passive"))
      (node (ref "R1") (pin "1") (pinfunction "1_1") (pintype "passive"))
      (node (ref "U1") (pin "5") (pinfunction "C1IN1-/SDI2/PMA4/RPI119/RG7_5") (pintype "passive"))
    )
    (net (code "64") (name "/MCU_MISO1") (class "Default")
      (node (ref "Q8") (pin "3") (pinfunction "C_3") (pintype "passive"))
      (node (ref "R7") (pin "2") (pinfunction "2_2") (pintype "passive"))
      (node (ref "U1") (pin "50") (pinfunction "DPH/RP66/RD2_50") (pintype "passive"))
    )
    (net (code "65") (name "/MCU_MOSI0") (class "Default")
      (node (ref "R3") (pin "2") (pinfunction "2_2") (pintype "passive"))
      (node (ref "U1") (pin "6") (pinfunction "C2IN3-/SDO2/PMA3/RP120/RG8_6") (pintype "passive"))
    )
    (net (code "66") (name "/MCU_MOSI1") (class "Default")
      (node (ref "R10") (pin "2") (pinfunction "2_2") (pintype "passive"))
      (node (ref "U1") (pin "49") (pinfunction "VCPCON/RP65/RD1_49") (pintype "passive"))
    )
    (net (code "67") (name "/MCU_SCK0") (class "Default")
      (node (ref "R5") (pin "2") (pinfunction "2_2") (pintype "passive"))
      (node (ref "U1") (pin "4") (pinfunction "C1IN3-/SCK2/PMA5/RP118/RG6_4") (pintype "passive"))
    )
    (net (code "68") (name "/MCU_SCK1") (class "Default")
      (node (ref "R11") (pin "2") (pinfunction "2_2") (pintype "passive"))
      (node (ref "U1") (pin "51") (pinfunction "PMBE/RP67/RD3_51") (pintype "passive"))
    )
    (net (code "69") (name "/MEAS12") (class "Default")
      (node (ref "C325") (pin "1") (pinfunction "1_1") (pintype "passive"))
      (node (ref "R57") (pin "2") (pinfunction "2_2") (pintype "passive"))
      (node (ref "R61") (pin "2") (pinfunction "2_2") (pintype "passive"))
      (node (ref "U1") (pin "18") (pinfunction "PGED1/AN7/RCV/RPI39/RB7_18") (pintype "passive"))
    )
    (net (code "70") (name "/Main OSC In") (class "Default")
      (node (ref "C85") (pin "1") (pinfunction "1_1") (pintype "passive"))
      (node (ref "U1") (pin "39") (pinfunction "OSC1/RPI60/RC12_39") (pintype "passive"))
      (node (ref "Y1") (pin "1") (pinfunction "1_1") (pintype "passive"))
    )
    (net (code "71") (name "/Main OSC Out") (class "Default")
      (node (ref "C86") (pin "1") (pinfunction "1_1") (pintype "passive"))
      (node (ref "U1") (pin "40") (pinfunction "OSC2/CLKO/RC15_40") (pintype "passive"))
      (node (ref "Y1") (pin "2") (pinfunction "2_2") (pintype "passive"))
    )
    (net (code "72") (name "/ORANGE") (class "Default")
      (node (ref "D7") (pin "2") (pinfunction "A_2") (pintype "passive"))
      (node (ref "U1") (pin "45") (pinfunction "PMCS1/RPI75/RD11_45") (pintype "passive"))
    )
    (net (code "73") (name "/PGC") (class "Default")
      (node (ref "J1") (pin "5") (pinfunction "5_5") (pintype "passive"))
      (node (ref "U1") (pin "15") (pinfunction "PGEC3/AN1/VREF-/RPI33/RB1_15") (pintype "passive"))
    )
    (net (code "74") (name "/PGD") (class "Default")
      (node (ref "J1") (pin "4") (pinfunction "4_4") (pintype "passive"))
      (node (ref "U1") (pin "16") (pinfunction "PGED3/AN0/VREF+/RPI32/RB0_16") (pintype "passive"))
    )
    (net (code "75") (name "/PWM") (class "Default")
      (node (ref "J6") (pin "4") (pinfunction "4_4") (pintype "passive"))
      (node (ref "U1") (pin "61") (pinfunction "AN25/PWM1H/PMD1/RPI81/RE1_61") (pintype "passive"))
    )
    (net (code "76") (name "/PWM3H") (class "Default")
      (node (ref "R59") (pin "2") (pinfunction "2_2") (pintype "passive"))
      (node (ref "U1") (pin "1") (pinfunction "AN29/PWM3H/PMD5/RP85/RE5_1") (pintype "passive"))
      (node (ref "U30") (pin "5") (pinfunction "IN_5") (pintype "passive"))
    )
    (net (code "77") (name "/PWM3L") (class "Default")
      (node (ref "C311") (pin "1") (pinfunction "1_1") (pintype "passive"))
      (node (ref "R14") (pin "2") (pinfunction "2_2") (pintype "passive"))
      (node (ref "R18") (pin "2") (pinfunction "2_2") (pintype "passive"))
      (node (ref "U1") (pin "64") (pinfunction "AN28/PWM3L/PMD4/RP84/RE4_64") (pintype "passive"))
      (node (ref "U30") (pin "6") (pinfunction "Vlogic_6") (pintype "passive"))
    )
    (net (code "78") (name "/PWM4H") (class "Default")
      (node (ref "R40") (pin "2") (pinfunction "2_2") (pintype "passive"))
      (node (ref "U1") (pin "3") (pinfunction "AN31/PWM4H/PMD7/RP87/RE7_3") (pintype "passive"))
      (node (ref "U25") (pin "5") (pinfunction "IN_5") (pintype "passive"))
    )
    (net (code "79") (name "/PWM4L") (class "Default")
      (node (ref "C252") (pin "1") (pinfunction "1_1") (pintype "passive"))
      (node (ref "R15") (pin "2") (pinfunction "2_2") (pintype "passive"))
      (node (ref "R16") (pin "2") (pinfunction "2_2") (pintype "passive"))
      (node (ref "U1") (pin "2") (pinfunction "AN30/PWM4L/PMD6/RPI86/RE6_2") (pintype "passive"))
      (node (ref "U25") (pin "6") (pinfunction "Vlogic_6") (pintype "passive"))
    )
    (net (code "80") (name "/RED") (class "Default")
      (node (ref "D4") (pin "2") (pinfunction "A_2") (pintype "passive"))
      (node (ref "U1") (pin "63") (pinfunction "AN27/PWM2H/PMD3/RPI83/RE3_63") (pintype "passive"))
    )
    (net (code "81") (name "/RPM") (class "Default")
      (node (ref "R44") (pin "1") (pinfunction "1_1") (pintype "passive"))
      (node (ref "R45") (pin "2") (pinfunction "2_2") (pintype "passive"))
      (node (ref "U1") (pin "60") (pinfunction "AN24/PWM1L/PMD0/RP80/RE0_60") (pintype "passive"))
    )
    (net (code "82") (name "/RPMF") (class "Default")
      (node (ref "J6") (pin "3") (pinfunction "3_3") (pintype "passive"))
      (node (ref "R44") (pin "2") (pinfunction "2_2") (pintype "passive"))
    )
    (net (code "83") (name "/SPI_MISO0") (class "Default")
      (node (ref "R2") (pin "1") (pinfunction "1_1") (pintype "passive"))
      (node (ref "R8") (pin "1") (pinfunction "1_1") (pintype "passive"))
      (node (ref "U2") (pin "9") (pinfunction "INMISO_9") (pintype "passive"))
    )
    (net (code "84") (name "/SPI_MISO1") (class "Default")
      (node (ref "U2") (pin "8") (pinfunction "OUTMISO_8") (pintype "passive"))
      (node (ref "U3") (pin "9") (pinfunction "INMISO_9") (pintype "passive"))
    )
    (net (code "85") (name "/SPI_MISO2") (class "Default")
      (node (ref "U3") (pin "8") (pinfunction "OUTMISO_8") (pintype "passive"))
      (node (ref "U4") (pin "9") (pinfunction "INMISO_9") (pintype "passive"))
    )
    (net (code "86") (name "/SPI_MISO3") (class "Default")
      (node (ref "U4") (pin "8") (pinfunction "OUTMISO_8") (pintype "passive"))
      (node (ref "U5") (pin "9") (pinfunction "INMISO_9") (pintype "passive"))
    )
    (net (code "87") (name "/SPI_MISO4") (class "Default")
      (node (ref "U5") (pin "8") (pinfunction "OUTMISO_8") (pintype "passive"))
      (node (ref "U7") (pin "9") (pinfunction "INMISO_9") (pintype "passive"))
    )
    (net (code "88") (name "/SPI_MISO5") (class "Default")
      (node (ref "U7") (pin "8") (pinfunction "OUTMISO_8") (pintype "passive"))
      (node (ref "U8") (pin "9") (pinfunction "INMISO_9") (pintype "passive"))
    )
    (net (code "89") (name "/SPI_MISO6") (class "Default")
      (node (ref "U8") (pin "8") (pinfunction "OUTMISO_8") (pintype "passive"))
      (node (ref "U9") (pin "9") (pinfunction "INMISO_9") (pintype "passive"))
    )
    (net (code "90") (name "/SPI_MISO7") (class "Default")
      (node (ref "U10") (pin "9") (pinfunction "INMISO_9") (pintype "passive"))
      (node (ref "U9") (pin "8") (pinfunction "OUTMISO_8") (pintype "passive"))
    )
    (net (code "91") (name "/SPI_MISO8") (class "Default")
      (node (ref "U10") (pin "8") (pinfunction "OUTMISO_8") (pintype "passive"))
      (node (ref "U11") (pin "9") (pinfunction "INMISO_9") (pintype "passive"))
    )
    (net (code "92") (name "/SPI_MISO9") (class "Default")
      (node (ref "U11") (pin "8") (pinfunction "OUTMISO_8") (pintype "passive"))
      (node (ref "U12") (pin "9") (pinfunction "INMISO_9") (pintype "passive"))
    )
    (net (code "93") (name "/SPI_MISO10") (class "Default")
      (node (ref "U12") (pin "8") (pinfunction "OUTMISO_8") (pintype "passive"))
      (node (ref "U13") (pin "9") (pinfunction "INMISO_9") (pintype "passive"))
    )
    (net (code "94") (name "/SPI_MISO11") (class "Default")
      (node (ref "U13") (pin "8") (pinfunction "OUTMISO_8") (pintype "passive"))
      (node (ref "U14") (pin "9") (pinfunction "INMISO_9") (pintype "passive"))
    )
    (net (code "95") (name "/SPI_MISO12") (class "Default")
      (node (ref "U14") (pin "8") (pinfunction "OUTMISO_8") (pintype "passive"))
      (node (ref "U15") (pin "9") (pinfunction "INMISO_9") (pintype "passive"))
    )
    (net (code "96") (name "/SPI_MISO13") (class "Default")
      (node (ref "U15") (pin "8") (pinfunction "OUTMISO_8") (pintype "passive"))
      (node (ref "U16") (pin "9") (pinfunction "INMISO_9") (pintype "passive"))
    )
    (net (code "97") (name "/SPI_MISO14") (class "Default")
      (node (ref "U16") (pin "8") (pinfunction "OUTMISO_8") (pintype "passive"))
      (node (ref "U17") (pin "9") (pinfunction "INMISO_9") (pintype "passive"))
    )
    (net (code "98") (name "/SPI_MISO15") (class "Default")
      (node (ref "U17") (pin "8") (pinfunction "OUTMISO_8") (pintype "passive"))
      (node (ref "U18") (pin "9") (pinfunction "INMISO_9") (pintype "passive"))
    )
    (net (code "99") (name "/SPI_MISO16") (class "Default")
      (node (ref "U18") (pin "8") (pinfunction "OUTMISO_8") (pintype "passive"))
    )
    (net (code "100") (name "/SPI_MOSI0") (class "Default")
      (node (ref "R10") (pin "1") (pinfunction "1_1") (pintype "passive"))
      (node (ref "R3") (pin "1") (pinfunction "1_1") (pintype "passive"))
      (node (ref "R4") (pin "2") (pinfunction "2_2") (pintype "passive"))
      (node (ref "U2") (pin "10") (pinfunction "INMOSI_10") (pintype "passive"))
    )
    (net (code "101") (name "/SPI_MOSI1") (class "Default")
      (node (ref "U2") (pin "7") (pinfunction "OUTMOSI_7") (pintype "passive"))
      (node (ref "U3") (pin "10") (pinfunction "INMOSI_10") (pintype "passive"))
    )
    (net (code "102") (name "/SPI_MOSI2") (class "Default")
      (node (ref "U3") (pin "7") (pinfunction "OUTMOSI_7") (pintype "passive"))
      (node (ref "U4") (pin "10") (pinfunction "INMOSI_10") (pintype "passive"))
    )
    (net (code "103") (name "/SPI_MOSI3") (class "Default")
      (node (ref "U4") (pin "7") (pinfunction "OUTMOSI_7") (pintype "passive"))
      (node (ref "U5") (pin "10") (pinfunction "INMOSI_10") (pintype "passive"))
    )
    (net (code "104") (name "/SPI_MOSI4") (class "Default")
      (node (ref "U5") (pin "7") (pinfunction "OUTMOSI_7") (pintype "passive"))
      (node (ref "U7") (pin "10") (pinfunction "INMOSI_10") (pintype "passive"))
    )
    (net (code "105") (name "/SPI_MOSI5") (class "Default")
      (node (ref "U7") (pin "7") (pinfunction "OUTMOSI_7") (pintype "passive"))
      (node (ref "U8") (pin "10") (pinfunction "INMOSI_10") (pintype "passive"))
    )
    (net (code "106") (name "/SPI_MOSI6") (class "Default")
      (node (ref "U8") (pin "7") (pinfunction "OUTMOSI_7") (pintype "passive"))
      (node (ref "U9") (pin "10") (pinfunction "INMOSI_10") (pintype "passive"))
    )
    (net (code "107") (name "/SPI_MOSI7") (class "Default")
      (node (ref "U10") (pin "10") (pinfunction "INMOSI_10") (pintype "passive"))
      (node (ref "U9") (pin "7") (pinfunction "OUTMOSI_7") (pintype "passive"))
    )
    (net (code "108") (name "/SPI_MOSI8") (class "Default")
      (node (ref "U10") (pin "7") (pinfunction "OUTMOSI_7") (pintype "passive"))
      (node (ref "U11") (pin "10") (pinfunction "INMOSI_10") (pintype "passive"))
    )
    (net (code "109") (name "/SPI_MOSI9") (class "Default")
      (node (ref "U11") (pin "7") (pinfunction "OUTMOSI_7") (pintype "passive"))
      (node (ref "U12") (pin "10") (pinfunction "INMOSI_10") (pintype "passive"))
    )
    (net (code "110") (name "/SPI_MOSI10") (class "Default")
      (node (ref "U12") (pin "7") (pinfunction "OUTMOSI_7") (pintype "passive"))
      (node (ref "U13") (pin "10") (pinfunction "INMOSI_10") (pintype "passive"))
    )
    (net (code "111") (name "/SPI_MOSI11") (class "Default")
      (node (ref "U13") (pin "7") (pinfunction "OUTMOSI_7") (pintype "passive"))
      (node (ref "U14") (pin "10") (pinfunction "INMOSI_10") (pintype "passive"))
    )
    (net (code "112") (name "/SPI_MOSI12") (class "Default")
      (node (ref "U14") (pin "7") (pinfunction "OUTMOSI_7") (pintype "passive"))
      (node (ref "U15") (pin "10") (pinfunction "INMOSI_10") (pintype "passive"))
    )
    (net (code "113") (name "/SPI_MOSI13") (class "Default")
      (node (ref "U15") (pin "7") (pinfunction "OUTMOSI_7") (pintype "passive"))
      (node (ref "U16") (pin "10") (pinfunction "INMOSI_10") (pintype "passive"))
    )
    (net (code "114") (name "/SPI_MOSI14") (class "Default")
      (node (ref "U16") (pin "7") (pinfunction "OUTMOSI_7") (pintype "passive"))
      (node (ref "U17") (pin "10") (pinfunction "INMOSI_10") (pintype "passive"))
    )
    (net (code "115") (name "/SPI_MOSI15") (class "Default")
      (node (ref "U17") (pin "7") (pinfunction "OUTMOSI_7") (pintype "passive"))
      (node (ref "U18") (pin "10") (pinfunction "INMOSI_10") (pintype "passive"))
    )
    (net (code "116") (name "/SPI_MOSI16") (class "Default")
      (node (ref "R17") (pin "1") (pinfunction "1_1") (pintype "passive"))
      (node (ref "U18") (pin "7") (pinfunction "OUTMOSI_7") (pintype "passive"))
    )
    (net (code "117") (name "/SPI_SCK0") (class "Default")
      (node (ref "R11") (pin "1") (pinfunction "1_1") (pintype "passive"))
      (node (ref "R5") (pin "1") (pinfunction "1_1") (pintype "passive"))
      (node (ref "R6") (pin "2") (pinfunction "2_2") (pintype "passive"))
      (node (ref "U2") (pin "11") (pinfunction "INSCK_11") (pintype "passive"))
    )
    (net (code "118") (name "/SPI_SCK1") (class "Default")
      (node (ref "U2") (pin "6") (pinfunction "OUTSCK_6") (pintype "passive"))
      (node (ref "U3") (pin "11") (pinfunction "INSCK_11") (pintype "passive"))
    )
    (net (code "119") (name "/SPI_SCK2") (class "Default")
      (node (ref "U3") (pin "6") (pinfunction "OUTSCK_6") (pintype "passive"))
      (node (ref "U4") (pin "11") (pinfunction "INSCK_11") (pintype "passive"))
    )
    (net (code "120") (name "/SPI_SCK3") (class "Default")
      (node (ref "U4") (pin "6") (pinfunction "OUTSCK_6") (pintype "passive"))
      (node (ref "U5") (pin "11") (pinfunction "INSCK_11") (pintype "passive"))
    )
    (net (code "121") (name "/SPI_SCK4") (class "Default")
      (node (ref "U5") (pin "6") (pinfunction "OUTSCK_6") (pintype "passive"))
      (node (ref "U7") (pin "11") (pinfunction "INSCK_11") (pintype "passive"))
    )
    (net (code "122") (name "/SPI_SCK5") (class "Default")
      (node (ref "U7") (pin "6") (pinfunction "OUTSCK_6") (pintype "passive"))
      (node (ref "U8") (pin "11") (pinfunction "INSCK_11") (pintype "passive"))
    )
    (net (code "123") (name "/SPI_SCK6") (class "Default")
      (node (ref "U8") (pin "6") (pinfunction "OUTSCK_6") (pintype "passive"))
      (node (ref "U9") (pin "11") (pinfunction "INSCK_11") (pintype "passive"))
    )
    (net (code "124") (name "/SPI_SCK7") (class "Default")
      (node (ref "U10") (pin "11") (pinfunction "INSCK_11") (pintype "passive"))
      (node (ref "U9") (pin "6") (pinfunction "OUTSCK_6") (pintype "passive"))
    )
    (net (code "125") (name "/SPI_SCK8") (class "Default")
      (node (ref "U10") (pin "6") (pinfunction "OUTSCK_6") (pintype "passive"))
      (node (ref "U11") (pin "11") (pinfunction "INSCK_11") (pintype "passive"))
    )
    (net (code "126") (name "/SPI_SCK9") (class "Default")
      (node (ref "U11") (pin "6") (pinfunction "OUTSCK_6") (pintype "passive"))
      (node (ref "U12") (pin "11") (pinfunction "INSCK_11") (pintype "passive"))
    )
    (net (code "127") (name "/SPI_SCK10") (class "Default")
      (node (ref "U12") (pin "6") (pinfunction "OUTSCK_6") (pintype "passive"))
      (node (ref "U13") (pin "11") (pinfunction "INSCK_11") (pintype "passive"))
    )
    (net (code "128") (name "/SPI_SCK11") (class "Default")
      (node (ref "U13") (pin "6") (pinfunction "OUTSCK_6") (pintype "passive"))
      (node (ref "U14") (pin "11") (pinfunction "INSCK_11") (pintype "passive"))
    )
    (net (code "129") (name "/SPI_SCK12") (class "Default")
      (node (ref "U14") (pin "6") (pinfunction "OUTSCK_6") (pintype "passive"))
      (node (ref "U15") (pin "11") (pinfunction "INSCK_11") (pintype "passive"))
    )
    (net (code "130") (name "/SPI_SCK13") (class "Default")
      (node (ref "U15") (pin "6") (pinfunction "OUTSCK_6") (pintype "passive"))
      (node (ref "U16") (pin "11") (pinfunction "INSCK_11") (pintype "passive"))
    )
    (net (code "131") (name "/SPI_SCK14") (class "Default")
      (node (ref "U16") (pin "6") (pinfunction "OUTSCK_6") (pintype "passive"))
      (node (ref "U17") (pin "11") (pinfunction "INSCK_11") (pintype "passive"))
    )
    (net (code "132") (name "/SPI_SCK15") (class "Default")
      (node (ref "U17") (pin "6") (pinfunction "OUTSCK_6") (pintype "passive"))
      (node (ref "U18") (pin "11") (pinfunction "INSCK_11") (pintype "passive"))
    )
    (net (code "133") (name "/SPI_SCK16") (class "Default")
      (node (ref "U18") (pin "6") (pinfunction "OUTSCK_6") (pintype "passive"))
    )
    (net (code "134") (name "/SWN3") (class "Default")
      (node (ref "C312") (pin "2") (pinfunction "2_2") (pintype "passive"))
      (node (ref "L2") (pin "1") (pinfunction "1_1") (pintype "passive"))
      (node (ref "Q4") (pin "1") (pinfunction "S_1") (pintype "passive"))
      (node (ref "Q4") (pin "2") (pinfunction "S_2") (pintype "passive"))
      (node (ref "Q4") (pin "3") (pinfunction "S_3") (pintype "passive"))
      (node (ref "Q5") (pin "5") (pinfunction "D_5") (pintype "passive"))
      (node (ref "Q5") (pin "6") (pinfunction "D_6") (pintype "passive"))
      (node (ref "Q5") (pin "7") (pinfunction "D_7") (pintype "passive"))
      (node (ref "Q5") (pin "8") (pinfunction "D_8") (pintype "passive"))
      (node (ref "Q6") (pin "5") (pinfunction "D_5") (pintype "passive"))
      (node (ref "Q6") (pin "6") (pinfunction "D_6") (pintype "passive"))
      (node (ref "Q6") (pin "7") (pinfunction "D_7") (pintype "passive"))
      (node (ref "Q6") (pin "8") (pinfunction "D_8") (pintype "passive"))
      (node (ref "U30") (pin "2") (pinfunction "SW_2") (pintype "passive"))
    )
    (net (code "135") (name "/SWN4") (class "Default")
      (node (ref "C189") (pin "2") (pinfunction "2_2") (pintype "passive"))
      (node (ref "L1") (pin "1") (pinfunction "1_1") (pintype "passive"))
      (node (ref "Q1") (pin "1") (pinfunction "S_1") (pintype "passive"))
      (node (ref "Q1") (pin "2") (pinfunction "S_2") (pintype "passive"))
      (node (ref "Q1") (pin "3") (pinfunction "S_3") (pintype "passive"))
      (node (ref "Q2") (pin "5") (pinfunction "D_5") (pintype "passive"))
      (node (ref "Q2") (pin "6") (pinfunction "D_6") (pintype "passive"))
      (node (ref "Q2") (pin "7") (pinfunction "D_7") (pintype "passive"))
      (node (ref "Q2") (pin "8") (pinfunction "D_8") (pintype "passive"))
      (node (ref "Q3") (pin "5") (pinfunction "D_5") (pintype "passive"))
      (node (ref "Q3") (pin "6") (pinfunction "D_6") (pintype "passive"))
      (node (ref "Q3") (pin "7") (pinfunction "D_7") (pintype "passive"))
      (node (ref "Q3") (pin "8") (pinfunction "D_8") (pintype "passive"))
      (node (ref "R36") (pin "2") (pinfunction "2_2") (pintype "passive"))
      (node (ref "U25") (pin "2") (pinfunction "SW_2") (pintype "passive"))
    )
    (net (code "136") (name "/U2Rx") (class "Default")
      (node (ref "U1") (pin "31") (pinfunction "SDA2/PMA9/RP100/RF4_31") (pintype "passive"))
    )
    (net (code "137") (name "/U2Tx") (class "Default")
      (node (ref "U1") (pin "32") (pinfunction "SCL2/PMA8/RP101/RF5_32") (pintype "passive"))
    )
    (net (code "138") (name "/USB5.0V") (class "Default")
      (node (ref "J3") (pin "1") (pinfunction "1_1") (pintype "passive"))
      (node (ref "R46") (pin "2") (pinfunction "2_2") (pintype "passive"))
      (node (ref "R56") (pin "2") (pinfunction "2_2") (pintype "passive"))
    )
    (net (code "139") (name "/USBDM{slash}D-") (class "Default")
      (node (ref "J3") (pin "2") (pinfunction "2_2") (pintype "passive"))
      (node (ref "R34") (pin "1") (pinfunction "1_1") (pintype "passive"))
    )
    (net (code "140") (name "/USBDP{slash}D+") (class "Default")
      (node (ref "J3") (pin "3") (pinfunction "3_3") (pintype "passive"))
      (node (ref "R35") (pin "1") (pinfunction "1_1") (pintype "passive"))
    )
    (net (code "141") (name "/USBMCU5.0V") (class "Default")
      (node (ref "R56") (pin "1") (pinfunction "1_1") (pintype "passive"))
      (node (ref "R62") (pin "1") (pinfunction "1_1") (pintype "passive"))
      (node (ref "U1") (pin "34") (pinfunction "VBUS_34") (pintype "passive"))
    )
    (net (code "142") (name "/VCAP") (class "Default")
      (node (ref "C17") (pin "1") (pinfunction "1_1") (pintype "passive"))
      (node (ref "U1") (pin "56") (pinfunction "VCAP_56") (pintype "passive"))
    )
    (net (code "143") (name "/YELLOW") (class "Default")
      (node (ref "D6") (pin "2") (pinfunction "A_2") (pintype "passive"))
      (node (ref "U1") (pin "44") (pinfunction "ASCL1/PMCS2/RPI74/RD10_44") (pintype "passive"))
    )
    (net (code "144") (name "GND") (class "Default")
      (node (ref "C100") (pin "2") (pinfunction "2_2") (pintype "passive"))
      (node (ref "C102") (pin "2") (pinfunction "2_2") (pintype "passive"))
      (node (ref "C103") (pin "2") (pinfunction "2_2") (pintype "passive"))
      (node (ref "C105") (pin "2") (pinfunction "2_2") (pintype "passive"))
      (node (ref "C106") (pin "2") (pinfunction "2_2") (pintype "passive"))
      (node (ref "C107") (pin "2") (pinfunction "2_2") (pintype "passive"))
      (node (ref "C108") (pin "2") (pinfunction "2_2") (pintype "passive"))
      (node (ref "C109") (pin "2") (pinfunction "2_2") (pintype "passive"))
      (node (ref "C11") (pin "2") (pinfunction "2_2") (pintype "passive"))
      (node (ref "C110") (pin "2") (pinfunction "2_2") (pintype "passive"))
      (node (ref "C111") (pin "2") (pinfunction "2_2") (pintype "passive"))
      (node (ref "C112") (pin "2") (pinfunction "2_2") (pintype "passive"))
      (node (ref "C113") (pin "2") (pinfunction "2_2") (pintype "passive"))
      (node (ref "C114") (pin "2") (pinfunction "2_2") (pintype "passive"))
      (node (ref "C115") (pin "2") (pinfunction "2_2") (pintype "passive"))
      (node (ref "C116") (pin "2") (pinfunction "2_2") (pintype "passive"))
      (node (ref "C117") (pin "2") (pinfunction "2_2") (pintype "passive"))
      (node (ref "C118") (pin "2") (pinfunction "2_2") (pintype "passive"))
      (node (ref "C119") (pin "2") (pinfunction "2_2") (pintype "passive"))
      (node (ref "C12") (pin "2") (pinfunction "2_2") (pintype "passive"))
      (node (ref "C120") (pin "2") (pinfunction "2_2") (pintype "passive"))
      (node (ref "C121") (pin "2") (pinfunction "2_2") (pintype "passive"))
      (node (ref "C122") (pin "2") (pinfunction "2_2") (pintype "passive"))
      (node (ref "C123") (pin "2") (pinfunction "2_2") (pintype "passive"))
      (node (ref "C124") (pin "2") (pinfunction "2_2") (pintype "passive"))
      (node (ref "C125") (pin "2") (pinfunction "2_2") (pintype "passive"))
      (node (ref "C126") (pin "2") (pinfunction "2_2") (pintype "passive"))
      (node (ref "C127") (pin "2") (pinfunction "2_2") (pintype "passive"))
      (node (ref "C128") (pin "2") (pinfunction "2_2") (pintype "passive"))
      (node (ref "C129") (pin "2") (pinfunction "2_2") (pintype "passive"))
      (node (ref "C13") (pin "1") (pinfunction "1_1") (pintype "passive"))
      (node (ref "C130") (pin "2") (pinfunction "2_2") (pintype "passive"))
      (node (ref "C131") (pin "2") (pinfunction "2_2") (pintype "passive"))
      (node (ref "C132") (pin "2") (pinfunction "2_2") (pintype "passive"))
      (node (ref "C133") (pin "2") (pinfunction "2_2") (pintype "passive"))
      (node (ref "C134") (pin "2") (pinfunction "2_2") (pintype "passive"))
      (node (ref "C135") (pin "2") (pinfunction "2_2") (pintype "passive"))
      (node (ref "C136") (pin "2") (pinfunction "2_2") (pintype "passive"))
      (node (ref "C137") (pin "2") (pinfunction "2_2") (pintype "passive"))
      (node (ref "C138") (pin "2") (pinfunction "2_2") (pintype "passive"))
      (node (ref "C139") (pin "2") (pinfunction "2_2") (pintype "passive"))
      (node (ref "C14") (pin "1") (pinfunction "1_1") (pintype "passive"))
      (node (ref "C140") (pin "2") (pinfunction "2_2") (pintype "passive"))
      (node (ref "C142") (pin "2") (pinfunction "2_2") (pintype "passive"))
      (node (ref "C144") (pin "2") (pinfunction "2_2") (pintype "passive"))
      (node (ref "C145") (pin "2") (pinfunction "2_2") (pintype "passive"))
      (node (ref "C146") (pin "2") (pinfunction "2_2") (pintype "passive"))
      (node (ref "C148") (pin "2") (pinfunction "2_2") (pintype "passive"))
      (node (ref "C149") (pin "2") (pinfunction "2_2") (pintype "passive"))
      (node (ref "C15") (pin "1") (pinfunction "1_1") (pintype "passive"))
      (node (ref "C150") (pin "2") (pinfunction "2_2") (pintype "passive"))
      (node (ref "C152") (pin "2") (pinfunction "2_2") (pintype "passive"))
      (node (ref "C153") (pin "2") (pinfunction "2_2") (pintype "passive"))
      (node (ref "C154") (pin "2") (pinfunction "2_2") (pintype "passive"))
      (node (ref "C155") (pin "2") (pinfunction "2_2") (pintype "passive"))
      (node (ref "C156") (pin "2") (pinfunction "2_2") (pintype "passive"))
      (node (ref "C157") (pin "2") (pinfunction "2_2") (pintype "passive"))
      (node (ref "C158") (pin "2") (pinfunction "2_2") (pintype "passive"))
      (node (ref "C159") (pin "2") (pinfunction "2_2") (pintype "passive"))
      (node (ref "C16") (pin "1") (pinfunction "1_1") (pintype "passive"))
      (node (ref "C160") (pin "2") (pinfunction "2_2") (pintype "passive"))
      (node (ref "C161") (pin "2") (pinfunction "2_2") (pintype "passive"))
      (node (ref "C162") (pin "2") (pinfunction "2_2") (pintype "passive"))
      (node (ref "C163") (pin "2") (pinfunction "2_2") (pintype "passive"))
      (node (ref "C164") (pin "2") (pinfunction "2_2") (pintype "passive"))
      (node (ref "C165") (pin "2") (pinfunction "2_2") (pintype "passive"))
      (node (ref "C166") (pin "2") (pinfunction "2_2") (pintype "passive"))
      (node (ref "C167") (pin "2") (pinfunction "2_2") (pintype "passive"))
      (node (ref "C169") (pin "2") (pinfunction "2_2") (pintype "passive"))
      (node (ref "C17") (pin "2") (pinfunction "2_2") (pintype "passive"))
      (node (ref "C170") (pin "2") (pinfunction "2_2") (pintype "passive"))
      (node (ref "C171") (pin "2") (pinfunction "2_2") (pintype "passive"))
      (node (ref "C172") (pin "2") (pinfunction "2_2") (pintype "passive"))
      (node (ref "C173") (pin "2") (pinfunction "2_2") (pintype "passive"))
      (node (ref "C174") (pin "2") (pinfunction "2_2") (pintype "passive"))
      (node (ref "C175") (pin "2") (pinfunction "2_2") (pintype "passive"))
      (node (ref "C176") (pin "2") (pinfunction "2_2") (pintype "passive"))
      (node (ref "C177") (pin "2") (pinfunction "2_2") (pintype "passive"))
      (node (ref "C178") (pin "2") (pinfunction "2_2") (pintype "passive"))
      (node (ref "C179") (pin "2") (pinfunction "2_2") (pintype "passive"))
      (node (ref "C18") (pin "1") (pinfunction "1_1") (pintype "passive"))
      (node (ref "C180") (pin "2") (pinfunction "2_2") (pintype "passive"))
      (node (ref "C181") (pin "2") (pinfunction "2_2") (pintype "passive"))
      (node (ref "C182") (pin "2") (pinfunction "2_2") (pintype "passive"))
      (node (ref "C183") (pin "2") (pinfunction "2_2") (pintype "passive"))
      (node (ref "C184") (pin "2") (pinfunction "2_2") (pintype "passive"))
      (node (ref "C185") (pin "2") (pinfunction "2_2") (pintype "passive"))
      (node (ref "C187") (pin "2") (pinfunction "2_2") (pintype "passive"))
      (node (ref "C188") (pin "1") (pinfunction "1_1") (pintype "passive"))
      (node (ref "C19") (pin "1") (pinfunction "1_1") (pintype "passive"))
      (node (ref "C190") (pin "2") (pinfunction "2_2") (pintype "passive"))
      (node (ref "C191") (pin "2") (pinfunction "2_2") (pintype "passive"))
      (node (ref "C192") (pin "2") (pinfunction "2_2") (pintype "passive"))
      (node (ref "C193") (pin "2") (pinfunction "2_2") (pintype "passive"))
      (node (ref "C195") (pin "2") (pinfunction "2_2") (pintype "passive"))
      (node (ref "C196") (pin "2") (pinfunction "2_2") (pintype "passive"))
      (node (ref "C197") (pin "2") (pinfunction "2_2") (pintype "passive"))
      (node (ref "C198") (pin "2") (pinfunction "2_2") (pintype "passive"))
      (node (ref "C199") (pin "2") (pinfunction "2_2") (pintype "passive"))
      (node (ref "C2") (pin "2") (pinfunction "2_2") (pintype "passive"))
      (node (ref "C20") (pin "1") (pinfunction "1_1") (pintype "passive"))
      (node (ref "C200") (pin "2") (pinfunction "2_2") (pintype "passive"))
      (node (ref "C201") (pin "2") (pinfunction "2_2") (pintype "passive"))
      (node (ref "C202") (pin "2") (pinfunction "2_2") (pintype "passive"))
      (node (ref "C203") (pin "2") (pinfunction "2_2") (pintype "passive"))
      (node (ref "C204") (pin "2") (pinfunction "2_2") (pintype "passive"))
      (node (ref "C205") (pin "2") (pinfunction "2_2") (pintype "passive"))
      (node (ref "C206") (pin "1") (pinfunction "1_1") (pintype "passive"))
      (node (ref "C207") (pin "2") (pinfunction "2_2") (pintype "passive"))
      (node (ref "C208") (pin "2") (pinfunction "2_2") (pintype "passive"))
      (node (ref "C21") (pin "1") (pinfunction "1_1") (pintype "passive"))
      (node (ref "C210") (pin "2") (pinfunction "2_2") (pintype "passive"))
      (node (ref "C211") (pin "2") (pinfunction "2_2") (pintype "passive"))
      (node (ref "C213") (pin "2") (pinfunction "2_2") (pintype "passive"))
      (node (ref "C214") (pin "2") (pinfunction "2_2") (pintype "passive"))
      (node (ref "C215") (pin "2") (pinfunction "2_2") (pintype "passive"))
      (node (ref "C216") (pin "2") (pinfunction "2_2") (pintype "passive"))
      (node (ref "C217") (pin "2") (pinfunction "2_2") (pintype "passive"))
      (node (ref "C218") (pin "2") (pinfunction "2_2") (pintype "passive"))
      (node (ref "C219") (pin "2") (pinfunction "2_2") (pintype "passive"))
      (node (ref "C22") (pin "1") (pinfunction "1_1") (pintype "passive"))
      (node (ref "C220") (pin "2") (pinfunction "2_2") (pintype "passive"))
      (node (ref "C221") (pin "2") (pinfunction "2_2") (pintype "passive"))
      (node (ref "C222") (pin "2") (pinfunction "2_2") (pintype "passive"))
      (node (ref "C223") (pin "2") (pinfunction "2_2") (pintype "passive"))
      (node (ref "C224") (pin "2") (pinfunction "2_2") (pintype "passive"))
      (node (ref "C225") (pin "2") (pinfunction "2_2") (pintype "passive"))
      (node (ref "C226") (pin "2") (pinfunction "2_2") (pintype "passive"))
      (node (ref "C227") (pin "2") (pinfunction "2_2") (pintype "passive"))
      (node (ref "C228") (pin "2") (pinfunction "2_2") (pintype "passive"))
      (node (ref "C229") (pin "2") (pinfunction "2_2") (pintype "passive"))
      (node (ref "C23") (pin "1") (pinfunction "1_1") (pintype "passive"))
      (node (ref "C231") (pin "2") (pinfunction "2_2") (pintype "passive"))
      (node (ref "C233") (pin "2") (pinfunction "2_2") (pintype "passive"))
      (node (ref "C234") (pin "2") (pinfunction "2_2") (pintype "passive"))
      (node (ref "C237") (pin "2") (pinfunction "2_2") (pintype "passive"))
      (node (ref "C238") (pin "2") (pinfunction "2_2") (pintype "passive"))
      (node (ref "C239") (pin "2") (pinfunction "2_2") (pintype "passive"))
      (node (ref "C24") (pin "1") (pinfunction "1_1") (pintype "passive"))
      (node (ref "C240") (pin "2") (pinfunction "2_2") (pintype "passive"))
      (node (ref "C241") (pin "2") (pinfunction "2_2") (pintype "passive"))
      (node (ref "C242") (pin "2") (pinfunction "2_2") (pintype "passive"))
      (node (ref "C243") (pin "2") (pinfunction "2_2") (pintype "passive"))
      (node (ref "C244") (pin "2") (pinfunction "2_2") (pintype "passive"))
      (node (ref "C245") (pin "2") (pinfunction "2_2") (pintype "passive"))
      (node (ref "C246") (pin "2") (pinfunction "2_2") (pintype "passive"))
      (node (ref "C247") (pin "2") (pinfunction "2_2") (pintype "passive"))
      (node (ref "C248") (pin "2") (pinfunction "2_2") (pintype "passive"))
      (node (ref "C249") (pin "2") (pinfunction "2_2") (pintype "passive"))
      (node (ref "C25") (pin "1") (pinfunction "1_1") (pintype "passive"))
      (node (ref "C250") (pin "2") (pinfunction "2_2") (pintype "passive"))
      (node (ref "C251") (pin "2") (pinfunction "2_2") (pintype "passive"))
      (node (ref "C252") (pin "2") (pinfunction "2_2") (pintype "passive"))
      (node (ref "C253") (pin "1") (pinfunction "1_1") (pintype "passive"))
      (node (ref "C254") (pin "1") (pinfunction "1_1") (pintype "passive"))
      (node (ref "C255") (pin "2") (pinfunction "2_2") (pintype "passive"))
      (node (ref "C256") (pin "2") (pinfunction "2_2") (pintype "passive"))
      (node (ref "C257") (pin "2") (pinfunction "2_2") (pintype "passive"))
      (node (ref "C258") (pin "2") (pinfunction "2_2") (pintype "passive"))
      (node (ref "C259") (pin "2") (pinfunction "2_2") (pintype "passive"))
      (node (ref "C26") (pin "1") (pinfunction "1_1") (pintype "passive"))
      (node (ref "C260") (pin "2") (pinfunction "2_2") (pintype "passive"))
      (node (ref "C261") (pin "2") (pinfunction "2_2") (pintype "passive"))
      (node (ref "C262") (pin "2") (pinfunction "2_2") (pintype "passive"))
      (node (ref "C263") (pin "2") (pinfunction "2_2") (pintype "passive"))
      (node (ref "C264") (pin "2") (pinfunction "2_2") (pintype "passive"))
      (node (ref "C265") (pin "2") (pinfunction "2_2") (pintype "passive"))
      (node (ref "C266") (pin "2") (pinfunction "2_2") (pintype "passive"))
      (node (ref "C267") (pin "2") (pinfunction "2_2") (pintype "passive"))
      (node (ref "C268") (pin "2") (pinfunction "2_2") (pintype "passive"))
      (node (ref "C269") (pin "2") (pinfunction "2_2") (pintype "passive"))
      (node (ref "C27") (pin "1") (pinfunction "1_1") (pintype "passive"))
      (node (ref "C270") (pin "2") (pinfunction "2_2") (pintype "passive"))
      (node (ref "C271") (pin "2") (pinfunction "2_2") (pintype "passive"))
      (node (ref "C272") (pin "2") (pinfunction "2_2") (pintype "passive"))
      (node (ref "C273") (pin "2") (pinfunction "2_2") (pintype "passive"))
      (node (ref "C274") (pin "2") (pinfunction "2_2") (pintype "passive"))
      (node (ref "C275") (pin "2") (pinfunction "2_2") (pintype "passive"))
      (node (ref "C276") (pin "2") (pinfunction "2_2") (pintype "passive"))
      (node (ref "C277") (pin "2") (pinfunction "2_2") (pintype "passive"))
      (node (ref "C278") (pin "2") (pinfunction "2_2") (pintype "passive"))
      (node (ref "C279") (pin "2") (pinfunction "2_2") (pintype "passive"))
      (node (ref "C28") (pin "1") (pinfunction "1_1") (pintype "passive"))
      (node (ref "C280") (pin "2") (pinfunction "2_2") (pintype "passive"))
      (node (ref "C281") (pin "2") (pinfunction "2_2") (pintype "passive"))
      (node (ref "C282") (pin "2") (pinfunction "2_2") (pintype "passive"))
      (node (ref "C283") (pin "2") (pinfunction "2_2") (pintype "passive"))
      (node (ref "C284") (pin "2") (pinfunction "2_2") (pintype "passive"))
      (node (ref "C285") (pin "2") (pinfunction "2_2") (pintype "passive"))
      (node (ref "C286") (pin "2") (pinfunction "2_2") (pintype "passive"))
      (node (ref "C287") (pin "2") (pinfunction "2_2") (pintype "passive"))
      (node (ref "C288") (pin "2") (pinfunction "2_2") (pintype "passive"))
      (node (ref "C289") (pin "2") (pinfunction "2_2") (pintype "passive"))
      (node (ref "C29") (pin "1") (pinfunction "1_1") (pintype "passive"))
      (node (ref "C290") (pin "2") (pinfunction "2_2") (pintype "passive"))
      (node (ref "C291") (pin "2") (pinfunction "2_2") (pintype "passive"))
      (node (ref "C292") (pin "2") (pinfunction "2_2") (pintype "passive"))
      (node (ref "C293") (pin "2") (pinfunction "2_2") (pintype "passive"))
      (node (ref "C294") (pin "2") (pinfunction "2_2") (pintype "passive"))
      (node (ref "C295") (pin "2") (pinfunction "2_2") (pintype "passive"))
      (node (ref "C296") (pin "2") (pinfunction "2_2") (pintype "passive"))
      (node (ref "C297") (pin "2") (pinfunction "2_2") (pintype "passive"))
      (node (ref "C298") (pin "2") (pinfunction "2_2") (pintype "passive"))
      (node (ref "C299") (pin "2") (pinfunction "2_2") (pintype "passive"))
      (node (ref "C3") (pin "2") (pinfunction "2_2") (pintype "passive"))
      (node (ref "C30") (pin "2") (pinfunction "2_2") (pintype "passive"))
      (node (ref "C300") (pin "2") (pinfunction "2_2") (pintype "passive"))
      (node (ref "C301") (pin "2") (pinfunction "2_2") (pintype "passive"))
      (node (ref "C302") (pin "2") (pinfunction "2_2") (pintype "passive"))
      (node (ref "C303") (pin "2") (pinfunction "2_2") (pintype "passive"))
      (node (ref "C304") (pin "2") (pinfunction "2_2") (pintype "passive"))
      (node (ref "C305") (pin "2") (pinfunction "2_2") (pintype "passive"))
      (node (ref "C306") (pin "2") (pinfunction "2_2") (pintype "passive"))
      (node (ref "C307") (pin "2") (pinfunction "2_2") (pintype "passive"))
      (node (ref "C308") (pin "1") (pinfunction "1_1") (pintype "passive"))
      (node (ref "C309") (pin "2") (pinfunction "2_2") (pintype "passive"))
      (node (ref "C311") (pin "2") (pinfunction "2_2") (pintype "passive"))
      (node (ref "C313") (pin "2") (pinfunction "2_2") (pintype "passive"))
      (node (ref "C314") (pin "2") (pinfunction "2_2") (pintype "passive"))
      (node (ref "C315") (pin "2") (pinfunction "2_2") (pintype "passive"))
      (node (ref "C316") (pin "2") (pinfunction "2_2") (pintype "passive"))
      (node (ref "C317") (pin "2") (pinfunction "2_2") (pintype "passive"))
      (node (ref "C318") (pin "2") (pinfunction "2_2") (pintype "passive"))
      (node (ref "C319") (pin "2") (pinfunction "2_2") (pintype "passive"))
      (node (ref "C32") (pin "2") (pinfunction "2_2") (pintype "passive"))
      (node (ref "C320") (pin "2") (pinfunction "2_2") (pintype "passive"))
      (node (ref "C321") (pin "2") (pinfunction "2_2") (pintype "passive"))
      (node (ref "C322") (pin "2") (pinfunction "2_2") (pintype "passive"))
      (node (ref "C323") (pin "2") (pinfunction "2_2") (pintype "passive"))
      (node (ref "C324") (pin "2") (pinfunction "2_2") (pintype "passive"))
      (node (ref "C325") (pin "2") (pinfunction "2_2") (pintype "passive"))
      (node (ref "C326") (pin "2") (pinfunction "2_2") (pintype "passive"))
      (node (ref "C327") (pin "2") (pinfunction "2_2") (pintype "passive"))
      (node (ref "C328") (pin "2") (pinfunction "2_2") (pintype "passive"))
      (node (ref "C329") (pin "2") (pinfunction "2_2") (pintype "passive"))
      (node (ref "C33") (pin "2") (pinfunction "2_2") (pintype "passive"))
      (node (ref "C330") (pin "2") (pinfunction "2_2") (pintype "passive"))
      (node (ref "C331") (pin "2") (pinfunction "2_2") (pintype "passive"))
      (node (ref "C332") (pin "2") (pinfunction "2_2") (pintype "passive"))
      (node (ref "C333") (pin "2") (pinfunction "2_2") (pintype "passive"))
      (node (ref "C334") (pin "2") (pinfunction "2_2") (pintype "passive"))
      (node (ref "C335") (pin "2") (pinfunction "2_2") (pintype "passive"))
      (node (ref "C336") (pin "2") (pinfunction "2_2") (pintype "passive"))
      (node (ref "C337") (pin "2") (pinfunction "2_2") (pintype "passive"))
      (node (ref "C338") (pin "2") (pinfunction "2_2") (pintype "passive"))
      (node (ref "C339") (pin "2") (pinfunction "2_2") (pintype "passive"))
      (node (ref "C34") (pin "2") (pinfunction "2_2") (pintype "passive"))
      (node (ref "C340") (pin "2") (pinfunction "2_2") (pintype "passive"))
      (node (ref "C341") (pin "2") (pinfunction "2_2") (pintype "passive"))
      (node (ref "C342") (pin "2") (pinfunction "2_2") (pintype "passive"))
      (node (ref "C343") (pin "2") (pinfunction "2_2") (pintype "passive"))
      (node (ref "C344") (pin "2") (pinfunction "2_2") (pintype "passive"))
      (node (ref "C345") (pin "2") (pinfunction "2_2") (pintype "passive"))
      (node (ref "C346") (pin "2") (pinfunction "2_2") (pintype "passive"))
      (node (ref "C347") (pin "2") (pinfunction "2_2") (pintype "passive"))
      (node (ref "C348") (pin "2") (pinfunction "2_2") (pintype "passive"))
      (node (ref "C349") (pin "2") (pinfunction "2_2") (pintype "passive"))
      (node (ref "C35") (pin "2") (pinfunction "2_2") (pintype "passive"))
      (node (ref "C351") (pin "2") (pinfunction "2_2") (pintype "passive"))
      (node (ref "C352") (pin "2") (pinfunction "2_2") (pintype "passive"))
      (node (ref "C353") (pin "2") (pinfunction "2_2") (pintype "passive"))
      (node (ref "C355") (pin "2") (pinfunction "2_2") (pintype "passive"))
      (node (ref "C356") (pin "2") (pinfunction "2_2") (pintype "passive"))
      (node (ref "C358") (pin "2") (pinfunction "2_2") (pintype "passive"))
      (node (ref "C359") (pin "2") (pinfunction "2_2") (pintype "passive"))
      (node (ref "C36") (pin "2") (pinfunction "2_2") (pintype "passive"))
      (node (ref "C360") (pin "2") (pinfunction "2_2") (pintype "passive"))
      (node (ref "C361") (pin "2") (pinfunction "2_2") (pintype "passive"))
      (node (ref "C362") (pin "2") (pinfunction "2_2") (pintype "passive"))
      (node (ref "C363") (pin "2") (pinfunction "2_2") (pintype "passive"))
      (node (ref "C364") (pin "2") (pinfunction "2_2") (pintype "passive"))
      (node (ref "C365") (pin "2") (pinfunction "2_2") (pintype "passive"))
      (node (ref "C366") (pin "2") (pinfunction "2_2") (pintype "passive"))
      (node (ref "C367") (pin "2") (pinfunction "2_2") (pintype "passive"))
      (node (ref "C368") (pin "2") (pinfunction "2_2") (pintype "passive"))
      (node (ref "C369") (pin "2") (pinfunction "2_2") (pintype "passive"))
      (node (ref "C37") (pin "2") (pinfunction "2_2") (pintype "passive"))
      (node (ref "C370") (pin "2") (pinfunction "2_2") (pintype "passive"))
      (node (ref "C371") (pin "2") (pinfunction "2_2") (pintype "passive"))
      (node (ref "C372") (pin "2") (pinfunction "2_2") (pintype "passive"))
      (node (ref "C373") (pin "2") (pinfunction "2_2") (pintype "passive"))
      (node (ref "C374") (pin "2") (pinfunction "2_2") (pintype "passive"))
      (node (ref "C375") (pin "2") (pinfunction "2_2") (pintype "passive"))
      (node (ref "C376") (pin "2") (pinfunction "2_2") (pintype "passive"))
      (node (ref "C377") (pin "2") (pinfunction "2_2") (pintype "passive"))
      (node (ref "C378") (pin "2") (pinfunction "2_2") (pintype "passive"))
      (node (ref "C379") (pin "2") (pinfunction "2_2") (pintype "passive"))
      (node (ref "C380") (pin "2") (pinfunction "2_2") (pintype "passive"))
      (node (ref "C381") (pin "2") (pinfunction "2_2") (pintype "passive"))
      (node (ref "C382") (pin "2") (pinfunction "2_2") (pintype "passive"))
      (node (ref "C383") (pin "2") (pinfunction "2_2") (pintype "passive"))
      (node (ref "C384") (pin "2") (pinfunction "2_2") (pintype "passive"))
      (node (ref "C385") (pin "2") (pinfunction "2_2") (pintype "passive"))
      (node (ref "C386") (pin "2") (pinfunction "2_2") (pintype "passive"))
      (node (ref "C387") (pin "2") (pinfunction "2_2") (pintype "passive"))
      (node (ref "C388") (pin "1") (pinfunction "1_1") (pintype "passive"))
      (node (ref "C389") (pin "1") (pinfunction "1_1") (pintype "passive"))
      (node (ref "C39") (pin "2") (pinfunction "2_2") (pintype "passive"))
      (node (ref "C390") (pin "1") (pinfunction "1_1") (pintype "passive"))
      (node (ref "C391") (pin "1") (pinfunction "1_1") (pintype "passive"))
      (node (ref "C392") (pin "1") (pinfunction "1_1") (pintype "passive"))
      (node (ref "C393") (pin "1") (pinfunction "1_1") (pintype "passive"))
      (node (ref "C394") (pin "1") (pinfunction "1_1") (pintype "passive"))
      (node (ref "C395") (pin "1") (pinfunction "1_1") (pintype "passive"))
      (node (ref "C396") (pin "1") (pinfunction "1_1") (pintype "passive"))
      (node (ref "C397") (pin "1") (pinfunction "1_1") (pintype "passive"))
      (node (ref "C398") (pin "1") (pinfunction "1_1") (pintype "passive"))
      (node (ref "C399") (pin "1") (pinfunction "1_1") (pintype "passive"))
      (node (ref "C4") (pin "2") (pinfunction "2_2") (pintype "passive"))
      (node (ref "C40") (pin "2") (pinfunction "2_2") (pintype "passive"))
      (node (ref "C400") (pin "1") (pinfunction "1_1") (pintype "passive"))
      (node (ref "C401") (pin "1") (pinfunction "1_1") (pintype "passive"))
      (node (ref "C402") (pin "1") (pinfunction "1_1") (pintype "passive"))
      (node (ref "C403") (pin "1") (pinfunction "1_1") (pintype "passive"))
      (node (ref "C404") (pin "1") (pinfunction "1_1") (pintype "passive"))
      (node (ref "C405") (pin "1") (pinfunction "1_1") (pintype "passive"))
      (node (ref "C406") (pin "1") (pinfunction "1_1") (pintype "passive"))
      (node (ref "C407") (pin "1") (pinfunction "1_1") (pintype "passive"))
      (node (ref "C408") (pin "1") (pinfunction "1_1") (pintype "passive"))
      (node (ref "C409") (pin "1") (pinfunction "1_1") (pintype "passive"))
      (node (ref "C41") (pin "2") (pinfunction "2_2") (pintype "passive"))
      (node (ref "C410") (pin "1") (pinfunction "1_1") (pintype "passive"))
      (node (ref "C411") (pin "1") (pinfunction "1_1") (pintype "passive"))
      (node (ref "C412") (pin "1") (pinfunction "1_1") (pintype "passive"))
      (node (ref "C413") (pin "1") (pinfunction "1_1") (pintype "passive"))
      (node (ref "C414") (pin "1") (pinfunction "1_1") (pintype "passive"))
      (node (ref "C415") (pin "1") (pinfunction "1_1") (pintype "passive"))
      (node (ref "C416") (pin "1") (pinfunction "1_1") (pintype "passive"))
      (node (ref "C417") (pin "1") (pinfunction "1_1") (pintype "passive"))
      (node (ref "C418") (pin "1") (pinfunction "1_1") (pintype "passive"))
      (node (ref "C419") (pin "1") (pinfunction "1_1") (pintype "passive"))
      (node (ref "C42") (pin "2") (pinfunction "2_2") (pintype "passive"))
      (node (ref "C420") (pin "1") (pinfunction "1_1") (pintype "passive"))
      (node (ref "C421") (pin "1") (pinfunction "1_1") (pintype "passive"))
      (node (ref "C422") (pin "1") (pinfunction "1_1") (pintype "passive"))
      (node (ref "C423") (pin "1") (pinfunction "1_1") (pintype "passive"))
      (node (ref "C424") (pin "1") (pinfunction "1_1") (pintype "passive"))
      (node (ref "C427") (pin "1") (pinfunction "1_1") (pintype "passive"))
      (node (ref "C428") (pin "1") (pinfunction "1_1") (pintype "passive"))
      (node (ref "C429") (pin "1") (pinfunction "1_1") (pintype "passive"))
      (node (ref "C43") (pin "2") (pinfunction "2_2") (pintype "passive"))
      (node (ref "C430") (pin "1") (pinfunction "1_1") (pintype "passive"))
      (node (ref "C431") (pin "1") (pinfunction "1_1") (pintype "passive"))
      (node (ref "C432") (pin "1") (pinfunction "1_1") (pintype "passive"))
      (node (ref "C433") (pin "1") (pinfunction "1_1") (pintype "passive"))
      (node (ref "C434") (pin "1") (pinfunction "1_1") (pintype "passive"))
      (node (ref "C435") (pin "1") (pinfunction "1_1") (pintype "passive"))
      (node (ref "C436") (pin "1") (pinfunction "1_1") (pintype "passive"))
      (node (ref "C439") (pin "1") (pinfunction "1_1") (pintype "passive"))
      (node (ref "C44") (pin "2") (pinfunction "2_2") (pintype "passive"))
      (node (ref "C440") (pin "1") (pinfunction "1_1") (pintype "passive"))
      (node (ref "C441") (pin "1") (pinfunction "1_1") (pintype "passive"))
      (node (ref "C442") (pin "1") (pinfunction "1_1") (pintype "passive"))
      (node (ref "C443") (pin "1") (pinfunction "1_1") (pintype "passive"))
      (node (ref "C444") (pin "1") (pinfunction "1_1") (pintype "passive"))
      (node (ref "C445") (pin "1") (pinfunction "1_1") (pintype "passive"))
      (node (ref "C446") (pin "1") (pinfunction "1_1") (pintype "passive"))
      (node (ref "C447") (pin "1") (pinfunction "1_1") (pintype "passive"))
      (node (ref "C448") (pin "1") (pinfunction "1_1") (pintype "passive"))
      (node (ref "C449") (pin "1") (pinfunction "1_1") (pintype "passive"))
      (node (ref "C450") (pin "1") (pinfunction "1_1") (pintype "passive"))
      (node (ref "C451") (pin "1") (pinfunction "1_1") (pintype "passive"))
      (node (ref "C452") (pin "1") (pinfunction "1_1") (pintype "passive"))
      (node (ref "C453") (pin "1") (pinfunction "1_1") (pintype "passive"))
      (node (ref "C454") (pin "1") (pinfunction "1_1") (pintype "passive"))
      (node (ref "C455") (pin "1") (pinfunction "1_1") (pintype "passive"))
      (node (ref "C456") (pin "1") (pinfunction "1_1") (pintype "passive"))
      (node (ref "C457") (pin "1") (pinfunction "1_1") (pintype "passive"))
      (node (ref "C458") (pin "1") (pinfunction "1_1") (pintype "passive"))
      (node (ref "C459") (pin "1") (pinfunction "1_1") (pintype "passive"))
      (node (ref "C46") (pin "2") (pinfunction "2_2") (pintype "passive"))
      (node (ref "C460") (pin "1") (pinfunction "1_1") (pintype "passive"))
      (node (ref "C461") (pin "1") (pinfunction "1_1") (pintype "passive"))
      (node (ref "C462") (pin "1") (pinfunction "1_1") (pintype "passive"))
      (node (ref "C463") (pin "1") (pinfunction "1_1") (pintype "passive"))
      (node (ref "C464") (pin "1") (pinfunction "1_1") (pintype "passive"))
      (node (ref "C465") (pin "1") (pinfunction "1_1") (pintype "passive"))
      (node (ref "C466") (pin "1") (pinfunction "1_1") (pintype "passive"))
      (node (ref "C467") (pin "1") (pinfunction "1_1") (pintype "passive"))
      (node (ref "C468") (pin "1") (pinfunction "1_1") (pintype "passive"))
      (node (ref "C469") (pin "1") (pinfunction "1_1") (pintype "passive"))
      (node (ref "C470") (pin "1") (pinfunction "1_1") (pintype "passive"))
      (node (ref "C471") (pin "1") (pinfunction "1_1") (pintype "passive"))
      (node (ref "C472") (pin "1") (pinfunction "1_1") (pintype "passive"))
      (node (ref "C475") (pin "1") (pinfunction "1_1") (pintype "passive"))
      (node (ref "C476") (pin "1") (pinfunction "1_1") (pintype "passive"))
      (node (ref "C477") (pin "1") (pinfunction "1_1") (pintype "passive"))
      (node (ref "C478") (pin "1") (pinfunction "1_1") (pintype "passive"))
      (node (ref "C479") (pin "1") (pinfunction "1_1") (pintype "passive"))
      (node (ref "C48") (pin "2") (pinfunction "2_2") (pintype "passive"))
      (node (ref "C480") (pin "1") (pinfunction "1_1") (pintype "passive"))
      (node (ref "C481") (pin "1") (pinfunction "1_1") (pintype "passive"))
      (node (ref "C482") (pin "1") (pinfunction "1_1") (pintype "passive"))
      (node (ref "C483") (pin "1") (pinfunction "1_1") (pintype "passive"))
      (node (ref "C489") (pin "2") (pinfunction "2_2") (pintype "passive"))
      (node (ref "C49") (pin "2") (pinfunction "2_2") (pintype "passive"))
      (node (ref "C491") (pin "2") (pinfunction "2_2") (pintype "passive"))
      (node (ref "C493") (pin "2") (pinfunction "2_2") (pintype "passive"))
      (node (ref "C494") (pin "2") (pinfunction "2_2") (pintype "passive"))
      (node (ref "C495") (pin "2") (pinfunction "2_2") (pintype "passive"))
      (node (ref "C5") (pin "2") (pinfunction "2_2") (pintype "passive"))
      (node (ref "C50") (pin "2") (pinfunction "2_2") (pintype "passive"))
      (node (ref "C501") (pin "2") (pinfunction "2_2") (pintype "passive"))
      (node (ref "C503") (pin "2") (pinfunction "2_2") (pintype "passive"))
      (node (ref "C504") (pin "2") (pinfunction "2_2") (pintype "passive"))
      (node (ref "C505") (pin "2") (pinfunction "2_2") (pintype "passive"))
      (node (ref "C506") (pin "2") (pinfunction "2_2") (pintype "passive"))
      (node (ref "C507") (pin "2") (pinfunction "2_2") (pintype "passive"))
      (node (ref "C508") (pin "2") (pinfunction "2_2") (pintype "passive"))
      (node (ref "C509") (pin "2") (pinfunction "2_2") (pintype "passive"))
      (node (ref "C51") (pin "2") (pinfunction "2_2") (pintype "passive"))
      (node (ref "C510") (pin "2") (pinfunction "2_2") (pintype "passive"))
      (node (ref "C511") (pin "2") (pinfunction "2_2") (pintype "passive"))
      (node (ref "C512") (pin "2") (pinfunction "2_2") (pintype "passive"))
      (node (ref "C513") (pin "2") (pinfunction "2_2") (pintype "passive"))
      (node (ref "C514") (pin "2") (pinfunction "2_2") (pintype "passive"))
      (node (ref "C515") (pin "2") (pinfunction "2_2") (pintype "passive"))
      (node (ref "C516") (pin "2") (pinfunction "2_2") (pintype "passive"))
      (node (ref "C517") (pin "2") (pinfunction "2_2") (pintype "passive"))
      (node (ref "C518") (pin "2") (pinfunction "2_2") (pintype "passive"))
      (node (ref "C519") (pin "2") (pinfunction "2_2") (pintype "passive"))
      (node (ref "C52") (pin "2") (pinfunction "2_2") (pintype "passive"))
      (node (ref "C520") (pin "2") (pinfunction "2_2") (pintype "passive"))
      (node (ref "C521") (pin "2") (pinfunction "2_2") (pintype "passive"))
      (node (ref "C522") (pin "2") (pinfunction "2_2") (pintype "passive"))
      (node (ref "C523") (pin "2") (pinfunction "2_2") (pintype "passive"))
      (node (ref "C524") (pin "2") (pinfunction "2_2") (pintype "passive"))
      (node (ref "C525") (pin "2") (pinfunction "2_2") (pintype "passive"))
      (node (ref "C526") (pin "2") (pinfunction "2_2") (pintype "passive"))
      (node (ref "C527") (pin "2") (pinfunction "2_2") (pintype "passive"))
      (node (ref "C528") (pin "2") (pinfunction "2_2") (pintype "passive"))
      (node (ref "C529") (pin "2") (pinfunction "2_2") (pintype "passive"))
      (node (ref "C53") (pin "2") (pinfunction "2_2") (pintype "passive"))
      (node (ref "C530") (pin "2") (pinfunction "2_2") (pintype "passive"))
      (node (ref "C531") (pin "2") (pinfunction "2_2") (pintype "passive"))
      (node (ref "C532") (pin "2") (pinfunction "2_2") (pintype "passive"))
      (node (ref "C533") (pin "2") (pinfunction "2_2") (pintype "passive"))
      (node (ref "C534") (pin "2") (pinfunction "2_2") (pintype "passive"))
      (node (ref "C535") (pin "2") (pinfunction "2_2") (pintype "passive"))
      (node (ref "C536") (pin "2") (pinfunction "2_2") (pintype "passive"))
      (node (ref "C54") (pin "2") (pinfunction "2_2") (pintype "passive"))
      (node (ref "C55") (pin "2") (pinfunction "2_2") (pintype "passive"))
      (node (ref "C56") (pin "2") (pinfunction "2_2") (pintype "passive"))
      (node (ref "C57") (pin "2") (pinfunction "2_2") (pintype "passive"))
      (node (ref "C58") (pin "2") (pinfunction "2_2") (pintype "passive"))
      (node (ref "C6") (pin "2") (pinfunction "2_2") (pintype "passive"))
      (node (ref "C60") (pin "2") (pinfunction "2_2") (pintype "passive"))
      (node (ref "C61") (pin "2") (pinfunction "2_2") (pintype "passive"))
      (node (ref "C62") (pin "2") (pinfunction "2_2") (pintype "passive"))
      (node (ref "C63") (pin "2") (pinfunction "2_2") (pintype "passive"))
      (node (ref "C64") (pin "2") (pinfunction "2_2") (pintype "passive"))
      (node (ref "C66") (pin "2") (pinfunction "2_2") (pintype "passive"))
      (node (ref "C67") (pin "2") (pinfunction "2_2") (pintype "passive"))
      (node (ref "C68") (pin "2") (pinfunction "2_2") (pintype "passive"))
      (node (ref "C69") (pin "2") (pinfunction "2_2") (pintype "passive"))
      (node (ref "C7") (pin "2") (pinfunction "2_2") (pintype "passive"))
      (node (ref "C70") (pin "2") (pinfunction "2_2") (pintype "passive"))
      (node (ref "C71") (pin "2") (pinfunction "2_2") (pintype "passive"))
      (node (ref "C72") (pin "2") (pinfunction "2_2") (pintype "passive"))
      (node (ref "C73") (pin "2") (pinfunction "2_2") (pintype "passive"))
      (node (ref "C74") (pin "2") (pinfunction "2_2") (pintype "passive"))
      (node (ref "C75") (pin "2") (pinfunction "2_2") (pintype "passive"))
      (node (ref "C76") (pin "2") (pinfunction "2_2") (pintype "passive"))
      (node (ref "C77") (pin "2") (pinfunction "2_2") (pintype "passive"))
      (node (ref "C78") (pin "2") (pinfunction "2_2") (pintype "passive"))
      (node (ref "C79") (pin "2") (pinfunction "2_2") (pintype "passive"))
      (node (ref "C8") (pin "2") (pinfunction "2_2") (pintype "passive"))
      (node (ref "C80") (pin "2") (pinfunction "2_2") (pintype "passive"))
      (node (ref "C81") (pin "2") (pinfunction "2_2") (pintype "passive"))
      (node (ref "C82") (pin "2") (pinfunction "2_2") (pintype "passive"))
      (node (ref "C83") (pin "2") (pinfunction "2_2") (pintype "passive"))
      (node (ref "C84") (pin "2") (pinfunction "2_2") (pintype "passive"))
      (node (ref "C85") (pin "2") (pinfunction "2_2") (pintype "passive"))
      (node (ref "C86") (pin "2") (pinfunction "2_2") (pintype "passive"))
      (node (ref "C87") (pin "2") (pinfunction "2_2") (pintype "passive"))
      (node (ref "C88") (pin "2") (pinfunction "2_2") (pintype "passive"))
      (node (ref "C89") (pin "2") (pinfunction "2_2") (pintype "passive"))
      (node (ref "C9") (pin "2") (pinfunction "2_2") (pintype "passive"))
      (node (ref "C90") (pin "2") (pinfunction "2_2") (pintype "passive"))
      (node (ref "C91") (pin "2") (pinfunction "2_2") (pintype "passive"))
      (node (ref "C92") (pin "2") (pinfunction "2_2") (pintype "passive"))
      (node (ref "C93") (pin "2") (pinfunction "2_2") (pintype "passive"))
      (node (ref "C94") (pin "2") (pinfunction "2_2") (pintype "passive"))
      (node (ref "C95") (pin "2") (pinfunction "2_2") (pintype "passive"))
      (node (ref "C96") (pin "2") (pinfunction "2_2") (pintype "passive"))
      (node (ref "C97") (pin "2") (pinfunction "2_2") (pintype "passive"))
      (node (ref "C98") (pin "2") (pinfunction "2_2") (pintype "passive"))
      (node (ref "D3") (pin "1") (pinfunction "A1_1") (pintype "passive"))
      (node (ref "D3") (pin "2") (pinfunction "A2_2") (pintype "passive"))
      (node (ref "D4") (pin "1") (pinfunction "C_1") (pintype "passive"))
      (node (ref "D5") (pin "1") (pinfunction "C_1") (pintype "passive"))
      (node (ref "D6") (pin "1") (pinfunction "C_1") (pintype "passive"))
      (node (ref "D7") (pin "1") (pinfunction "C_1") (pintype "passive"))
      (node (ref "J1") (pin "3") (pinfunction "3_3") (pintype "passive"))
      (node (ref "J2") (pin "2") (pinfunction "2_2") (pintype "passive"))
      (node (ref "J2") (pin "3") (pinfunction "3_3") (pintype "passive"))
      (node (ref "J3") (pin "5") (pinfunction "5_5") (pintype "passive"))
      (node (ref "J3") (pin "6") (pinfunction "6_6") (pintype "passive"))
      (node (ref "J3") (pin "7") (pinfunction "7_7") (pintype "passive"))
      (node (ref "J3") (pin "8") (pinfunction "8_8") (pintype "passive"))
      (node (ref "J3") (pin "9") (pinfunction "9_9") (pintype "passive"))
      (node (ref "J6") (pin "1") (pinfunction "1_1") (pintype "passive"))
      (node (ref "Q2") (pin "1") (pinfunction "S_1") (pintype "passive"))
      (node (ref "Q2") (pin "2") (pinfunction "S_2") (pintype "passive"))
      (node (ref "Q2") (pin "3") (pinfunction "S_3") (pintype "passive"))
      (node (ref "Q3") (pin "1") (pinfunction "S_1") (pintype "passive"))
      (node (ref "Q3") (pin "2") (pinfunction "S_2") (pintype "passive"))
      (node (ref "Q3") (pin "3") (pinfunction "S_3") (pintype "passive"))
      (node (ref "Q5") (pin "1") (pinfunction "S_1") (pintype "passive"))
      (node (ref "Q5") (pin "2") (pinfunction "S_2") (pintype "passive"))
      (node (ref "Q5") (pin "3") (pinfunction "S_3") (pintype "passive"))
      (node (ref "Q6") (pin "1") (pinfunction "S_1") (pintype "passive"))
      (node (ref "Q6") (pin "2") (pinfunction "S_2") (pintype "passive"))
      (node (ref "Q6") (pin "3") (pinfunction "S_3") (pintype "passive"))
      (node (ref "Q7") (pin "2") (pinfunction "E_2") (pintype "passive"))
      (node (ref "Q8") (pin "2") (pinfunction "E_2") (pintype "passive"))
      (node (ref "R103") (pin "1") (pinfunction "1_1") (pintype "passive"))
      (node (ref "R104") (pin "1") (pinfunction "1_1") (pintype "passive"))
      (node (ref "R105") (pin "1") (pinfunction "1_1") (pintype "passive"))
      (node (ref "R106") (pin "1") (pinfunction "1_1") (pintype "passive"))
      (node (ref "R127") (pin "1") (pinfunction "1_1") (pintype "passive"))
      (node (ref "R128") (pin "1") (pinfunction "1_1") (pintype "passive"))
      (node (ref "R129") (pin "1") (pinfunction "1_1") (pintype "passive"))
      (node (ref "R130") (pin "1") (pinfunction "1_1") (pintype "passive"))
      (node (ref "R14") (pin "1") (pinfunction "1_1") (pintype "passive"))
      (node (ref "R15") (pin "1") (pinfunction "1_1") (pintype "passive"))
      (node (ref "R17") (pin "2") (pinfunction "2_2") (pintype "passive"))
      (node (ref "R24") (pin "1") (pinfunction "1_1") (pintype "passive"))
      (node (ref "R25") (pin "1") (pinfunction "1_1") (pintype "passive"))
      (node (ref "R26") (pin "1") (pinfunction "1_1") (pintype "passive"))
      (node (ref "R27") (pin "1") (pinfunction "1_1") (pintype "passive"))
      (node (ref "R4") (pin "1") (pinfunction "1_1") (pintype "passive"))
      (node (ref "R40") (pin "1") (pinfunction "1_1") (pintype "passive"))
      (node (ref "R45") (pin "1") (pinfunction "1_1") (pintype "passive"))
      (node (ref "R59") (pin "1") (pinfunction "1_1") (pintype "passive"))
      (node (ref "R6") (pin "1") (pinfunction "1_1") (pintype "passive"))
      (node (ref "R60") (pin "1") (pinfunction "1_1") (pintype "passive"))
      (node (ref "R61") (pin "1") (pinfunction "1_1") (pintype "passive"))
      (node (ref "R79") (pin "1") (pinfunction "1_1") (pintype "passive"))
      (node (ref "R80") (pin "1") (pinfunction "1_1") (pintype "passive"))
      (node (ref "R81") (pin "1") (pinfunction "1_1") (pintype "passive"))
      (node (ref "R82") (pin "1") (pinfunction "1_1") (pintype "passive"))
      (node (ref "U1") (pin "20") (pinfunction "AVSS_20") (pintype "passive"))
      (node (ref "U1") (pin "25") (pinfunction "VSS_25") (pintype "passive"))
      (node (ref "U1") (pin "41") (pinfunction "VSS_41") (pintype "passive"))
      (node (ref "U1") (pin "9") (pinfunction "VSS_9") (pintype "passive"))
      (node (ref "U10") (pin "1") (pinfunction "CQM_1") (pintype "passive"))
      (node (ref "U10") (pin "12") (pinfunction "INCLK_12") (pintype "passive"))
      (node (ref "U10") (pin "2") (pinfunction "CMPLUS_2") (pintype "passive"))
      (node (ref "U10") (pin "3") (pinfunction "CMMINUS_3") (pintype "passive"))
      (node (ref "U10") (pin "49") (pinfunction "EP_49") (pintype "passive"))
      (node (ref "U11") (pin "1") (pinfunction "CQM_1") (pintype "passive"))
      (node (ref "U11") (pin "12") (pinfunction "INCLK_12") (pintype "passive"))
      (node (ref "U11") (pin "2") (pinfunction "CMPLUS_2") (pintype "passive"))
      (node (ref "U11") (pin "3") (pinfunction "CMMINUS_3") (pintype "passive"))
      (node (ref "U11") (pin "49") (pinfunction "EP_49") (pintype "passive"))
      (node (ref "U12") (pin "1") (pinfunction "CQM_1") (pintype "passive"))
      (node (ref "U12") (pin "12") (pinfunction "INCLK_12") (pintype "passive"))
      (node (ref "U12") (pin "2") (pinfunction "CMPLUS_2") (pintype "passive"))
      (node (ref "U12") (pin "3") (pinfunction "CMMINUS_3") (pintype "passive"))
      (node (ref "U12") (pin "49") (pinfunction "EP_49") (pintype "passive"))
      (node (ref "U13") (pin "1") (pinfunction "CQM_1") (pintype "passive"))
      (node (ref "U13") (pin "12") (pinfunction "INCLK_12") (pintype "passive"))
      (node (ref "U13") (pin "2") (pinfunction "CMPLUS_2") (pintype "passive"))
      (node (ref "U13") (pin "3") (pinfunction "CMMINUS_3") (pintype "passive"))
      (node (ref "U13") (pin "49") (pinfunction "EP_49") (pintype "passive"))
      (node (ref "U14") (pin "1") (pinfunction "CQM_1") (pintype "passive"))
      (node (ref "U14") (pin "12") (pinfunction "INCLK_12") (pintype "passive"))
      (node (ref "U14") (pin "2") (pinfunction "CMPLUS_2") (pintype "passive"))
      (node (ref "U14") (pin "3") (pinfunction "CMMINUS_3") (pintype "passive"))
      (node (ref "U14") (pin "49") (pinfunction "EP_49") (pintype "passive"))
      (node (ref "U15") (pin "1") (pinfunction "CQM_1") (pintype "passive"))
      (node (ref "U15") (pin "12") (pinfunction "INCLK_12") (pintype "passive"))
      (node (ref "U15") (pin "2") (pinfunction "CMPLUS_2") (pintype "passive"))
      (node (ref "U15") (pin "3") (pinfunction "CMMINUS_3") (pintype "passive"))
      (node (ref "U15") (pin "49") (pinfunction "EP_49") (pintype "passive"))
      (node (ref "U16") (pin "1") (pinfunction "CQM_1") (pintype "passive"))
      (node (ref "U16") (pin "12") (pinfunction "INCLK_12") (pintype "passive"))
      (node (ref "U16") (pin "2") (pinfunction "CMPLUS_2") (pintype "passive"))
      (node (ref "U16") (pin "3") (pinfunction "CMMINUS_3") (pintype "passive"))
      (node (ref "U16") (pin "49") (pinfunction "EP_49") (pintype "passive"))
      (node (ref "U17") (pin "1") (pinfunction "CQM_1") (pintype "passive"))
      (node (ref "U17") (pin "12") (pinfunction "INCLK_12") (pintype "passive"))
      (node (ref "U17") (pin "2") (pinfunction "CMPLUS_2") (pintype "passive"))
      (node (ref "U17") (pin "3") (pinfunction "CMMINUS_3") (pintype "passive"))
      (node (ref "U17") (pin "49") (pinfunction "EP_49") (pintype "passive"))
      (node (ref "U18") (pin "1") (pinfunction "CQM_1") (pintype "passive"))
      (node (ref "U18") (pin "12") (pinfunction "INCLK_12") (pintype "passive"))
      (node (ref "U18") (pin "2") (pinfunction "CMPLUS_2") (pintype "passive"))
      (node (ref "U18") (pin "3") (pinfunction "CMMINUS_3") (pintype "passive"))
      (node (ref "U18") (pin "49") (pinfunction "EP_49") (pintype "passive"))
      (node (ref "U19") (pin "6") (pinfunction "GND_6") (pintype "passive"))
      (node (ref "U19") (pin "7") (pinfunction "GND_7") (pintype "passive"))
      (node (ref "U2") (pin "1") (pinfunction "CQM_1") (pintype "passive"))
      (node (ref "U2") (pin "12") (pinfunction "INCLK_12") (pintype "passive"))
      (node (ref "U2") (pin "2") (pinfunction "CMPLUS_2") (pintype "passive"))
      (node (ref "U2") (pin "3") (pinfunction "CMMINUS_3") (pintype "passive"))
      (node (ref "U2") (pin "49") (pinfunction "EP_49") (pintype "passive"))
      (node (ref "U21") (pin "3") (pinfunction "Vdd_3") (pintype "passive"))
      (node (ref "U21") (pin "8") (pinfunction "Rs_8") (pintype "passive"))
      (node (ref "U24") (pin "6") (pinfunction "GND_6") (pintype "passive"))
      (node (ref "U24") (pin "7") (pinfunction "GND_7") (pintype "passive"))
      (node (ref "U25") (pin "4") (pinfunction "GND_4") (pintype "passive"))
      (node (ref "U25") (pin "9") (pinfunction "EP_9") (pintype "passive"))
      (node (ref "U3") (pin "1") (pinfunction "CQM_1") (pintype "passive"))
      (node (ref "U3") (pin "12") (pinfunction "INCLK_12") (pintype "passive"))
      (node (ref "U3") (pin "2") (pinfunction "CMPLUS_2") (pintype "passive"))
      (node (ref "U3") (pin "3") (pinfunction "CMMINUS_3") (pintype "passive"))
      (node (ref "U3") (pin "49") (pinfunction "EP_49") (pintype "passive"))
      (node (ref "U30") (pin "4") (pinfunction "GND_4") (pintype "passive"))
      (node (ref "U30") (pin "9") (pinfunction "EP_9") (pintype "passive"))
      (node (ref "U4") (pin "1") (pinfunction "CQM_1") (pintype "passive"))
      (node (ref "U4") (pin "12") (pinfunction "INCLK_12") (pintype "passive"))
      (node (ref "U4") (pin "2") (pinfunction "CMPLUS_2") (pintype "passive"))
      (node (ref "U4") (pin "3") (pinfunction "CMMINUS_3") (pintype "passive"))
      (node (ref "U4") (pin "49") (pinfunction "EP_49") (pintype "passive"))
      (node (ref "U5") (pin "1") (pinfunction "CQM_1") (pintype "passive"))
      (node (ref "U5") (pin "12") (pinfunction "INCLK_12") (pintype "passive"))
      (node (ref "U5") (pin "2") (pinfunction "CMPLUS_2") (pintype "passive"))
      (node (ref "U5") (pin "3") (pinfunction "CMMINUS_3") (pintype "passive"))
      (node (ref "U5") (pin "49") (pinfunction "EP_49") (pintype "passive"))
      (node (ref "U6") (pin "2") (pinfunction "GND_2") (pintype "passive"))
      (node (ref "U7") (pin "1") (pinfunction "CQM_1") (pintype "passive"))
      (node (ref "U7") (pin "12") (pinfunction "INCLK_12") (pintype "passive"))
      (node (ref "U7") (pin "2") (pinfunction "CMPLUS_2") (pintype "passive"))
      (node (ref "U7") (pin "3") (pinfunction "CMMINUS_3") (pintype "passive"))
      (node (ref "U7") (pin "49") (pinfunction "EP_49") (pintype "passive"))
      (node (ref "U8") (pin "1") (pinfunction "CQM_1") (pintype "passive"))
      (node (ref "U8") (pin "12") (pinfunction "INCLK_12") (pintype "passive"))
      (node (ref "U8") (pin "2") (pinfunction "CMPLUS_2") (pintype "passive"))
      (node (ref "U8") (pin "3") (pinfunction "CMMINUS_3") (pintype "passive"))
      (node (ref "U8") (pin "49") (pinfunction "EP_49") (pintype "passive"))
      (node (ref "U9") (pin "1") (pinfunction "CQM_1") (pintype "passive"))
      (node (ref "U9") (pin "12") (pinfunction "INCLK_12") (pintype "passive"))
      (node (ref "U9") (pin "2") (pinfunction "CMPLUS_2") (pintype "passive"))
      (node (ref "U9") (pin "3") (pinfunction "CMMINUS_3") (pintype "passive"))
      (node (ref "U9") (pin "49") (pinfunction "EP_49") (pintype "passive"))
    )
    (net (code "145") (name "Net-(C209-Pad1)") (class "Default")
      (node (ref "C209") (pin "1") (pinfunction "1_1") (pintype "passive"))
      (node (ref "R36") (pin "1") (pinfunction "1_1") (pintype "passive"))
      (node (ref "R37") (pin "2") (pinfunction "2_2") (pintype "passive"))
    )
    (net (code "146") (name "Net-(J4-Pad2)") (class "Default")
      (node (ref "J4") (pin "2") (pinfunction "2_2") (pintype "passive"))
      (node (ref "R41") (pin "1") (pinfunction "1_1") (pintype "passive"))
    )
    (net (code "147") (name "Net-(Q7-B)") (class "Default")
      (node (ref "Q7") (pin "1") (pinfunction "B_1") (pintype "passive"))
      (node (ref "R2") (pin "2") (pinfunction "2_2") (pintype "passive"))
    )
    (net (code "148") (name "Net-(Q8-B)") (class "Default")
      (node (ref "Q8") (pin "1") (pinfunction "B_1") (pintype "passive"))
      (node (ref "R8") (pin "2") (pinfunction "2_2") (pintype "passive"))
    )
    (net (code "149") (name "unconnected-(J3-Pad4)") (class "Default")
      (node (ref "J3") (pin "4") (pinfunction "4_4") (pintype "passive"))
    )
    (net (code "150") (name "unconnected-(U1-AN4{slash}C1IN2-{slash}USBOEN{slash}RPI36{slash}RB4-Pad12)") (class "Default")
      (node (ref "U1") (pin "12") (pinfunction "AN4/C1IN2-/USBOEN/RPI36/RB4_12") (pintype "passive"))
    )
    (net (code "151") (name "unconnected-(U1-AN5{slash}C1IN1+{slash}VBUSON{slash}VBUSST{slash}RPI37{slash}RB5-Pad11)") (class "Default")
      (node (ref "U1") (pin "11") (pinfunction "AN5/C1IN1+/VBUSON/VBUSST/RPI37/RB5_11") (pintype "passive"))
    )
    (net (code "152") (name "unconnected-(U1-AN8{slash}PMA6{slash}RPI40{slash}RB8-Pad21)") (class "Default")
      (node (ref "U1") (pin "21") (pinfunction "AN8/PMA6/RPI40/RB8_21") (pintype "passive"))
    )
    (net (code "153") (name "unconnected-(U1-AN9{slash}PMA7{slash}{slash}RPI41{slash}RB9-Pad22)") (class "Default")
      (node (ref "U1") (pin "22") (pinfunction "AN9/PMA7//RPI41/RB9_22") (pintype "passive"))
    )
    (net (code "154") (name "unconnected-(U1-AN14{slash}PMA1{slash}RPI46{slash}RB14-Pad29)") (class "Default")
      (node (ref "U1") (pin "29") (pinfunction "AN14/PMA1/RPI46/RB14_29") (pintype "passive"))
    )
    (net (code "155") (name "unconnected-(U1-AN15{slash}PMA0{slash}RPI47{slash}RB15-Pad30)") (class "Default")
      (node (ref "U1") (pin "30") (pinfunction "AN15/PMA0/RPI47/RB15_30") (pintype "passive"))
    )
    (net (code "156") (name "unconnected-(U1-C2IN1-{slash}PMA2{slash}RPI121{slash}RG9-Pad8)") (class "Default")
      (node (ref "U1") (pin "8") (pinfunction "C2IN1-/PMA2/RPI121/RG9_8") (pintype "passive"))
    )
    (net (code "157") (name "unconnected-(U1-C3IN1+{slash}VCMPST3{slash}RP71{slash}RD7-Pad55)") (class "Default")
      (node (ref "U1") (pin "55") (pinfunction "C3IN1+/VCMPST3/RP71/RD7_55") (pintype "passive"))
    )
    (net (code "158") (name "unconnected-(U1-C3IN2-{slash}RP70{slash}RD6-Pad54)") (class "Default")
      (node (ref "U1") (pin "54") (pinfunction "C3IN2-/RP70/RD6_54") (pintype "passive"))
    )
    (net (code "159") (name "unconnected-(U1-INT0{slash}DMH{slash}RP64{slash}RD0-Pad46)") (class "Default")
      (node (ref "U1") (pin "46") (pinfunction "INT0/DMH/RP64/RD0_46") (pintype "passive"))
    )
    (net (code "160") (name "unconnected-(U1-PGEC2{slash}SOSCO{slash}C3IN1-{slash}T1CK{slash}RPI62{slash}RC14-Pad48)") (class "Default")
      (node (ref "U1") (pin "48") (pinfunction "PGEC2/SOSCO/C3IN1-/T1CK/RPI62/RC14_48") (pintype "passive"))
    )
    (net (code "161") (name "unconnected-(U1-PGED2{slash}SOSCI{slash}C3IN3-{slash}RPI61{slash}RC13-Pad47)") (class "Default")
      (node (ref "U1") (pin "47") (pinfunction "PGED2/SOSCI/C3IN3-/RPI61/RC13_47") (pintype "passive"))
    )
    (net (code "162") (name "unconnected-(U1-PMRD{slash}RP69{slash}RD5-Pad53)") (class "Default")
      (node (ref "U1") (pin "53") (pinfunction "PMRD/RP69/RD5_53") (pintype "passive"))
    )
    (net (code "163") (name "unconnected-(U1-PMWR{slash}RP68{slash}RD4-Pad52)") (class "Default")
      (node (ref "U1") (pin "52") (pinfunction "PMWR/RP68/RD4_52") (pintype "passive"))
    )
    (net (code "164") (name "unconnected-(U1-TCK{slash}AN12{slash}PMA11{slash}RPI44{slash}RB12-Pad27)") (class "Default")
      (node (ref "U1") (pin "27") (pinfunction "TCK/AN12/PMA11/RPI44/RB12_27") (pintype "passive"))
    )
    (net (code "165") (name "unconnected-(U1-TDI{slash}AN13{slash}PMA10{slash}RPI45{slash}RB13-Pad28)") (class "Default")
      (node (ref "U1") (pin "28") (pinfunction "TDI/AN13/PMA10/RPI45/RB13_28") (pintype "passive"))
    )
    (net (code "166") (name "unconnected-(U1-TDO{slash}AN11{slash}PMA12{slash}RPI43{slash}RB11-Pad24)") (class "Default")
      (node (ref "U1") (pin "24") (pinfunction "TDO/AN11/PMA12/RPI43/RB11_24") (pintype "passive"))
    )
    (net (code "167") (name "unconnected-(U1-TMS{slash}AN10{slash}CVREF{slash}PMA13{slash}RPI42{slash}RB10-Pad23)") (class "Default")
      (node (ref "U1") (pin "23") (pinfunction "TMS/AN10/CVREF/PMA13/RPI42/RB10_23") (pintype "passive"))
    )
    (net (code "168") (name "unconnected-(U1-USBID{slash}RP99{slash}RF3-Pad33)") (class "Default")
      (node (ref "U1") (pin "33") (pinfunction "USBID/RP99/RF3_33") (pintype "passive"))
    )
    (net (code "169") (name "unconnected-(U6-NC-Pad4)") (class "Default")
      (node (ref "U6") (pin "4") (pinfunction "NC_4") (pintype "passive"))
    )
    (net (code "170") (name "unconnected-(U19-GND-Pad2)") (class "Default")
      (node (ref "U19") (pin "2") (pinfunction "GND_2") (pintype "passive"))
    )
    (net (code "171") (name "unconnected-(U19-GND-Pad3)") (class "Default")
      (node (ref "U19") (pin "3") (pinfunction "GND_3") (pintype "passive"))
    )
    (net (code "172") (name "unconnected-(U19-N.C.-Pad4)") (class "Default")
      (node (ref "U19") (pin "4") (pinfunction "N.C._4") (pintype "passive"))
    )
    (net (code "173") (name "unconnected-(U21-Vref-Pad5)") (class "Default")
      (node (ref "U21") (pin "5") (pinfunction "Vref_5") (pintype "passive"))
    )
    (net (code "174") (name "unconnected-(U24-GND-Pad2)") (class "Default")
      (node (ref "U24") (pin "2") (pinfunction "GND_2") (pintype "passive"))
    )
    (net (code "175") (name "unconnected-(U24-GND-Pad3)") (class "Default")
      (node (ref "U24") (pin "3") (pinfunction "GND_3") (pintype "passive"))
    )
    (net (code "176") (name "unconnected-(U24-N.C.-Pad4)") (class "Default")
      (node (ref "U24") (pin "4") (pinfunction "N.C._4") (pintype "passive"))
    )
  )
)
